# mpiovd.net
KiCad netlist of a schematic drawn in EAGLE
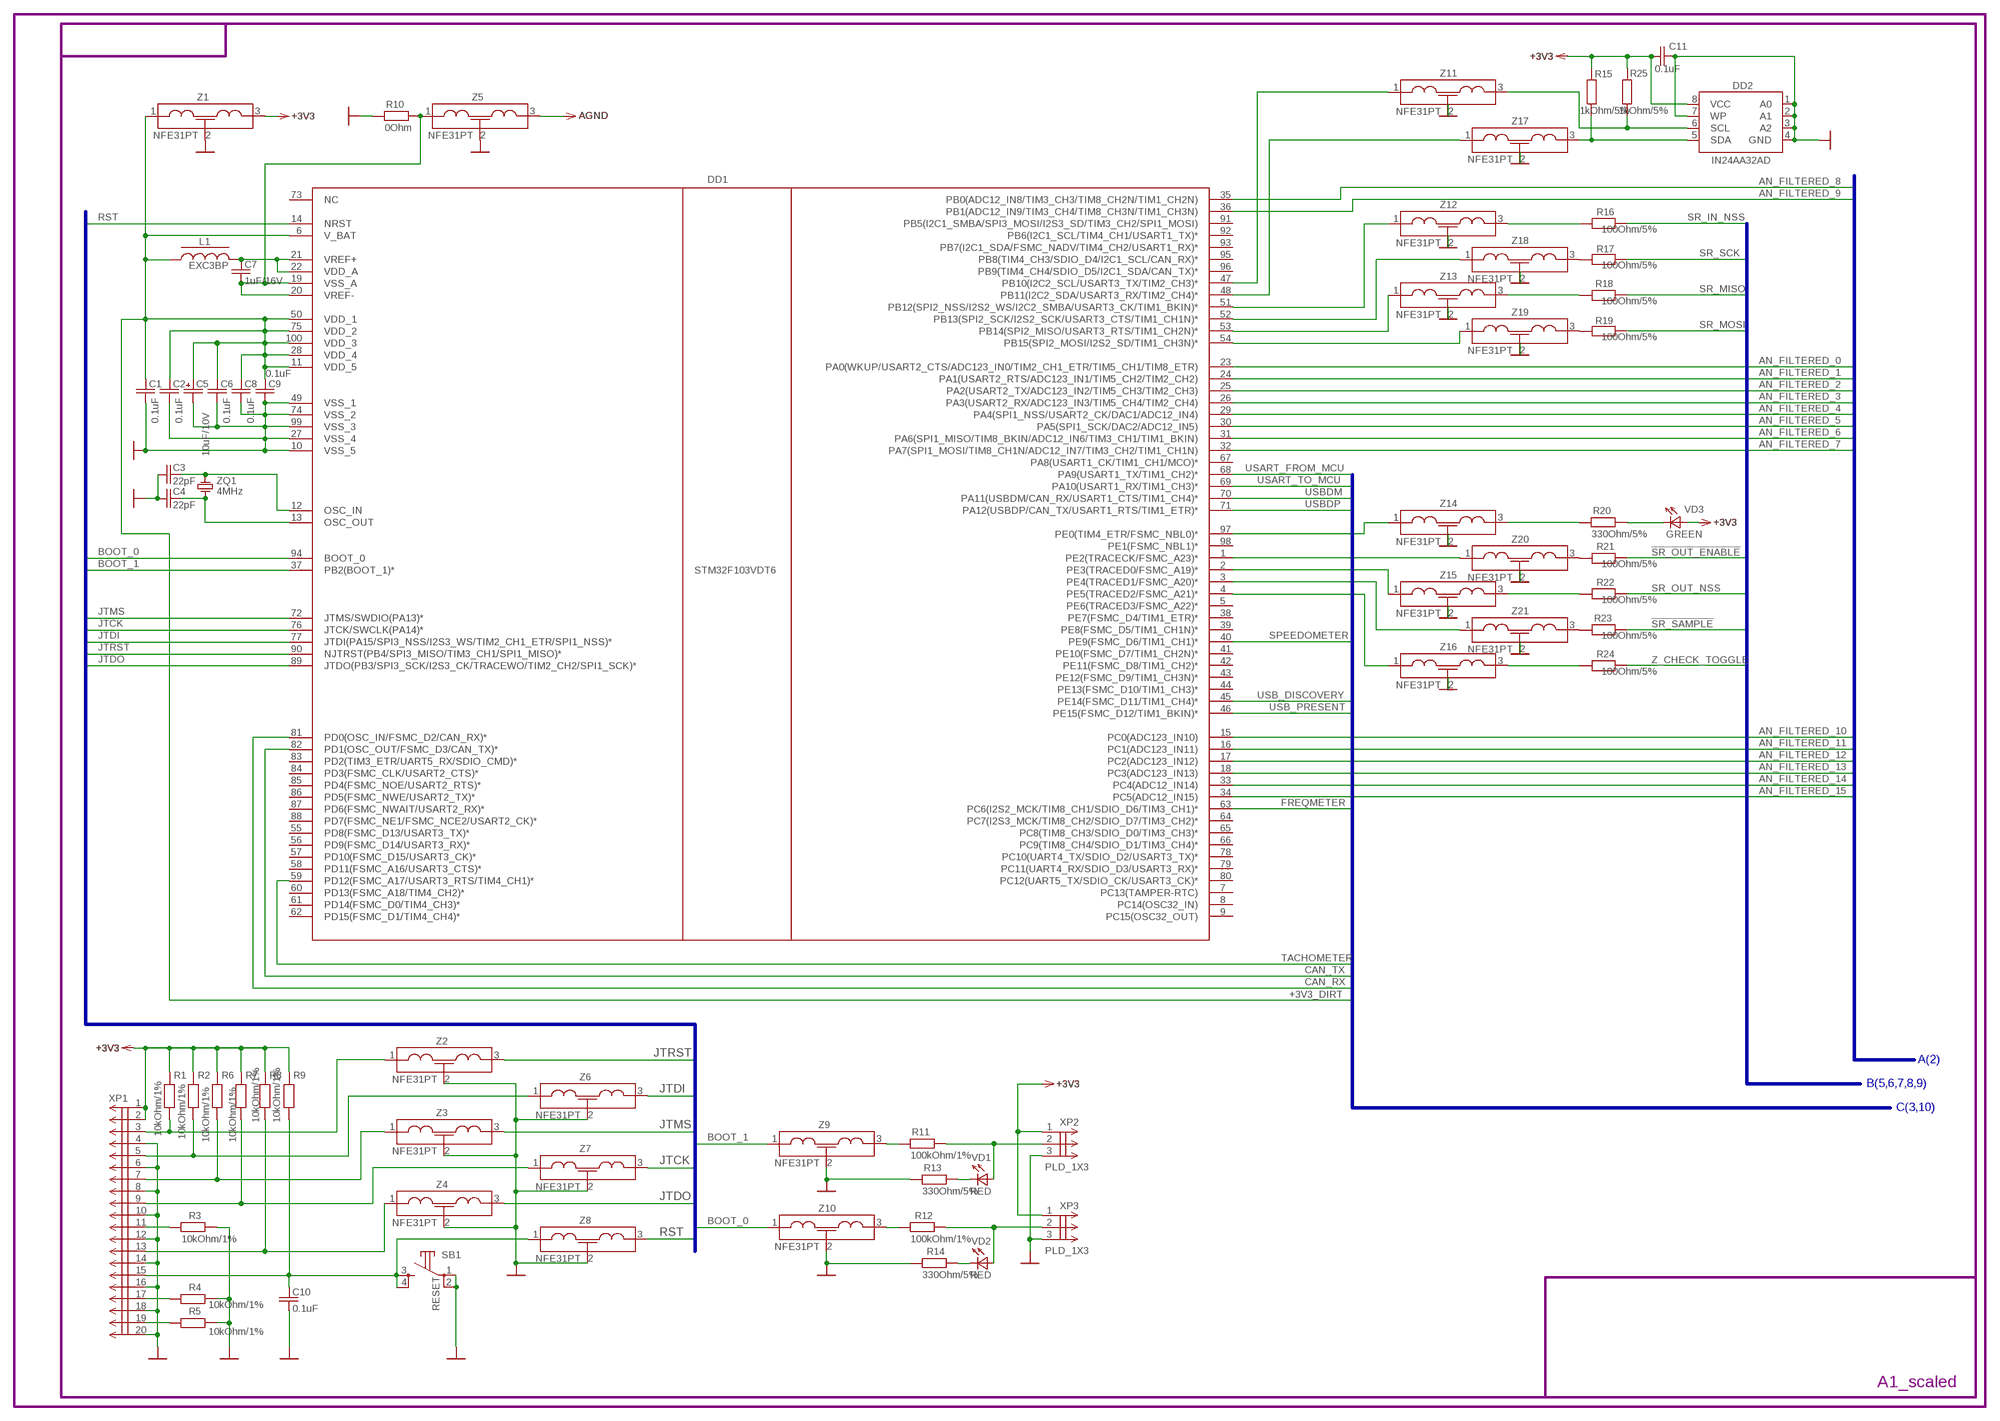
[diagram p0: schematic, sheet 1]
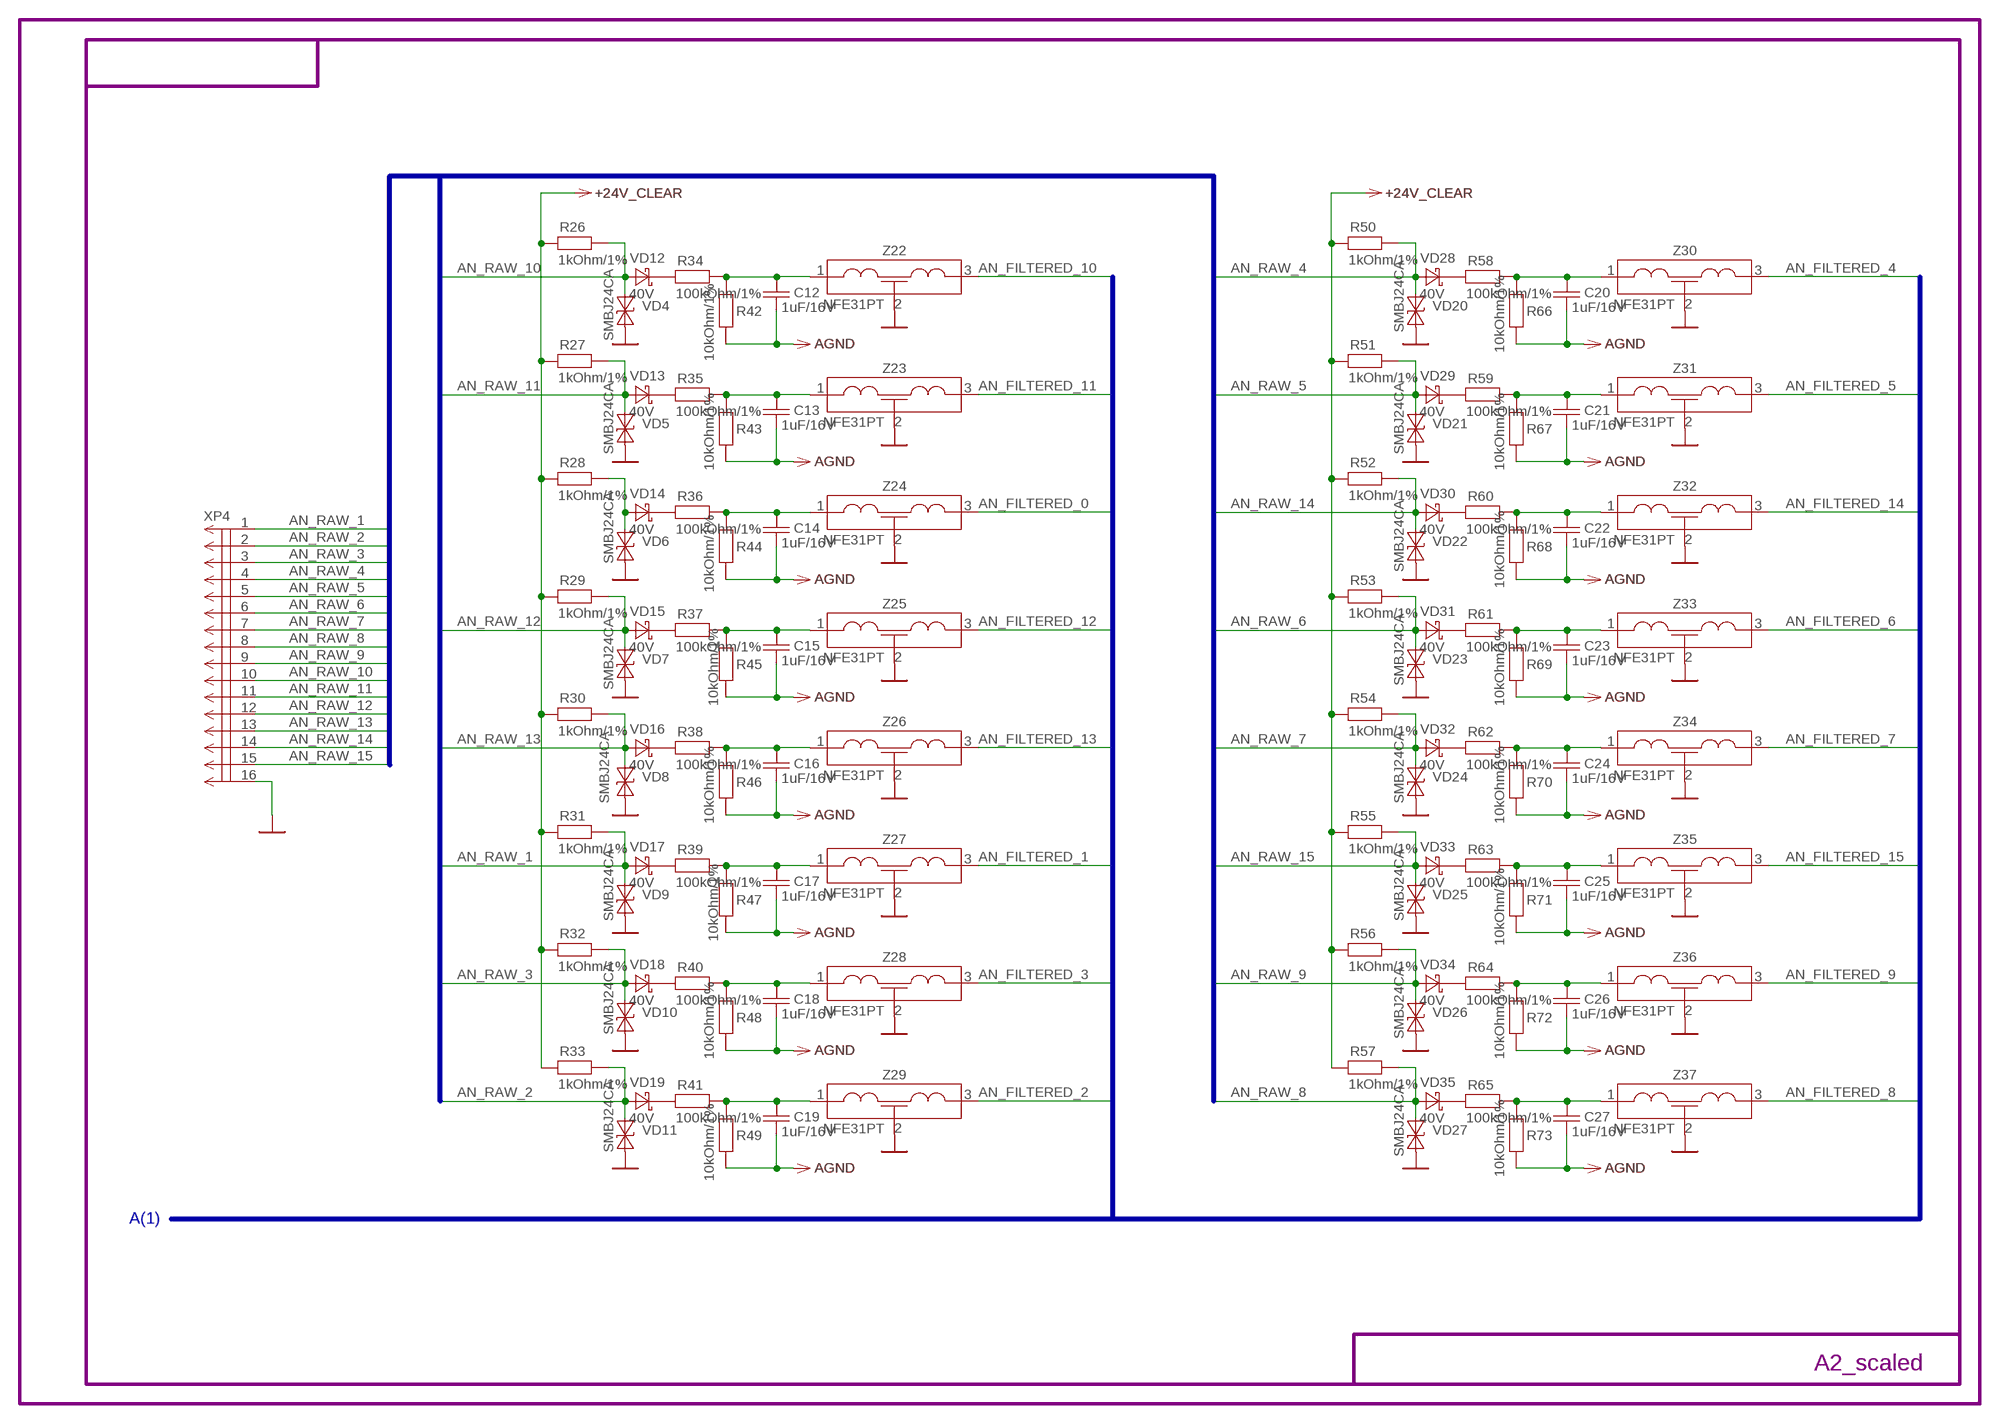
[diagram p1: schematic, sheet 2]
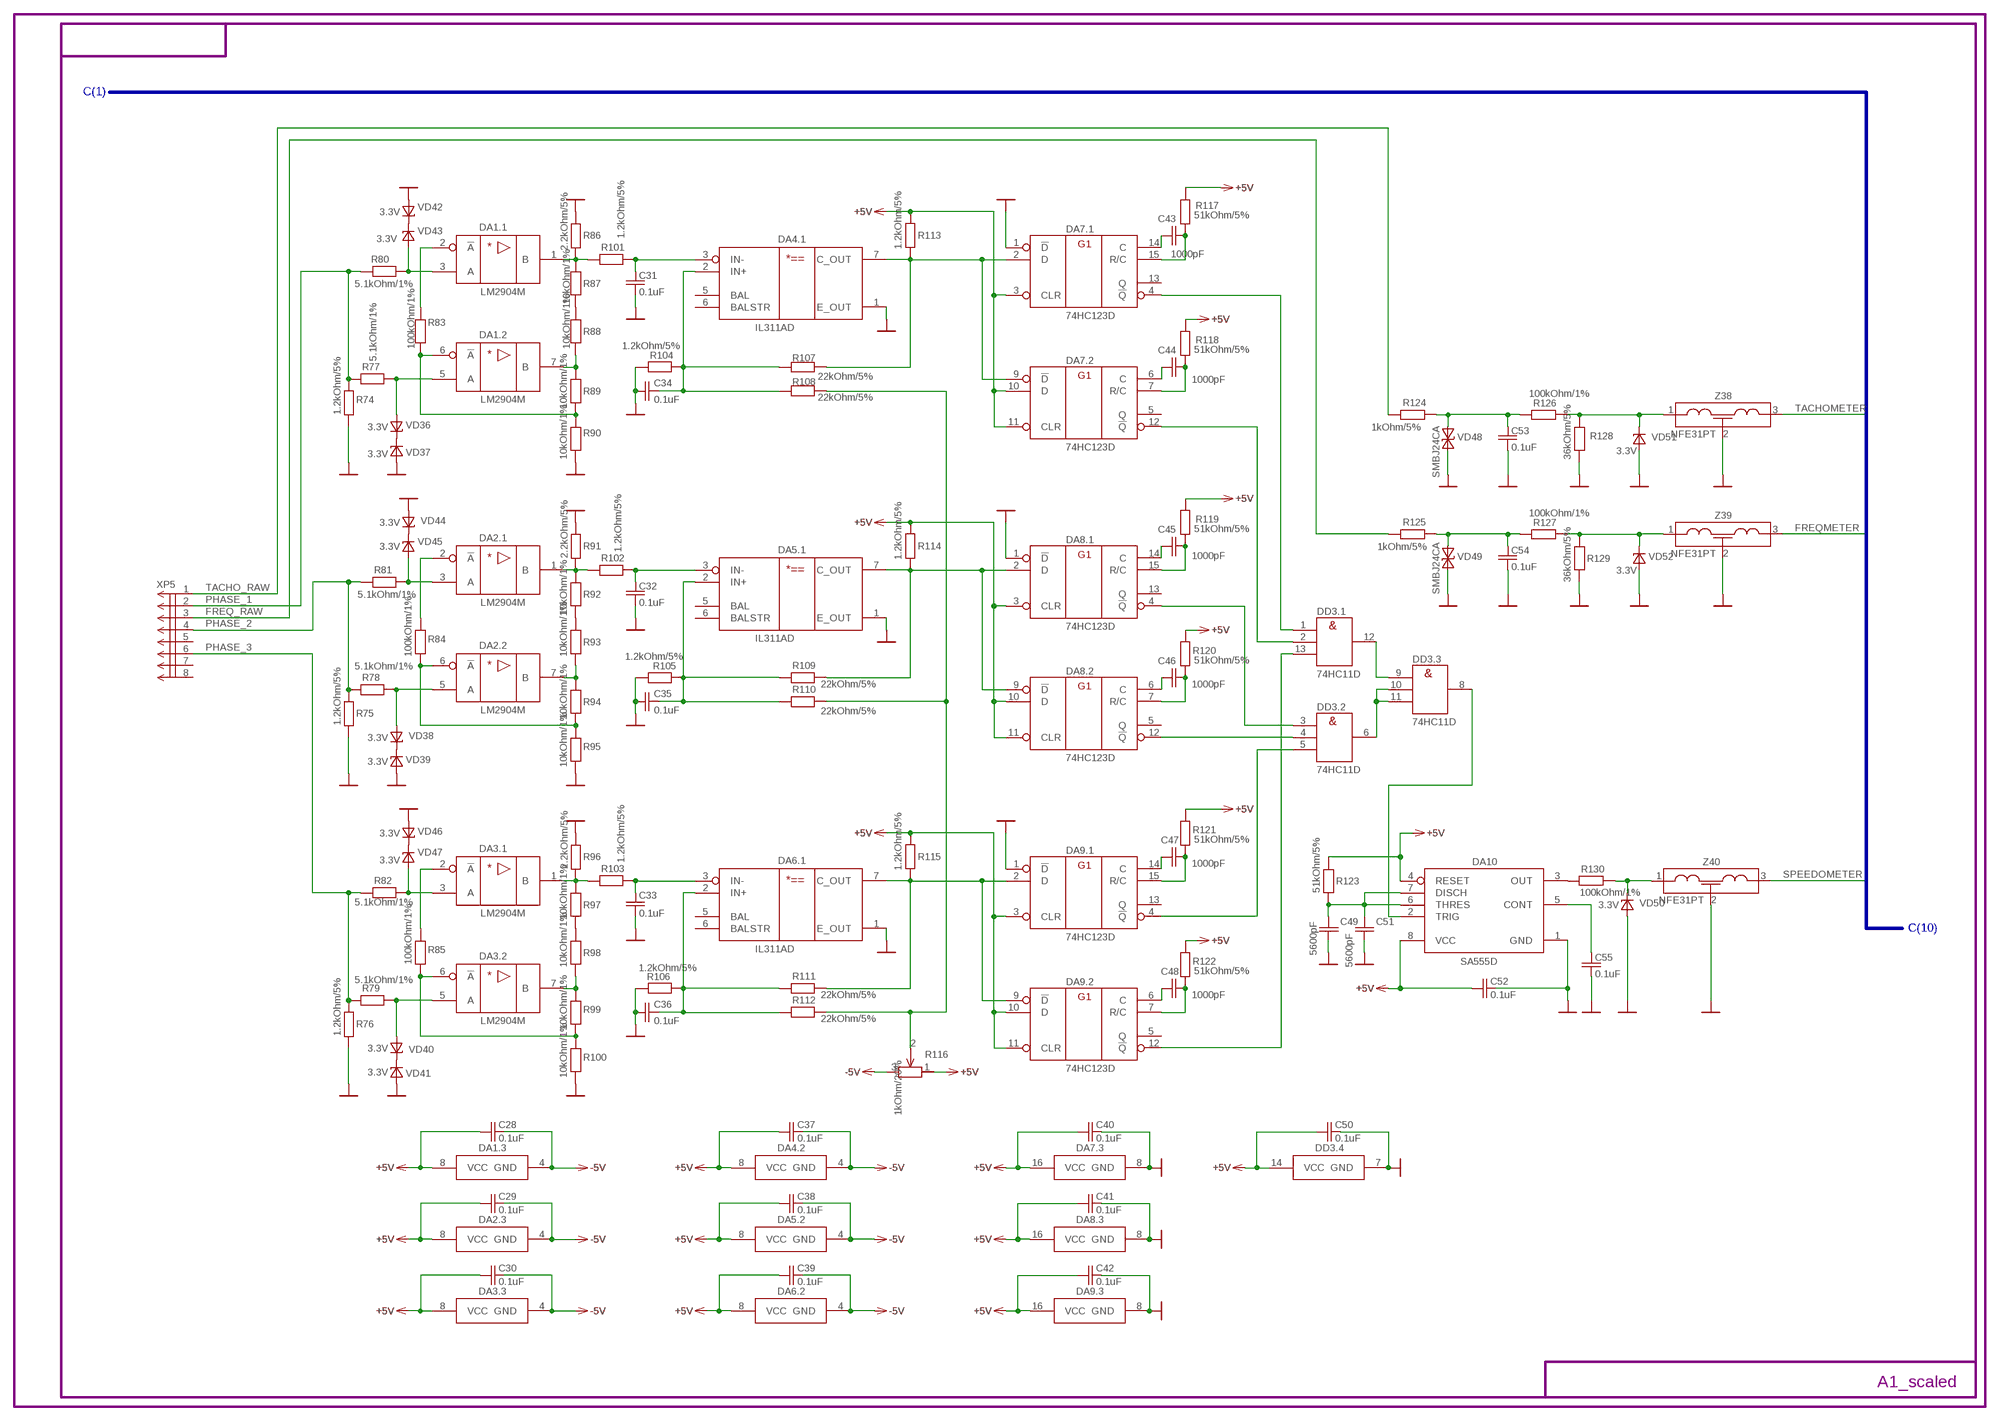
[diagram p2: schematic, sheet 3]
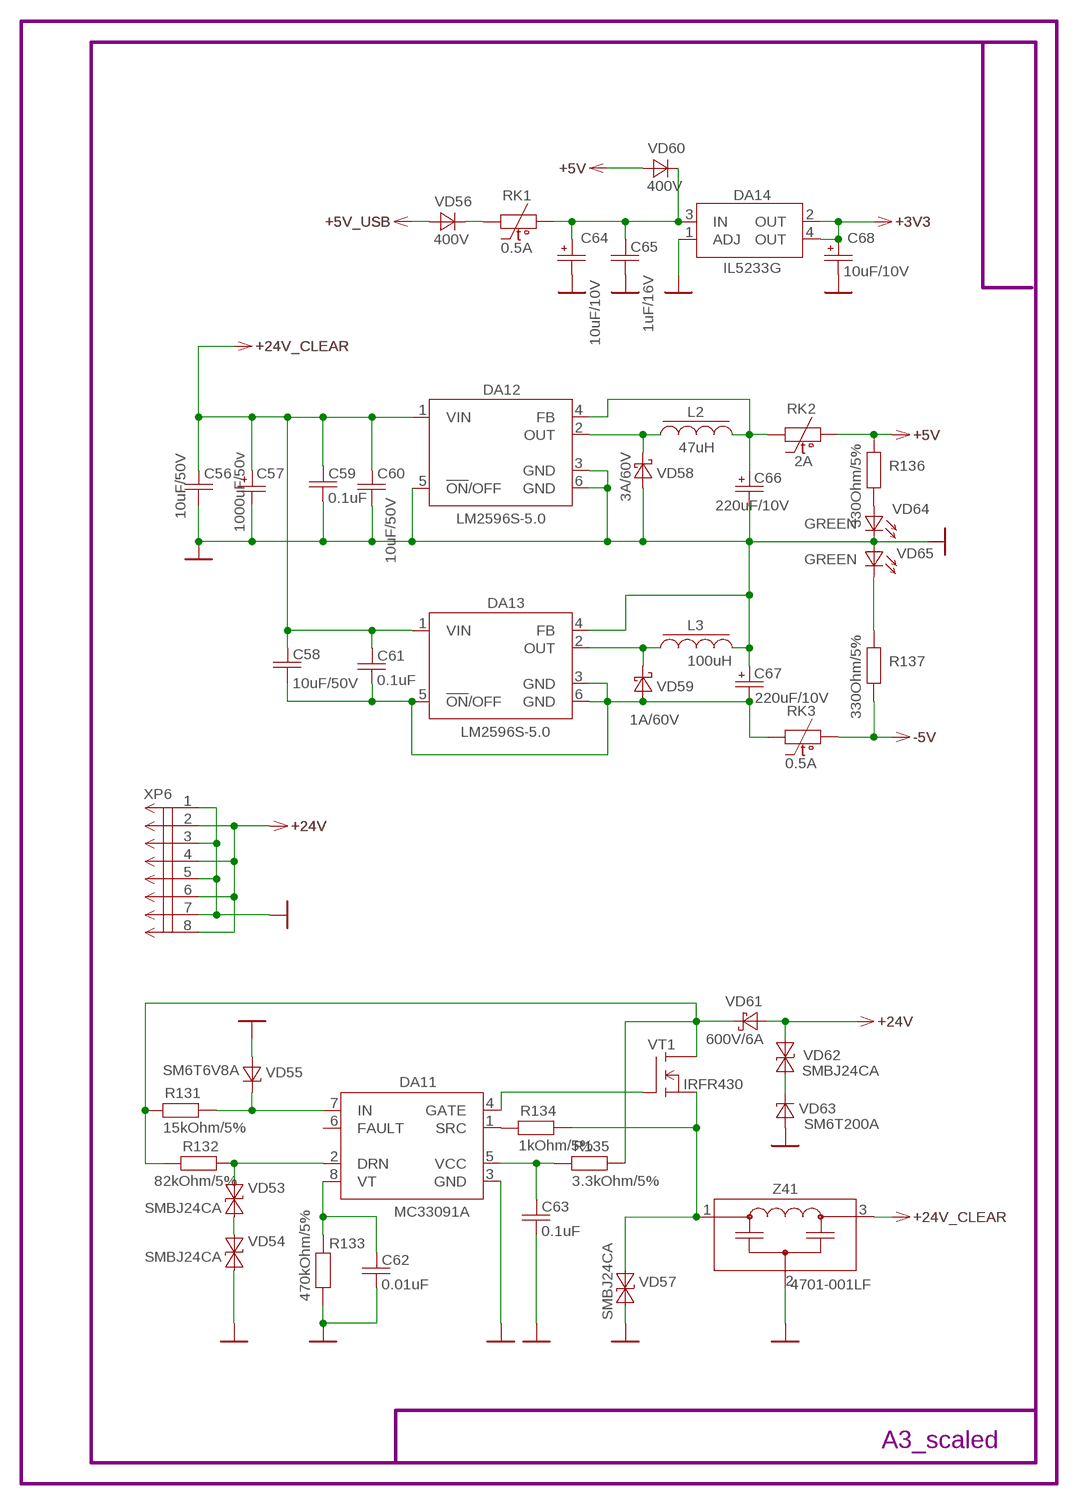
[diagram p3: schematic, sheet 4]
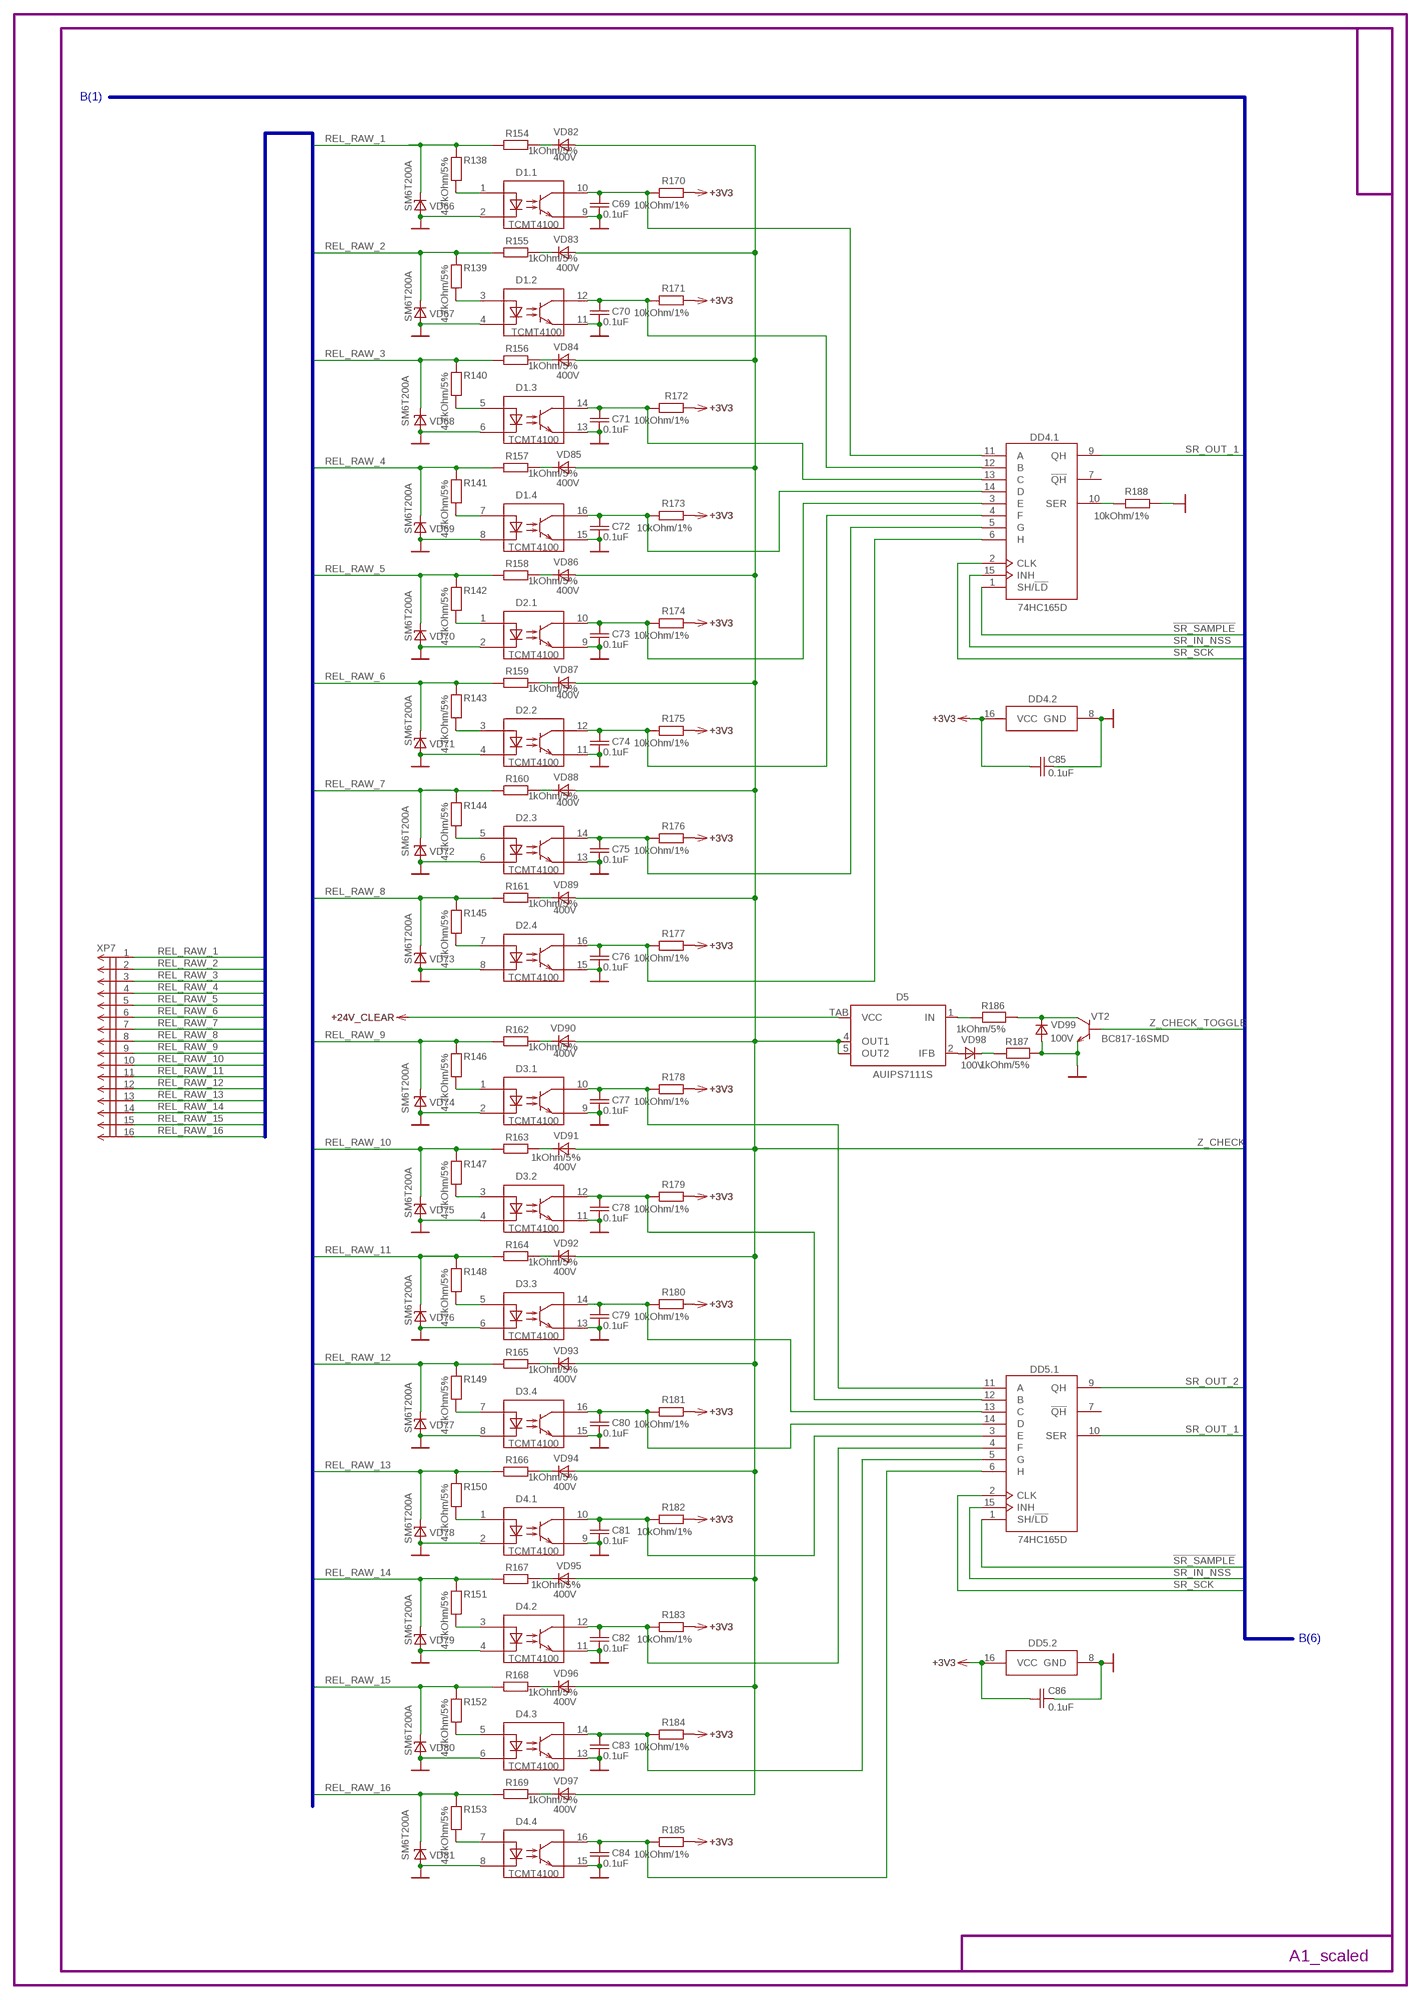
[diagram p4: schematic, sheet 5]
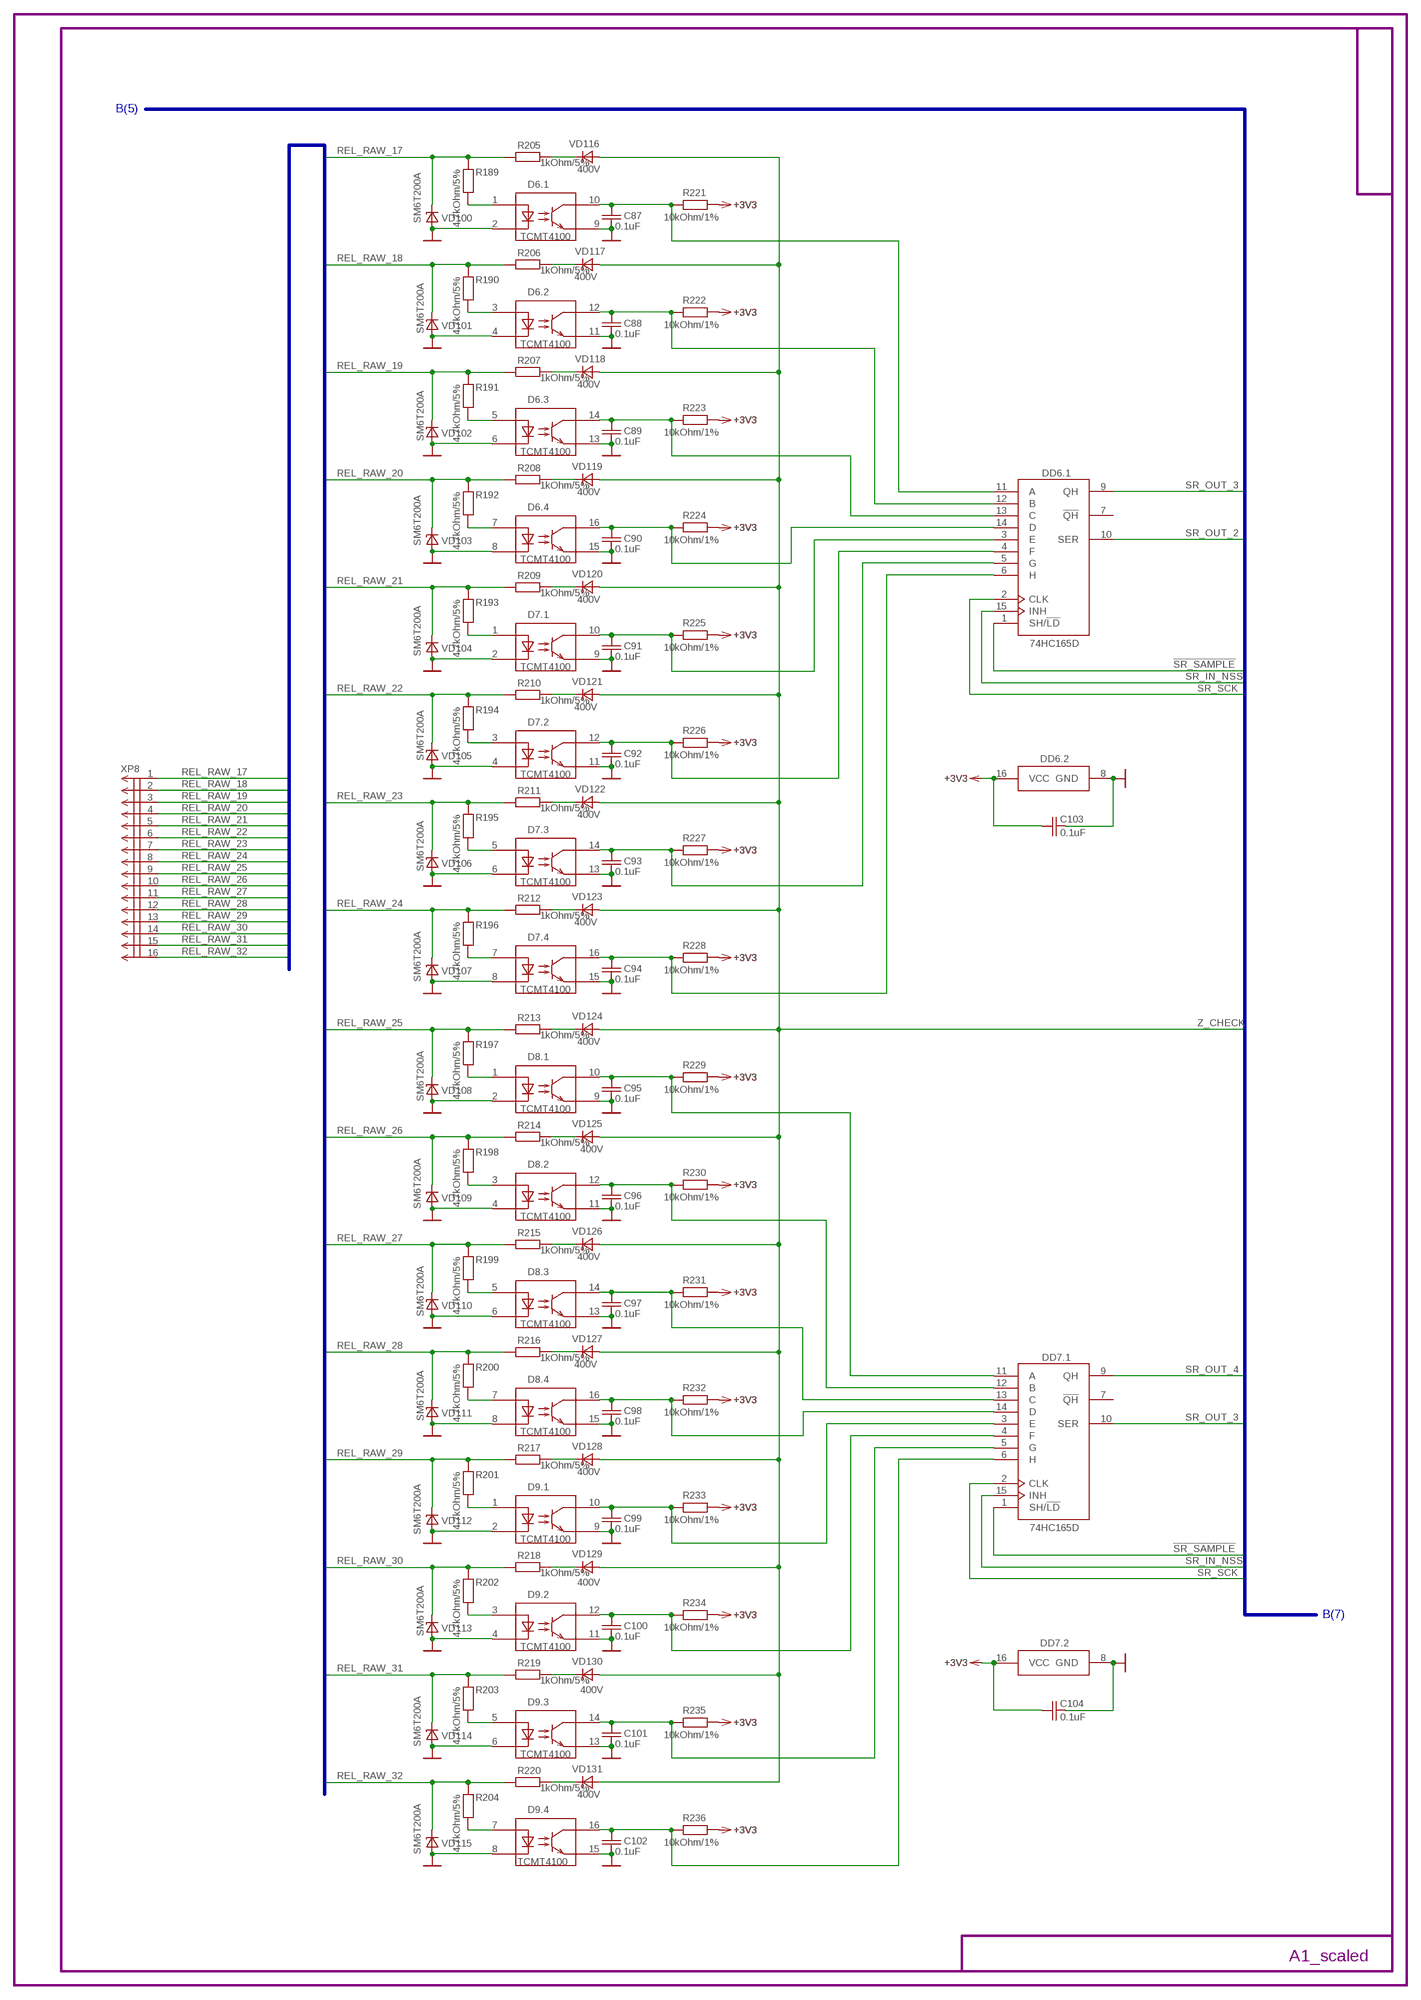
[diagram p5: schematic, sheet 6]
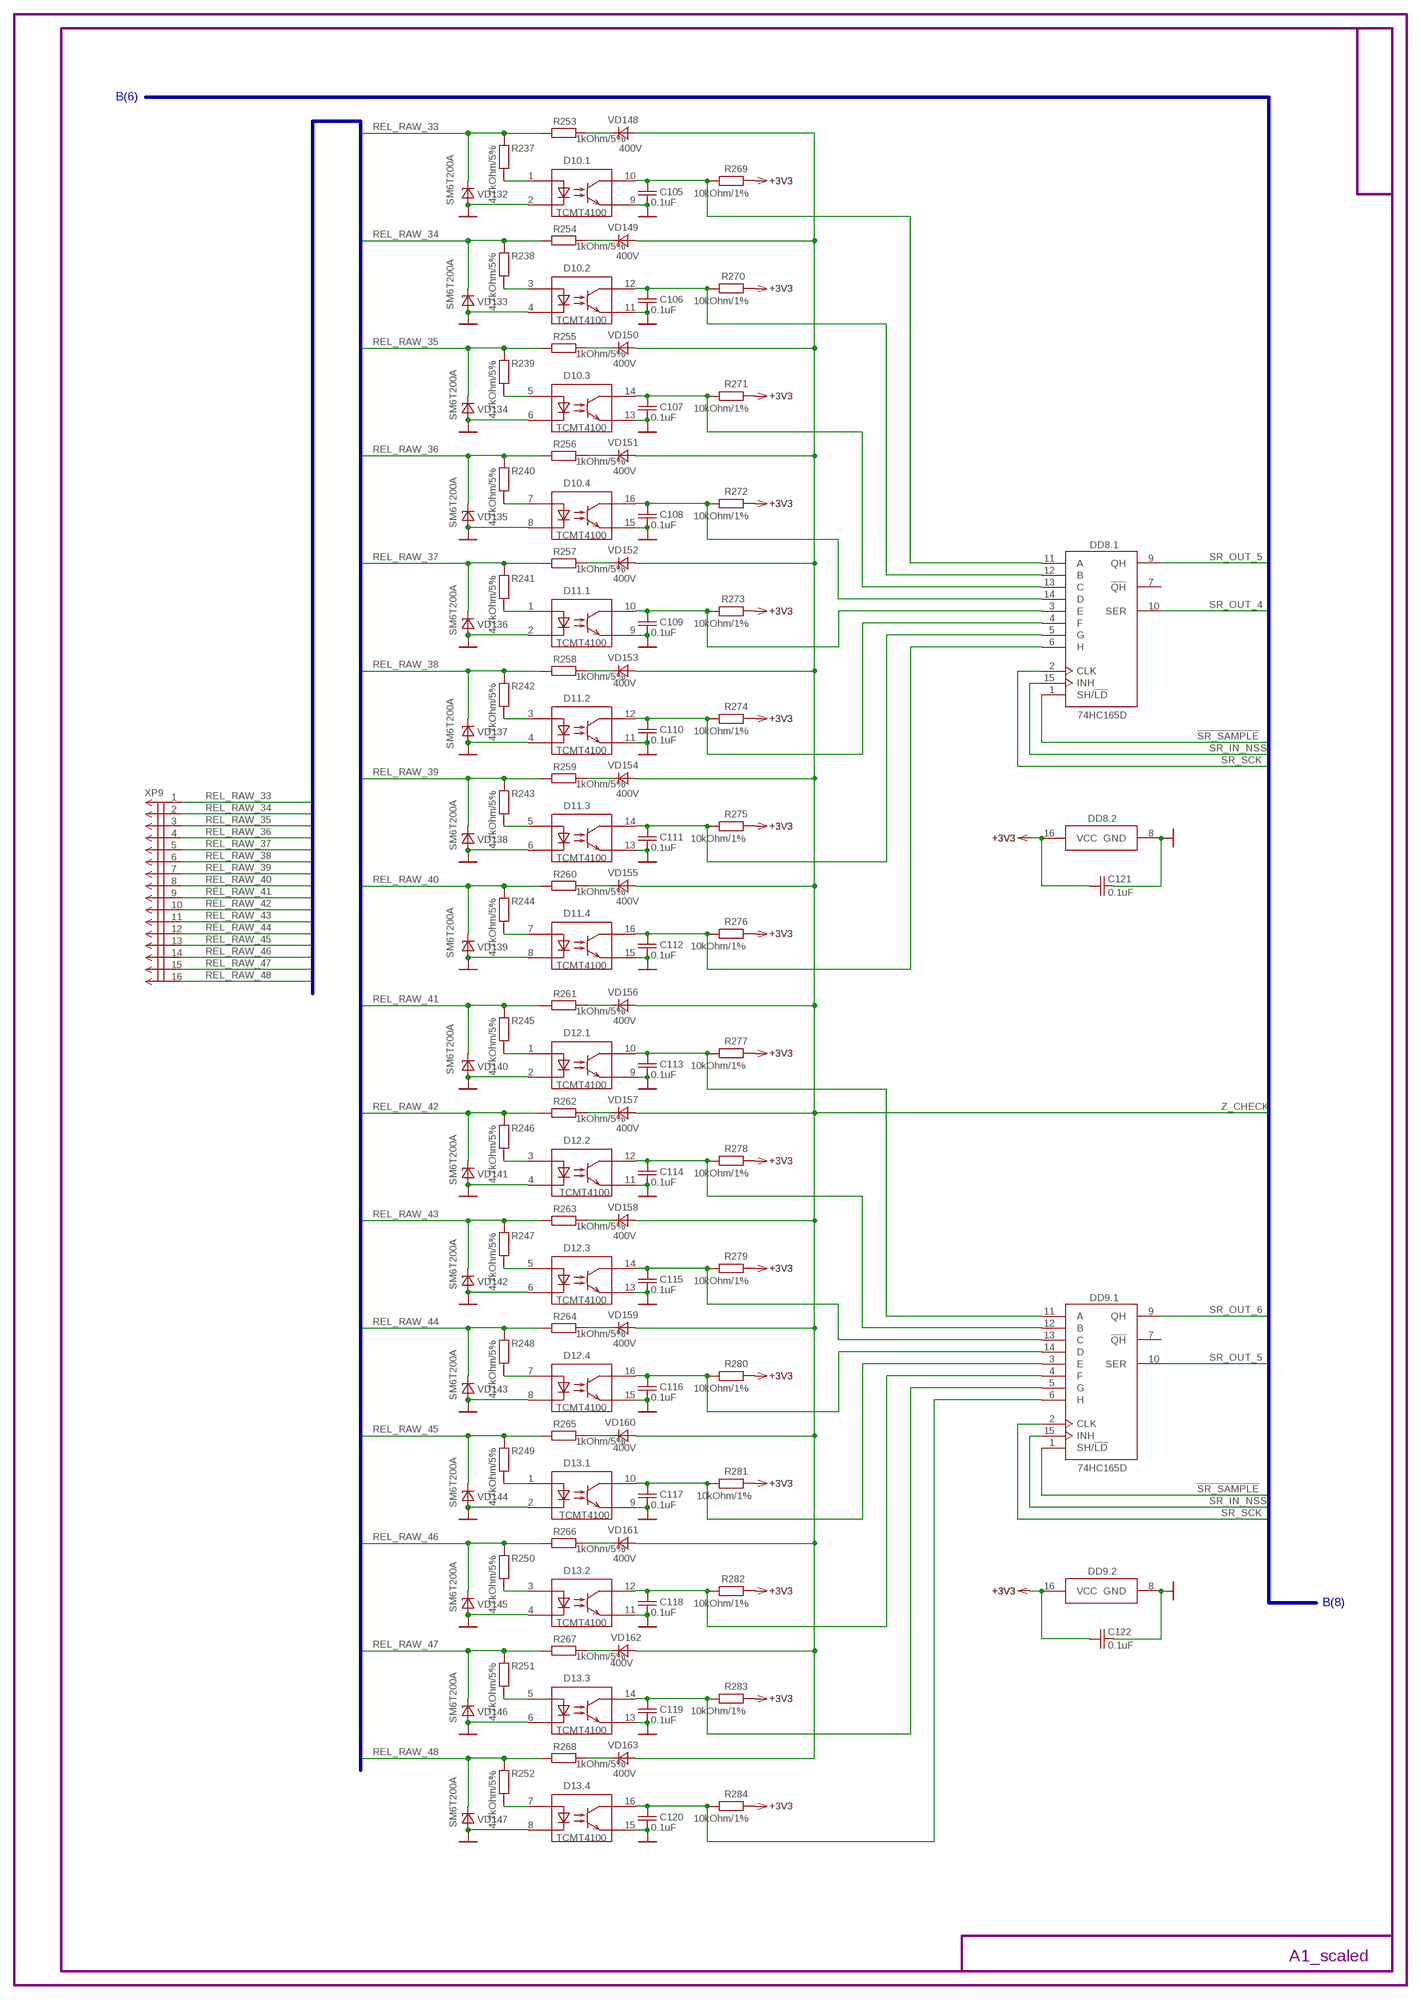
[diagram p6: schematic, sheet 7]
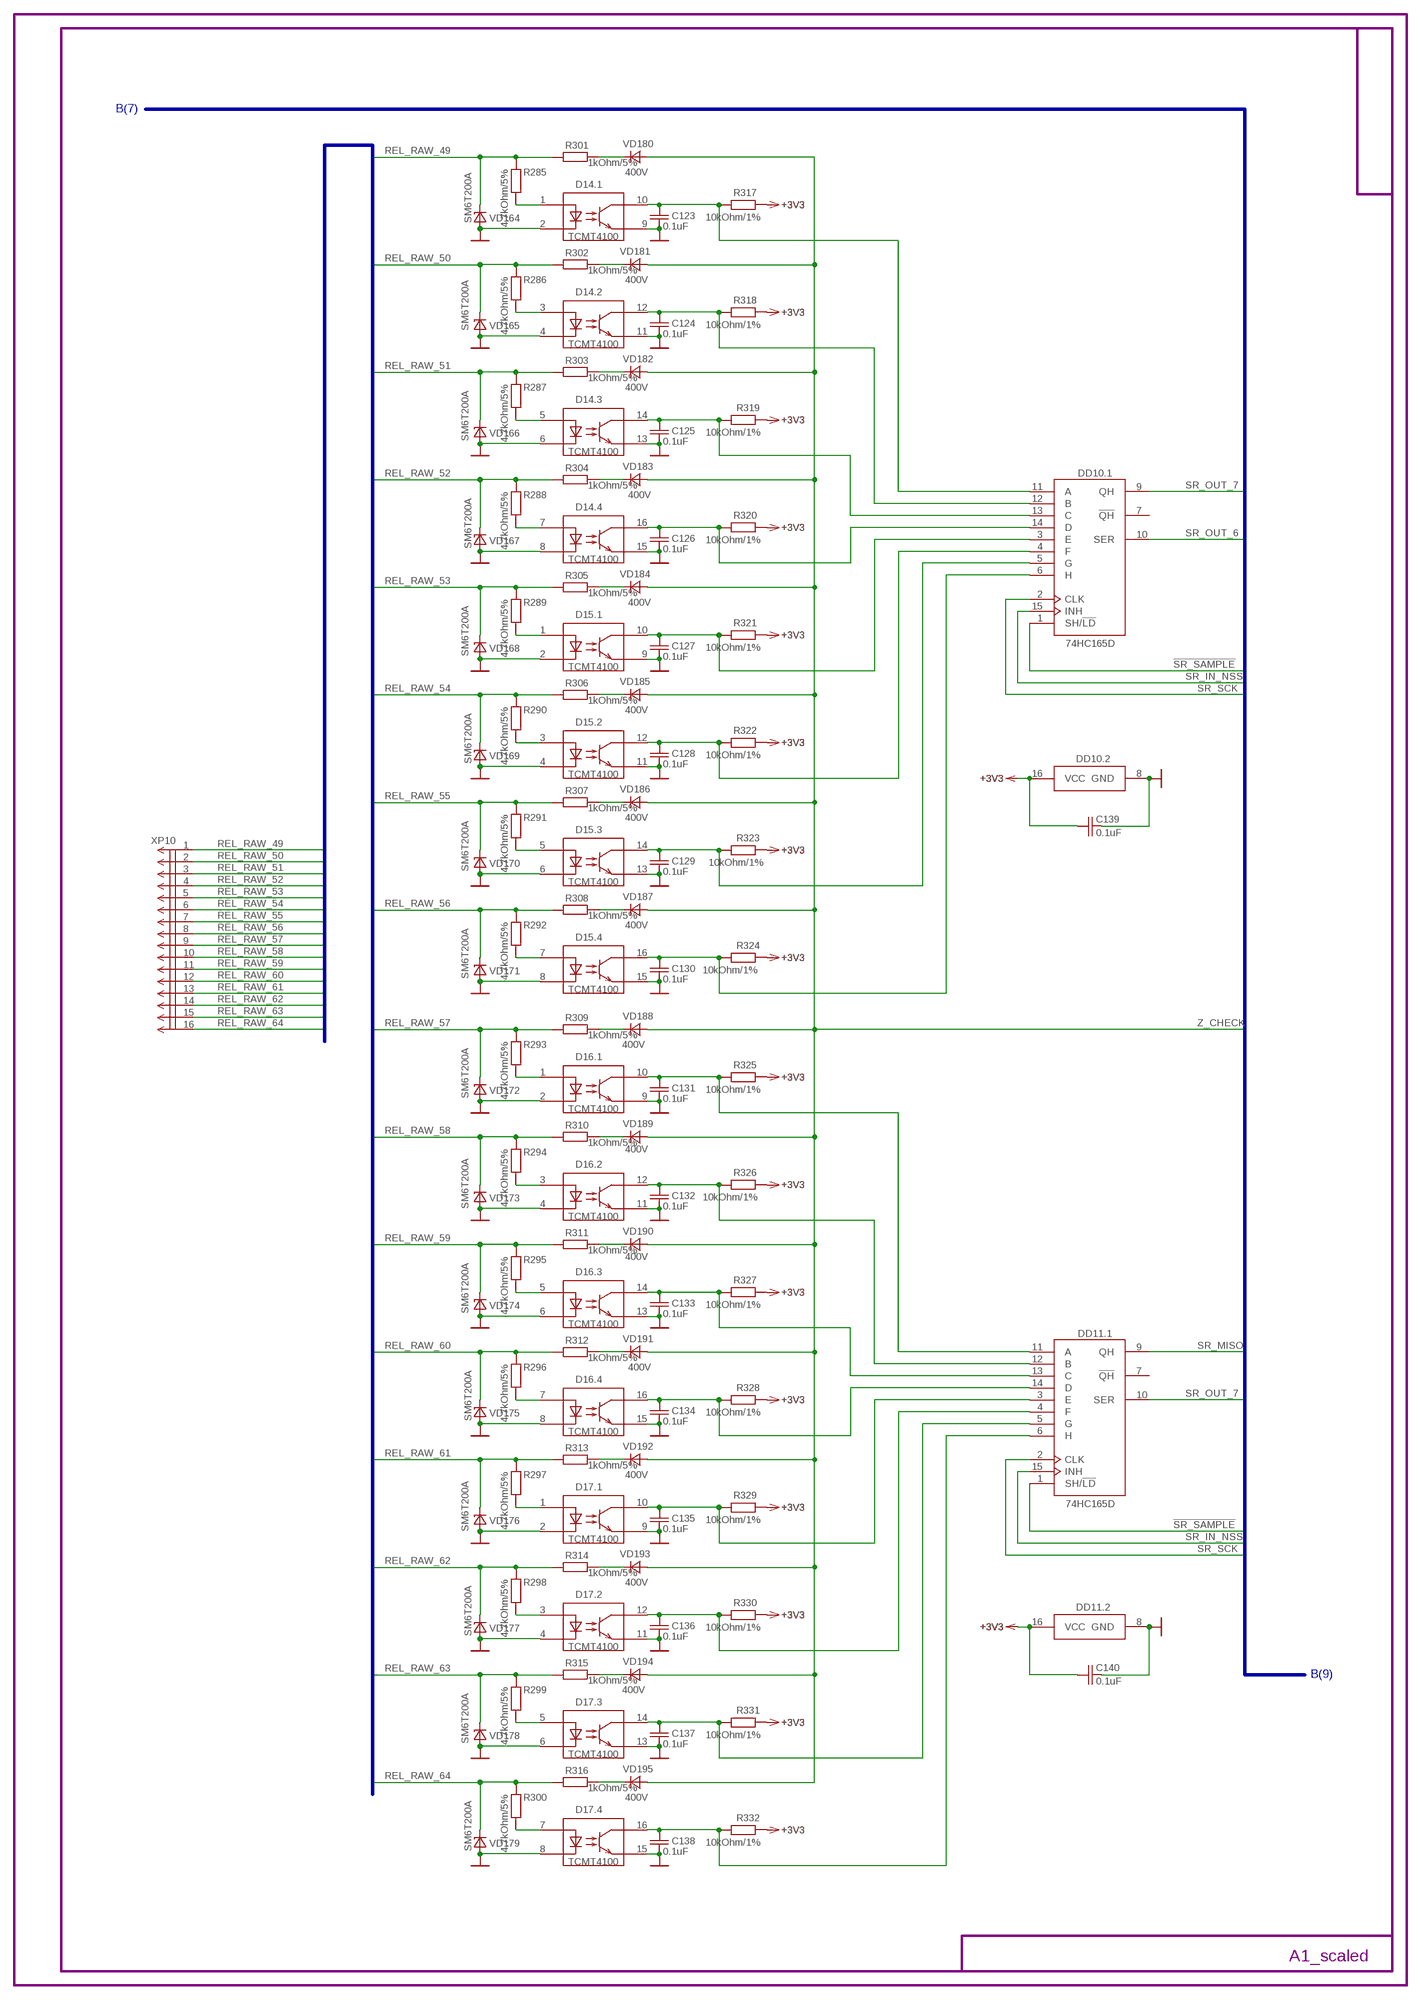
[diagram p7: schematic, sheet 8]
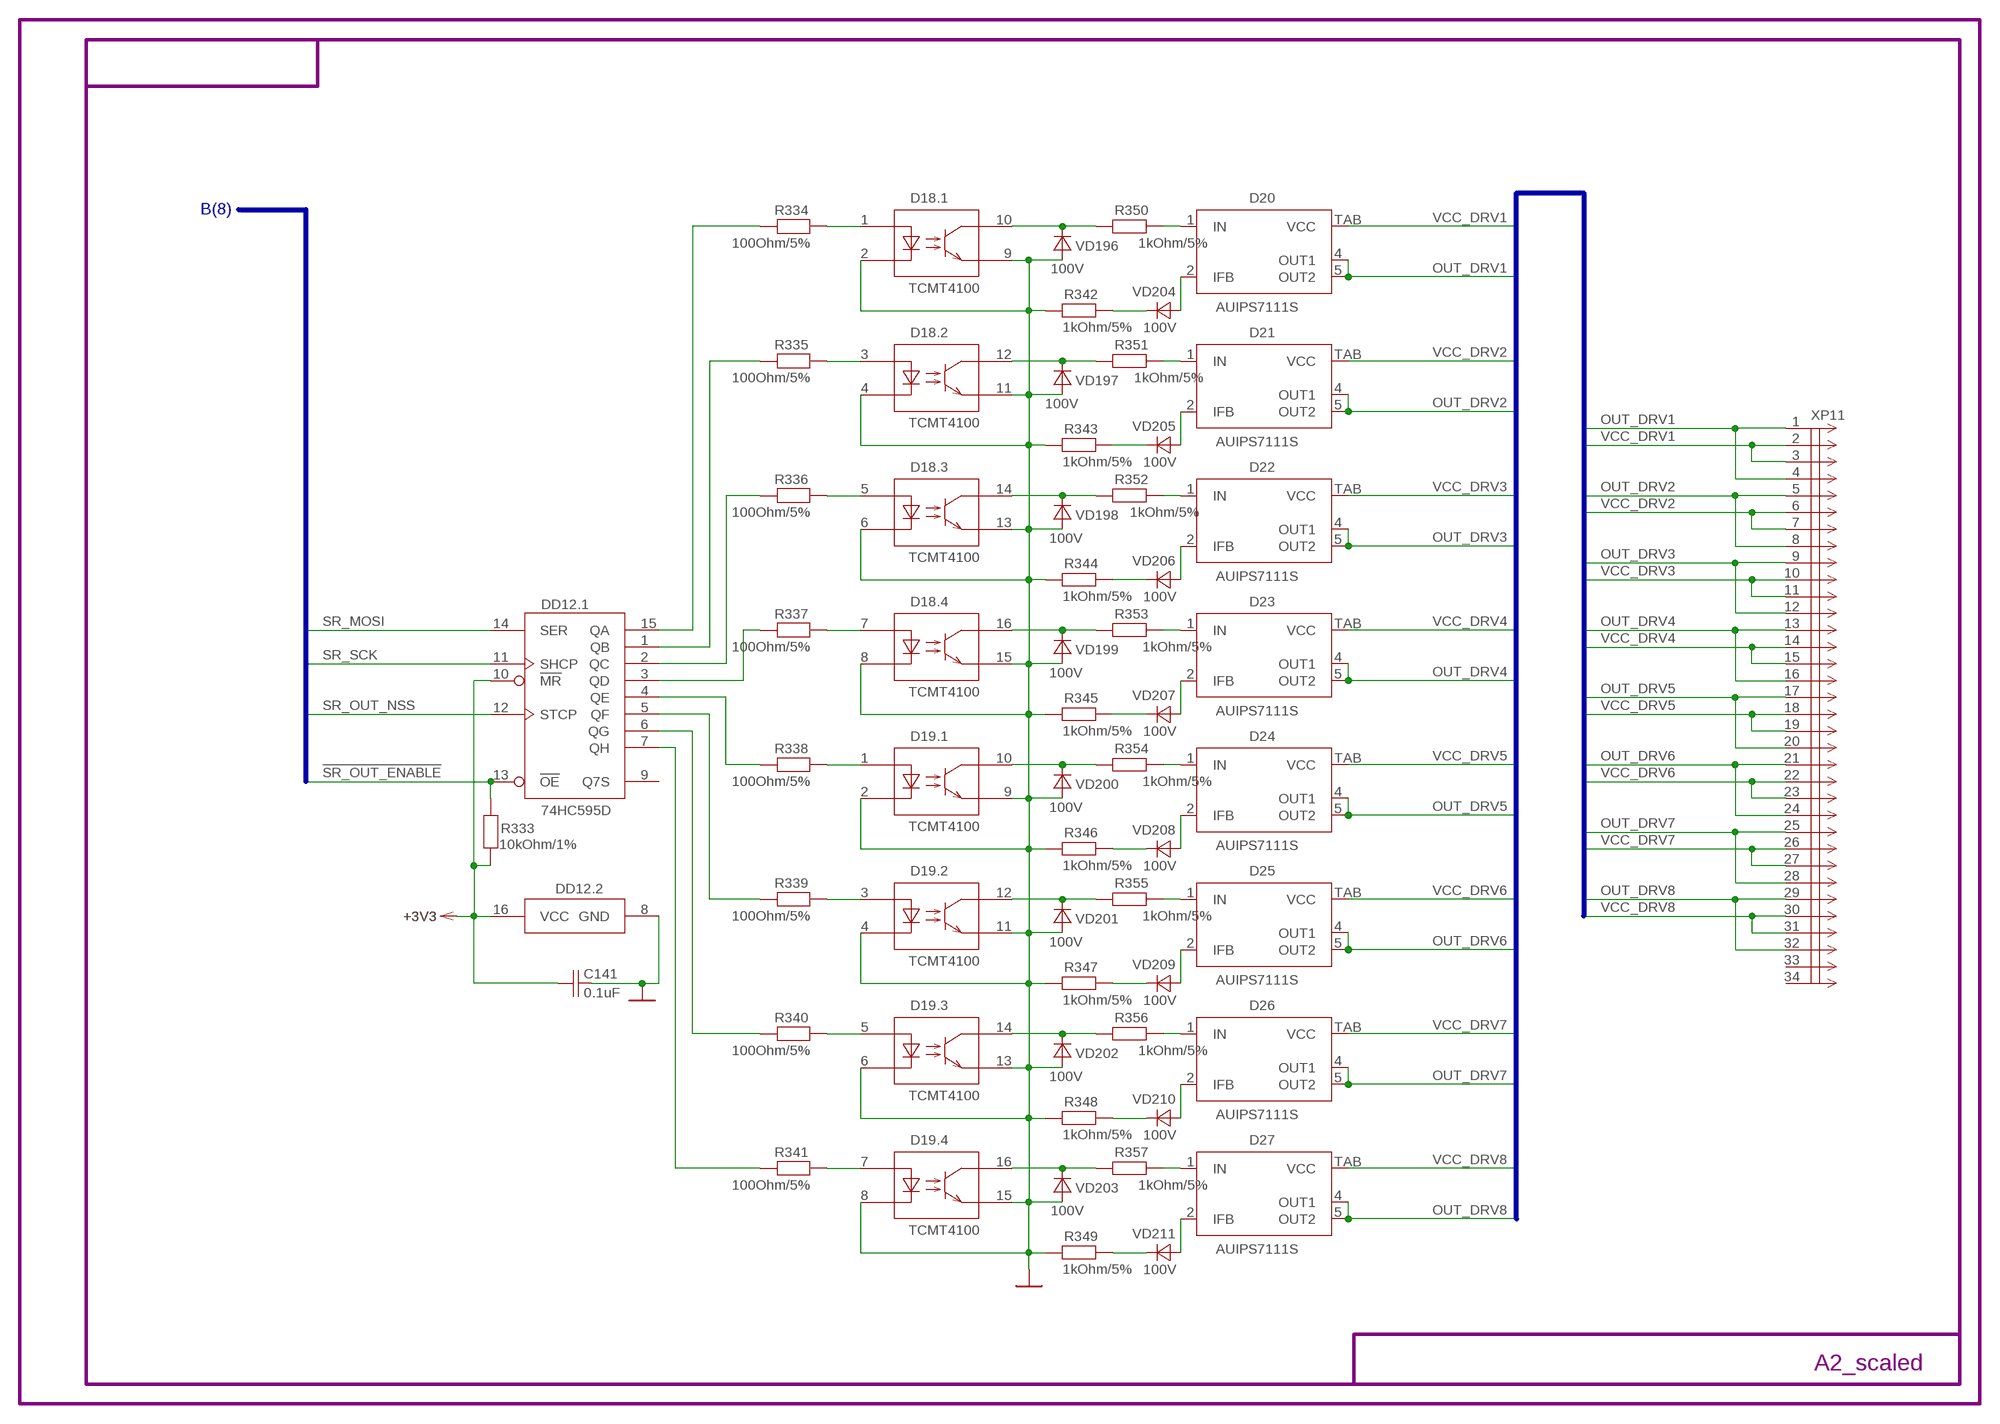
[diagram p8: schematic, sheet 9]
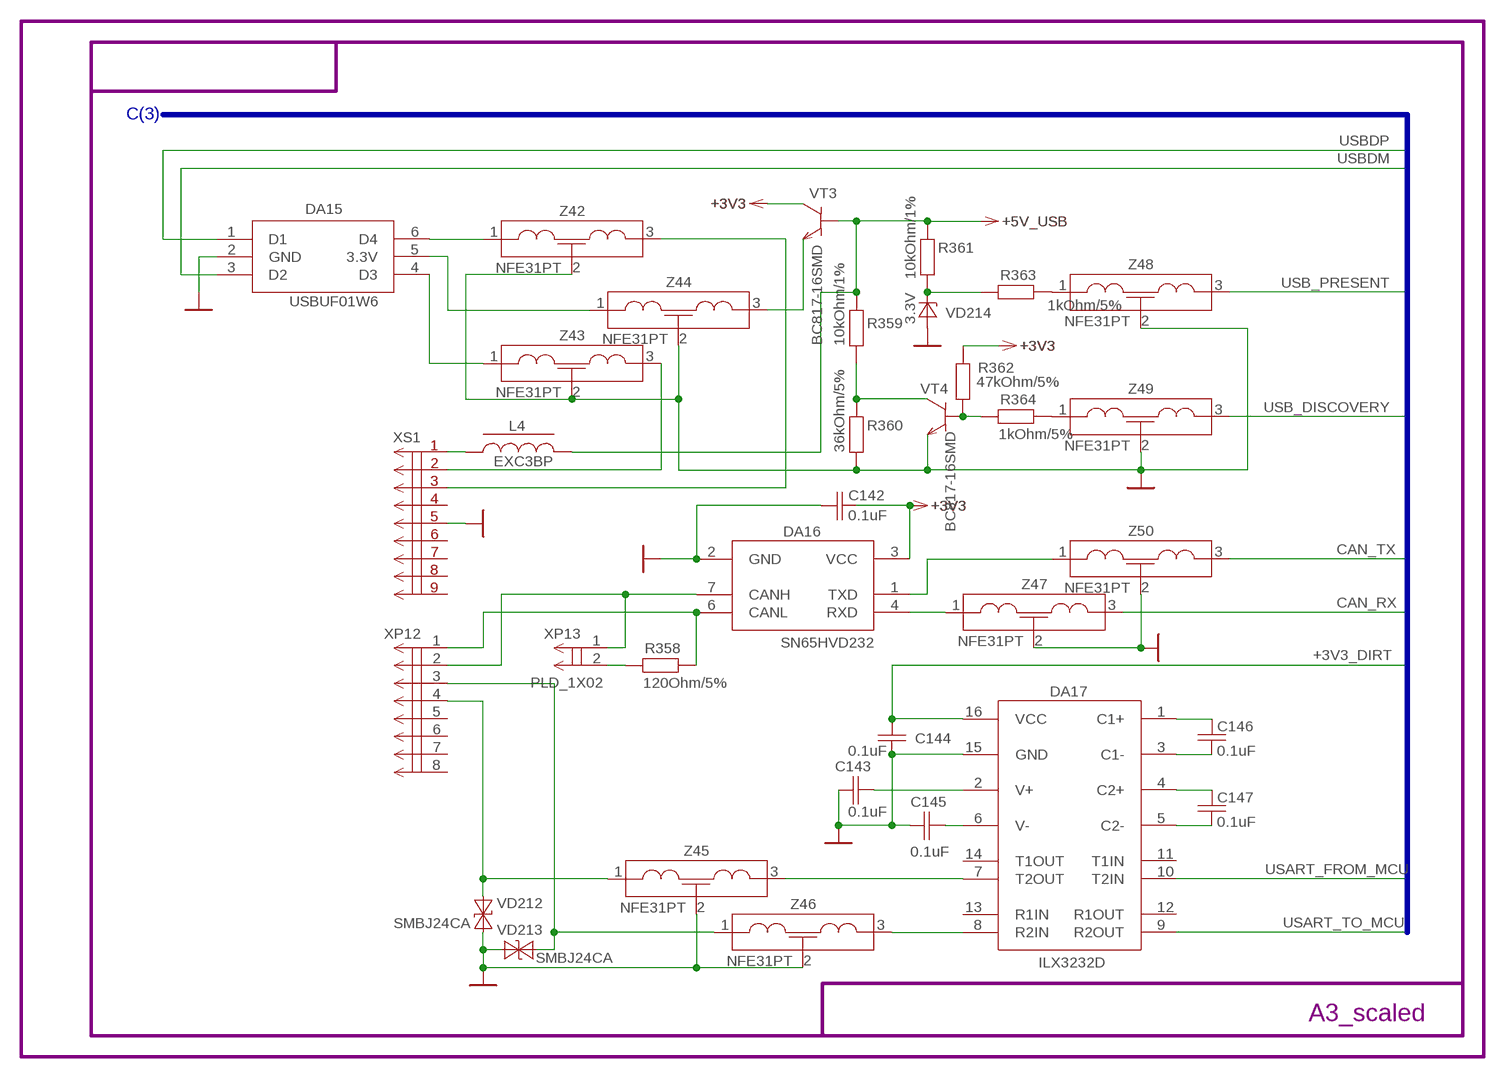
[diagram p9: schematic, sheet 10]
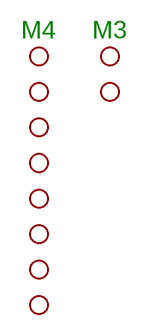
[diagram p10: schematic, sheet 11]

(export (version "E")
  (design (tool "Eeschema 10.0.6"))
  (components
    (comp (ref "C141")
      (value "0.1uF")
      (footprint "eagle-import:C0603")
      (fields (field (name "PARTNO") "C0603C104K5RACTU"))
      (libsource (lib "eagle-import") (part "C-EUC0603"))
    )
    (comp (ref "D18")
      (value "TCMT4100")
      (footprint "eagle-import:SO16")
      (fields (field (name "PARTNO") "TCMT4100"))
      (libsource (lib "eagle-import") (part "TCMT4100"))
    )
    (comp (ref "D19")
      (value "TCMT4100")
      (footprint "eagle-import:SO16")
      (fields (field (name "PARTNO") "TCMT4100"))
      (libsource (lib "eagle-import") (part "TCMT4100"))
    )
    (comp (ref "D20")
      (value "AUIPS7111S")
      (footprint "eagle-import:TO252-5-11")
      (libsource (lib "eagle-import") (part "AUIPS7111S"))
    )
    (comp (ref "D21")
      (value "AUIPS7111S")
      (footprint "eagle-import:TO252-5-11")
      (libsource (lib "eagle-import") (part "AUIPS7111S"))
    )
    (comp (ref "D22")
      (value "AUIPS7111S")
      (footprint "eagle-import:TO252-5-11")
      (libsource (lib "eagle-import") (part "AUIPS7111S"))
    )
    (comp (ref "D23")
      (value "AUIPS7111S")
      (footprint "eagle-import:TO252-5-11")
      (libsource (lib "eagle-import") (part "AUIPS7111S"))
    )
    (comp (ref "D24")
      (value "AUIPS7111S")
      (footprint "eagle-import:TO252-5-11")
      (libsource (lib "eagle-import") (part "AUIPS7111S"))
    )
    (comp (ref "D25")
      (value "AUIPS7111S")
      (footprint "eagle-import:TO252-5-11")
      (libsource (lib "eagle-import") (part "AUIPS7111S"))
    )
    (comp (ref "D26")
      (value "AUIPS7111S")
      (footprint "eagle-import:TO252-5-11")
      (libsource (lib "eagle-import") (part "AUIPS7111S"))
    )
    (comp (ref "D27")
      (value "AUIPS7111S")
      (footprint "eagle-import:TO252-5-11")
      (libsource (lib "eagle-import") (part "AUIPS7111S"))
    )
    (comp (ref "DD12")
      (value "74HC595D")
      (footprint "eagle-import:SO16")
      (fields (field (name "PARTNO") "IN74HC595AD"))
      (libsource (lib "eagle-import") (part "74595DHC"))
    )
    (comp (ref "R333")
      (value "10kOhm/1%")
      (footprint "eagle-import:R0603")
      (fields (field (name "PARTNO") "RC0603FR-1010KL"))
      (libsource (lib "eagle-import") (part "R-EU_R0603"))
    )
    (comp (ref "R334")
      (value "100Ohm/5%")
      (footprint "eagle-import:R0603")
      (fields (field (name "PARTNO") "ERJ3GEYJ101V"))
      (libsource (lib "eagle-import") (part "R-EU_R0603"))
    )
    (comp (ref "R335")
      (value "100Ohm/5%")
      (footprint "eagle-import:R0603")
      (fields (field (name "PARTNO") "ERJ3GEYJ101V"))
      (libsource (lib "eagle-import") (part "R-EU_R0603"))
    )
    (comp (ref "R336")
      (value "100Ohm/5%")
      (footprint "eagle-import:R0603")
      (fields (field (name "PARTNO") "ERJ3GEYJ101V"))
      (libsource (lib "eagle-import") (part "R-EU_R0603"))
    )
    (comp (ref "R337")
      (value "100Ohm/5%")
      (footprint "eagle-import:R0603")
      (fields (field (name "PARTNO") "ERJ3GEYJ101V"))
      (libsource (lib "eagle-import") (part "R-EU_R0603"))
    )
    (comp (ref "R338")
      (value "100Ohm/5%")
      (footprint "eagle-import:R0603")
      (fields (field (name "PARTNO") "ERJ3GEYJ101V"))
      (libsource (lib "eagle-import") (part "R-EU_R0603"))
    )
    (comp (ref "R339")
      (value "100Ohm/5%")
      (footprint "eagle-import:R0603")
      (fields (field (name "PARTNO") "ERJ3GEYJ101V"))
      (libsource (lib "eagle-import") (part "R-EU_R0603"))
    )
    (comp (ref "R340")
      (value "100Ohm/5%")
      (footprint "eagle-import:R0603")
      (fields (field (name "PARTNO") "ERJ3GEYJ101V"))
      (libsource (lib "eagle-import") (part "R-EU_R0603"))
    )
    (comp (ref "R341")
      (value "100Ohm/5%")
      (footprint "eagle-import:R0603")
      (fields (field (name "PARTNO") "ERJ3GEYJ101V"))
      (libsource (lib "eagle-import") (part "R-EU_R0603"))
    )
    (comp (ref "R342")
      (value "1kOhm/5%")
      (footprint "eagle-import:R0805")
      (fields (field (name "PARTNO") "ERJ6GEYJ102V"))
      (libsource (lib "eagle-import") (part "R-EU_R0805"))
    )
    (comp (ref "R343")
      (value "1kOhm/5%")
      (footprint "eagle-import:R0805")
      (fields (field (name "PARTNO") "ERJ6GEYJ102V"))
      (libsource (lib "eagle-import") (part "R-EU_R0805"))
    )
    (comp (ref "R344")
      (value "1kOhm/5%")
      (footprint "eagle-import:R0805")
      (fields (field (name "PARTNO") "ERJ6GEYJ102V"))
      (libsource (lib "eagle-import") (part "R-EU_R0805"))
    )
    (comp (ref "R345")
      (value "1kOhm/5%")
      (footprint "eagle-import:R0805")
      (fields (field (name "PARTNO") "ERJ6GEYJ102V"))
      (libsource (lib "eagle-import") (part "R-EU_R0805"))
    )
    (comp (ref "R346")
      (value "1kOhm/5%")
      (footprint "eagle-import:R0805")
      (fields (field (name "PARTNO") "ERJ6GEYJ102V"))
      (libsource (lib "eagle-import") (part "R-EU_R0805"))
    )
    (comp (ref "R347")
      (value "1kOhm/5%")
      (footprint "eagle-import:R0805")
      (fields (field (name "PARTNO") "ERJ6GEYJ102V"))
      (libsource (lib "eagle-import") (part "R-EU_R0805"))
    )
    (comp (ref "R348")
      (value "1kOhm/5%")
      (footprint "eagle-import:R0805")
      (fields (field (name "PARTNO") "ERJ6GEYJ102V"))
      (libsource (lib "eagle-import") (part "R-EU_R0805"))
    )
    (comp (ref "R349")
      (value "1kOhm/5%")
      (footprint "eagle-import:R0805")
      (fields (field (name "PARTNO") "ERJ6GEYJ102V"))
      (libsource (lib "eagle-import") (part "R-EU_R0805"))
    )
    (comp (ref "R350")
      (value "1kOhm/5%")
      (footprint "eagle-import:R0805")
      (fields (field (name "PARTNO") "ERJ6GEYJ102V"))
      (libsource (lib "eagle-import") (part "R-EU_R0805"))
    )
    (comp (ref "R351")
      (value "1kOhm/5%")
      (footprint "eagle-import:R0805")
      (fields (field (name "PARTNO") "ERJ6GEYJ102V"))
      (libsource (lib "eagle-import") (part "R-EU_R0805"))
    )
    (comp (ref "R352")
      (value "1kOhm/5%")
      (footprint "eagle-import:R0805")
      (fields (field (name "PARTNO") "ERJ6GEYJ102V"))
      (libsource (lib "eagle-import") (part "R-EU_R0805"))
    )
    (comp (ref "R353")
      (value "1kOhm/5%")
      (footprint "eagle-import:R0805")
      (fields (field (name "PARTNO") "ERJ6GEYJ102V"))
      (libsource (lib "eagle-import") (part "R-EU_R0805"))
    )
    (comp (ref "R354")
      (value "1kOhm/5%")
      (footprint "eagle-import:R0805")
      (fields (field (name "PARTNO") "ERJ6GEYJ102V"))
      (libsource (lib "eagle-import") (part "R-EU_R0805"))
    )
    (comp (ref "R355")
      (value "1kOhm/5%")
      (footprint "eagle-import:R0805")
      (fields (field (name "PARTNO") "ERJ6GEYJ102V"))
      (libsource (lib "eagle-import") (part "R-EU_R0805"))
    )
    (comp (ref "R356")
      (value "1kOhm/5%")
      (footprint "eagle-import:R0805")
      (fields (field (name "PARTNO") "ERJ6GEYJ102V"))
      (libsource (lib "eagle-import") (part "R-EU_R0805"))
    )
    (comp (ref "R357")
      (value "1kOhm/5%")
      (footprint "eagle-import:R0805")
      (fields (field (name "PARTNO") "ERJ6GEYJ102V"))
      (libsource (lib "eagle-import") (part "R-EU_R0805"))
    )
    (comp (ref "VD196")
      (value "100V")
      (footprint "eagle-import:SOD323")
      (fields (field (name "PARTNO") "1N4148WS-V-GS18"))
      (libsource (lib "eagle-import") (part "DIODE-STANDARD-SOD323"))
    )
    (comp (ref "VD197")
      (value "100V")
      (footprint "eagle-import:SOD323")
      (fields (field (name "PARTNO") "1N4148WS-V-GS18"))
      (libsource (lib "eagle-import") (part "DIODE-STANDARD-SOD323"))
    )
    (comp (ref "VD198")
      (value "100V")
      (footprint "eagle-import:SOD323")
      (fields (field (name "PARTNO") "1N4148WS-V-GS18"))
      (libsource (lib "eagle-import") (part "DIODE-STANDARD-SOD323"))
    )
    (comp (ref "VD199")
      (value "100V")
      (footprint "eagle-import:SOD323")
      (fields (field (name "PARTNO") "1N4148WS-V-GS18"))
      (libsource (lib "eagle-import") (part "DIODE-STANDARD-SOD323"))
    )
    (comp (ref "VD200")
      (value "100V")
      (footprint "eagle-import:SOD323")
      (fields (field (name "PARTNO") "1N4148WS-V-GS18"))
      (libsource (lib "eagle-import") (part "DIODE-STANDARD-SOD323"))
    )
    (comp (ref "VD201")
      (value "100V")
      (footprint "eagle-import:SOD323")
      (fields (field (name "PARTNO") "1N4148WS-V-GS18"))
      (libsource (lib "eagle-import") (part "DIODE-STANDARD-SOD323"))
    )
    (comp (ref "VD202")
      (value "100V")
      (footprint "eagle-import:SOD323")
      (fields (field (name "PARTNO") "1N4148WS-V-GS18"))
      (libsource (lib "eagle-import") (part "DIODE-STANDARD-SOD323"))
    )
    (comp (ref "VD203")
      (value "100V")
      (footprint "eagle-import:SOD323")
      (fields (field (name "PARTNO") "1N4148WS-V-GS18"))
      (libsource (lib "eagle-import") (part "DIODE-STANDARD-SOD323"))
    )
    (comp (ref "VD204")
      (value "100V")
      (footprint "eagle-import:SOD323")
      (fields (field (name "PARTNO") "1N4148WS-V-GS18"))
      (libsource (lib "eagle-import") (part "DIODE-STANDARD-SOD323"))
    )
    (comp (ref "VD205")
      (value "100V")
      (footprint "eagle-import:SOD323")
      (fields (field (name "PARTNO") "1N4148WS-V-GS18"))
      (libsource (lib "eagle-import") (part "DIODE-STANDARD-SOD323"))
    )
    (comp (ref "VD206")
      (value "100V")
      (footprint "eagle-import:SOD323")
      (fields (field (name "PARTNO") "1N4148WS-V-GS18"))
      (libsource (lib "eagle-import") (part "DIODE-STANDARD-SOD323"))
    )
    (comp (ref "VD207")
      (value "100V")
      (footprint "eagle-import:SOD323")
      (fields (field (name "PARTNO") "1N4148WS-V-GS18"))
      (libsource (lib "eagle-import") (part "DIODE-STANDARD-SOD323"))
    )
    (comp (ref "VD208")
      (value "100V")
      (footprint "eagle-import:SOD323")
      (fields (field (name "PARTNO") "1N4148WS-V-GS18"))
      (libsource (lib "eagle-import") (part "DIODE-STANDARD-SOD323"))
    )
    (comp (ref "VD209")
      (value "100V")
      (footprint "eagle-import:SOD323")
      (fields (field (name "PARTNO") "1N4148WS-V-GS18"))
      (libsource (lib "eagle-import") (part "DIODE-STANDARD-SOD323"))
    )
    (comp (ref "VD210")
      (value "100V")
      (footprint "eagle-import:SOD323")
      (fields (field (name "PARTNO") "1N4148WS-V-GS18"))
      (libsource (lib "eagle-import") (part "DIODE-STANDARD-SOD323"))
    )
    (comp (ref "VD211")
      (value "100V")
      (footprint "eagle-import:SOD323")
      (fields (field (name "PARTNO") "1N4148WS-V-GS18"))
      (libsource (lib "eagle-import") (part "DIODE-STANDARD-SOD323"))
    )
    (comp (ref "XP11")
      (value "MOLEX-90130-34")
      (footprint "eagle-import:MOLEX-90130-34")
      (fields (field (name "PARTNO") "90130-1234"))
      (libsource (lib "eagle-import") (part "MOLEX-90130-34"))
    )
    (comp (ref "C87")
      (value "0.1uF")
      (footprint "eagle-import:C0603")
      (fields (field (name "PARTNO") "C0603C104K5RACTU"))
      (libsource (lib "eagle-import") (part "C-EUC0603"))
    )
    (comp (ref "C88")
      (value "0.1uF")
      (footprint "eagle-import:C0603")
      (fields (field (name "PARTNO") "C0603C104K5RACTU"))
      (libsource (lib "eagle-import") (part "C-EUC0603"))
    )
    (comp (ref "C89")
      (value "0.1uF")
      (footprint "eagle-import:C0603")
      (fields (field (name "PARTNO") "C0603C104K5RACTU"))
      (libsource (lib "eagle-import") (part "C-EUC0603"))
    )
    (comp (ref "C90")
      (value "0.1uF")
      (footprint "eagle-import:C0603")
      (fields (field (name "PARTNO") "C0603C104K5RACTU"))
      (libsource (lib "eagle-import") (part "C-EUC0603"))
    )
    (comp (ref "C91")
      (value "0.1uF")
      (footprint "eagle-import:C0603")
      (fields (field (name "PARTNO") "C0603C104K5RACTU"))
      (libsource (lib "eagle-import") (part "C-EUC0603"))
    )
    (comp (ref "C92")
      (value "0.1uF")
      (footprint "eagle-import:C0603")
      (fields (field (name "PARTNO") "C0603C104K5RACTU"))
      (libsource (lib "eagle-import") (part "C-EUC0603"))
    )
    (comp (ref "C93")
      (value "0.1uF")
      (footprint "eagle-import:C0603")
      (fields (field (name "PARTNO") "C0603C104K5RACTU"))
      (libsource (lib "eagle-import") (part "C-EUC0603"))
    )
    (comp (ref "C94")
      (value "0.1uF")
      (footprint "eagle-import:C0603")
      (fields (field (name "PARTNO") "C0603C104K5RACTU"))
      (libsource (lib "eagle-import") (part "C-EUC0603"))
    )
    (comp (ref "C95")
      (value "0.1uF")
      (footprint "eagle-import:C0603")
      (fields (field (name "PARTNO") "C0603C104K5RACTU"))
      (libsource (lib "eagle-import") (part "C-EUC0603"))
    )
    (comp (ref "C96")
      (value "0.1uF")
      (footprint "eagle-import:C0603")
      (fields (field (name "PARTNO") "C0603C104K5RACTU"))
      (libsource (lib "eagle-import") (part "C-EUC0603"))
    )
    (comp (ref "C97")
      (value "0.1uF")
      (footprint "eagle-import:C0603")
      (fields (field (name "PARTNO") "C0603C104K5RACTU"))
      (libsource (lib "eagle-import") (part "C-EUC0603"))
    )
    (comp (ref "C98")
      (value "0.1uF")
      (footprint "eagle-import:C0603")
      (fields (field (name "PARTNO") "C0603C104K5RACTU"))
      (libsource (lib "eagle-import") (part "C-EUC0603"))
    )
    (comp (ref "C99")
      (value "0.1uF")
      (footprint "eagle-import:C0603")
      (fields (field (name "PARTNO") "C0603C104K5RACTU"))
      (libsource (lib "eagle-import") (part "C-EUC0603"))
    )
    (comp (ref "C100")
      (value "0.1uF")
      (footprint "eagle-import:C0603")
      (fields (field (name "PARTNO") "C0603C104K5RACTU"))
      (libsource (lib "eagle-import") (part "C-EUC0603"))
    )
    (comp (ref "C101")
      (value "0.1uF")
      (footprint "eagle-import:C0603")
      (fields (field (name "PARTNO") "C0603C104K5RACTU"))
      (libsource (lib "eagle-import") (part "C-EUC0603"))
    )
    (comp (ref "C102")
      (value "0.1uF")
      (footprint "eagle-import:C0603")
      (fields (field (name "PARTNO") "C0603C104K5RACTU"))
      (libsource (lib "eagle-import") (part "C-EUC0603"))
    )
    (comp (ref "C103")
      (value "0.1uF")
      (footprint "eagle-import:C0603")
      (fields (field (name "PARTNO") "C0603C104K5RACTU"))
      (libsource (lib "eagle-import") (part "C-EUC0603"))
    )
    (comp (ref "C104")
      (value "0.1uF")
      (footprint "eagle-import:C0603")
      (fields (field (name "PARTNO") "C0603C104K5RACTU"))
      (libsource (lib "eagle-import") (part "C-EUC0603"))
    )
    (comp (ref "D6")
      (value "TCMT4100")
      (footprint "eagle-import:SO16")
      (fields (field (name "PARTNO") "TCMT4100"))
      (libsource (lib "eagle-import") (part "TCMT4100"))
    )
    (comp (ref "D7")
      (value "TCMT4100")
      (footprint "eagle-import:SO16")
      (fields (field (name "PARTNO") "TCMT4100"))
      (libsource (lib "eagle-import") (part "TCMT4100"))
    )
    (comp (ref "D8")
      (value "TCMT4100")
      (footprint "eagle-import:SO16")
      (fields (field (name "PARTNO") "TCMT4100"))
      (libsource (lib "eagle-import") (part "TCMT4100"))
    )
    (comp (ref "D9")
      (value "TCMT4100")
      (footprint "eagle-import:SO16")
      (fields (field (name "PARTNO") "TCMT4100"))
      (libsource (lib "eagle-import") (part "TCMT4100"))
    )
    (comp (ref "DD6")
      (value "74HC165D")
      (footprint "eagle-import:SO16")
      (fields (field (name "PARTNO") "IN74HC165AD"))
      (libsource (lib "eagle-import") (part "74165DHC"))
    )
    (comp (ref "DD7")
      (value "74HC165D")
      (footprint "eagle-import:SO16")
      (fields (field (name "PARTNO") "IN74HC165AD"))
      (libsource (lib "eagle-import") (part "74165DHC"))
    )
    (comp (ref "R189")
      (value "4.7kOhm/5%")
      (footprint "eagle-import:R1206")
      (fields (field (name "PARTNO") "RC1206JR-074K7L"))
      (libsource (lib "eagle-import") (part "R-EU_R1206"))
    )
    (comp (ref "R190")
      (value "4.7kOhm/5%")
      (footprint "eagle-import:R1206")
      (fields (field (name "PARTNO") "RC1206JR-074K7L"))
      (libsource (lib "eagle-import") (part "R-EU_R1206"))
    )
    (comp (ref "R191")
      (value "4.7kOhm/5%")
      (footprint "eagle-import:R1206")
      (fields (field (name "PARTNO") "RC1206JR-074K7L"))
      (libsource (lib "eagle-import") (part "R-EU_R1206"))
    )
    (comp (ref "R192")
      (value "4.7kOhm/5%")
      (footprint "eagle-import:R1206")
      (fields (field (name "PARTNO") "RC1206JR-074K7L"))
      (libsource (lib "eagle-import") (part "R-EU_R1206"))
    )
    (comp (ref "R193")
      (value "4.7kOhm/5%")
      (footprint "eagle-import:R1206")
      (fields (field (name "PARTNO") "RC1206JR-074K7L"))
      (libsource (lib "eagle-import") (part "R-EU_R1206"))
    )
    (comp (ref "R194")
      (value "4.7kOhm/5%")
      (footprint "eagle-import:R1206")
      (fields (field (name "PARTNO") "RC1206JR-074K7L"))
      (libsource (lib "eagle-import") (part "R-EU_R1206"))
    )
    (comp (ref "R195")
      (value "4.7kOhm/5%")
      (footprint "eagle-import:R1206")
      (fields (field (name "PARTNO") "RC1206JR-074K7L"))
      (libsource (lib "eagle-import") (part "R-EU_R1206"))
    )
    (comp (ref "R196")
      (value "4.7kOhm/5%")
      (footprint "eagle-import:R1206")
      (fields (field (name "PARTNO") "RC1206JR-074K7L"))
      (libsource (lib "eagle-import") (part "R-EU_R1206"))
    )
    (comp (ref "R197")
      (value "4.7kOhm/5%")
      (footprint "eagle-import:R1206")
      (fields (field (name "PARTNO") "RC1206JR-074K7L"))
      (libsource (lib "eagle-import") (part "R-EU_R1206"))
    )
    (comp (ref "R198")
      (value "4.7kOhm/5%")
      (footprint "eagle-import:R1206")
      (fields (field (name "PARTNO") "RC1206JR-074K7L"))
      (libsource (lib "eagle-import") (part "R-EU_R1206"))
    )
    (comp (ref "R199")
      (value "4.7kOhm/5%")
      (footprint "eagle-import:R1206")
      (fields (field (name "PARTNO") "RC1206JR-074K7L"))
      (libsource (lib "eagle-import") (part "R-EU_R1206"))
    )
    (comp (ref "R200")
      (value "4.7kOhm/5%")
      (footprint "eagle-import:R1206")
      (fields (field (name "PARTNO") "RC1206JR-074K7L"))
      (libsource (lib "eagle-import") (part "R-EU_R1206"))
    )
    (comp (ref "R201")
      (value "4.7kOhm/5%")
      (footprint "eagle-import:R1206")
      (fields (field (name "PARTNO") "RC1206JR-074K7L"))
      (libsource (lib "eagle-import") (part "R-EU_R1206"))
    )
    (comp (ref "R202")
      (value "4.7kOhm/5%")
      (footprint "eagle-import:R1206")
      (fields (field (name "PARTNO") "RC1206JR-074K7L"))
      (libsource (lib "eagle-import") (part "R-EU_R1206"))
    )
    (comp (ref "R203")
      (value "4.7kOhm/5%")
      (footprint "eagle-import:R1206")
      (fields (field (name "PARTNO") "RC1206JR-074K7L"))
      (libsource (lib "eagle-import") (part "R-EU_R1206"))
    )
    (comp (ref "R204")
      (value "4.7kOhm/5%")
      (footprint "eagle-import:R1206")
      (fields (field (name "PARTNO") "RC1206JR-074K7L"))
      (libsource (lib "eagle-import") (part "R-EU_R1206"))
    )
    (comp (ref "R205")
      (value "1kOhm/5%")
      (footprint "eagle-import:R2512")
      (fields (field (name "PARTNO") "RC2512JK-071KL"))
      (libsource (lib "eagle-import") (part "R-EU_R2512"))
    )
    (comp (ref "R206")
      (value "1kOhm/5%")
      (footprint "eagle-import:R2512")
      (fields (field (name "PARTNO") "RC2512JK-071KL"))
      (libsource (lib "eagle-import") (part "R-EU_R2512"))
    )
    (comp (ref "R207")
      (value "1kOhm/5%")
      (footprint "eagle-import:R2512")
      (fields (field (name "PARTNO") "RC2512JK-071KL"))
      (libsource (lib "eagle-import") (part "R-EU_R2512"))
    )
    (comp (ref "R208")
      (value "1kOhm/5%")
      (footprint "eagle-import:R2512")
      (fields (field (name "PARTNO") "RC2512JK-071KL"))
      (libsource (lib "eagle-import") (part "R-EU_R2512"))
    )
    (comp (ref "R209")
      (value "1kOhm/5%")
      (footprint "eagle-import:R2512")
      (fields (field (name "PARTNO") "RC2512JK-071KL"))
      (libsource (lib "eagle-import") (part "R-EU_R2512"))
    )
    (comp (ref "R210")
      (value "1kOhm/5%")
      (footprint "eagle-import:R2512")
      (fields (field (name "PARTNO") "RC2512JK-071KL"))
      (libsource (lib "eagle-import") (part "R-EU_R2512"))
    )
    (comp (ref "R211")
      (value "1kOhm/5%")
      (footprint "eagle-import:R2512")
      (fields (field (name "PARTNO") "RC2512JK-071KL"))
      (libsource (lib "eagle-import") (part "R-EU_R2512"))
    )
    (comp (ref "R212")
      (value "1kOhm/5%")
      (footprint "eagle-import:R2512")
      (fields (field (name "PARTNO") "RC2512JK-071KL"))
      (libsource (lib "eagle-import") (part "R-EU_R2512"))
    )
    (comp (ref "R213")
      (value "1kOhm/5%")
      (footprint "eagle-import:R2512")
      (fields (field (name "PARTNO") "RC2512JK-071KL"))
      (libsource (lib "eagle-import") (part "R-EU_R2512"))
    )
    (comp (ref "R214")
      (value "1kOhm/5%")
      (footprint "eagle-import:R2512")
      (fields (field (name "PARTNO") "RC2512JK-071KL"))
      (libsource (lib "eagle-import") (part "R-EU_R2512"))
    )
    (comp (ref "R215")
      (value "1kOhm/5%")
      (footprint "eagle-import:R2512")
      (fields (field (name "PARTNO") "RC2512JK-071KL"))
      (libsource (lib "eagle-import") (part "R-EU_R2512"))
    )
    (comp (ref "R216")
      (value "1kOhm/5%")
      (footprint "eagle-import:R2512")
      (fields (field (name "PARTNO") "RC2512JK-071KL"))
      (libsource (lib "eagle-import") (part "R-EU_R2512"))
    )
    (comp (ref "R217")
      (value "1kOhm/5%")
      (footprint "eagle-import:R2512")
      (fields (field (name "PARTNO") "RC2512JK-071KL"))
      (libsource (lib "eagle-import") (part "R-EU_R2512"))
    )
    (comp (ref "R218")
      (value "1kOhm/5%")
      (footprint "eagle-import:R2512")
      (fields (field (name "PARTNO") "RC2512JK-071KL"))
      (libsource (lib "eagle-import") (part "R-EU_R2512"))
    )
    (comp (ref "R219")
      (value "1kOhm/5%")
      (footprint "eagle-import:R2512")
      (fields (field (name "PARTNO") "RC2512JK-071KL"))
      (libsource (lib "eagle-import") (part "R-EU_R2512"))
    )
    (comp (ref "R220")
      (value "1kOhm/5%")
      (footprint "eagle-import:R2512")
      (fields (field (name "PARTNO") "RC2512JK-071KL"))
      (libsource (lib "eagle-import") (part "R-EU_R2512"))
    )
    (comp (ref "R221")
      (value "10kOhm/1%")
      (footprint "eagle-import:R0603")
      (fields (field (name "PARTNO") "RC0603FR-1010KL"))
      (libsource (lib "eagle-import") (part "R-EU_R0603"))
    )
    (comp (ref "R222")
      (value "10kOhm/1%")
      (footprint "eagle-import:R0603")
      (fields (field (name "PARTNO") "RC0603FR-1010KL"))
      (libsource (lib "eagle-import") (part "R-EU_R0603"))
    )
    (comp (ref "R223")
      (value "10kOhm/1%")
      (footprint "eagle-import:R0603")
      (fields (field (name "PARTNO") "RC0603FR-1010KL"))
      (libsource (lib "eagle-import") (part "R-EU_R0603"))
    )
    (comp (ref "R224")
      (value "10kOhm/1%")
      (footprint "eagle-import:R0603")
      (fields (field (name "PARTNO") "RC0603FR-1010KL"))
      (libsource (lib "eagle-import") (part "R-EU_R0603"))
    )
    (comp (ref "R225")
      (value "10kOhm/1%")
      (footprint "eagle-import:R0603")
      (fields (field (name "PARTNO") "RC0603FR-1010KL"))
      (libsource (lib "eagle-import") (part "R-EU_R0603"))
    )
    (comp (ref "R226")
      (value "10kOhm/1%")
      (footprint "eagle-import:R0603")
      (fields (field (name "PARTNO") "RC0603FR-1010KL"))
      (libsource (lib "eagle-import") (part "R-EU_R0603"))
    )
    (comp (ref "R227")
      (value "10kOhm/1%")
      (footprint "eagle-import:R0603")
      (fields (field (name "PARTNO") "RC0603FR-1010KL"))
      (libsource (lib "eagle-import") (part "R-EU_R0603"))
    )
    (comp (ref "R228")
      (value "10kOhm/1%")
      (footprint "eagle-import:R0603")
      (fields (field (name "PARTNO") "RC0603FR-1010KL"))
      (libsource (lib "eagle-import") (part "R-EU_R0603"))
    )
    (comp (ref "R229")
      (value "10kOhm/1%")
      (footprint "eagle-import:R0603")
      (fields (field (name "PARTNO") "RC0603FR-1010KL"))
      (libsource (lib "eagle-import") (part "R-EU_R0603"))
    )
    (comp (ref "R230")
      (value "10kOhm/1%")
      (footprint "eagle-import:R0603")
      (fields (field (name "PARTNO") "RC0603FR-1010KL"))
      (libsource (lib "eagle-import") (part "R-EU_R0603"))
    )
    (comp (ref "R231")
      (value "10kOhm/1%")
      (footprint "eagle-import:R0603")
      (fields (field (name "PARTNO") "RC0603FR-1010KL"))
      (libsource (lib "eagle-import") (part "R-EU_R0603"))
    )
    (comp (ref "R232")
      (value "10kOhm/1%")
      (footprint "eagle-import:R0603")
      (fields (field (name "PARTNO") "RC0603FR-1010KL"))
      (libsource (lib "eagle-import") (part "R-EU_R0603"))
    )
    (comp (ref "R233")
      (value "10kOhm/1%")
      (footprint "eagle-import:R0603")
      (fields (field (name "PARTNO") "RC0603FR-1010KL"))
      (libsource (lib "eagle-import") (part "R-EU_R0603"))
    )
    (comp (ref "R234")
      (value "10kOhm/1%")
      (footprint "eagle-import:R0603")
      (fields (field (name "PARTNO") "RC0603FR-1010KL"))
      (libsource (lib "eagle-import") (part "R-EU_R0603"))
    )
    (comp (ref "R235")
      (value "10kOhm/1%")
      (footprint "eagle-import:R0603")
      (fields (field (name "PARTNO") "RC0603FR-1010KL"))
      (libsource (lib "eagle-import") (part "R-EU_R0603"))
    )
    (comp (ref "R236")
      (value "10kOhm/1%")
      (footprint "eagle-import:R0603")
      (fields (field (name "PARTNO") "RC0603FR-1010KL"))
      (libsource (lib "eagle-import") (part "R-EU_R0603"))
    )
    (comp (ref "VD100")
      (value "SM6T200A")
      (footprint "eagle-import:SMB")
      (libsource (lib "eagle-import") (part "DIODE-TVS-UNIDIR-SMB"))
    )
    (comp (ref "VD101")
      (value "SM6T200A")
      (footprint "eagle-import:SMB")
      (libsource (lib "eagle-import") (part "DIODE-TVS-UNIDIR-SMB"))
    )
    (comp (ref "VD102")
      (value "SM6T200A")
      (footprint "eagle-import:SMB")
      (libsource (lib "eagle-import") (part "DIODE-TVS-UNIDIR-SMB"))
    )
    (comp (ref "VD103")
      (value "SM6T200A")
      (footprint "eagle-import:SMB")
      (libsource (lib "eagle-import") (part "DIODE-TVS-UNIDIR-SMB"))
    )
    (comp (ref "VD104")
      (value "SM6T200A")
      (footprint "eagle-import:SMB")
      (libsource (lib "eagle-import") (part "DIODE-TVS-UNIDIR-SMB"))
    )
    (comp (ref "VD105")
      (value "SM6T200A")
      (footprint "eagle-import:SMB")
      (libsource (lib "eagle-import") (part "DIODE-TVS-UNIDIR-SMB"))
    )
    (comp (ref "VD106")
      (value "SM6T200A")
      (footprint "eagle-import:SMB")
      (libsource (lib "eagle-import") (part "DIODE-TVS-UNIDIR-SMB"))
    )
    (comp (ref "VD107")
      (value "SM6T200A")
      (footprint "eagle-import:SMB")
      (libsource (lib "eagle-import") (part "DIODE-TVS-UNIDIR-SMB"))
    )
    (comp (ref "VD108")
      (value "SM6T200A")
      (footprint "eagle-import:SMB")
      (libsource (lib "eagle-import") (part "DIODE-TVS-UNIDIR-SMB"))
    )
    (comp (ref "VD109")
      (value "SM6T200A")
      (footprint "eagle-import:SMB")
      (libsource (lib "eagle-import") (part "DIODE-TVS-UNIDIR-SMB"))
    )
    (comp (ref "VD110")
      (value "SM6T200A")
      (footprint "eagle-import:SMB")
      (libsource (lib "eagle-import") (part "DIODE-TVS-UNIDIR-SMB"))
    )
    (comp (ref "VD111")
      (value "SM6T200A")
      (footprint "eagle-import:SMB")
      (libsource (lib "eagle-import") (part "DIODE-TVS-UNIDIR-SMB"))
    )
    (comp (ref "VD112")
      (value "SM6T200A")
      (footprint "eagle-import:SMB")
      (libsource (lib "eagle-import") (part "DIODE-TVS-UNIDIR-SMB"))
    )
    (comp (ref "VD113")
      (value "SM6T200A")
      (footprint "eagle-import:SMB")
      (libsource (lib "eagle-import") (part "DIODE-TVS-UNIDIR-SMB"))
    )
    (comp (ref "VD114")
      (value "SM6T200A")
      (footprint "eagle-import:SMB")
      (libsource (lib "eagle-import") (part "DIODE-TVS-UNIDIR-SMB"))
    )
    (comp (ref "VD115")
      (value "SM6T200A")
      (footprint "eagle-import:SMB")
      (libsource (lib "eagle-import") (part "DIODE-TVS-UNIDIR-SMB"))
    )
    (comp (ref "VD116")
      (value "400V")
      (footprint "eagle-import:SMA")
      (fields (field (name "PARTNO") "S1G-E3/61T"))
      (libsource (lib "eagle-import") (part "DIODE-STANDARD-SMA"))
    )
    (comp (ref "VD117")
      (value "400V")
      (footprint "eagle-import:SMA")
      (fields (field (name "PARTNO") "S1G-E3/61T"))
      (libsource (lib "eagle-import") (part "DIODE-STANDARD-SMA"))
    )
    (comp (ref "VD118")
      (value "400V")
      (footprint "eagle-import:SMA")
      (fields (field (name "PARTNO") "S1G-E3/61T"))
      (libsource (lib "eagle-import") (part "DIODE-STANDARD-SMA"))
    )
    (comp (ref "VD119")
      (value "400V")
      (footprint "eagle-import:SMA")
      (fields (field (name "PARTNO") "S1G-E3/61T"))
      (libsource (lib "eagle-import") (part "DIODE-STANDARD-SMA"))
    )
    (comp (ref "VD120")
      (value "400V")
      (footprint "eagle-import:SMA")
      (fields (field (name "PARTNO") "S1G-E3/61T"))
      (libsource (lib "eagle-import") (part "DIODE-STANDARD-SMA"))
    )
    (comp (ref "VD121")
      (value "400V")
      (footprint "eagle-import:SMA")
      (fields (field (name "PARTNO") "S1G-E3/61T"))
      (libsource (lib "eagle-import") (part "DIODE-STANDARD-SMA"))
    )
    (comp (ref "VD122")
      (value "400V")
      (footprint "eagle-import:SMA")
      (fields (field (name "PARTNO") "S1G-E3/61T"))
      (libsource (lib "eagle-import") (part "DIODE-STANDARD-SMA"))
    )
    (comp (ref "VD123")
      (value "400V")
      (footprint "eagle-import:SMA")
      (fields (field (name "PARTNO") "S1G-E3/61T"))
      (libsource (lib "eagle-import") (part "DIODE-STANDARD-SMA"))
    )
    (comp (ref "VD124")
      (value "400V")
      (footprint "eagle-import:SMA")
      (fields (field (name "PARTNO") "S1G-E3/61T"))
      (libsource (lib "eagle-import") (part "DIODE-STANDARD-SMA"))
    )
    (comp (ref "VD125")
      (value "400V")
      (footprint "eagle-import:SMA")
      (fields (field (name "PARTNO") "S1G-E3/61T"))
      (libsource (lib "eagle-import") (part "DIODE-STANDARD-SMA"))
    )
    (comp (ref "VD126")
      (value "400V")
      (footprint "eagle-import:SMA")
      (fields (field (name "PARTNO") "S1G-E3/61T"))
      (libsource (lib "eagle-import") (part "DIODE-STANDARD-SMA"))
    )
    (comp (ref "VD127")
      (value "400V")
      (footprint "eagle-import:SMA")
      (fields (field (name "PARTNO") "S1G-E3/61T"))
      (libsource (lib "eagle-import") (part "DIODE-STANDARD-SMA"))
    )
    (comp (ref "VD128")
      (value "400V")
      (footprint "eagle-import:SMA")
      (fields (field (name "PARTNO") "S1G-E3/61T"))
      (libsource (lib "eagle-import") (part "DIODE-STANDARD-SMA"))
    )
    (comp (ref "VD129")
      (value "400V")
      (footprint "eagle-import:SMA")
      (fields (field (name "PARTNO") "S1G-E3/61T"))
      (libsource (lib "eagle-import") (part "DIODE-STANDARD-SMA"))
    )
    (comp (ref "VD130")
      (value "400V")
      (footprint "eagle-import:SMA")
      (fields (field (name "PARTNO") "S1G-E3/61T"))
      (libsource (lib "eagle-import") (part "DIODE-STANDARD-SMA"))
    )
    (comp (ref "VD131")
      (value "400V")
      (footprint "eagle-import:SMA")
      (fields (field (name "PARTNO") "S1G-E3/61T"))
      (libsource (lib "eagle-import") (part "DIODE-STANDARD-SMA"))
    )
    (comp (ref "XP8")
      (value "MOLEX-90130-16")
      (footprint "eagle-import:MOLEX-90130-16")
      (fields (field (name "PARTNO") "90130-1216"))
      (libsource (lib "eagle-import") (part "MOLEX-90130-16"))
    )
    (comp (ref "C56")
      (value "10uF/50V")
      (footprint "eagle-import:C2220K")
      (fields (field (name "PARTNO") "22205C106KAT2A"))
      (libsource (lib "eagle-import") (part "C-EUC2220K"))
    )
    (comp (ref "C57")
      (value "1000uF/50v")
      (footprint "eagle-import:E35-16-STRAPPED")
      (fields (field (name "PARTNO") "516D108M050QS6AE3"))
      (libsource (lib "eagle-import") (part "CPOL-EUE35-16AXIAL-STRAPPED"))
    )
    (comp (ref "C58")
      (value "10uF/50V")
      (footprint "eagle-import:C2220K")
      (fields (field (name "PARTNO") "22205C106KAT2A"))
      (libsource (lib "eagle-import") (part "C-EUC2220K"))
    )
    (comp (ref "C59")
      (value "0.1uF")
      (footprint "eagle-import:C0603")
      (fields (field (name "PARTNO") "C0603C104K5RACTU"))
      (libsource (lib "eagle-import") (part "C-EUC0603"))
    )
    (comp (ref "C60")
      (value "10uF/50V")
      (footprint "eagle-import:C2220K")
      (fields (field (name "PARTNO") "22205C106KAT2A"))
      (libsource (lib "eagle-import") (part "C-EUC2220K"))
    )
    (comp (ref "C61")
      (value "0.1uF")
      (footprint "eagle-import:C0603")
      (fields (field (name "PARTNO") "C0603C104K5RACTU"))
      (libsource (lib "eagle-import") (part "C-EUC0603"))
    )
    (comp (ref "C62")
      (value "0.01uF")
      (footprint "eagle-import:C0603")
      (fields (field (name "PARTNO") "C0603C103K5RACTU"))
      (libsource (lib "eagle-import") (part "C-EUC0603"))
    )
    (comp (ref "C63")
      (value "0.1uF")
      (footprint "eagle-import:C0603")
      (fields (field (name "PARTNO") "C0603C104K5RACTU"))
      (libsource (lib "eagle-import") (part "C-EUC0603"))
    )
    (comp (ref "C64")
      (value "10uF/10V")
      (footprint "eagle-import:A_3216-18W")
      (fields (field (name "PARTNO") "T491A106K010AT"))
      (libsource (lib "eagle-import") (part "CPOL-EUA/3216-18W"))
    )
    (comp (ref "C65")
      (value "1uF/16V")
      (footprint "eagle-import:C0603")
      (fields (field (name "PARTNO") "C0603C105K4PACTU"))
      (libsource (lib "eagle-import") (part "C-EUC0603"))
    )
    (comp (ref "C66")
      (value "220uF/10V")
      (footprint "eagle-import:TE-D-7343")
      (fields (field (name "PARTNO") "T491D227K010AT"))
      (libsource (lib "eagle-import") (part "CPOL-EUTE-D-7343"))
    )
    (comp (ref "C67")
      (value "220uF/10V")
      (footprint "eagle-import:TE-D-7343")
      (fields (field (name "PARTNO") "T491D227K010AT"))
      (libsource (lib "eagle-import") (part "CPOL-EUTE-D-7343"))
    )
    (comp (ref "C68")
      (value "10uF/10V")
      (footprint "eagle-import:A_3216-18W")
      (fields (field (name "PARTNO") "T491A106K010AT"))
      (libsource (lib "eagle-import") (part "CPOL-EUA/3216-18W"))
    )
    (comp (ref "DA11")
      (value "MC33091A")
      (footprint "eagle-import:SO08")
      (fields (field (name "PARTNO") "IL33091AD"))
      (libsource (lib "eagle-import") (part "MC33091A"))
    )
    (comp (ref "DA12")
      (value "LM2596S-5.0")
      (footprint "eagle-import:TO263-5")
      (fields (field (name "PARTNO") "LM2596S-5.0/NOPB"))
      (libsource (lib "eagle-import") (part "LM2596?-S5.0"))
    )
    (comp (ref "DA13")
      (value "LM2596S-5.0")
      (footprint "eagle-import:TO263-5")
      (fields (field (name "PARTNO") "LM2596S-5.0/NOPB"))
      (libsource (lib "eagle-import") (part "LM2596?-S5.0"))
    )
    (comp (ref "DA14")
      (value "IL5233G")
      (footprint "eagle-import:SOT223")
      (libsource (lib "eagle-import") (part "IL52G33"))
    )
    (comp (ref "L2")
      (value "47uH")
      (footprint "eagle-import:DRA127")
      (fields (field (name "PARTNO") "DR127-470-R"))
      (libsource (lib "eagle-import") (part "DRA127"))
    )
    (comp (ref "L3")
      (value "100uH")
      (footprint "eagle-import:DRA73")
      (fields (field (name "PARTNO") "DR73-101-R"))
      (libsource (lib "eagle-import") (part "DRA73"))
    )
    (comp (ref "R131")
      (value "15kOhm/5%")
      (footprint "eagle-import:R0805")
      (fields (field (name "PARTNO") "ERJ6GEYJ153V"))
      (libsource (lib "eagle-import") (part "R-EU_R0805"))
    )
    (comp (ref "R132")
      (value "82kOhm/5%")
      (footprint "eagle-import:R0805")
      (fields (field (name "PARTNO") "RC0805JR-0782KL"))
      (libsource (lib "eagle-import") (part "R-EU_R0805"))
    )
    (comp (ref "R133")
      (value "470kOhm/5%")
      (footprint "eagle-import:R0805")
      (fields (field (name "PARTNO") "ERJ6GEYJ474V"))
      (libsource (lib "eagle-import") (part "R-EU_R0805"))
    )
    (comp (ref "R134")
      (value "1kOhm/5%")
      (footprint "eagle-import:R0805")
      (fields (field (name "PARTNO") "ERJ6GEYJ102V"))
      (libsource (lib "eagle-import") (part "R-EU_R0805"))
    )
    (comp (ref "R135")
      (value "3.3kOhm/5%")
      (footprint "eagle-import:R2512")
      (fields (field (name "PARTNO") "35203K3JT"))
      (libsource (lib "eagle-import") (part "R-EU_R2512"))
    )
    (comp (ref "R136")
      (value "330Ohm/5%")
      (footprint "eagle-import:R0603")
      (fields (field (name "PARTNO") "ERJ3GEYJ331V"))
      (libsource (lib "eagle-import") (part "R-EU_R0603"))
    )
    (comp (ref "R137")
      (value "330Ohm/5%")
      (footprint "eagle-import:R0603")
      (fields (field (name "PARTNO") "ERJ3GEYJ331V"))
      (libsource (lib "eagle-import") (part "R-EU_R0603"))
    )
    (comp (ref "RK1")
      (value "0.5A")
      (footprint "eagle-import:RK1210")
      (fields (field (name "PARTNO") "1210L050YR"))
      (libsource (lib "eagle-import") (part "RESETTABLE_FUSE_1210"))
    )
    (comp (ref "RK2")
      (value "2A")
      (footprint "eagle-import:RK1812")
      (fields (field (name "PARTNO") "1812L200DR"))
      (libsource (lib "eagle-import") (part "RESETTABLE_FUSE_1812"))
    )
    (comp (ref "RK3")
      (value "0.5A")
      (footprint "eagle-import:RK1210")
      (fields (field (name "PARTNO") "1210L050YR"))
      (libsource (lib "eagle-import") (part "RESETTABLE_FUSE_1210"))
    )
    (comp (ref "VD53")
      (value "SMBJ24CA")
      (footprint "eagle-import:SMB-BIDIR")
      (libsource (lib "eagle-import") (part "DIODE-TVS-BIDIR-SMB"))
    )
    (comp (ref "VD54")
      (value "SMBJ24CA")
      (footprint "eagle-import:SMB-BIDIR")
      (libsource (lib "eagle-import") (part "DIODE-TVS-BIDIR-SMB"))
    )
    (comp (ref "VD55")
      (value "SM6T6V8A")
      (footprint "eagle-import:SMB")
      (libsource (lib "eagle-import") (part "DIODE-TVS-UNIDIR-SMB"))
    )
    (comp (ref "VD56")
      (value "400V")
      (footprint "eagle-import:SMA")
      (fields (field (name "PARTNO") "S1G-E3/61T"))
      (libsource (lib "eagle-import") (part "DIODE-STANDARD-SMA"))
    )
    (comp (ref "VD57")
      (value "SMBJ24CA")
      (footprint "eagle-import:SMB-BIDIR")
      (libsource (lib "eagle-import") (part "DIODE-TVS-BIDIR-SMB"))
    )
    (comp (ref "VD58")
      (value "3A/60V")
      (footprint "eagle-import:SMC")
      (fields (field (name "PARTNO") "VS-30BQ060TRPBF"))
      (libsource (lib "eagle-import") (part "DIODE-SCHOTTKY-SMC"))
    )
    (comp (ref "VD59")
      (value "1A/60V")
      (footprint "eagle-import:SMB")
      (fields (field (name "PARTNO") "VS-10BQ060TRPBF"))
      (libsource (lib "eagle-import") (part "DIODE-SCHOTTKY-SMB"))
    )
    (comp (ref "VD60")
      (value "400V")
      (footprint "eagle-import:SMA")
      (fields (field (name "PARTNO") "S1G-E3/61T"))
      (libsource (lib "eagle-import") (part "DIODE-STANDARD-SMA"))
    )
    (comp (ref "VD61")
      (value "600V/6A")
      (footprint "eagle-import:DPAK")
      (fields (field (name "PARTNO") "IDD06SG60C"))
      (libsource (lib "eagle-import") (part "IDD06SG60C"))
    )
    (comp (ref "VD62")
      (value "SMBJ24CA")
      (footprint "eagle-import:SMB-BIDIR")
      (libsource (lib "eagle-import") (part "DIODE-TVS-BIDIR-SMB"))
    )
    (comp (ref "VD63")
      (value "SM6T200A")
      (footprint "eagle-import:SMB")
      (libsource (lib "eagle-import") (part "DIODE-TVS-UNIDIR-SMB"))
    )
    (comp (ref "VD64")
      (value "GREEN")
      (footprint "eagle-import:LED-0805")
      (fields (field (name "LABEL") "+5V") (field (name "PARTNO") "KPHCM-2012SGC-T"))
      (libsource (lib "eagle-import") (part "LED0805"))
    )
    (comp (ref "VD65")
      (value "GREEN")
      (footprint "eagle-import:LED-0805")
      (fields (field (name "LABEL") "-5V") (field (name "PARTNO") "KPHCM-2012SGC-T"))
      (libsource (lib "eagle-import") (part "LED0805"))
    )
    (comp (ref "VT1")
      (value "IRFR430")
      (footprint "eagle-import:DPAK")
      (fields (field (name "PARTNO") "IRFR430APBF"))
      (libsource (lib "eagle-import") (part "IRFR430"))
    )
    (comp (ref "XP6")
      (value "MOLEX-90130-08")
      (footprint "eagle-import:MOLEX-90130-08")
      (fields (field (name "LABEL") "POWER") (field (name "PARTNO") "90130-1208"))
      (libsource (lib "eagle-import") (part "MOLEX-90130-08"))
    )
    (comp (ref "Z41")
      (value "4701-001LF")
      (footprint "eagle-import:TUSONIX-4701")
      (libsource (lib "eagle-import") (part "4701-001LF"))
    )
    (comp (ref "C105")
      (value "0.1uF")
      (footprint "eagle-import:C0603")
      (fields (field (name "PARTNO") "C0603C104K5RACTU"))
      (libsource (lib "eagle-import") (part "C-EUC0603"))
    )
    (comp (ref "C106")
      (value "0.1uF")
      (footprint "eagle-import:C0603")
      (fields (field (name "PARTNO") "C0603C104K5RACTU"))
      (libsource (lib "eagle-import") (part "C-EUC0603"))
    )
    (comp (ref "C107")
      (value "0.1uF")
      (footprint "eagle-import:C0603")
      (fields (field (name "PARTNO") "C0603C104K5RACTU"))
      (libsource (lib "eagle-import") (part "C-EUC0603"))
    )
    (comp (ref "C108")
      (value "0.1uF")
      (footprint "eagle-import:C0603")
      (fields (field (name "PARTNO") "C0603C104K5RACTU"))
      (libsource (lib "eagle-import") (part "C-EUC0603"))
    )
    (comp (ref "C109")
      (value "0.1uF")
      (footprint "eagle-import:C0603")
      (fields (field (name "PARTNO") "C0603C104K5RACTU"))
      (libsource (lib "eagle-import") (part "C-EUC0603"))
    )
    (comp (ref "C110")
      (value "0.1uF")
      (footprint "eagle-import:C0603")
      (fields (field (name "PARTNO") "C0603C104K5RACTU"))
      (libsource (lib "eagle-import") (part "C-EUC0603"))
    )
    (comp (ref "C111")
      (value "0.1uF")
      (footprint "eagle-import:C0603")
      (fields (field (name "PARTNO") "C0603C104K5RACTU"))
      (libsource (lib "eagle-import") (part "C-EUC0603"))
    )
    (comp (ref "C112")
      (value "0.1uF")
      (footprint "eagle-import:C0603")
      (fields (field (name "PARTNO") "C0603C104K5RACTU"))
      (libsource (lib "eagle-import") (part "C-EUC0603"))
    )
    (comp (ref "C113")
      (value "0.1uF")
      (footprint "eagle-import:C0603")
      (fields (field (name "PARTNO") "C0603C104K5RACTU"))
      (libsource (lib "eagle-import") (part "C-EUC0603"))
    )
    (comp (ref "C114")
      (value "0.1uF")
      (footprint "eagle-import:C0603")
      (fields (field (name "PARTNO") "C0603C104K5RACTU"))
      (libsource (lib "eagle-import") (part "C-EUC0603"))
    )
    (comp (ref "C115")
      (value "0.1uF")
      (footprint "eagle-import:C0603")
      (fields (field (name "PARTNO") "C0603C104K5RACTU"))
      (libsource (lib "eagle-import") (part "C-EUC0603"))
    )
    (comp (ref "C116")
      (value "0.1uF")
      (footprint "eagle-import:C0603")
      (fields (field (name "PARTNO") "C0603C104K5RACTU"))
      (libsource (lib "eagle-import") (part "C-EUC0603"))
    )
    (comp (ref "C117")
      (value "0.1uF")
      (footprint "eagle-import:C0603")
      (fields (field (name "PARTNO") "C0603C104K5RACTU"))
      (libsource (lib "eagle-import") (part "C-EUC0603"))
    )
    (comp (ref "C118")
      (value "0.1uF")
      (footprint "eagle-import:C0603")
      (fields (field (name "PARTNO") "C0603C104K5RACTU"))
      (libsource (lib "eagle-import") (part "C-EUC0603"))
    )
    (comp (ref "C119")
      (value "0.1uF")
      (footprint "eagle-import:C0603")
      (fields (field (name "PARTNO") "C0603C104K5RACTU"))
      (libsource (lib "eagle-import") (part "C-EUC0603"))
    )
    (comp (ref "C120")
      (value "0.1uF")
      (footprint "eagle-import:C0603")
      (fields (field (name "PARTNO") "C0603C104K5RACTU"))
      (libsource (lib "eagle-import") (part "C-EUC0603"))
    )
    (comp (ref "C121")
      (value "0.1uF")
      (footprint "eagle-import:C0603")
      (fields (field (name "PARTNO") "C0603C104K5RACTU"))
      (libsource (lib "eagle-import") (part "C-EUC0603"))
    )
    (comp (ref "C122")
      (value "0.1uF")
      (footprint "eagle-import:C0603")
      (fields (field (name "PARTNO") "C0603C104K5RACTU"))
      (libsource (lib "eagle-import") (part "C-EUC0603"))
    )
    (comp (ref "D10")
      (value "TCMT4100")
      (footprint "eagle-import:SO16")
      (fields (field (name "PARTNO") "TCMT4100"))
      (libsource (lib "eagle-import") (part "TCMT4100"))
    )
    (comp (ref "D11")
      (value "TCMT4100")
      (footprint "eagle-import:SO16")
      (fields (field (name "PARTNO") "TCMT4100"))
      (libsource (lib "eagle-import") (part "TCMT4100"))
    )
    (comp (ref "D12")
      (value "TCMT4100")
      (footprint "eagle-import:SO16")
      (fields (field (name "PARTNO") "TCMT4100"))
      (libsource (lib "eagle-import") (part "TCMT4100"))
    )
    (comp (ref "D13")
      (value "TCMT4100")
      (footprint "eagle-import:SO16")
      (fields (field (name "PARTNO") "TCMT4100"))
      (libsource (lib "eagle-import") (part "TCMT4100"))
    )
    (comp (ref "DD8")
      (value "74HC165D")
      (footprint "eagle-import:SO16")
      (fields (field (name "PARTNO") "IN74HC165AD"))
      (libsource (lib "eagle-import") (part "74165DHC"))
    )
    (comp (ref "DD9")
      (value "74HC165D")
      (footprint "eagle-import:SO16")
      (fields (field (name "PARTNO") "IN74HC165AD"))
      (libsource (lib "eagle-import") (part "74165DHC"))
    )
    (comp (ref "R237")
      (value "4.7kOhm/5%")
      (footprint "eagle-import:R1206")
      (fields (field (name "PARTNO") "RC1206JR-074K7L"))
      (libsource (lib "eagle-import") (part "R-EU_R1206"))
    )
    (comp (ref "R238")
      (value "4.7kOhm/5%")
      (footprint "eagle-import:R1206")
      (fields (field (name "PARTNO") "RC1206JR-074K7L"))
      (libsource (lib "eagle-import") (part "R-EU_R1206"))
    )
    (comp (ref "R239")
      (value "4.7kOhm/5%")
      (footprint "eagle-import:R1206")
      (fields (field (name "PARTNO") "RC1206JR-074K7L"))
      (libsource (lib "eagle-import") (part "R-EU_R1206"))
    )
    (comp (ref "R240")
      (value "4.7kOhm/5%")
      (footprint "eagle-import:R1206")
      (fields (field (name "PARTNO") "RC1206JR-074K7L"))
      (libsource (lib "eagle-import") (part "R-EU_R1206"))
    )
    (comp (ref "R241")
      (value "4.7kOhm/5%")
      (footprint "eagle-import:R1206")
      (fields (field (name "PARTNO") "RC1206JR-074K7L"))
      (libsource (lib "eagle-import") (part "R-EU_R1206"))
    )
    (comp (ref "R242")
      (value "4.7kOhm/5%")
      (footprint "eagle-import:R1206")
      (fields (field (name "PARTNO") "RC1206JR-074K7L"))
      (libsource (lib "eagle-import") (part "R-EU_R1206"))
    )
    (comp (ref "R243")
      (value "4.7kOhm/5%")
      (footprint "eagle-import:R1206")
      (fields (field (name "PARTNO") "RC1206JR-074K7L"))
      (libsource (lib "eagle-import") (part "R-EU_R1206"))
    )
    (comp (ref "R244")
      (value "4.7kOhm/5%")
      (footprint "eagle-import:R1206")
      (fields (field (name "PARTNO") "RC1206JR-074K7L"))
      (libsource (lib "eagle-import") (part "R-EU_R1206"))
    )
    (comp (ref "R245")
      (value "4.7kOhm/5%")
      (footprint "eagle-import:R1206")
      (fields (field (name "PARTNO") "RC1206JR-074K7L"))
      (libsource (lib "eagle-import") (part "R-EU_R1206"))
    )
    (comp (ref "R246")
      (value "4.7kOhm/5%")
      (footprint "eagle-import:R1206")
      (fields (field (name "PARTNO") "RC1206JR-074K7L"))
      (libsource (lib "eagle-import") (part "R-EU_R1206"))
    )
    (comp (ref "R247")
      (value "4.7kOhm/5%")
      (footprint "eagle-import:R1206")
      (fields (field (name "PARTNO") "RC1206JR-074K7L"))
      (libsource (lib "eagle-import") (part "R-EU_R1206"))
    )
    (comp (ref "R248")
      (value "4.7kOhm/5%")
      (footprint "eagle-import:R1206")
      (fields (field (name "PARTNO") "RC1206JR-074K7L"))
      (libsource (lib "eagle-import") (part "R-EU_R1206"))
    )
    (comp (ref "R249")
      (value "4.7kOhm/5%")
      (footprint "eagle-import:R1206")
      (fields (field (name "PARTNO") "RC1206JR-074K7L"))
      (libsource (lib "eagle-import") (part "R-EU_R1206"))
    )
    (comp (ref "R250")
      (value "4.7kOhm/5%")
      (footprint "eagle-import:R1206")
      (fields (field (name "PARTNO") "RC1206JR-074K7L"))
      (libsource (lib "eagle-import") (part "R-EU_R1206"))
    )
    (comp (ref "R251")
      (value "4.7kOhm/5%")
      (footprint "eagle-import:R1206")
      (fields (field (name "PARTNO") "RC1206JR-074K7L"))
      (libsource (lib "eagle-import") (part "R-EU_R1206"))
    )
    (comp (ref "R252")
      (value "4.7kOhm/5%")
      (footprint "eagle-import:R1206")
      (fields (field (name "PARTNO") "RC1206JR-074K7L"))
      (libsource (lib "eagle-import") (part "R-EU_R1206"))
    )
    (comp (ref "R253")
      (value "1kOhm/5%")
      (footprint "eagle-import:R2512")
      (fields (field (name "PARTNO") "RC2512JK-071KL"))
      (libsource (lib "eagle-import") (part "R-EU_R2512"))
    )
    (comp (ref "R254")
      (value "1kOhm/5%")
      (footprint "eagle-import:R2512")
      (fields (field (name "PARTNO") "RC2512JK-071KL"))
      (libsource (lib "eagle-import") (part "R-EU_R2512"))
    )
    (comp (ref "R255")
      (value "1kOhm/5%")
      (footprint "eagle-import:R2512")
      (fields (field (name "PARTNO") "RC2512JK-071KL"))
      (libsource (lib "eagle-import") (part "R-EU_R2512"))
    )
    (comp (ref "R256")
      (value "1kOhm/5%")
      (footprint "eagle-import:R2512")
      (fields (field (name "PARTNO") "RC2512JK-071KL"))
      (libsource (lib "eagle-import") (part "R-EU_R2512"))
    )
    (comp (ref "R257")
      (value "1kOhm/5%")
      (footprint "eagle-import:R2512")
      (fields (field (name "PARTNO") "RC2512JK-071KL"))
      (libsource (lib "eagle-import") (part "R-EU_R2512"))
    )
    (comp (ref "R258")
      (value "1kOhm/5%")
      (footprint "eagle-import:R2512")
      (fields (field (name "PARTNO") "RC2512JK-071KL"))
      (libsource (lib "eagle-import") (part "R-EU_R2512"))
    )
    (comp (ref "R259")
      (value "1kOhm/5%")
      (footprint "eagle-import:R2512")
      (fields (field (name "PARTNO") "RC2512JK-071KL"))
      (libsource (lib "eagle-import") (part "R-EU_R2512"))
    )
    (comp (ref "R260")
      (value "1kOhm/5%")
      (footprint "eagle-import:R2512")
      (fields (field (name "PARTNO") "RC2512JK-071KL"))
      (libsource (lib "eagle-import") (part "R-EU_R2512"))
    )
    (comp (ref "R261")
      (value "1kOhm/5%")
      (footprint "eagle-import:R2512")
      (fields (field (name "PARTNO") "RC2512JK-071KL"))
      (libsource (lib "eagle-import") (part "R-EU_R2512"))
    )
    (comp (ref "R262")
      (value "1kOhm/5%")
      (footprint "eagle-import:R2512")
      (fields (field (name "PARTNO") "RC2512JK-071KL"))
      (libsource (lib "eagle-import") (part "R-EU_R2512"))
    )
    (comp (ref "R263")
      (value "1kOhm/5%")
      (footprint "eagle-import:R2512")
      (fields (field (name "PARTNO") "RC2512JK-071KL"))
      (libsource (lib "eagle-import") (part "R-EU_R2512"))
    )
    (comp (ref "R264")
      (value "1kOhm/5%")
      (footprint "eagle-import:R2512")
      (fields (field (name "PARTNO") "RC2512JK-071KL"))
      (libsource (lib "eagle-import") (part "R-EU_R2512"))
    )
    (comp (ref "R265")
      (value "1kOhm/5%")
      (footprint "eagle-import:R2512")
      (fields (field (name "PARTNO") "RC2512JK-071KL"))
      (libsource (lib "eagle-import") (part "R-EU_R2512"))
    )
    (comp (ref "R266")
      (value "1kOhm/5%")
      (footprint "eagle-import:R2512")
      (fields (field (name "PARTNO") "RC2512JK-071KL"))
      (libsource (lib "eagle-import") (part "R-EU_R2512"))
    )
    (comp (ref "R267")
      (value "1kOhm/5%")
      (footprint "eagle-import:R2512")
      (fields (field (name "PARTNO") "RC2512JK-071KL"))
      (libsource (lib "eagle-import") (part "R-EU_R2512"))
    )
    (comp (ref "R268")
      (value "1kOhm/5%")
      (footprint "eagle-import:R2512")
      (fields (field (name "PARTNO") "RC2512JK-071KL"))
      (libsource (lib "eagle-import") (part "R-EU_R2512"))
    )
    (comp (ref "R269")
      (value "10kOhm/1%")
      (footprint "eagle-import:R0603")
      (fields (field (name "PARTNO") "RC0603FR-1010KL"))
      (libsource (lib "eagle-import") (part "R-EU_R0603"))
    )
    (comp (ref "R270")
      (value "10kOhm/1%")
      (footprint "eagle-import:R0603")
      (fields (field (name "PARTNO") "RC0603FR-1010KL"))
      (libsource (lib "eagle-import") (part "R-EU_R0603"))
    )
    (comp (ref "R271")
      (value "10kOhm/1%")
      (footprint "eagle-import:R0603")
      (fields (field (name "PARTNO") "RC0603FR-1010KL"))
      (libsource (lib "eagle-import") (part "R-EU_R0603"))
    )
    (comp (ref "R272")
      (value "10kOhm/1%")
      (footprint "eagle-import:R0603")
      (fields (field (name "PARTNO") "RC0603FR-1010KL"))
      (libsource (lib "eagle-import") (part "R-EU_R0603"))
    )
    (comp (ref "R273")
      (value "10kOhm/1%")
      (footprint "eagle-import:R0603")
      (fields (field (name "PARTNO") "RC0603FR-1010KL"))
      (libsource (lib "eagle-import") (part "R-EU_R0603"))
    )
    (comp (ref "R274")
      (value "10kOhm/1%")
      (footprint "eagle-import:R0603")
      (fields (field (name "PARTNO") "RC0603FR-1010KL"))
      (libsource (lib "eagle-import") (part "R-EU_R0603"))
    )
    (comp (ref "R275")
      (value "10kOhm/1%")
      (footprint "eagle-import:R0603")
      (fields (field (name "PARTNO") "RC0603FR-1010KL"))
      (libsource (lib "eagle-import") (part "R-EU_R0603"))
    )
    (comp (ref "R276")
      (value "10kOhm/1%")
      (footprint "eagle-import:R0603")
      (fields (field (name "PARTNO") "RC0603FR-1010KL"))
      (libsource (lib "eagle-import") (part "R-EU_R0603"))
    )
    (comp (ref "R277")
      (value "10kOhm/1%")
      (footprint "eagle-import:R0603")
      (fields (field (name "PARTNO") "RC0603FR-1010KL"))
      (libsource (lib "eagle-import") (part "R-EU_R0603"))
    )
    (comp (ref "R278")
      (value "10kOhm/1%")
      (footprint "eagle-import:R0603")
      (fields (field (name "PARTNO") "RC0603FR-1010KL"))
      (libsource (lib "eagle-import") (part "R-EU_R0603"))
    )
    (comp (ref "R279")
      (value "10kOhm/1%")
      (footprint "eagle-import:R0603")
      (fields (field (name "PARTNO") "RC0603FR-1010KL"))
      (libsource (lib "eagle-import") (part "R-EU_R0603"))
    )
    (comp (ref "R280")
      (value "10kOhm/1%")
      (footprint "eagle-import:R0603")
      (fields (field (name "PARTNO") "RC0603FR-1010KL"))
      (libsource (lib "eagle-import") (part "R-EU_R0603"))
    )
    (comp (ref "R281")
      (value "10kOhm/1%")
      (footprint "eagle-import:R0603")
      (fields (field (name "PARTNO") "RC0603FR-1010KL"))
      (libsource (lib "eagle-import") (part "R-EU_R0603"))
    )
    (comp (ref "R282")
      (value "10kOhm/1%")
      (footprint "eagle-import:R0603")
      (fields (field (name "PARTNO") "RC0603FR-1010KL"))
      (libsource (lib "eagle-import") (part "R-EU_R0603"))
    )
    (comp (ref "R283")
      (value "10kOhm/1%")
      (footprint "eagle-import:R0603")
      (fields (field (name "PARTNO") "RC0603FR-1010KL"))
      (libsource (lib "eagle-import") (part "R-EU_R0603"))
    )
    (comp (ref "R284")
      (value "10kOhm/1%")
      (footprint "eagle-import:R0603")
      (fields (field (name "PARTNO") "RC0603FR-1010KL"))
      (libsource (lib "eagle-import") (part "R-EU_R0603"))
    )
    (comp (ref "VD132")
      (value "SM6T200A")
      (footprint "eagle-import:SMB")
      (libsource (lib "eagle-import") (part "DIODE-TVS-UNIDIR-SMB"))
    )
    (comp (ref "VD133")
      (value "SM6T200A")
      (footprint "eagle-import:SMB")
      (libsource (lib "eagle-import") (part "DIODE-TVS-UNIDIR-SMB"))
    )
    (comp (ref "VD134")
      (value "SM6T200A")
      (footprint "eagle-import:SMB")
      (libsource (lib "eagle-import") (part "DIODE-TVS-UNIDIR-SMB"))
    )
    (comp (ref "VD135")
      (value "SM6T200A")
      (footprint "eagle-import:SMB")
      (libsource (lib "eagle-import") (part "DIODE-TVS-UNIDIR-SMB"))
    )
    (comp (ref "VD136")
      (value "SM6T200A")
      (footprint "eagle-import:SMB")
      (libsource (lib "eagle-import") (part "DIODE-TVS-UNIDIR-SMB"))
    )
    (comp (ref "VD137")
      (value "SM6T200A")
      (footprint "eagle-import:SMB")
      (libsource (lib "eagle-import") (part "DIODE-TVS-UNIDIR-SMB"))
    )
    (comp (ref "VD138")
      (value "SM6T200A")
      (footprint "eagle-import:SMB")
      (libsource (lib "eagle-import") (part "DIODE-TVS-UNIDIR-SMB"))
    )
    (comp (ref "VD139")
      (value "SM6T200A")
      (footprint "eagle-import:SMB")
      (libsource (lib "eagle-import") (part "DIODE-TVS-UNIDIR-SMB"))
    )
    (comp (ref "VD140")
      (value "SM6T200A")
      (footprint "eagle-import:SMB")
      (libsource (lib "eagle-import") (part "DIODE-TVS-UNIDIR-SMB"))
    )
    (comp (ref "VD141")
      (value "SM6T200A")
      (footprint "eagle-import:SMB")
      (libsource (lib "eagle-import") (part "DIODE-TVS-UNIDIR-SMB"))
    )
    (comp (ref "VD142")
      (value "SM6T200A")
      (footprint "eagle-import:SMB")
      (libsource (lib "eagle-import") (part "DIODE-TVS-UNIDIR-SMB"))
    )
    (comp (ref "VD143")
      (value "SM6T200A")
      (footprint "eagle-import:SMB")
      (libsource (lib "eagle-import") (part "DIODE-TVS-UNIDIR-SMB"))
    )
    (comp (ref "VD144")
      (value "SM6T200A")
      (footprint "eagle-import:SMB")
      (libsource (lib "eagle-import") (part "DIODE-TVS-UNIDIR-SMB"))
    )
    (comp (ref "VD145")
      (value "SM6T200A")
      (footprint "eagle-import:SMB")
      (libsource (lib "eagle-import") (part "DIODE-TVS-UNIDIR-SMB"))
    )
    (comp (ref "VD146")
      (value "SM6T200A")
      (footprint "eagle-import:SMB")
      (libsource (lib "eagle-import") (part "DIODE-TVS-UNIDIR-SMB"))
    )
    (comp (ref "VD147")
      (value "SM6T200A")
      (footprint "eagle-import:SMB")
      (libsource (lib "eagle-import") (part "DIODE-TVS-UNIDIR-SMB"))
    )
    (comp (ref "VD148")
      (value "400V")
      (footprint "eagle-import:SMA")
      (fields (field (name "PARTNO") "S1G-E3/61T"))
      (libsource (lib "eagle-import") (part "DIODE-STANDARD-SMA"))
    )
    (comp (ref "VD149")
      (value "400V")
      (footprint "eagle-import:SMA")
      (fields (field (name "PARTNO") "S1G-E3/61T"))
      (libsource (lib "eagle-import") (part "DIODE-STANDARD-SMA"))
    )
    (comp (ref "VD150")
      (value "400V")
      (footprint "eagle-import:SMA")
      (fields (field (name "PARTNO") "S1G-E3/61T"))
      (libsource (lib "eagle-import") (part "DIODE-STANDARD-SMA"))
    )
    (comp (ref "VD151")
      (value "400V")
      (footprint "eagle-import:SMA")
      (fields (field (name "PARTNO") "S1G-E3/61T"))
      (libsource (lib "eagle-import") (part "DIODE-STANDARD-SMA"))
    )
    (comp (ref "VD152")
      (value "400V")
      (footprint "eagle-import:SMA")
      (fields (field (name "PARTNO") "S1G-E3/61T"))
      (libsource (lib "eagle-import") (part "DIODE-STANDARD-SMA"))
    )
    (comp (ref "VD153")
      (value "400V")
      (footprint "eagle-import:SMA")
      (fields (field (name "PARTNO") "S1G-E3/61T"))
      (libsource (lib "eagle-import") (part "DIODE-STANDARD-SMA"))
    )
    (comp (ref "VD154")
      (value "400V")
      (footprint "eagle-import:SMA")
      (fields (field (name "PARTNO") "S1G-E3/61T"))
      (libsource (lib "eagle-import") (part "DIODE-STANDARD-SMA"))
    )
    (comp (ref "VD155")
      (value "400V")
      (footprint "eagle-import:SMA")
      (fields (field (name "PARTNO") "S1G-E3/61T"))
      (libsource (lib "eagle-import") (part "DIODE-STANDARD-SMA"))
    )
    (comp (ref "VD156")
      (value "400V")
      (footprint "eagle-import:SMA")
      (fields (field (name "PARTNO") "S1G-E3/61T"))
      (libsource (lib "eagle-import") (part "DIODE-STANDARD-SMA"))
    )
    (comp (ref "VD157")
      (value "400V")
      (footprint "eagle-import:SMA")
      (fields (field (name "PARTNO") "S1G-E3/61T"))
      (libsource (lib "eagle-import") (part "DIODE-STANDARD-SMA"))
    )
    (comp (ref "VD158")
      (value "400V")
      (footprint "eagle-import:SMA")
      (fields (field (name "PARTNO") "S1G-E3/61T"))
      (libsource (lib "eagle-import") (part "DIODE-STANDARD-SMA"))
    )
    (comp (ref "VD159")
      (value "400V")
      (footprint "eagle-import:SMA")
      (fields (field (name "PARTNO") "S1G-E3/61T"))
      (libsource (lib "eagle-import") (part "DIODE-STANDARD-SMA"))
    )
    (comp (ref "VD160")
      (value "400V")
      (footprint "eagle-import:SMA")
      (fields (field (name "PARTNO") "S1G-E3/61T"))
      (libsource (lib "eagle-import") (part "DIODE-STANDARD-SMA"))
    )
    (comp (ref "VD161")
      (value "400V")
      (footprint "eagle-import:SMA")
      (fields (field (name "PARTNO") "S1G-E3/61T"))
      (libsource (lib "eagle-import") (part "DIODE-STANDARD-SMA"))
    )
    (comp (ref "VD162")
      (value "400V")
      (footprint "eagle-import:SMA")
      (fields (field (name "PARTNO") "S1G-E3/61T"))
      (libsource (lib "eagle-import") (part "DIODE-STANDARD-SMA"))
    )
    (comp (ref "VD163")
      (value "400V")
      (footprint "eagle-import:SMA")
      (fields (field (name "PARTNO") "S1G-E3/61T"))
      (libsource (lib "eagle-import") (part "DIODE-STANDARD-SMA"))
    )
    (comp (ref "XP9")
      (value "MOLEX-90130-16")
      (footprint "eagle-import:MOLEX-90130-16")
      (fields (field (name "PARTNO") "90130-1216"))
      (libsource (lib "eagle-import") (part "MOLEX-90130-16"))
    )
    (comp (ref "JP1")
      (value "STAND-OFF-M4")
      (footprint "eagle-import:STAND-OFF-M4")
      (libsource (lib "eagle-import") (part "STAND-OFF-M4"))
    )
    (comp (ref "JP2")
      (value "STAND-OFF-M4")
      (footprint "eagle-import:STAND-OFF-M4")
      (libsource (lib "eagle-import") (part "STAND-OFF-M4"))
    )
    (comp (ref "JP3")
      (value "STAND-OFF-M4")
      (footprint "eagle-import:STAND-OFF-M4")
      (libsource (lib "eagle-import") (part "STAND-OFF-M4"))
    )
    (comp (ref "JP4")
      (value "STAND-OFF-M4")
      (footprint "eagle-import:STAND-OFF-M4")
      (libsource (lib "eagle-import") (part "STAND-OFF-M4"))
    )
    (comp (ref "JP5")
      (value "STAND-OFF-M4")
      (footprint "eagle-import:STAND-OFF-M4")
      (libsource (lib "eagle-import") (part "STAND-OFF-M4"))
    )
    (comp (ref "JP6")
      (value "STAND-OFF-M4")
      (footprint "eagle-import:STAND-OFF-M4")
      (libsource (lib "eagle-import") (part "STAND-OFF-M4"))
    )
    (comp (ref "JP7")
      (value "STAND-OFF-M4")
      (footprint "eagle-import:STAND-OFF-M4")
      (libsource (lib "eagle-import") (part "STAND-OFF-M4"))
    )
    (comp (ref "JP8")
      (value "STAND-OFF-M4")
      (footprint "eagle-import:STAND-OFF-M4")
      (libsource (lib "eagle-import") (part "STAND-OFF-M4"))
    )
    (comp (ref "JP9")
      (value "STAND-OFF-M3")
      (footprint "eagle-import:STAND-OFF-M3")
      (libsource (lib "eagle-import") (part "STAND-OFF-M3"))
    )
    (comp (ref "JP10")
      (value "STAND-OFF-M3")
      (footprint "eagle-import:STAND-OFF-M3")
      (libsource (lib "eagle-import") (part "STAND-OFF-M3"))
    )
    (comp (ref "C142")
      (value "0.1uF")
      (footprint "eagle-import:C0603")
      (fields (field (name "PARTNO") "C0603C104K5RACTU"))
      (libsource (lib "eagle-import") (part "C-EUC0603"))
    )
    (comp (ref "C143")
      (value "0.1uF")
      (footprint "eagle-import:C0603")
      (fields (field (name "PARTNO") "C0603C104K5RACTU"))
      (libsource (lib "eagle-import") (part "C-EUC0603"))
    )
    (comp (ref "C144")
      (value "0.1uF")
      (footprint "eagle-import:C0603")
      (fields (field (name "PARTNO") "C0603C104K5RACTU"))
      (libsource (lib "eagle-import") (part "C-EUC0603"))
    )
    (comp (ref "C145")
      (value "0.1uF")
      (footprint "eagle-import:C0603")
      (fields (field (name "PARTNO") "C0603C104K5RACTU"))
      (libsource (lib "eagle-import") (part "C-EUC0603"))
    )
    (comp (ref "C146")
      (value "0.1uF")
      (footprint "eagle-import:C0603")
      (fields (field (name "PARTNO") "C0603C104K5RACTU"))
      (libsource (lib "eagle-import") (part "C-EUC0603"))
    )
    (comp (ref "C147")
      (value "0.1uF")
      (footprint "eagle-import:C0603")
      (fields (field (name "PARTNO") "C0603C104K5RACTU"))
      (libsource (lib "eagle-import") (part "C-EUC0603"))
    )
    (comp (ref "DA15")
      (value "USBUF01W6")
      (footprint "eagle-import:SOTT323-6L")
      (libsource (lib "eagle-import") (part "USBUF01W6"))
    )
    (comp (ref "DA16")
      (value "SN65HVD232")
      (footprint "eagle-import:SO08")
      (fields (field (name "PARTNO") "SN65HVD232D"))
      (libsource (lib "eagle-import") (part "SN65HVD232"))
    )
    (comp (ref "DA17")
      (value "ILX3232D")
      (footprint "eagle-import:SO16")
      (libsource (lib "eagle-import") (part "ILX3232D"))
    )
    (comp (ref "L4")
      (value "EXC3BP")
      (footprint "eagle-import:L0603")
      (fields (field (name "PARTNO") "EXC3BP121H"))
      (libsource (lib "eagle-import") (part "EXC3BP"))
    )
    (comp (ref "R358")
      (value "120Ohm/5%")
      (footprint "eagle-import:R1206")
      (fields (field (name "PARTNO") "RC1206JR-07120RL"))
      (libsource (lib "eagle-import") (part "R-EU_R1206"))
    )
    (comp (ref "R359")
      (value "10kOhm/1%")
      (footprint "eagle-import:R0603")
      (fields (field (name "PARTNO") "RC0603FR-1010KL"))
      (libsource (lib "eagle-import") (part "R-EU_R0603"))
    )
    (comp (ref "R360")
      (value "36kOhm/5%")
      (footprint "eagle-import:R0603")
      (fields (field (name "PARTNO") "ERJ3GEYJ363V"))
      (libsource (lib "eagle-import") (part "R-EU_R0603"))
    )
    (comp (ref "R361")
      (value "10kOhm/1%")
      (footprint "eagle-import:R0603")
      (fields (field (name "PARTNO") "RC0603FR-1010KL"))
      (libsource (lib "eagle-import") (part "R-EU_R0603"))
    )
    (comp (ref "R362")
      (value "47kOhm/5%")
      (footprint "eagle-import:R0603")
      (fields (field (name "PARTNO") "ERJ3GEYJ473V"))
      (libsource (lib "eagle-import") (part "R-EU_R0603"))
    )
    (comp (ref "R363")
      (value "1kOhm/5%")
      (footprint "eagle-import:R0805")
      (fields (field (name "PARTNO") "ERJ6GEYJ102V"))
      (libsource (lib "eagle-import") (part "R-EU_R0805"))
    )
    (comp (ref "R364")
      (value "1kOhm/5%")
      (footprint "eagle-import:R0805")
      (fields (field (name "PARTNO") "ERJ6GEYJ102V"))
      (libsource (lib "eagle-import") (part "R-EU_R0805"))
    )
    (comp (ref "VD212")
      (value "SMBJ24CA")
      (footprint "eagle-import:SMB-BIDIR")
      (libsource (lib "eagle-import") (part "DIODE-TVS-BIDIR-SMB"))
    )
    (comp (ref "VD213")
      (value "SMBJ24CA")
      (footprint "eagle-import:SMB-BIDIR")
      (libsource (lib "eagle-import") (part "DIODE-TVS-BIDIR-SMB"))
    )
    (comp (ref "VD214")
      (value "3.3V")
      (footprint "eagle-import:SOD80")
      (fields (field (name "PARTNO") "BZV55-C3V3"))
      (libsource (lib "eagle-import") (part "DIODE-ZENER-"))
    )
    (comp (ref "VT3")
      (value "BC817-16SMD")
      (footprint "eagle-import:SOT23-BEC")
      (fields (field (name "PARTNO") "BC817"))
      (libsource (lib "eagle-import") (part "BC817SMD-16"))
    )
    (comp (ref "VT4")
      (value "BC817-16SMD")
      (footprint "eagle-import:SOT23-BEC")
      (fields (field (name "PARTNO") "BC817"))
      (libsource (lib "eagle-import") (part "BC817SMD-16"))
    )
    (comp (ref "XP12")
      (value "MOLEX-90130-08")
      (footprint "eagle-import:MOLEX-90130-08")
      (fields (field (name "LABEL") "INTERFACES") (field (name "PARTNO") "90130-1208"))
      (libsource (lib "eagle-import") (part "MOLEX-90130-08"))
    )
    (comp (ref "XP13")
      (value "PLD_1X02")
      (footprint "eagle-import:PLD_1X02")
      (fields (field (name "PARTNO") "825433-2"))
      (libsource (lib "eagle-import") (part "PLD_1X02"))
    )
    (comp (ref "XS1")
      (value "USB-MINIB_(SOVOK-UGO)")
      (footprint "eagle-import:USB-MINIB")
      (fields (field (name "PARTNO") "MUBS1-05SN2"))
      (libsource (lib "eagle-import") (part "USB-MINIB_(SOVOK-UGO)"))
    )
    (comp (ref "Z42")
      (value "NFE31PT")
      (footprint "eagle-import:NFE31")
      (fields (field (name "PARTNO") "NFE31PT152Z1E9"))
      (libsource (lib "eagle-import") (part "NFE31PT"))
    )
    (comp (ref "Z43")
      (value "NFE31PT")
      (footprint "eagle-import:NFE31")
      (fields (field (name "PARTNO") "NFE31PT152Z1E9"))
      (libsource (lib "eagle-import") (part "NFE31PT"))
    )
    (comp (ref "Z44")
      (value "NFE31PT")
      (footprint "eagle-import:NFE31")
      (fields (field (name "PARTNO") "NFE31PT152Z1E9"))
      (libsource (lib "eagle-import") (part "NFE31PT"))
    )
    (comp (ref "Z45")
      (value "NFE31PT")
      (footprint "eagle-import:NFE31")
      (fields (field (name "PARTNO") "NFE31PT152Z1E9"))
      (libsource (lib "eagle-import") (part "NFE31PT"))
    )
    (comp (ref "Z46")
      (value "NFE31PT")
      (footprint "eagle-import:NFE31")
      (fields (field (name "PARTNO") "NFE31PT152Z1E9"))
      (libsource (lib "eagle-import") (part "NFE31PT"))
    )
    (comp (ref "Z47")
      (value "NFE31PT")
      (footprint "eagle-import:NFE31")
      (fields (field (name "PARTNO") "NFE31PT152Z1E9"))
      (libsource (lib "eagle-import") (part "NFE31PT"))
    )
    (comp (ref "Z48")
      (value "NFE31PT")
      (footprint "eagle-import:NFE31")
      (fields (field (name "PARTNO") "NFE31PT152Z1E9"))
      (libsource (lib "eagle-import") (part "NFE31PT"))
    )
    (comp (ref "Z49")
      (value "NFE31PT")
      (footprint "eagle-import:NFE31")
      (fields (field (name "PARTNO") "NFE31PT152Z1E9"))
      (libsource (lib "eagle-import") (part "NFE31PT"))
    )
    (comp (ref "Z50")
      (value "NFE31PT")
      (footprint "eagle-import:NFE31")
      (fields (field (name "PARTNO") "NFE31PT152Z1E9"))
      (libsource (lib "eagle-import") (part "NFE31PT"))
    )
    (comp (ref "C1")
      (value "0.1uF")
      (footprint "eagle-import:C0603")
      (fields (field (name "PARTNO") "C0603C104K5RACTU"))
      (libsource (lib "eagle-import") (part "C-EUC0603"))
    )
    (comp (ref "C2")
      (value "0.1uF")
      (footprint "eagle-import:C0603")
      (fields (field (name "PARTNO") "C0603C104K5RACTU"))
      (libsource (lib "eagle-import") (part "C-EUC0603"))
    )
    (comp (ref "C3")
      (value "22pF")
      (footprint "eagle-import:C0603")
      (fields (field (name "PARTNO") "C0603C220J5GACTU"))
      (libsource (lib "eagle-import") (part "C-EUC0603"))
    )
    (comp (ref "C4")
      (value "22pF")
      (footprint "eagle-import:C0603")
      (fields (field (name "PARTNO") "C0603C220J5GACTU"))
      (libsource (lib "eagle-import") (part "C-EUC0603"))
    )
    (comp (ref "C5")
      (value "10uF/10V")
      (footprint "eagle-import:A_3216-18W")
      (fields (field (name "PARTNO") "T491A106K010AT"))
      (libsource (lib "eagle-import") (part "CPOL-EUA/3216-18W"))
    )
    (comp (ref "C6")
      (value "0.1uF")
      (footprint "eagle-import:C0603")
      (fields (field (name "PARTNO") "C0603C104K5RACTU"))
      (libsource (lib "eagle-import") (part "C-EUC0603"))
    )
    (comp (ref "C7")
      (value "1uF/16V")
      (footprint "eagle-import:C0603")
      (fields (field (name "PARTNO") "C0603C105K4PACTU"))
      (libsource (lib "eagle-import") (part "C-EUC0603"))
    )
    (comp (ref "C8")
      (value "0.1uF")
      (footprint "eagle-import:C0603")
      (fields (field (name "PARTNO") "C0603C104K5RACTU"))
      (libsource (lib "eagle-import") (part "C-EUC0603"))
    )
    (comp (ref "C9")
      (value "0.1uF")
      (footprint "eagle-import:C0603")
      (fields (field (name "PARTNO") "C0603C104K5RACTU"))
      (libsource (lib "eagle-import") (part "C-EUC0603"))
    )
    (comp (ref "C10")
      (value "0.1uF")
      (footprint "eagle-import:C0603")
      (fields (field (name "PARTNO") "C0603C104K5RACTU"))
      (libsource (lib "eagle-import") (part "C-EUC0603"))
    )
    (comp (ref "C11")
      (value "0.1uF")
      (footprint "eagle-import:C0603")
      (fields (field (name "PARTNO") "C0603C104K5RACTU"))
      (libsource (lib "eagle-import") (part "C-EUC0603"))
    )
    (comp (ref "DD1")
      (value "STM32F103VDT6")
      (footprint "eagle-import:TQFP100")
      (libsource (lib "eagle-import") (part "STM32F103VDT6"))
    )
    (comp (ref "DD2")
      (value "IN24AA32AD")
      (footprint "eagle-import:SO08")
      (libsource (lib "eagle-import") (part "IN24DAA32A"))
    )
    (comp (ref "L1")
      (value "EXC3BP")
      (footprint "eagle-import:L0603")
      (fields (field (name "PARTNO") "EXC3BP121H"))
      (libsource (lib "eagle-import") (part "EXC3BP"))
    )
    (comp (ref "R1")
      (value "10kOhm/1%")
      (footprint "eagle-import:R0603")
      (fields (field (name "PARTNO") "RC0603FR-1010KL"))
      (libsource (lib "eagle-import") (part "R-EU_R0603"))
    )
    (comp (ref "R2")
      (value "10kOhm/1%")
      (footprint "eagle-import:R0603")
      (fields (field (name "PARTNO") "RC0603FR-1010KL"))
      (libsource (lib "eagle-import") (part "R-EU_R0603"))
    )
    (comp (ref "R3")
      (value "10kOhm/1%")
      (footprint "eagle-import:R0603")
      (fields (field (name "PARTNO") "RC0603FR-1010KL"))
      (libsource (lib "eagle-import") (part "R-EU_R0603"))
    )
    (comp (ref "R4")
      (value "10kOhm/1%")
      (footprint "eagle-import:R0603")
      (fields (field (name "PARTNO") "RC0603FR-1010KL"))
      (libsource (lib "eagle-import") (part "R-EU_R0603"))
    )
    (comp (ref "R5")
      (value "10kOhm/1%")
      (footprint "eagle-import:R0603")
      (fields (field (name "PARTNO") "RC0603FR-1010KL"))
      (libsource (lib "eagle-import") (part "R-EU_R0603"))
    )
    (comp (ref "R6")
      (value "10kOhm/1%")
      (footprint "eagle-import:R0603")
      (fields (field (name "PARTNO") "RC0603FR-1010KL"))
      (libsource (lib "eagle-import") (part "R-EU_R0603"))
    )
    (comp (ref "R7")
      (value "10kOhm/1%")
      (footprint "eagle-import:R0603")
      (fields (field (name "PARTNO") "RC0603FR-1010KL"))
      (libsource (lib "eagle-import") (part "R-EU_R0603"))
    )
    (comp (ref "R8")
      (value "10kOhm/1%")
      (footprint "eagle-import:R0603")
      (fields (field (name "PARTNO") "RC0603FR-1010KL"))
      (libsource (lib "eagle-import") (part "R-EU_R0603"))
    )
    (comp (ref "R9")
      (value "10kOhm/1%")
      (footprint "eagle-import:R0603")
      (fields (field (name "PARTNO") "RC0603FR-1010KL"))
      (libsource (lib "eagle-import") (part "R-EU_R0603"))
    )
    (comp (ref "R10")
      (value "0Ohm")
      (footprint "eagle-import:R0805")
      (fields (field (name "PARTNO") "ERJ6GEY0R00V"))
      (libsource (lib "eagle-import") (part "R-EU_R0805"))
    )
    (comp (ref "R11")
      (value "100kOhm/1%")
      (footprint "eagle-import:R0603")
      (fields (field (name "PARTNO") "RC0603FR-13100KL"))
      (libsource (lib "eagle-import") (part "R-EU_R0603"))
    )
    (comp (ref "R12")
      (value "100kOhm/1%")
      (footprint "eagle-import:R0603")
      (fields (field (name "PARTNO") "RC0603FR-13100KL"))
      (libsource (lib "eagle-import") (part "R-EU_R0603"))
    )
    (comp (ref "R13")
      (value "330Ohm/5%")
      (footprint "eagle-import:R0603")
      (fields (field (name "PARTNO") "ERJ3GEYJ331V"))
      (libsource (lib "eagle-import") (part "R-EU_R0603"))
    )
    (comp (ref "R14")
      (value "330Ohm/5%")
      (footprint "eagle-import:R0603")
      (fields (field (name "PARTNO") "ERJ3GEYJ331V"))
      (libsource (lib "eagle-import") (part "R-EU_R0603"))
    )
    (comp (ref "R15")
      (value "1kOhm/5%")
      (footprint "eagle-import:R0805")
      (fields (field (name "PARTNO") "ERJ6GEYJ102V"))
      (libsource (lib "eagle-import") (part "R-EU_R0805"))
    )
    (comp (ref "R16")
      (value "100Ohm/5%")
      (footprint "eagle-import:R0603")
      (fields (field (name "PARTNO") "ERJ3GEYJ101V"))
      (libsource (lib "eagle-import") (part "R-EU_R0603"))
    )
    (comp (ref "R17")
      (value "100Ohm/5%")
      (footprint "eagle-import:R0603")
      (fields (field (name "PARTNO") "ERJ3GEYJ101V"))
      (libsource (lib "eagle-import") (part "R-EU_R0603"))
    )
    (comp (ref "R18")
      (value "100Ohm/5%")
      (footprint "eagle-import:R0603")
      (fields (field (name "PARTNO") "ERJ3GEYJ101V"))
      (libsource (lib "eagle-import") (part "R-EU_R0603"))
    )
    (comp (ref "R19")
      (value "100Ohm/5%")
      (footprint "eagle-import:R0603")
      (fields (field (name "PARTNO") "ERJ3GEYJ101V"))
      (libsource (lib "eagle-import") (part "R-EU_R0603"))
    )
    (comp (ref "R20")
      (value "330Ohm/5%")
      (footprint "eagle-import:R0603")
      (fields (field (name "PARTNO") "ERJ3GEYJ331V"))
      (libsource (lib "eagle-import") (part "R-EU_R0603"))
    )
    (comp (ref "R21")
      (value "100Ohm/5%")
      (footprint "eagle-import:R0603")
      (fields (field (name "PARTNO") "ERJ3GEYJ101V"))
      (libsource (lib "eagle-import") (part "R-EU_R0603"))
    )
    (comp (ref "R22")
      (value "100Ohm/5%")
      (footprint "eagle-import:R0603")
      (fields (field (name "PARTNO") "ERJ3GEYJ101V"))
      (libsource (lib "eagle-import") (part "R-EU_R0603"))
    )
    (comp (ref "R23")
      (value "100Ohm/5%")
      (footprint "eagle-import:R0603")
      (fields (field (name "PARTNO") "ERJ3GEYJ101V"))
      (libsource (lib "eagle-import") (part "R-EU_R0603"))
    )
    (comp (ref "R24")
      (value "100Ohm/5%")
      (footprint "eagle-import:R0603")
      (fields (field (name "PARTNO") "ERJ3GEYJ101V"))
      (libsource (lib "eagle-import") (part "R-EU_R0603"))
    )
    (comp (ref "R25")
      (value "1kOhm/5%")
      (footprint "eagle-import:R0805")
      (fields (field (name "PARTNO") "ERJ6GEYJ102V"))
      (libsource (lib "eagle-import") (part "R-EU_R0805"))
    )
    (comp (ref "SB1")
      (value "RESET")
      (footprint "eagle-import:B3S-10XX")
      (fields (field (name "PARTNO") "4-1437565-2"))
      (libsource (lib "eagle-import") (part "4-1437565-2"))
    )
    (comp (ref "VD1")
      (value "RED")
      (footprint "eagle-import:LED-0805")
      (fields (field (name "PARTNO") "KPHCM-2012EC-T"))
      (libsource (lib "eagle-import") (part "LED0805"))
    )
    (comp (ref "VD2")
      (value "RED")
      (footprint "eagle-import:LED-0805")
      (fields (field (name "PARTNO") "KPHCM-2012EC-T"))
      (libsource (lib "eagle-import") (part "LED0805"))
    )
    (comp (ref "VD3")
      (value "GREEN")
      (footprint "eagle-import:LED-0805")
      (fields (field (name "PARTNO") "KPHCM-2012SGC-T"))
      (libsource (lib "eagle-import") (part "LED0805"))
    )
    (comp (ref "XP1")
      (value "PLD_2X10-SHROUDED")
      (footprint "eagle-import:PLD_2X10_SHROUDED")
      (fields (field (name "LABEL") "JTAG") (field (name "PARTNO") "MC9A12-2034"))
      (libsource (lib "eagle-import") (part "PLD_2X10-SHROUDED"))
    )
    (comp (ref "XP2")
      (value "PLD_1X3")
      (footprint "eagle-import:PLD_1X03")
      (fields (field (name "LABEL") "BOOT_1") (field (name "PARTNO") "825433-3"))
      (libsource (lib "eagle-import") (part "PLD_1X03"))
    )
    (comp (ref "XP3")
      (value "PLD_1X3")
      (footprint "eagle-import:PLD_1X03")
      (fields (field (name "LABEL") "BOOT_0") (field (name "PARTNO") "825433-3"))
      (libsource (lib "eagle-import") (part "PLD_1X03"))
    )
    (comp (ref "Z1")
      (value "NFE31PT")
      (footprint "eagle-import:NFE31")
      (fields (field (name "PARTNO") "NFE31PT152Z1E9"))
      (libsource (lib "eagle-import") (part "NFE31PT"))
    )
    (comp (ref "Z2")
      (value "NFE31PT")
      (footprint "eagle-import:NFE31")
      (fields (field (name "PARTNO") "NFE31PT152Z1E9"))
      (libsource (lib "eagle-import") (part "NFE31PT"))
    )
    (comp (ref "Z3")
      (value "NFE31PT")
      (footprint "eagle-import:NFE31")
      (fields (field (name "PARTNO") "NFE31PT152Z1E9"))
      (libsource (lib "eagle-import") (part "NFE31PT"))
    )
    (comp (ref "Z4")
      (value "NFE31PT")
      (footprint "eagle-import:NFE31")
      (fields (field (name "PARTNO") "NFE31PT152Z1E9"))
      (libsource (lib "eagle-import") (part "NFE31PT"))
    )
    (comp (ref "Z5")
      (value "NFE31PT")
      (footprint "eagle-import:NFE31")
      (fields (field (name "PARTNO") "NFE31PT152Z1E9"))
      (libsource (lib "eagle-import") (part "NFE31PT"))
    )
    (comp (ref "Z6")
      (value "NFE31PT")
      (footprint "eagle-import:NFE31")
      (fields (field (name "PARTNO") "NFE31PT152Z1E9"))
      (libsource (lib "eagle-import") (part "NFE31PT"))
    )
    (comp (ref "Z7")
      (value "NFE31PT")
      (footprint "eagle-import:NFE31")
      (fields (field (name "PARTNO") "NFE31PT152Z1E9"))
      (libsource (lib "eagle-import") (part "NFE31PT"))
    )
    (comp (ref "Z8")
      (value "NFE31PT")
      (footprint "eagle-import:NFE31")
      (fields (field (name "PARTNO") "NFE31PT152Z1E9"))
      (libsource (lib "eagle-import") (part "NFE31PT"))
    )
    (comp (ref "Z9")
      (value "NFE31PT")
      (footprint "eagle-import:NFE31")
      (fields (field (name "PARTNO") "NFE31PT152Z1E9"))
      (libsource (lib "eagle-import") (part "NFE31PT"))
    )
    (comp (ref "Z10")
      (value "NFE31PT")
      (footprint "eagle-import:NFE31")
      (fields (field (name "PARTNO") "NFE31PT152Z1E9"))
      (libsource (lib "eagle-import") (part "NFE31PT"))
    )
    (comp (ref "Z11")
      (value "NFE31PT")
      (footprint "eagle-import:NFE31")
      (fields (field (name "PARTNO") "NFE31PT152Z1E9"))
      (libsource (lib "eagle-import") (part "NFE31PT"))
    )
    (comp (ref "Z12")
      (value "NFE31PT")
      (footprint "eagle-import:NFE31")
      (fields (field (name "PARTNO") "NFE31PT152Z1E9"))
      (libsource (lib "eagle-import") (part "NFE31PT"))
    )
    (comp (ref "Z13")
      (value "NFE31PT")
      (footprint "eagle-import:NFE31")
      (fields (field (name "PARTNO") "NFE31PT152Z1E9"))
      (libsource (lib "eagle-import") (part "NFE31PT"))
    )
    (comp (ref "Z14")
      (value "NFE31PT")
      (footprint "eagle-import:NFE31")
      (fields (field (name "PARTNO") "NFE31PT152Z1E9"))
      (libsource (lib "eagle-import") (part "NFE31PT"))
    )
    (comp (ref "Z15")
      (value "NFE31PT")
      (footprint "eagle-import:NFE31")
      (fields (field (name "PARTNO") "NFE31PT152Z1E9"))
      (libsource (lib "eagle-import") (part "NFE31PT"))
    )
    (comp (ref "Z16")
      (value "NFE31PT")
      (footprint "eagle-import:NFE31")
      (fields (field (name "PARTNO") "NFE31PT152Z1E9"))
      (libsource (lib "eagle-import") (part "NFE31PT"))
    )
    (comp (ref "Z17")
      (value "NFE31PT")
      (footprint "eagle-import:NFE31")
      (fields (field (name "PARTNO") "NFE31PT152Z1E9"))
      (libsource (lib "eagle-import") (part "NFE31PT"))
    )
    (comp (ref "Z18")
      (value "NFE31PT")
      (footprint "eagle-import:NFE31")
      (fields (field (name "PARTNO") "NFE31PT152Z1E9"))
      (libsource (lib "eagle-import") (part "NFE31PT"))
    )
    (comp (ref "Z19")
      (value "NFE31PT")
      (footprint "eagle-import:NFE31")
      (fields (field (name "PARTNO") "NFE31PT152Z1E9"))
      (libsource (lib "eagle-import") (part "NFE31PT"))
    )
    (comp (ref "Z20")
      (value "NFE31PT")
      (footprint "eagle-import:NFE31")
      (fields (field (name "PARTNO") "NFE31PT152Z1E9"))
      (libsource (lib "eagle-import") (part "NFE31PT"))
    )
    (comp (ref "Z21")
      (value "NFE31PT")
      (footprint "eagle-import:NFE31")
      (fields (field (name "PARTNO") "NFE31PT152Z1E9"))
      (libsource (lib "eagle-import") (part "NFE31PT"))
    )
    (comp (ref "ZQ1")
      (value "4MHz")
      (footprint "eagle-import:HC49U-V")
      (fields (field (name "PARTNO") "CA-4.000-18-3050-X"))
      (libsource (lib "eagle-import") (part "CRYSTALHC49UV"))
    )
    (comp (ref "C28")
      (value "0.1uF")
      (footprint "eagle-import:C0603")
      (fields (field (name "PARTNO") "C0603C104K5RACTU"))
      (libsource (lib "eagle-import") (part "C-EUC0603"))
    )
    (comp (ref "C29")
      (value "0.1uF")
      (footprint "eagle-import:C0603")
      (fields (field (name "PARTNO") "C0603C104K5RACTU"))
      (libsource (lib "eagle-import") (part "C-EUC0603"))
    )
    (comp (ref "C30")
      (value "0.1uF")
      (footprint "eagle-import:C0603")
      (fields (field (name "PARTNO") "C0603C104K5RACTU"))
      (libsource (lib "eagle-import") (part "C-EUC0603"))
    )
    (comp (ref "C31")
      (value "0.1uF")
      (footprint "eagle-import:C0603")
      (fields (field (name "PARTNO") "C0603C104K5RACTU"))
      (libsource (lib "eagle-import") (part "C-EUC0603"))
    )
    (comp (ref "C32")
      (value "0.1uF")
      (footprint "eagle-import:C0603")
      (fields (field (name "PARTNO") "C0603C104K5RACTU"))
      (libsource (lib "eagle-import") (part "C-EUC0603"))
    )
    (comp (ref "C33")
      (value "0.1uF")
      (footprint "eagle-import:C0603")
      (fields (field (name "PARTNO") "C0603C104K5RACTU"))
      (libsource (lib "eagle-import") (part "C-EUC0603"))
    )
    (comp (ref "C34")
      (value "0.1uF")
      (footprint "eagle-import:C0603")
      (fields (field (name "PARTNO") "C0603C104K5RACTU"))
      (libsource (lib "eagle-import") (part "C-EUC0603"))
    )
    (comp (ref "C35")
      (value "0.1uF")
      (footprint "eagle-import:C0603")
      (fields (field (name "PARTNO") "C0603C104K5RACTU"))
      (libsource (lib "eagle-import") (part "C-EUC0603"))
    )
    (comp (ref "C36")
      (value "0.1uF")
      (footprint "eagle-import:C0603")
      (fields (field (name "PARTNO") "C0603C104K5RACTU"))
      (libsource (lib "eagle-import") (part "C-EUC0603"))
    )
    (comp (ref "C37")
      (value "0.1uF")
      (footprint "eagle-import:C0603")
      (fields (field (name "PARTNO") "C0603C104K5RACTU"))
      (libsource (lib "eagle-import") (part "C-EUC0603"))
    )
    (comp (ref "C38")
      (value "0.1uF")
      (footprint "eagle-import:C0603")
      (fields (field (name "PARTNO") "C0603C104K5RACTU"))
      (libsource (lib "eagle-import") (part "C-EUC0603"))
    )
    (comp (ref "C39")
      (value "0.1uF")
      (footprint "eagle-import:C0603")
      (fields (field (name "PARTNO") "C0603C104K5RACTU"))
      (libsource (lib "eagle-import") (part "C-EUC0603"))
    )
    (comp (ref "C40")
      (value "0.1uF")
      (footprint "eagle-import:C0603")
      (fields (field (name "PARTNO") "C0603C104K5RACTU"))
      (libsource (lib "eagle-import") (part "C-EUC0603"))
    )
    (comp (ref "C41")
      (value "0.1uF")
      (footprint "eagle-import:C0603")
      (fields (field (name "PARTNO") "C0603C104K5RACTU"))
      (libsource (lib "eagle-import") (part "C-EUC0603"))
    )
    (comp (ref "C42")
      (value "0.1uF")
      (footprint "eagle-import:C0603")
      (fields (field (name "PARTNO") "C0603C104K5RACTU"))
      (libsource (lib "eagle-import") (part "C-EUC0603"))
    )
    (comp (ref "C43")
      (value "1000pF")
      (footprint "eagle-import:C0603")
      (fields (field (name "PARTNO") "C0603C102K5RACTU"))
      (libsource (lib "eagle-import") (part "C-EUC0603"))
    )
    (comp (ref "C44")
      (value "1000pF")
      (footprint "eagle-import:C0603")
      (fields (field (name "PARTNO") "C0603C102K5RACTU"))
      (libsource (lib "eagle-import") (part "C-EUC0603"))
    )
    (comp (ref "C45")
      (value "1000pF")
      (footprint "eagle-import:C0603")
      (fields (field (name "PARTNO") "C0603C102K5RACTU"))
      (libsource (lib "eagle-import") (part "C-EUC0603"))
    )
    (comp (ref "C46")
      (value "1000pF")
      (footprint "eagle-import:C0603")
      (fields (field (name "PARTNO") "C0603C102K5RACTU"))
      (libsource (lib "eagle-import") (part "C-EUC0603"))
    )
    (comp (ref "C47")
      (value "1000pF")
      (footprint "eagle-import:C0603")
      (fields (field (name "PARTNO") "C0603C102K5RACTU"))
      (libsource (lib "eagle-import") (part "C-EUC0603"))
    )
    (comp (ref "C48")
      (value "1000pF")
      (footprint "eagle-import:C0603")
      (fields (field (name "PARTNO") "C0603C102K5RACTU"))
      (libsource (lib "eagle-import") (part "C-EUC0603"))
    )
    (comp (ref "C49")
      (value "5600pF")
      (footprint "eagle-import:C0603")
      (fields (field (name "PARTNO") "C0603C562K5RACTU"))
      (libsource (lib "eagle-import") (part "C-EUC0603"))
    )
    (comp (ref "C50")
      (value "0.1uF")
      (footprint "eagle-import:C0603")
      (fields (field (name "PARTNO") "C0603C104K5RACTU"))
      (libsource (lib "eagle-import") (part "C-EUC0603"))
    )
    (comp (ref "C51")
      (value "5600pF")
      (footprint "eagle-import:C0603")
      (fields (field (name "PARTNO") "C0603C562K5RACTU"))
      (libsource (lib "eagle-import") (part "C-EUC0603"))
    )
    (comp (ref "C52")
      (value "0.1uF")
      (footprint "eagle-import:C0603")
      (fields (field (name "PARTNO") "C0603C104K5RACTU"))
      (libsource (lib "eagle-import") (part "C-EUC0603"))
    )
    (comp (ref "C53")
      (value "0.1uF")
      (footprint "eagle-import:C0603")
      (fields (field (name "PARTNO") "C0603C104K5RACTU"))
      (libsource (lib "eagle-import") (part "C-EUC0603"))
    )
    (comp (ref "C54")
      (value "0.1uF")
      (footprint "eagle-import:C0603")
      (fields (field (name "PARTNO") "C0603C104K5RACTU"))
      (libsource (lib "eagle-import") (part "C-EUC0603"))
    )
    (comp (ref "C55")
      (value "0.1uF")
      (footprint "eagle-import:C0603")
      (fields (field (name "PARTNO") "C0603C104K5RACTU"))
      (libsource (lib "eagle-import") (part "C-EUC0603"))
    )
    (comp (ref "DA1")
      (value "LM2904M")
      (footprint "eagle-import:SO08")
      (fields (field (name "PARTNO") "LM2904M"))
      (libsource (lib "eagle-import") (part "LM2904M"))
    )
    (comp (ref "DA2")
      (value "LM2904M")
      (footprint "eagle-import:SO08")
      (fields (field (name "PARTNO") "LM2904M"))
      (libsource (lib "eagle-import") (part "LM2904M"))
    )
    (comp (ref "DA3")
      (value "LM2904M")
      (footprint "eagle-import:SO08")
      (fields (field (name "PARTNO") "LM2904M"))
      (libsource (lib "eagle-import") (part "LM2904M"))
    )
    (comp (ref "DA4")
      (value "IL311AD")
      (footprint "eagle-import:SO08")
      (fields (field (name "PARTNO") "IL311AD"))
      (libsource (lib "eagle-import") (part "IL311AD"))
    )
    (comp (ref "DA5")
      (value "IL311AD")
      (footprint "eagle-import:SO08")
      (fields (field (name "PARTNO") "IL311AD"))
      (libsource (lib "eagle-import") (part "IL311AD"))
    )
    (comp (ref "DA6")
      (value "IL311AD")
      (footprint "eagle-import:SO08")
      (fields (field (name "PARTNO") "IL311AD"))
      (libsource (lib "eagle-import") (part "IL311AD"))
    )
    (comp (ref "DA7")
      (value "74HC123D")
      (footprint "eagle-import:SO16")
      (fields (field (name "PARTNO") "IN74HC123AD"))
      (libsource (lib "eagle-import") (part "74123DHC"))
    )
    (comp (ref "DA8")
      (value "74HC123D")
      (footprint "eagle-import:SO16")
      (fields (field (name "PARTNO") "IN74HC123AD"))
      (libsource (lib "eagle-import") (part "74123DHC"))
    )
    (comp (ref "DA9")
      (value "74HC123D")
      (footprint "eagle-import:SO16")
      (fields (field (name "PARTNO") "IN74HC123AD"))
      (libsource (lib "eagle-import") (part "74123DHC"))
    )
    (comp (ref "DA10")
      (value "SA555D")
      (footprint "eagle-import:SO08")
      (libsource (lib "eagle-import") (part "555DSA"))
    )
    (comp (ref "DD3")
      (value "74HC11D")
      (footprint "eagle-import:SO14")
      (fields (field (name "PARTNO") "IN74HC11AD"))
      (libsource (lib "eagle-import") (part "7411DHC"))
    )
    (comp (ref "R74")
      (value "1.2kOhm/5%")
      (footprint "eagle-import:R0603")
      (fields (field (name "PARTNO") "RC0603JR-071K2L"))
      (libsource (lib "eagle-import") (part "R-EU_R0603"))
    )
    (comp (ref "R75")
      (value "1.2kOhm/5%")
      (footprint "eagle-import:R0603")
      (fields (field (name "PARTNO") "RC0603JR-071K2L"))
      (libsource (lib "eagle-import") (part "R-EU_R0603"))
    )
    (comp (ref "R76")
      (value "1.2kOhm/5%")
      (footprint "eagle-import:R0603")
      (fields (field (name "PARTNO") "RC0603JR-071K2L"))
      (libsource (lib "eagle-import") (part "R-EU_R0603"))
    )
    (comp (ref "R77")
      (value "5.1kOhm/1%")
      (footprint "eagle-import:R0603")
      (fields (field (name "PARTNO") "RC0603FR-075K1L"))
      (libsource (lib "eagle-import") (part "R-EU_R0603"))
    )
    (comp (ref "R78")
      (value "5.1kOhm/1%")
      (footprint "eagle-import:R0603")
      (fields (field (name "PARTNO") "RC0603FR-075K1L"))
      (libsource (lib "eagle-import") (part "R-EU_R0603"))
    )
    (comp (ref "R79")
      (value "5.1kOhm/1%")
      (footprint "eagle-import:R0603")
      (fields (field (name "PARTNO") "RC0603FR-075K1L"))
      (libsource (lib "eagle-import") (part "R-EU_R0603"))
    )
    (comp (ref "R80")
      (value "5.1kOhm/1%")
      (footprint "eagle-import:R0603")
      (fields (field (name "PARTNO") "RC0603FR-075K1L"))
      (libsource (lib "eagle-import") (part "R-EU_R0603"))
    )
    (comp (ref "R81")
      (value "5.1kOhm/1%")
      (footprint "eagle-import:R0603")
      (fields (field (name "PARTNO") "RC0603FR-075K1L"))
      (libsource (lib "eagle-import") (part "R-EU_R0603"))
    )
    (comp (ref "R82")
      (value "5.1kOhm/1%")
      (footprint "eagle-import:R0603")
      (fields (field (name "PARTNO") "RC0603FR-075K1L"))
      (libsource (lib "eagle-import") (part "R-EU_R0603"))
    )
    (comp (ref "R83")
      (value "100kOhm/1%")
      (footprint "eagle-import:R0603")
      (fields (field (name "PARTNO") "RC0603FR-13100KL"))
      (libsource (lib "eagle-import") (part "R-EU_R0603"))
    )
    (comp (ref "R84")
      (value "100kOhm/1%")
      (footprint "eagle-import:R0603")
      (fields (field (name "PARTNO") "RC0603FR-13100KL"))
      (libsource (lib "eagle-import") (part "R-EU_R0603"))
    )
    (comp (ref "R85")
      (value "100kOhm/1%")
      (footprint "eagle-import:R0603")
      (fields (field (name "PARTNO") "RC0603FR-13100KL"))
      (libsource (lib "eagle-import") (part "R-EU_R0603"))
    )
    (comp (ref "R86")
      (value "2.2kOhm/5%")
      (footprint "eagle-import:R0603")
      (fields (field (name "PARTNO") "RC0603JR-072K2L"))
      (libsource (lib "eagle-import") (part "R-EU_R0603"))
    )
    (comp (ref "R87")
      (value "10kOhm/1%")
      (footprint "eagle-import:R0603")
      (fields (field (name "PARTNO") "RC0603FR-1010KL"))
      (libsource (lib "eagle-import") (part "R-EU_R0603"))
    )
    (comp (ref "R88")
      (value "10kOhm/1%")
      (footprint "eagle-import:R0603")
      (fields (field (name "PARTNO") "RC0603FR-1010KL"))
      (libsource (lib "eagle-import") (part "R-EU_R0603"))
    )
    (comp (ref "R89")
      (value "10kOhm/1%")
      (footprint "eagle-import:R0603")
      (fields (field (name "PARTNO") "RC0603FR-1010KL"))
      (libsource (lib "eagle-import") (part "R-EU_R0603"))
    )
    (comp (ref "R90")
      (value "10kOhm/1%")
      (footprint "eagle-import:R0603")
      (fields (field (name "PARTNO") "RC0603FR-1010KL"))
      (libsource (lib "eagle-import") (part "R-EU_R0603"))
    )
    (comp (ref "R91")
      (value "2.2kOhm/5%")
      (footprint "eagle-import:R0603")
      (fields (field (name "PARTNO") "RC0603JR-072K2L"))
      (libsource (lib "eagle-import") (part "R-EU_R0603"))
    )
    (comp (ref "R92")
      (value "10kOhm/1%")
      (footprint "eagle-import:R0603")
      (fields (field (name "PARTNO") "RC0603FR-1010KL"))
      (libsource (lib "eagle-import") (part "R-EU_R0603"))
    )
    (comp (ref "R93")
      (value "10kOhm/1%")
      (footprint "eagle-import:R0603")
      (fields (field (name "PARTNO") "RC0603FR-1010KL"))
      (libsource (lib "eagle-import") (part "R-EU_R0603"))
    )
    (comp (ref "R94")
      (value "10kOhm/1%")
      (footprint "eagle-import:R0603")
      (fields (field (name "PARTNO") "RC0603FR-1010KL"))
      (libsource (lib "eagle-import") (part "R-EU_R0603"))
    )
    (comp (ref "R95")
      (value "10kOhm/1%")
      (footprint "eagle-import:R0603")
      (fields (field (name "PARTNO") "RC0603FR-1010KL"))
      (libsource (lib "eagle-import") (part "R-EU_R0603"))
    )
    (comp (ref "R96")
      (value "2.2kOhm/5%")
      (footprint "eagle-import:R0603")
      (fields (field (name "PARTNO") "RC0603JR-072K2L"))
      (libsource (lib "eagle-import") (part "R-EU_R0603"))
    )
    (comp (ref "R97")
      (value "10kOhm/1%")
      (footprint "eagle-import:R0603")
      (fields (field (name "PARTNO") "RC0603FR-1010KL"))
      (libsource (lib "eagle-import") (part "R-EU_R0603"))
    )
    (comp (ref "R98")
      (value "10kOhm/1%")
      (footprint "eagle-import:R0603")
      (fields (field (name "PARTNO") "RC0603FR-1010KL"))
      (libsource (lib "eagle-import") (part "R-EU_R0603"))
    )
    (comp (ref "R99")
      (value "10kOhm/1%")
      (footprint "eagle-import:R0603")
      (fields (field (name "PARTNO") "RC0603FR-1010KL"))
      (libsource (lib "eagle-import") (part "R-EU_R0603"))
    )
    (comp (ref "R100")
      (value "10kOhm/1%")
      (footprint "eagle-import:R0603")
      (fields (field (name "PARTNO") "RC0603FR-1010KL"))
      (libsource (lib "eagle-import") (part "R-EU_R0603"))
    )
    (comp (ref "R101")
      (value "1.2kOhm/5%")
      (footprint "eagle-import:R0603")
      (fields (field (name "PARTNO") "RC0603JR-071K2L"))
      (libsource (lib "eagle-import") (part "R-EU_R0603"))
    )
    (comp (ref "R102")
      (value "1.2kOhm/5%")
      (footprint "eagle-import:R0603")
      (fields (field (name "PARTNO") "RC0603JR-071K2L"))
      (libsource (lib "eagle-import") (part "R-EU_R0603"))
    )
    (comp (ref "R103")
      (value "1.2kOhm/5%")
      (footprint "eagle-import:R0603")
      (fields (field (name "PARTNO") "RC0603JR-071K2L"))
      (libsource (lib "eagle-import") (part "R-EU_R0603"))
    )
    (comp (ref "R104")
      (value "1.2kOhm/5%")
      (footprint "eagle-import:R0603")
      (fields (field (name "PARTNO") "RC0603JR-071K2L"))
      (libsource (lib "eagle-import") (part "R-EU_R0603"))
    )
    (comp (ref "R105")
      (value "1.2kOhm/5%")
      (footprint "eagle-import:R0603")
      (fields (field (name "PARTNO") "RC0603JR-071K2L"))
      (libsource (lib "eagle-import") (part "R-EU_R0603"))
    )
    (comp (ref "R106")
      (value "1.2kOhm/5%")
      (footprint "eagle-import:R0603")
      (fields (field (name "PARTNO") "RC0603JR-071K2L"))
      (libsource (lib "eagle-import") (part "R-EU_R0603"))
    )
    (comp (ref "R107")
      (value "22kOhm/5%")
      (footprint "eagle-import:R0603")
      (fields (field (name "PARTNO") "RC0603JR-0722KL"))
      (libsource (lib "eagle-import") (part "R-EU_R0603"))
    )
    (comp (ref "R108")
      (value "22kOhm/5%")
      (footprint "eagle-import:R0603")
      (fields (field (name "PARTNO") "RC0603JR-0722KL"))
      (libsource (lib "eagle-import") (part "R-EU_R0603"))
    )
    (comp (ref "R109")
      (value "22kOhm/5%")
      (footprint "eagle-import:R0603")
      (fields (field (name "PARTNO") "RC0603JR-0722KL"))
      (libsource (lib "eagle-import") (part "R-EU_R0603"))
    )
    (comp (ref "R110")
      (value "22kOhm/5%")
      (footprint "eagle-import:R0603")
      (fields (field (name "PARTNO") "RC0603JR-0722KL"))
      (libsource (lib "eagle-import") (part "R-EU_R0603"))
    )
    (comp (ref "R111")
      (value "22kOhm/5%")
      (footprint "eagle-import:R0603")
      (fields (field (name "PARTNO") "RC0603JR-0722KL"))
      (libsource (lib "eagle-import") (part "R-EU_R0603"))
    )
    (comp (ref "R112")
      (value "22kOhm/5%")
      (footprint "eagle-import:R0603")
      (fields (field (name "PARTNO") "RC0603JR-0722KL"))
      (libsource (lib "eagle-import") (part "R-EU_R0603"))
    )
    (comp (ref "R113")
      (value "1.2kOhm/5%")
      (footprint "eagle-import:R0603")
      (fields (field (name "PARTNO") "RC0603JR-071K2L"))
      (libsource (lib "eagle-import") (part "R-EU_R0603"))
    )
    (comp (ref "R114")
      (value "1.2kOhm/5%")
      (footprint "eagle-import:R0603")
      (fields (field (name "PARTNO") "RC0603JR-071K2L"))
      (libsource (lib "eagle-import") (part "R-EU_R0603"))
    )
    (comp (ref "R115")
      (value "1.2kOhm/5%")
      (footprint "eagle-import:R0603")
      (fields (field (name "PARTNO") "RC0603JR-071K2L"))
      (libsource (lib "eagle-import") (part "R-EU_R0603"))
    )
    (comp (ref "R116")
      (value "1kOhm/20%")
      (footprint "eagle-import:RTRIMTSM53YJ")
      (fields (field (name "PARTNO") "TSM4YJ102KR05"))
      (libsource (lib "eagle-import") (part "R-TRIMMTSM4YJ"))
    )
    (comp (ref "R117")
      (value "51kOhm/5%")
      (footprint "eagle-import:R0603")
      (fields (field (name "PARTNO") "RC0603JR-0751KL"))
      (libsource (lib "eagle-import") (part "R-EU_R0603"))
    )
    (comp (ref "R118")
      (value "51kOhm/5%")
      (footprint "eagle-import:R0603")
      (fields (field (name "PARTNO") "RC0603JR-0751KL"))
      (libsource (lib "eagle-import") (part "R-EU_R0603"))
    )
    (comp (ref "R119")
      (value "51kOhm/5%")
      (footprint "eagle-import:R0603")
      (fields (field (name "PARTNO") "RC0603JR-0751KL"))
      (libsource (lib "eagle-import") (part "R-EU_R0603"))
    )
    (comp (ref "R120")
      (value "51kOhm/5%")
      (footprint "eagle-import:R0603")
      (fields (field (name "PARTNO") "RC0603JR-0751KL"))
      (libsource (lib "eagle-import") (part "R-EU_R0603"))
    )
    (comp (ref "R121")
      (value "51kOhm/5%")
      (footprint "eagle-import:R0603")
      (fields (field (name "PARTNO") "RC0603JR-0751KL"))
      (libsource (lib "eagle-import") (part "R-EU_R0603"))
    )
    (comp (ref "R122")
      (value "51kOhm/5%")
      (footprint "eagle-import:R0603")
      (fields (field (name "PARTNO") "RC0603JR-0751KL"))
      (libsource (lib "eagle-import") (part "R-EU_R0603"))
    )
    (comp (ref "R123")
      (value "51kOhm/5%")
      (footprint "eagle-import:R0603")
      (fields (field (name "PARTNO") "RC0603JR-0751KL"))
      (libsource (lib "eagle-import") (part "R-EU_R0603"))
    )
    (comp (ref "R124")
      (value "1kOhm/5%")
      (footprint "eagle-import:R2512")
      (fields (field (name "PARTNO") "RC2512JK-071KL"))
      (libsource (lib "eagle-import") (part "R-EU_R2512"))
    )
    (comp (ref "R125")
      (value "1kOhm/5%")
      (footprint "eagle-import:R2512")
      (fields (field (name "PARTNO") "RC2512JK-071KL"))
      (libsource (lib "eagle-import") (part "R-EU_R2512"))
    )
    (comp (ref "R126")
      (value "100kOhm/1%")
      (footprint "eagle-import:R0603")
      (fields (field (name "PARTNO") "RC0603FR-13100KL"))
      (libsource (lib "eagle-import") (part "R-EU_R0603"))
    )
    (comp (ref "R127")
      (value "100kOhm/1%")
      (footprint "eagle-import:R0603")
      (fields (field (name "PARTNO") "RC0603FR-13100KL"))
      (libsource (lib "eagle-import") (part "R-EU_R0603"))
    )
    (comp (ref "R128")
      (value "36kOhm/5%")
      (footprint "eagle-import:R0603")
      (fields (field (name "PARTNO") "ERJ3GEYJ363V"))
      (libsource (lib "eagle-import") (part "R-EU_R0603"))
    )
    (comp (ref "R129")
      (value "36kOhm/5%")
      (footprint "eagle-import:R0603")
      (fields (field (name "PARTNO") "ERJ3GEYJ363V"))
      (libsource (lib "eagle-import") (part "R-EU_R0603"))
    )
    (comp (ref "R130")
      (value "100kOhm/1%")
      (footprint "eagle-import:R0603")
      (fields (field (name "PARTNO") "RC0603FR-13100KL"))
      (libsource (lib "eagle-import") (part "R-EU_R0603"))
    )
    (comp (ref "VD36")
      (value "3.3V")
      (footprint "eagle-import:SOD80")
      (fields (field (name "PARTNO") "BZV55-C3V3"))
      (libsource (lib "eagle-import") (part "DIODE-ZENER-"))
    )
    (comp (ref "VD37")
      (value "3.3V")
      (footprint "eagle-import:SOD80")
      (fields (field (name "PARTNO") "BZV55-C3V3"))
      (libsource (lib "eagle-import") (part "DIODE-ZENER-"))
    )
    (comp (ref "VD38")
      (value "3.3V")
      (footprint "eagle-import:SOD80")
      (fields (field (name "PARTNO") "BZV55-C3V3"))
      (libsource (lib "eagle-import") (part "DIODE-ZENER-"))
    )
    (comp (ref "VD39")
      (value "3.3V")
      (footprint "eagle-import:SOD80")
      (fields (field (name "PARTNO") "BZV55-C3V3"))
      (libsource (lib "eagle-import") (part "DIODE-ZENER-"))
    )
    (comp (ref "VD40")
      (value "3.3V")
      (footprint "eagle-import:SOD80")
      (fields (field (name "PARTNO") "BZV55-C3V3"))
      (libsource (lib "eagle-import") (part "DIODE-ZENER-"))
    )
    (comp (ref "VD41")
      (value "3.3V")
      (footprint "eagle-import:SOD80")
      (fields (field (name "PARTNO") "BZV55-C3V3"))
      (libsource (lib "eagle-import") (part "DIODE-ZENER-"))
    )
    (comp (ref "VD42")
      (value "3.3V")
      (footprint "eagle-import:SOD80")
      (fields (field (name "PARTNO") "BZV55-C3V3"))
      (libsource (lib "eagle-import") (part "DIODE-ZENER-"))
    )
    (comp (ref "VD43")
      (value "3.3V")
      (footprint "eagle-import:SOD80")
      (fields (field (name "PARTNO") "BZV55-C3V3"))
      (libsource (lib "eagle-import") (part "DIODE-ZENER-"))
    )
    (comp (ref "VD44")
      (value "3.3V")
      (footprint "eagle-import:SOD80")
      (fields (field (name "PARTNO") "BZV55-C3V3"))
      (libsource (lib "eagle-import") (part "DIODE-ZENER-"))
    )
    (comp (ref "VD45")
      (value "3.3V")
      (footprint "eagle-import:SOD80")
      (fields (field (name "PARTNO") "BZV55-C3V3"))
      (libsource (lib "eagle-import") (part "DIODE-ZENER-"))
    )
    (comp (ref "VD46")
      (value "3.3V")
      (footprint "eagle-import:SOD80")
      (fields (field (name "PARTNO") "BZV55-C3V3"))
      (libsource (lib "eagle-import") (part "DIODE-ZENER-"))
    )
    (comp (ref "VD47")
      (value "3.3V")
      (footprint "eagle-import:SOD80")
      (fields (field (name "PARTNO") "BZV55-C3V3"))
      (libsource (lib "eagle-import") (part "DIODE-ZENER-"))
    )
    (comp (ref "VD48")
      (value "SMBJ24CA")
      (footprint "eagle-import:SMB-BIDIR")
      (libsource (lib "eagle-import") (part "DIODE-TVS-BIDIR-SMB"))
    )
    (comp (ref "VD49")
      (value "SMBJ24CA")
      (footprint "eagle-import:SMB-BIDIR")
      (libsource (lib "eagle-import") (part "DIODE-TVS-BIDIR-SMB"))
    )
    (comp (ref "VD50")
      (value "3.3V")
      (footprint "eagle-import:SOD80")
      (fields (field (name "PARTNO") "BZV55-C3V3"))
      (libsource (lib "eagle-import") (part "DIODE-ZENER-"))
    )
    (comp (ref "VD51")
      (value "3.3V")
      (footprint "eagle-import:SOD80")
      (fields (field (name "PARTNO") "BZV55-C3V3"))
      (libsource (lib "eagle-import") (part "DIODE-ZENER-"))
    )
    (comp (ref "VD52")
      (value "3.3V")
      (footprint "eagle-import:SOD80")
      (fields (field (name "PARTNO") "BZV55-C3V3"))
      (libsource (lib "eagle-import") (part "DIODE-ZENER-"))
    )
    (comp (ref "XP5")
      (value "MOLEX-90130-08")
      (footprint "eagle-import:MOLEX-90130-08")
      (fields (field (name "LABEL") "FREQUENCY") (field (name "PARTNO") "90130-1208"))
      (libsource (lib "eagle-import") (part "MOLEX-90130-08"))
    )
    (comp (ref "Z38")
      (value "NFE31PT")
      (footprint "eagle-import:NFE31")
      (fields (field (name "PARTNO") "NFE31PT152Z1E9"))
      (libsource (lib "eagle-import") (part "NFE31PT"))
    )
    (comp (ref "Z39")
      (value "NFE31PT")
      (footprint "eagle-import:NFE31")
      (fields (field (name "PARTNO") "NFE31PT152Z1E9"))
      (libsource (lib "eagle-import") (part "NFE31PT"))
    )
    (comp (ref "Z40")
      (value "NFE31PT")
      (footprint "eagle-import:NFE31")
      (fields (field (name "PARTNO") "NFE31PT152Z1E9"))
      (libsource (lib "eagle-import") (part "NFE31PT"))
    )
    (comp (ref "C69")
      (value "0.1uF")
      (footprint "eagle-import:C0603")
      (fields (field (name "PARTNO") "C0603C104K5RACTU"))
      (libsource (lib "eagle-import") (part "C-EUC0603"))
    )
    (comp (ref "C70")
      (value "0.1uF")
      (footprint "eagle-import:C0603")
      (fields (field (name "PARTNO") "C0603C104K5RACTU"))
      (libsource (lib "eagle-import") (part "C-EUC0603"))
    )
    (comp (ref "C71")
      (value "0.1uF")
      (footprint "eagle-import:C0603")
      (fields (field (name "PARTNO") "C0603C104K5RACTU"))
      (libsource (lib "eagle-import") (part "C-EUC0603"))
    )
    (comp (ref "C72")
      (value "0.1uF")
      (footprint "eagle-import:C0603")
      (fields (field (name "PARTNO") "C0603C104K5RACTU"))
      (libsource (lib "eagle-import") (part "C-EUC0603"))
    )
    (comp (ref "C73")
      (value "0.1uF")
      (footprint "eagle-import:C0603")
      (fields (field (name "PARTNO") "C0603C104K5RACTU"))
      (libsource (lib "eagle-import") (part "C-EUC0603"))
    )
    (comp (ref "C74")
      (value "0.1uF")
      (footprint "eagle-import:C0603")
      (fields (field (name "PARTNO") "C0603C104K5RACTU"))
      (libsource (lib "eagle-import") (part "C-EUC0603"))
    )
    (comp (ref "C75")
      (value "0.1uF")
      (footprint "eagle-import:C0603")
      (fields (field (name "PARTNO") "C0603C104K5RACTU"))
      (libsource (lib "eagle-import") (part "C-EUC0603"))
    )
    (comp (ref "C76")
      (value "0.1uF")
      (footprint "eagle-import:C0603")
      (fields (field (name "PARTNO") "C0603C104K5RACTU"))
      (libsource (lib "eagle-import") (part "C-EUC0603"))
    )
    (comp (ref "C77")
      (value "0.1uF")
      (footprint "eagle-import:C0603")
      (fields (field (name "PARTNO") "C0603C104K5RACTU"))
      (libsource (lib "eagle-import") (part "C-EUC0603"))
    )
    (comp (ref "C78")
      (value "0.1uF")
      (footprint "eagle-import:C0603")
      (fields (field (name "PARTNO") "C0603C104K5RACTU"))
      (libsource (lib "eagle-import") (part "C-EUC0603"))
    )
    (comp (ref "C79")
      (value "0.1uF")
      (footprint "eagle-import:C0603")
      (fields (field (name "PARTNO") "C0603C104K5RACTU"))
      (libsource (lib "eagle-import") (part "C-EUC0603"))
    )
    (comp (ref "C80")
      (value "0.1uF")
      (footprint "eagle-import:C0603")
      (fields (field (name "PARTNO") "C0603C104K5RACTU"))
      (libsource (lib "eagle-import") (part "C-EUC0603"))
    )
    (comp (ref "C81")
      (value "0.1uF")
      (footprint "eagle-import:C0603")
      (fields (field (name "PARTNO") "C0603C104K5RACTU"))
      (libsource (lib "eagle-import") (part "C-EUC0603"))
    )
    (comp (ref "C82")
      (value "0.1uF")
      (footprint "eagle-import:C0603")
      (fields (field (name "PARTNO") "C0603C104K5RACTU"))
      (libsource (lib "eagle-import") (part "C-EUC0603"))
    )
    (comp (ref "C83")
      (value "0.1uF")
      (footprint "eagle-import:C0603")
      (fields (field (name "PARTNO") "C0603C104K5RACTU"))
      (libsource (lib "eagle-import") (part "C-EUC0603"))
    )
    (comp (ref "C84")
      (value "0.1uF")
      (footprint "eagle-import:C0603")
      (fields (field (name "PARTNO") "C0603C104K5RACTU"))
      (libsource (lib "eagle-import") (part "C-EUC0603"))
    )
    (comp (ref "C85")
      (value "0.1uF")
      (footprint "eagle-import:C0603")
      (fields (field (name "PARTNO") "C0603C104K5RACTU"))
      (libsource (lib "eagle-import") (part "C-EUC0603"))
    )
    (comp (ref "C86")
      (value "0.1uF")
      (footprint "eagle-import:C0603")
      (fields (field (name "PARTNO") "C0603C104K5RACTU"))
      (libsource (lib "eagle-import") (part "C-EUC0603"))
    )
    (comp (ref "D1")
      (value "TCMT4100")
      (footprint "eagle-import:SO16")
      (fields (field (name "PARTNO") "TCMT4100"))
      (libsource (lib "eagle-import") (part "TCMT4100"))
    )
    (comp (ref "D2")
      (value "TCMT4100")
      (footprint "eagle-import:SO16")
      (fields (field (name "PARTNO") "TCMT4100"))
      (libsource (lib "eagle-import") (part "TCMT4100"))
    )
    (comp (ref "D3")
      (value "TCMT4100")
      (footprint "eagle-import:SO16")
      (fields (field (name "PARTNO") "TCMT4100"))
      (libsource (lib "eagle-import") (part "TCMT4100"))
    )
    (comp (ref "D4")
      (value "TCMT4100")
      (footprint "eagle-import:SO16")
      (fields (field (name "PARTNO") "TCMT4100"))
      (libsource (lib "eagle-import") (part "TCMT4100"))
    )
    (comp (ref "D5")
      (value "AUIPS7111S")
      (footprint "eagle-import:TO252-5-11")
      (libsource (lib "eagle-import") (part "AUIPS7111S"))
    )
    (comp (ref "DD4")
      (value "74HC165D")
      (footprint "eagle-import:SO16")
      (fields (field (name "PARTNO") "IN74HC165AD"))
      (libsource (lib "eagle-import") (part "74165DHC"))
    )
    (comp (ref "DD5")
      (value "74HC165D")
      (footprint "eagle-import:SO16")
      (fields (field (name "PARTNO") "IN74HC165AD"))
      (libsource (lib "eagle-import") (part "74165DHC"))
    )
    (comp (ref "R138")
      (value "4.7kOhm/5%")
      (footprint "eagle-import:R1206")
      (fields (field (name "PARTNO") "RC1206JR-074K7L"))
      (libsource (lib "eagle-import") (part "R-EU_R1206"))
    )
    (comp (ref "R139")
      (value "4.7kOhm/5%")
      (footprint "eagle-import:R1206")
      (fields (field (name "PARTNO") "RC1206JR-074K7L"))
      (libsource (lib "eagle-import") (part "R-EU_R1206"))
    )
    (comp (ref "R140")
      (value "4.7kOhm/5%")
      (footprint "eagle-import:R1206")
      (fields (field (name "PARTNO") "RC1206JR-074K7L"))
      (libsource (lib "eagle-import") (part "R-EU_R1206"))
    )
    (comp (ref "R141")
      (value "4.7kOhm/5%")
      (footprint "eagle-import:R1206")
      (fields (field (name "PARTNO") "RC1206JR-074K7L"))
      (libsource (lib "eagle-import") (part "R-EU_R1206"))
    )
    (comp (ref "R142")
      (value "4.7kOhm/5%")
      (footprint "eagle-import:R1206")
      (fields (field (name "PARTNO") "RC1206JR-074K7L"))
      (libsource (lib "eagle-import") (part "R-EU_R1206"))
    )
    (comp (ref "R143")
      (value "4.7kOhm/5%")
      (footprint "eagle-import:R1206")
      (fields (field (name "PARTNO") "RC1206JR-074K7L"))
      (libsource (lib "eagle-import") (part "R-EU_R1206"))
    )
    (comp (ref "R144")
      (value "4.7kOhm/5%")
      (footprint "eagle-import:R1206")
      (fields (field (name "PARTNO") "RC1206JR-074K7L"))
      (libsource (lib "eagle-import") (part "R-EU_R1206"))
    )
    (comp (ref "R145")
      (value "4.7kOhm/5%")
      (footprint "eagle-import:R1206")
      (fields (field (name "PARTNO") "RC1206JR-074K7L"))
      (libsource (lib "eagle-import") (part "R-EU_R1206"))
    )
    (comp (ref "R146")
      (value "4.7kOhm/5%")
      (footprint "eagle-import:R1206")
      (fields (field (name "PARTNO") "RC1206JR-074K7L"))
      (libsource (lib "eagle-import") (part "R-EU_R1206"))
    )
    (comp (ref "R147")
      (value "4.7kOhm/5%")
      (footprint "eagle-import:R1206")
      (fields (field (name "PARTNO") "RC1206JR-074K7L"))
      (libsource (lib "eagle-import") (part "R-EU_R1206"))
    )
    (comp (ref "R148")
      (value "4.7kOhm/5%")
      (footprint "eagle-import:R1206")
      (fields (field (name "PARTNO") "RC1206JR-074K7L"))
      (libsource (lib "eagle-import") (part "R-EU_R1206"))
    )
    (comp (ref "R149")
      (value "4.7kOhm/5%")
      (footprint "eagle-import:R1206")
      (fields (field (name "PARTNO") "RC1206JR-074K7L"))
      (libsource (lib "eagle-import") (part "R-EU_R1206"))
    )
    (comp (ref "R150")
      (value "4.7kOhm/5%")
      (footprint "eagle-import:R1206")
      (fields (field (name "PARTNO") "RC1206JR-074K7L"))
      (libsource (lib "eagle-import") (part "R-EU_R1206"))
    )
    (comp (ref "R151")
      (value "4.7kOhm/5%")
      (footprint "eagle-import:R1206")
      (fields (field (name "PARTNO") "RC1206JR-074K7L"))
      (libsource (lib "eagle-import") (part "R-EU_R1206"))
    )
    (comp (ref "R152")
      (value "4.7kOhm/5%")
      (footprint "eagle-import:R1206")
      (fields (field (name "PARTNO") "RC1206JR-074K7L"))
      (libsource (lib "eagle-import") (part "R-EU_R1206"))
    )
    (comp (ref "R153")
      (value "4.7kOhm/5%")
      (footprint "eagle-import:R1206")
      (fields (field (name "PARTNO") "RC1206JR-074K7L"))
      (libsource (lib "eagle-import") (part "R-EU_R1206"))
    )
    (comp (ref "R154")
      (value "1kOhm/5%")
      (footprint "eagle-import:R2512")
      (fields (field (name "PARTNO") "RC2512JK-071KL"))
      (libsource (lib "eagle-import") (part "R-EU_R2512"))
    )
    (comp (ref "R155")
      (value "1kOhm/5%")
      (footprint "eagle-import:R2512")
      (fields (field (name "PARTNO") "RC2512JK-071KL"))
      (libsource (lib "eagle-import") (part "R-EU_R2512"))
    )
    (comp (ref "R156")
      (value "1kOhm/5%")
      (footprint "eagle-import:R2512")
      (fields (field (name "PARTNO") "RC2512JK-071KL"))
      (libsource (lib "eagle-import") (part "R-EU_R2512"))
    )
    (comp (ref "R157")
      (value "1kOhm/5%")
      (footprint "eagle-import:R2512")
      (fields (field (name "PARTNO") "RC2512JK-071KL"))
      (libsource (lib "eagle-import") (part "R-EU_R2512"))
    )
    (comp (ref "R158")
      (value "1kOhm/5%")
      (footprint "eagle-import:R2512")
      (fields (field (name "PARTNO") "RC2512JK-071KL"))
      (libsource (lib "eagle-import") (part "R-EU_R2512"))
    )
    (comp (ref "R159")
      (value "1kOhm/5%")
      (footprint "eagle-import:R2512")
      (fields (field (name "PARTNO") "RC2512JK-071KL"))
      (libsource (lib "eagle-import") (part "R-EU_R2512"))
    )
    (comp (ref "R160")
      (value "1kOhm/5%")
      (footprint "eagle-import:R2512")
      (fields (field (name "PARTNO") "RC2512JK-071KL"))
      (libsource (lib "eagle-import") (part "R-EU_R2512"))
    )
    (comp (ref "R161")
      (value "1kOhm/5%")
      (footprint "eagle-import:R2512")
      (fields (field (name "PARTNO") "RC2512JK-071KL"))
      (libsource (lib "eagle-import") (part "R-EU_R2512"))
    )
    (comp (ref "R162")
      (value "1kOhm/5%")
      (footprint "eagle-import:R2512")
      (fields (field (name "PARTNO") "RC2512JK-071KL"))
      (libsource (lib "eagle-import") (part "R-EU_R2512"))
    )
    (comp (ref "R163")
      (value "1kOhm/5%")
      (footprint "eagle-import:R2512")
      (fields (field (name "PARTNO") "RC2512JK-071KL"))
      (libsource (lib "eagle-import") (part "R-EU_R2512"))
    )
    (comp (ref "R164")
      (value "1kOhm/5%")
      (footprint "eagle-import:R2512")
      (fields (field (name "PARTNO") "RC2512JK-071KL"))
      (libsource (lib "eagle-import") (part "R-EU_R2512"))
    )
    (comp (ref "R165")
      (value "1kOhm/5%")
      (footprint "eagle-import:R2512")
      (fields (field (name "PARTNO") "RC2512JK-071KL"))
      (libsource (lib "eagle-import") (part "R-EU_R2512"))
    )
    (comp (ref "R166")
      (value "1kOhm/5%")
      (footprint "eagle-import:R2512")
      (fields (field (name "PARTNO") "RC2512JK-071KL"))
      (libsource (lib "eagle-import") (part "R-EU_R2512"))
    )
    (comp (ref "R167")
      (value "1kOhm/5%")
      (footprint "eagle-import:R2512")
      (fields (field (name "PARTNO") "RC2512JK-071KL"))
      (libsource (lib "eagle-import") (part "R-EU_R2512"))
    )
    (comp (ref "R168")
      (value "1kOhm/5%")
      (footprint "eagle-import:R2512")
      (fields (field (name "PARTNO") "RC2512JK-071KL"))
      (libsource (lib "eagle-import") (part "R-EU_R2512"))
    )
    (comp (ref "R169")
      (value "1kOhm/5%")
      (footprint "eagle-import:R2512")
      (fields (field (name "PARTNO") "RC2512JK-071KL"))
      (libsource (lib "eagle-import") (part "R-EU_R2512"))
    )
    (comp (ref "R170")
      (value "10kOhm/1%")
      (footprint "eagle-import:R0603")
      (fields (field (name "PARTNO") "RC0603FR-1010KL"))
      (libsource (lib "eagle-import") (part "R-EU_R0603"))
    )
    (comp (ref "R171")
      (value "10kOhm/1%")
      (footprint "eagle-import:R0603")
      (fields (field (name "PARTNO") "RC0603FR-1010KL"))
      (libsource (lib "eagle-import") (part "R-EU_R0603"))
    )
    (comp (ref "R172")
      (value "10kOhm/1%")
      (footprint "eagle-import:R0603")
      (fields (field (name "PARTNO") "RC0603FR-1010KL"))
      (libsource (lib "eagle-import") (part "R-EU_R0603"))
    )
    (comp (ref "R173")
      (value "10kOhm/1%")
      (footprint "eagle-import:R0603")
      (fields (field (name "PARTNO") "RC0603FR-1010KL"))
      (libsource (lib "eagle-import") (part "R-EU_R0603"))
    )
    (comp (ref "R174")
      (value "10kOhm/1%")
      (footprint "eagle-import:R0603")
      (fields (field (name "PARTNO") "RC0603FR-1010KL"))
      (libsource (lib "eagle-import") (part "R-EU_R0603"))
    )
    (comp (ref "R175")
      (value "10kOhm/1%")
      (footprint "eagle-import:R0603")
      (fields (field (name "PARTNO") "RC0603FR-1010KL"))
      (libsource (lib "eagle-import") (part "R-EU_R0603"))
    )
    (comp (ref "R176")
      (value "10kOhm/1%")
      (footprint "eagle-import:R0603")
      (fields (field (name "PARTNO") "RC0603FR-1010KL"))
      (libsource (lib "eagle-import") (part "R-EU_R0603"))
    )
    (comp (ref "R177")
      (value "10kOhm/1%")
      (footprint "eagle-import:R0603")
      (fields (field (name "PARTNO") "RC0603FR-1010KL"))
      (libsource (lib "eagle-import") (part "R-EU_R0603"))
    )
    (comp (ref "R178")
      (value "10kOhm/1%")
      (footprint "eagle-import:R0603")
      (fields (field (name "PARTNO") "RC0603FR-1010KL"))
      (libsource (lib "eagle-import") (part "R-EU_R0603"))
    )
    (comp (ref "R179")
      (value "10kOhm/1%")
      (footprint "eagle-import:R0603")
      (fields (field (name "PARTNO") "RC0603FR-1010KL"))
      (libsource (lib "eagle-import") (part "R-EU_R0603"))
    )
    (comp (ref "R180")
      (value "10kOhm/1%")
      (footprint "eagle-import:R0603")
      (fields (field (name "PARTNO") "RC0603FR-1010KL"))
      (libsource (lib "eagle-import") (part "R-EU_R0603"))
    )
    (comp (ref "R181")
      (value "10kOhm/1%")
      (footprint "eagle-import:R0603")
      (fields (field (name "PARTNO") "RC0603FR-1010KL"))
      (libsource (lib "eagle-import") (part "R-EU_R0603"))
    )
    (comp (ref "R182")
      (value "10kOhm/1%")
      (footprint "eagle-import:R0603")
      (fields (field (name "PARTNO") "RC0603FR-1010KL"))
      (libsource (lib "eagle-import") (part "R-EU_R0603"))
    )
    (comp (ref "R183")
      (value "10kOhm/1%")
      (footprint "eagle-import:R0603")
      (fields (field (name "PARTNO") "RC0603FR-1010KL"))
      (libsource (lib "eagle-import") (part "R-EU_R0603"))
    )
    (comp (ref "R184")
      (value "10kOhm/1%")
      (footprint "eagle-import:R0603")
      (fields (field (name "PARTNO") "RC0603FR-1010KL"))
      (libsource (lib "eagle-import") (part "R-EU_R0603"))
    )
    (comp (ref "R185")
      (value "10kOhm/1%")
      (footprint "eagle-import:R0603")
      (fields (field (name "PARTNO") "RC0603FR-1010KL"))
      (libsource (lib "eagle-import") (part "R-EU_R0603"))
    )
    (comp (ref "R186")
      (value "1kOhm/5%")
      (footprint "eagle-import:R0805")
      (fields (field (name "PARTNO") "ERJ6GEYJ102V"))
      (libsource (lib "eagle-import") (part "R-EU_R0805"))
    )
    (comp (ref "R187")
      (value "1kOhm/5%")
      (footprint "eagle-import:R0805")
      (fields (field (name "PARTNO") "ERJ6GEYJ102V"))
      (libsource (lib "eagle-import") (part "R-EU_R0805"))
    )
    (comp (ref "R188")
      (value "10kOhm/1%")
      (footprint "eagle-import:R0603")
      (fields (field (name "PARTNO") "RC0603FR-1010KL"))
      (libsource (lib "eagle-import") (part "R-EU_R0603"))
    )
    (comp (ref "VD66")
      (value "SM6T200A")
      (footprint "eagle-import:SMB")
      (libsource (lib "eagle-import") (part "DIODE-TVS-UNIDIR-SMB"))
    )
    (comp (ref "VD67")
      (value "SM6T200A")
      (footprint "eagle-import:SMB")
      (libsource (lib "eagle-import") (part "DIODE-TVS-UNIDIR-SMB"))
    )
    (comp (ref "VD68")
      (value "SM6T200A")
      (footprint "eagle-import:SMB")
      (libsource (lib "eagle-import") (part "DIODE-TVS-UNIDIR-SMB"))
    )
    (comp (ref "VD69")
      (value "SM6T200A")
      (footprint "eagle-import:SMB")
      (libsource (lib "eagle-import") (part "DIODE-TVS-UNIDIR-SMB"))
    )
    (comp (ref "VD70")
      (value "SM6T200A")
      (footprint "eagle-import:SMB")
      (libsource (lib "eagle-import") (part "DIODE-TVS-UNIDIR-SMB"))
    )
    (comp (ref "VD71")
      (value "SM6T200A")
      (footprint "eagle-import:SMB")
      (libsource (lib "eagle-import") (part "DIODE-TVS-UNIDIR-SMB"))
    )
    (comp (ref "VD72")
      (value "SM6T200A")
      (footprint "eagle-import:SMB")
      (libsource (lib "eagle-import") (part "DIODE-TVS-UNIDIR-SMB"))
    )
    (comp (ref "VD73")
      (value "SM6T200A")
      (footprint "eagle-import:SMB")
      (libsource (lib "eagle-import") (part "DIODE-TVS-UNIDIR-SMB"))
    )
    (comp (ref "VD74")
      (value "SM6T200A")
      (footprint "eagle-import:SMB")
      (libsource (lib "eagle-import") (part "DIODE-TVS-UNIDIR-SMB"))
    )
    (comp (ref "VD75")
      (value "SM6T200A")
      (footprint "eagle-import:SMB")
      (libsource (lib "eagle-import") (part "DIODE-TVS-UNIDIR-SMB"))
    )
    (comp (ref "VD76")
      (value "SM6T200A")
      (footprint "eagle-import:SMB")
      (libsource (lib "eagle-import") (part "DIODE-TVS-UNIDIR-SMB"))
    )
    (comp (ref "VD77")
      (value "SM6T200A")
      (footprint "eagle-import:SMB")
      (libsource (lib "eagle-import") (part "DIODE-TVS-UNIDIR-SMB"))
    )
    (comp (ref "VD78")
      (value "SM6T200A")
      (footprint "eagle-import:SMB")
      (libsource (lib "eagle-import") (part "DIODE-TVS-UNIDIR-SMB"))
    )
    (comp (ref "VD79")
      (value "SM6T200A")
      (footprint "eagle-import:SMB")
      (libsource (lib "eagle-import") (part "DIODE-TVS-UNIDIR-SMB"))
    )
    (comp (ref "VD80")
      (value "SM6T200A")
      (footprint "eagle-import:SMB")
      (libsource (lib "eagle-import") (part "DIODE-TVS-UNIDIR-SMB"))
    )
    (comp (ref "VD81")
      (value "SM6T200A")
      (footprint "eagle-import:SMB")
      (libsource (lib "eagle-import") (part "DIODE-TVS-UNIDIR-SMB"))
    )
    (comp (ref "VD82")
      (value "400V")
      (footprint "eagle-import:SMA")
      (fields (field (name "PARTNO") "S1G-E3/61T"))
      (libsource (lib "eagle-import") (part "DIODE-STANDARD-SMA"))
    )
    (comp (ref "VD83")
      (value "400V")
      (footprint "eagle-import:SMA")
      (fields (field (name "PARTNO") "S1G-E3/61T"))
      (libsource (lib "eagle-import") (part "DIODE-STANDARD-SMA"))
    )
    (comp (ref "VD84")
      (value "400V")
      (footprint "eagle-import:SMA")
      (fields (field (name "PARTNO") "S1G-E3/61T"))
      (libsource (lib "eagle-import") (part "DIODE-STANDARD-SMA"))
    )
    (comp (ref "VD85")
      (value "400V")
      (footprint "eagle-import:SMA")
      (fields (field (name "PARTNO") "S1G-E3/61T"))
      (libsource (lib "eagle-import") (part "DIODE-STANDARD-SMA"))
    )
    (comp (ref "VD86")
      (value "400V")
      (footprint "eagle-import:SMA")
      (fields (field (name "PARTNO") "S1G-E3/61T"))
      (libsource (lib "eagle-import") (part "DIODE-STANDARD-SMA"))
    )
    (comp (ref "VD87")
      (value "400V")
      (footprint "eagle-import:SMA")
      (fields (field (name "PARTNO") "S1G-E3/61T"))
      (libsource (lib "eagle-import") (part "DIODE-STANDARD-SMA"))
    )
    (comp (ref "VD88")
      (value "400V")
      (footprint "eagle-import:SMA")
      (fields (field (name "PARTNO") "S1G-E3/61T"))
      (libsource (lib "eagle-import") (part "DIODE-STANDARD-SMA"))
    )
    (comp (ref "VD89")
      (value "400V")
      (footprint "eagle-import:SMA")
      (fields (field (name "PARTNO") "S1G-E3/61T"))
      (libsource (lib "eagle-import") (part "DIODE-STANDARD-SMA"))
    )
    (comp (ref "VD90")
      (value "400V")
      (footprint "eagle-import:SMA")
      (fields (field (name "PARTNO") "S1G-E3/61T"))
      (libsource (lib "eagle-import") (part "DIODE-STANDARD-SMA"))
    )
    (comp (ref "VD91")
      (value "400V")
      (footprint "eagle-import:SMA")
      (fields (field (name "PARTNO") "S1G-E3/61T"))
      (libsource (lib "eagle-import") (part "DIODE-STANDARD-SMA"))
    )
    (comp (ref "VD92")
      (value "400V")
      (footprint "eagle-import:SMA")
      (fields (field (name "PARTNO") "S1G-E3/61T"))
      (libsource (lib "eagle-import") (part "DIODE-STANDARD-SMA"))
    )
    (comp (ref "VD93")
      (value "400V")
      (footprint "eagle-import:SMA")
      (fields (field (name "PARTNO") "S1G-E3/61T"))
      (libsource (lib "eagle-import") (part "DIODE-STANDARD-SMA"))
    )
    (comp (ref "VD94")
      (value "400V")
      (footprint "eagle-import:SMA")
      (fields (field (name "PARTNO") "S1G-E3/61T"))
      (libsource (lib "eagle-import") (part "DIODE-STANDARD-SMA"))
    )
    (comp (ref "VD95")
      (value "400V")
      (footprint "eagle-import:SMA")
      (fields (field (name "PARTNO") "S1G-E3/61T"))
      (libsource (lib "eagle-import") (part "DIODE-STANDARD-SMA"))
    )
    (comp (ref "VD96")
      (value "400V")
      (footprint "eagle-import:SMA")
      (fields (field (name "PARTNO") "S1G-E3/61T"))
      (libsource (lib "eagle-import") (part "DIODE-STANDARD-SMA"))
    )
    (comp (ref "VD97")
      (value "400V")
      (footprint "eagle-import:SMA")
      (fields (field (name "PARTNO") "S1G-E3/61T"))
      (libsource (lib "eagle-import") (part "DIODE-STANDARD-SMA"))
    )
    (comp (ref "VD98")
      (value "100V")
      (footprint "eagle-import:SOD323")
      (fields (field (name "PARTNO") "1N4148WS-V-GS18"))
      (libsource (lib "eagle-import") (part "DIODE-STANDARD-SOD323"))
    )
    (comp (ref "VD99")
      (value "100V")
      (footprint "eagle-import:SOD323")
      (fields (field (name "PARTNO") "1N4148WS-V-GS18"))
      (libsource (lib "eagle-import") (part "DIODE-STANDARD-SOD323"))
    )
    (comp (ref "VT2")
      (value "BC817-16SMD")
      (footprint "eagle-import:SOT23-BEC")
      (fields (field (name "PARTNO") "BC817"))
      (libsource (lib "eagle-import") (part "BC817SMD-16"))
    )
    (comp (ref "XP7")
      (value "MOLEX-90130-16")
      (footprint "eagle-import:MOLEX-90130-16")
      (fields (field (name "LABEL") "DISCRETE(1..16)") (field (name "PARTNO") "90130-1216"))
      (libsource (lib "eagle-import") (part "MOLEX-90130-16"))
    )
    (comp (ref "C123")
      (value "0.1uF")
      (footprint "eagle-import:C0603")
      (fields (field (name "PARTNO") "C0603C104K5RACTU"))
      (libsource (lib "eagle-import") (part "C-EUC0603"))
    )
    (comp (ref "C124")
      (value "0.1uF")
      (footprint "eagle-import:C0603")
      (fields (field (name "PARTNO") "C0603C104K5RACTU"))
      (libsource (lib "eagle-import") (part "C-EUC0603"))
    )
    (comp (ref "C125")
      (value "0.1uF")
      (footprint "eagle-import:C0603")
      (fields (field (name "PARTNO") "C0603C104K5RACTU"))
      (libsource (lib "eagle-import") (part "C-EUC0603"))
    )
    (comp (ref "C126")
      (value "0.1uF")
      (footprint "eagle-import:C0603")
      (fields (field (name "PARTNO") "C0603C104K5RACTU"))
      (libsource (lib "eagle-import") (part "C-EUC0603"))
    )
    (comp (ref "C127")
      (value "0.1uF")
      (footprint "eagle-import:C0603")
      (fields (field (name "PARTNO") "C0603C104K5RACTU"))
      (libsource (lib "eagle-import") (part "C-EUC0603"))
    )
    (comp (ref "C128")
      (value "0.1uF")
      (footprint "eagle-import:C0603")
      (fields (field (name "PARTNO") "C0603C104K5RACTU"))
      (libsource (lib "eagle-import") (part "C-EUC0603"))
    )
    (comp (ref "C129")
      (value "0.1uF")
      (footprint "eagle-import:C0603")
      (fields (field (name "PARTNO") "C0603C104K5RACTU"))
      (libsource (lib "eagle-import") (part "C-EUC0603"))
    )
    (comp (ref "C130")
      (value "0.1uF")
      (footprint "eagle-import:C0603")
      (fields (field (name "PARTNO") "C0603C104K5RACTU"))
      (libsource (lib "eagle-import") (part "C-EUC0603"))
    )
    (comp (ref "C131")
      (value "0.1uF")
      (footprint "eagle-import:C0603")
      (fields (field (name "PARTNO") "C0603C104K5RACTU"))
      (libsource (lib "eagle-import") (part "C-EUC0603"))
    )
    (comp (ref "C132")
      (value "0.1uF")
      (footprint "eagle-import:C0603")
      (fields (field (name "PARTNO") "C0603C104K5RACTU"))
      (libsource (lib "eagle-import") (part "C-EUC0603"))
    )
    (comp (ref "C133")
      (value "0.1uF")
      (footprint "eagle-import:C0603")
      (fields (field (name "PARTNO") "C0603C104K5RACTU"))
      (libsource (lib "eagle-import") (part "C-EUC0603"))
    )
    (comp (ref "C134")
      (value "0.1uF")
      (footprint "eagle-import:C0603")
      (fields (field (name "PARTNO") "C0603C104K5RACTU"))
      (libsource (lib "eagle-import") (part "C-EUC0603"))
    )
    (comp (ref "C135")
      (value "0.1uF")
      (footprint "eagle-import:C0603")
      (fields (field (name "PARTNO") "C0603C104K5RACTU"))
      (libsource (lib "eagle-import") (part "C-EUC0603"))
    )
    (comp (ref "C136")
      (value "0.1uF")
      (footprint "eagle-import:C0603")
      (fields (field (name "PARTNO") "C0603C104K5RACTU"))
      (libsource (lib "eagle-import") (part "C-EUC0603"))
    )
    (comp (ref "C137")
      (value "0.1uF")
      (footprint "eagle-import:C0603")
      (fields (field (name "PARTNO") "C0603C104K5RACTU"))
      (libsource (lib "eagle-import") (part "C-EUC0603"))
    )
    (comp (ref "C138")
      (value "0.1uF")
      (footprint "eagle-import:C0603")
      (fields (field (name "PARTNO") "C0603C104K5RACTU"))
      (libsource (lib "eagle-import") (part "C-EUC0603"))
    )
    (comp (ref "C139")
      (value "0.1uF")
      (footprint "eagle-import:C0603")
      (fields (field (name "PARTNO") "C0603C104K5RACTU"))
      (libsource (lib "eagle-import") (part "C-EUC0603"))
    )
    (comp (ref "C140")
      (value "0.1uF")
      (footprint "eagle-import:C0603")
      (fields (field (name "PARTNO") "C0603C104K5RACTU"))
      (libsource (lib "eagle-import") (part "C-EUC0603"))
    )
    (comp (ref "D14")
      (value "TCMT4100")
      (footprint "eagle-import:SO16")
      (fields (field (name "PARTNO") "TCMT4100"))
      (libsource (lib "eagle-import") (part "TCMT4100"))
    )
    (comp (ref "D15")
      (value "TCMT4100")
      (footprint "eagle-import:SO16")
      (fields (field (name "PARTNO") "TCMT4100"))
      (libsource (lib "eagle-import") (part "TCMT4100"))
    )
    (comp (ref "D16")
      (value "TCMT4100")
      (footprint "eagle-import:SO16")
      (fields (field (name "PARTNO") "TCMT4100"))
      (libsource (lib "eagle-import") (part "TCMT4100"))
    )
    (comp (ref "D17")
      (value "TCMT4100")
      (footprint "eagle-import:SO16")
      (fields (field (name "PARTNO") "TCMT4100"))
      (libsource (lib "eagle-import") (part "TCMT4100"))
    )
    (comp (ref "DD10")
      (value "74HC165D")
      (footprint "eagle-import:SO16")
      (fields (field (name "PARTNO") "IN74HC165AD"))
      (libsource (lib "eagle-import") (part "74165DHC"))
    )
    (comp (ref "DD11")
      (value "74HC165D")
      (footprint "eagle-import:SO16")
      (fields (field (name "PARTNO") "IN74HC165AD"))
      (libsource (lib "eagle-import") (part "74165DHC"))
    )
    (comp (ref "R285")
      (value "4.7kOhm/5%")
      (footprint "eagle-import:R1206")
      (fields (field (name "PARTNO") "RC1206JR-074K7L"))
      (libsource (lib "eagle-import") (part "R-EU_R1206"))
    )
    (comp (ref "R286")
      (value "4.7kOhm/5%")
      (footprint "eagle-import:R1206")
      (fields (field (name "PARTNO") "RC1206JR-074K7L"))
      (libsource (lib "eagle-import") (part "R-EU_R1206"))
    )
    (comp (ref "R287")
      (value "4.7kOhm/5%")
      (footprint "eagle-import:R1206")
      (fields (field (name "PARTNO") "RC1206JR-074K7L"))
      (libsource (lib "eagle-import") (part "R-EU_R1206"))
    )
    (comp (ref "R288")
      (value "4.7kOhm/5%")
      (footprint "eagle-import:R1206")
      (fields (field (name "PARTNO") "RC1206JR-074K7L"))
      (libsource (lib "eagle-import") (part "R-EU_R1206"))
    )
    (comp (ref "R289")
      (value "4.7kOhm/5%")
      (footprint "eagle-import:R1206")
      (fields (field (name "PARTNO") "RC1206JR-074K7L"))
      (libsource (lib "eagle-import") (part "R-EU_R1206"))
    )
    (comp (ref "R290")
      (value "4.7kOhm/5%")
      (footprint "eagle-import:R1206")
      (fields (field (name "PARTNO") "RC1206JR-074K7L"))
      (libsource (lib "eagle-import") (part "R-EU_R1206"))
    )
    (comp (ref "R291")
      (value "4.7kOhm/5%")
      (footprint "eagle-import:R1206")
      (fields (field (name "PARTNO") "RC1206JR-074K7L"))
      (libsource (lib "eagle-import") (part "R-EU_R1206"))
    )
    (comp (ref "R292")
      (value "4.7kOhm/5%")
      (footprint "eagle-import:R1206")
      (fields (field (name "PARTNO") "RC1206JR-074K7L"))
      (libsource (lib "eagle-import") (part "R-EU_R1206"))
    )
    (comp (ref "R293")
      (value "4.7kOhm/5%")
      (footprint "eagle-import:R1206")
      (fields (field (name "PARTNO") "RC1206JR-074K7L"))
      (libsource (lib "eagle-import") (part "R-EU_R1206"))
    )
    (comp (ref "R294")
      (value "4.7kOhm/5%")
      (footprint "eagle-import:R1206")
      (fields (field (name "PARTNO") "RC1206JR-074K7L"))
      (libsource (lib "eagle-import") (part "R-EU_R1206"))
    )
    (comp (ref "R295")
      (value "4.7kOhm/5%")
      (footprint "eagle-import:R1206")
      (fields (field (name "PARTNO") "RC1206JR-074K7L"))
      (libsource (lib "eagle-import") (part "R-EU_R1206"))
    )
    (comp (ref "R296")
      (value "4.7kOhm/5%")
      (footprint "eagle-import:R1206")
      (fields (field (name "PARTNO") "RC1206JR-074K7L"))
      (libsource (lib "eagle-import") (part "R-EU_R1206"))
    )
    (comp (ref "R297")
      (value "4.7kOhm/5%")
      (footprint "eagle-import:R1206")
      (fields (field (name "PARTNO") "RC1206JR-074K7L"))
      (libsource (lib "eagle-import") (part "R-EU_R1206"))
    )
    (comp (ref "R298")
      (value "4.7kOhm/5%")
      (footprint "eagle-import:R1206")
      (fields (field (name "PARTNO") "RC1206JR-074K7L"))
      (libsource (lib "eagle-import") (part "R-EU_R1206"))
    )
    (comp (ref "R299")
      (value "4.7kOhm/5%")
      (footprint "eagle-import:R1206")
      (fields (field (name "PARTNO") "RC1206JR-074K7L"))
      (libsource (lib "eagle-import") (part "R-EU_R1206"))
    )
    (comp (ref "R300")
      (value "4.7kOhm/5%")
      (footprint "eagle-import:R1206")
      (fields (field (name "PARTNO") "RC1206JR-074K7L"))
      (libsource (lib "eagle-import") (part "R-EU_R1206"))
    )
    (comp (ref "R301")
      (value "1kOhm/5%")
      (footprint "eagle-import:R2512")
      (fields (field (name "PARTNO") "RC2512JK-071KL"))
      (libsource (lib "eagle-import") (part "R-EU_R2512"))
    )
    (comp (ref "R302")
      (value "1kOhm/5%")
      (footprint "eagle-import:R2512")
      (fields (field (name "PARTNO") "RC2512JK-071KL"))
      (libsource (lib "eagle-import") (part "R-EU_R2512"))
    )
    (comp (ref "R303")
      (value "1kOhm/5%")
      (footprint "eagle-import:R2512")
      (fields (field (name "PARTNO") "RC2512JK-071KL"))
      (libsource (lib "eagle-import") (part "R-EU_R2512"))
    )
    (comp (ref "R304")
      (value "1kOhm/5%")
      (footprint "eagle-import:R2512")
      (fields (field (name "PARTNO") "RC2512JK-071KL"))
      (libsource (lib "eagle-import") (part "R-EU_R2512"))
    )
    (comp (ref "R305")
      (value "1kOhm/5%")
      (footprint "eagle-import:R2512")
      (fields (field (name "PARTNO") "RC2512JK-071KL"))
      (libsource (lib "eagle-import") (part "R-EU_R2512"))
    )
    (comp (ref "R306")
      (value "1kOhm/5%")
      (footprint "eagle-import:R2512")
      (fields (field (name "PARTNO") "RC2512JK-071KL"))
      (libsource (lib "eagle-import") (part "R-EU_R2512"))
    )
    (comp (ref "R307")
      (value "1kOhm/5%")
      (footprint "eagle-import:R2512")
      (fields (field (name "PARTNO") "RC2512JK-071KL"))
      (libsource (lib "eagle-import") (part "R-EU_R2512"))
    )
    (comp (ref "R308")
      (value "1kOhm/5%")
      (footprint "eagle-import:R2512")
      (fields (field (name "PARTNO") "RC2512JK-071KL"))
      (libsource (lib "eagle-import") (part "R-EU_R2512"))
    )
    (comp (ref "R309")
      (value "1kOhm/5%")
      (footprint "eagle-import:R2512")
      (fields (field (name "PARTNO") "RC2512JK-071KL"))
      (libsource (lib "eagle-import") (part "R-EU_R2512"))
    )
    (comp (ref "R310")
      (value "1kOhm/5%")
      (footprint "eagle-import:R2512")
      (fields (field (name "PARTNO") "RC2512JK-071KL"))
      (libsource (lib "eagle-import") (part "R-EU_R2512"))
    )
    (comp (ref "R311")
      (value "1kOhm/5%")
      (footprint "eagle-import:R2512")
      (fields (field (name "PARTNO") "RC2512JK-071KL"))
      (libsource (lib "eagle-import") (part "R-EU_R2512"))
    )
    (comp (ref "R312")
      (value "1kOhm/5%")
      (footprint "eagle-import:R2512")
      (fields (field (name "PARTNO") "RC2512JK-071KL"))
      (libsource (lib "eagle-import") (part "R-EU_R2512"))
    )
    (comp (ref "R313")
      (value "1kOhm/5%")
      (footprint "eagle-import:R2512")
      (fields (field (name "PARTNO") "RC2512JK-071KL"))
      (libsource (lib "eagle-import") (part "R-EU_R2512"))
    )
    (comp (ref "R314")
      (value "1kOhm/5%")
      (footprint "eagle-import:R2512")
      (fields (field (name "PARTNO") "RC2512JK-071KL"))
      (libsource (lib "eagle-import") (part "R-EU_R2512"))
    )
    (comp (ref "R315")
      (value "1kOhm/5%")
      (footprint "eagle-import:R2512")
      (fields (field (name "PARTNO") "RC2512JK-071KL"))
      (libsource (lib "eagle-import") (part "R-EU_R2512"))
    )
    (comp (ref "R316")
      (value "1kOhm/5%")
      (footprint "eagle-import:R2512")
      (fields (field (name "PARTNO") "RC2512JK-071KL"))
      (libsource (lib "eagle-import") (part "R-EU_R2512"))
    )
    (comp (ref "R317")
      (value "10kOhm/1%")
      (footprint "eagle-import:R0603")
      (fields (field (name "PARTNO") "RC0603FR-1010KL"))
      (libsource (lib "eagle-import") (part "R-EU_R0603"))
    )
    (comp (ref "R318")
      (value "10kOhm/1%")
      (footprint "eagle-import:R0603")
      (fields (field (name "PARTNO") "RC0603FR-1010KL"))
      (libsource (lib "eagle-import") (part "R-EU_R0603"))
    )
    (comp (ref "R319")
      (value "10kOhm/1%")
      (footprint "eagle-import:R0603")
      (fields (field (name "PARTNO") "RC0603FR-1010KL"))
      (libsource (lib "eagle-import") (part "R-EU_R0603"))
    )
    (comp (ref "R320")
      (value "10kOhm/1%")
      (footprint "eagle-import:R0603")
      (fields (field (name "PARTNO") "RC0603FR-1010KL"))
      (libsource (lib "eagle-import") (part "R-EU_R0603"))
    )
    (comp (ref "R321")
      (value "10kOhm/1%")
      (footprint "eagle-import:R0603")
      (fields (field (name "PARTNO") "RC0603FR-1010KL"))
      (libsource (lib "eagle-import") (part "R-EU_R0603"))
    )
    (comp (ref "R322")
      (value "10kOhm/1%")
      (footprint "eagle-import:R0603")
      (fields (field (name "PARTNO") "RC0603FR-1010KL"))
      (libsource (lib "eagle-import") (part "R-EU_R0603"))
    )
    (comp (ref "R323")
      (value "10kOhm/1%")
      (footprint "eagle-import:R0603")
      (fields (field (name "PARTNO") "RC0603FR-1010KL"))
      (libsource (lib "eagle-import") (part "R-EU_R0603"))
    )
    (comp (ref "R324")
      (value "10kOhm/1%")
      (footprint "eagle-import:R0603")
      (fields (field (name "PARTNO") "RC0603FR-1010KL"))
      (libsource (lib "eagle-import") (part "R-EU_R0603"))
    )
    (comp (ref "R325")
      (value "10kOhm/1%")
      (footprint "eagle-import:R0603")
      (fields (field (name "PARTNO") "RC0603FR-1010KL"))
      (libsource (lib "eagle-import") (part "R-EU_R0603"))
    )
    (comp (ref "R326")
      (value "10kOhm/1%")
      (footprint "eagle-import:R0603")
      (fields (field (name "PARTNO") "RC0603FR-1010KL"))
      (libsource (lib "eagle-import") (part "R-EU_R0603"))
    )
    (comp (ref "R327")
      (value "10kOhm/1%")
      (footprint "eagle-import:R0603")
      (fields (field (name "PARTNO") "RC0603FR-1010KL"))
      (libsource (lib "eagle-import") (part "R-EU_R0603"))
    )
    (comp (ref "R328")
      (value "10kOhm/1%")
      (footprint "eagle-import:R0603")
      (fields (field (name "PARTNO") "RC0603FR-1010KL"))
      (libsource (lib "eagle-import") (part "R-EU_R0603"))
    )
    (comp (ref "R329")
      (value "10kOhm/1%")
      (footprint "eagle-import:R0603")
      (fields (field (name "PARTNO") "RC0603FR-1010KL"))
      (libsource (lib "eagle-import") (part "R-EU_R0603"))
    )
    (comp (ref "R330")
      (value "10kOhm/1%")
      (footprint "eagle-import:R0603")
      (fields (field (name "PARTNO") "RC0603FR-1010KL"))
      (libsource (lib "eagle-import") (part "R-EU_R0603"))
    )
    (comp (ref "R331")
      (value "10kOhm/1%")
      (footprint "eagle-import:R0603")
      (fields (field (name "PARTNO") "RC0603FR-1010KL"))
      (libsource (lib "eagle-import") (part "R-EU_R0603"))
    )
    (comp (ref "R332")
      (value "10kOhm/1%")
      (footprint "eagle-import:R0603")
      (fields (field (name "PARTNO") "RC0603FR-1010KL"))
      (libsource (lib "eagle-import") (part "R-EU_R0603"))
    )
    (comp (ref "VD164")
      (value "SM6T200A")
      (footprint "eagle-import:SMB")
      (libsource (lib "eagle-import") (part "DIODE-TVS-UNIDIR-SMB"))
    )
    (comp (ref "VD165")
      (value "SM6T200A")
      (footprint "eagle-import:SMB")
      (libsource (lib "eagle-import") (part "DIODE-TVS-UNIDIR-SMB"))
    )
    (comp (ref "VD166")
      (value "SM6T200A")
      (footprint "eagle-import:SMB")
      (libsource (lib "eagle-import") (part "DIODE-TVS-UNIDIR-SMB"))
    )
    (comp (ref "VD167")
      (value "SM6T200A")
      (footprint "eagle-import:SMB")
      (libsource (lib "eagle-import") (part "DIODE-TVS-UNIDIR-SMB"))
    )
    (comp (ref "VD168")
      (value "SM6T200A")
      (footprint "eagle-import:SMB")
      (libsource (lib "eagle-import") (part "DIODE-TVS-UNIDIR-SMB"))
    )
    (comp (ref "VD169")
      (value "SM6T200A")
      (footprint "eagle-import:SMB")
      (libsource (lib "eagle-import") (part "DIODE-TVS-UNIDIR-SMB"))
    )
    (comp (ref "VD170")
      (value "SM6T200A")
      (footprint "eagle-import:SMB")
      (libsource (lib "eagle-import") (part "DIODE-TVS-UNIDIR-SMB"))
    )
    (comp (ref "VD171")
      (value "SM6T200A")
      (footprint "eagle-import:SMB")
      (libsource (lib "eagle-import") (part "DIODE-TVS-UNIDIR-SMB"))
    )
    (comp (ref "VD172")
      (value "SM6T200A")
      (footprint "eagle-import:SMB")
      (libsource (lib "eagle-import") (part "DIODE-TVS-UNIDIR-SMB"))
    )
    (comp (ref "VD173")
      (value "SM6T200A")
      (footprint "eagle-import:SMB")
      (libsource (lib "eagle-import") (part "DIODE-TVS-UNIDIR-SMB"))
    )
    (comp (ref "VD174")
      (value "SM6T200A")
      (footprint "eagle-import:SMB")
      (libsource (lib "eagle-import") (part "DIODE-TVS-UNIDIR-SMB"))
    )
    (comp (ref "VD175")
      (value "SM6T200A")
      (footprint "eagle-import:SMB")
      (libsource (lib "eagle-import") (part "DIODE-TVS-UNIDIR-SMB"))
    )
    (comp (ref "VD176")
      (value "SM6T200A")
      (footprint "eagle-import:SMB")
      (libsource (lib "eagle-import") (part "DIODE-TVS-UNIDIR-SMB"))
    )
    (comp (ref "VD177")
      (value "SM6T200A")
      (footprint "eagle-import:SMB")
      (libsource (lib "eagle-import") (part "DIODE-TVS-UNIDIR-SMB"))
    )
    (comp (ref "VD178")
      (value "SM6T200A")
      (footprint "eagle-import:SMB")
      (libsource (lib "eagle-import") (part "DIODE-TVS-UNIDIR-SMB"))
    )
    (comp (ref "VD179")
      (value "SM6T200A")
      (footprint "eagle-import:SMB")
      (libsource (lib "eagle-import") (part "DIODE-TVS-UNIDIR-SMB"))
    )
    (comp (ref "VD180")
      (value "400V")
      (footprint "eagle-import:SMA")
      (fields (field (name "PARTNO") "S1G-E3/61T"))
      (libsource (lib "eagle-import") (part "DIODE-STANDARD-SMA"))
    )
    (comp (ref "VD181")
      (value "400V")
      (footprint "eagle-import:SMA")
      (fields (field (name "PARTNO") "S1G-E3/61T"))
      (libsource (lib "eagle-import") (part "DIODE-STANDARD-SMA"))
    )
    (comp (ref "VD182")
      (value "400V")
      (footprint "eagle-import:SMA")
      (fields (field (name "PARTNO") "S1G-E3/61T"))
      (libsource (lib "eagle-import") (part "DIODE-STANDARD-SMA"))
    )
    (comp (ref "VD183")
      (value "400V")
      (footprint "eagle-import:SMA")
      (fields (field (name "PARTNO") "S1G-E3/61T"))
      (libsource (lib "eagle-import") (part "DIODE-STANDARD-SMA"))
    )
    (comp (ref "VD184")
      (value "400V")
      (footprint "eagle-import:SMA")
      (fields (field (name "PARTNO") "S1G-E3/61T"))
      (libsource (lib "eagle-import") (part "DIODE-STANDARD-SMA"))
    )
    (comp (ref "VD185")
      (value "400V")
      (footprint "eagle-import:SMA")
      (fields (field (name "PARTNO") "S1G-E3/61T"))
      (libsource (lib "eagle-import") (part "DIODE-STANDARD-SMA"))
    )
    (comp (ref "VD186")
      (value "400V")
      (footprint "eagle-import:SMA")
      (fields (field (name "PARTNO") "S1G-E3/61T"))
      (libsource (lib "eagle-import") (part "DIODE-STANDARD-SMA"))
    )
    (comp (ref "VD187")
      (value "400V")
      (footprint "eagle-import:SMA")
      (fields (field (name "PARTNO") "S1G-E3/61T"))
      (libsource (lib "eagle-import") (part "DIODE-STANDARD-SMA"))
    )
    (comp (ref "VD188")
      (value "400V")
      (footprint "eagle-import:SMA")
      (fields (field (name "PARTNO") "S1G-E3/61T"))
      (libsource (lib "eagle-import") (part "DIODE-STANDARD-SMA"))
    )
    (comp (ref "VD189")
      (value "400V")
      (footprint "eagle-import:SMA")
      (fields (field (name "PARTNO") "S1G-E3/61T"))
      (libsource (lib "eagle-import") (part "DIODE-STANDARD-SMA"))
    )
    (comp (ref "VD190")
      (value "400V")
      (footprint "eagle-import:SMA")
      (fields (field (name "PARTNO") "S1G-E3/61T"))
      (libsource (lib "eagle-import") (part "DIODE-STANDARD-SMA"))
    )
    (comp (ref "VD191")
      (value "400V")
      (footprint "eagle-import:SMA")
      (fields (field (name "PARTNO") "S1G-E3/61T"))
      (libsource (lib "eagle-import") (part "DIODE-STANDARD-SMA"))
    )
    (comp (ref "VD192")
      (value "400V")
      (footprint "eagle-import:SMA")
      (fields (field (name "PARTNO") "S1G-E3/61T"))
      (libsource (lib "eagle-import") (part "DIODE-STANDARD-SMA"))
    )
    (comp (ref "VD193")
      (value "400V")
      (footprint "eagle-import:SMA")
      (fields (field (name "PARTNO") "S1G-E3/61T"))
      (libsource (lib "eagle-import") (part "DIODE-STANDARD-SMA"))
    )
    (comp (ref "VD194")
      (value "400V")
      (footprint "eagle-import:SMA")
      (fields (field (name "PARTNO") "S1G-E3/61T"))
      (libsource (lib "eagle-import") (part "DIODE-STANDARD-SMA"))
    )
    (comp (ref "VD195")
      (value "400V")
      (footprint "eagle-import:SMA")
      (fields (field (name "PARTNO") "S1G-E3/61T"))
      (libsource (lib "eagle-import") (part "DIODE-STANDARD-SMA"))
    )
    (comp (ref "XP10")
      (value "MOLEX-90130-16")
      (footprint "eagle-import:MOLEX-90130-16")
      (fields (field (name "PARTNO") "90130-1216"))
      (libsource (lib "eagle-import") (part "MOLEX-90130-16"))
    )
    (comp (ref "C12")
      (value "1uF/16V")
      (footprint "eagle-import:C0603")
      (fields (field (name "PARTNO") "C0603C105K4PACTU"))
      (libsource (lib "eagle-import") (part "C-EUC0603"))
    )
    (comp (ref "C13")
      (value "1uF/16V")
      (footprint "eagle-import:C0603")
      (fields (field (name "PARTNO") "C0603C105K4PACTU"))
      (libsource (lib "eagle-import") (part "C-EUC0603"))
    )
    (comp (ref "C14")
      (value "1uF/16V")
      (footprint "eagle-import:C0603")
      (fields (field (name "PARTNO") "C0603C105K4PACTU"))
      (libsource (lib "eagle-import") (part "C-EUC0603"))
    )
    (comp (ref "C15")
      (value "1uF/16V")
      (footprint "eagle-import:C0603")
      (fields (field (name "PARTNO") "C0603C105K4PACTU"))
      (libsource (lib "eagle-import") (part "C-EUC0603"))
    )
    (comp (ref "C16")
      (value "1uF/16V")
      (footprint "eagle-import:C0603")
      (fields (field (name "PARTNO") "C0603C105K4PACTU"))
      (libsource (lib "eagle-import") (part "C-EUC0603"))
    )
    (comp (ref "C17")
      (value "1uF/16V")
      (footprint "eagle-import:C0603")
      (fields (field (name "PARTNO") "C0603C105K4PACTU"))
      (libsource (lib "eagle-import") (part "C-EUC0603"))
    )
    (comp (ref "C18")
      (value "1uF/16V")
      (footprint "eagle-import:C0603")
      (fields (field (name "PARTNO") "C0603C105K4PACTU"))
      (libsource (lib "eagle-import") (part "C-EUC0603"))
    )
    (comp (ref "C19")
      (value "1uF/16V")
      (footprint "eagle-import:C0603")
      (fields (field (name "PARTNO") "C0603C105K4PACTU"))
      (libsource (lib "eagle-import") (part "C-EUC0603"))
    )
    (comp (ref "C20")
      (value "1uF/16V")
      (footprint "eagle-import:C0603")
      (fields (field (name "PARTNO") "C0603C105K4PACTU"))
      (libsource (lib "eagle-import") (part "C-EUC0603"))
    )
    (comp (ref "C21")
      (value "1uF/16V")
      (footprint "eagle-import:C0603")
      (fields (field (name "PARTNO") "C0603C105K4PACTU"))
      (libsource (lib "eagle-import") (part "C-EUC0603"))
    )
    (comp (ref "C22")
      (value "1uF/16V")
      (footprint "eagle-import:C0603")
      (fields (field (name "PARTNO") "C0603C105K4PACTU"))
      (libsource (lib "eagle-import") (part "C-EUC0603"))
    )
    (comp (ref "C23")
      (value "1uF/16V")
      (footprint "eagle-import:C0603")
      (fields (field (name "PARTNO") "C0603C105K4PACTU"))
      (libsource (lib "eagle-import") (part "C-EUC0603"))
    )
    (comp (ref "C24")
      (value "1uF/16V")
      (footprint "eagle-import:C0603")
      (fields (field (name "PARTNO") "C0603C105K4PACTU"))
      (libsource (lib "eagle-import") (part "C-EUC0603"))
    )
    (comp (ref "C25")
      (value "1uF/16V")
      (footprint "eagle-import:C0603")
      (fields (field (name "PARTNO") "C0603C105K4PACTU"))
      (libsource (lib "eagle-import") (part "C-EUC0603"))
    )
    (comp (ref "C26")
      (value "1uF/16V")
      (footprint "eagle-import:C0603")
      (fields (field (name "PARTNO") "C0603C105K4PACTU"))
      (libsource (lib "eagle-import") (part "C-EUC0603"))
    )
    (comp (ref "C27")
      (value "1uF/16V")
      (footprint "eagle-import:C0603")
      (fields (field (name "PARTNO") "C0603C105K4PACTU"))
      (libsource (lib "eagle-import") (part "C-EUC0603"))
    )
    (comp (ref "R26")
      (value "1kOhm/1%")
      (footprint "eagle-import:R2512")
      (fields (field (name "PARTNO") "RC2512FK-071KL"))
      (libsource (lib "eagle-import") (part "R-EU_R2512"))
    )
    (comp (ref "R27")
      (value "1kOhm/1%")
      (footprint "eagle-import:R2512")
      (fields (field (name "PARTNO") "RC2512FK-071KL"))
      (libsource (lib "eagle-import") (part "R-EU_R2512"))
    )
    (comp (ref "R28")
      (value "1kOhm/1%")
      (footprint "eagle-import:R2512")
      (fields (field (name "PARTNO") "RC2512FK-071KL"))
      (libsource (lib "eagle-import") (part "R-EU_R2512"))
    )
    (comp (ref "R29")
      (value "1kOhm/1%")
      (footprint "eagle-import:R2512")
      (fields (field (name "PARTNO") "RC2512FK-071KL"))
      (libsource (lib "eagle-import") (part "R-EU_R2512"))
    )
    (comp (ref "R30")
      (value "1kOhm/1%")
      (footprint "eagle-import:R2512")
      (fields (field (name "PARTNO") "RC2512FK-071KL"))
      (libsource (lib "eagle-import") (part "R-EU_R2512"))
    )
    (comp (ref "R31")
      (value "1kOhm/1%")
      (footprint "eagle-import:R2512")
      (fields (field (name "PARTNO") "RC2512FK-071KL"))
      (libsource (lib "eagle-import") (part "R-EU_R2512"))
    )
    (comp (ref "R32")
      (value "1kOhm/1%")
      (footprint "eagle-import:R2512")
      (fields (field (name "PARTNO") "RC2512FK-071KL"))
      (libsource (lib "eagle-import") (part "R-EU_R2512"))
    )
    (comp (ref "R33")
      (value "1kOhm/1%")
      (footprint "eagle-import:R2512")
      (fields (field (name "PARTNO") "RC2512FK-071KL"))
      (libsource (lib "eagle-import") (part "R-EU_R2512"))
    )
    (comp (ref "R34")
      (value "100kOhm/1%")
      (footprint "eagle-import:R0603")
      (fields (field (name "PARTNO") "RC0603FR-13100KL"))
      (libsource (lib "eagle-import") (part "R-EU_R0603"))
    )
    (comp (ref "R35")
      (value "100kOhm/1%")
      (footprint "eagle-import:R0603")
      (fields (field (name "PARTNO") "RC0603FR-13100KL"))
      (libsource (lib "eagle-import") (part "R-EU_R0603"))
    )
    (comp (ref "R36")
      (value "100kOhm/1%")
      (footprint "eagle-import:R0603")
      (fields (field (name "PARTNO") "RC0603FR-13100KL"))
      (libsource (lib "eagle-import") (part "R-EU_R0603"))
    )
    (comp (ref "R37")
      (value "100kOhm/1%")
      (footprint "eagle-import:R0603")
      (fields (field (name "PARTNO") "RC0603FR-13100KL"))
      (libsource (lib "eagle-import") (part "R-EU_R0603"))
    )
    (comp (ref "R38")
      (value "100kOhm/1%")
      (footprint "eagle-import:R0603")
      (fields (field (name "PARTNO") "RC0603FR-13100KL"))
      (libsource (lib "eagle-import") (part "R-EU_R0603"))
    )
    (comp (ref "R39")
      (value "100kOhm/1%")
      (footprint "eagle-import:R0603")
      (fields (field (name "PARTNO") "RC0603FR-13100KL"))
      (libsource (lib "eagle-import") (part "R-EU_R0603"))
    )
    (comp (ref "R40")
      (value "100kOhm/1%")
      (footprint "eagle-import:R0603")
      (fields (field (name "PARTNO") "RC0603FR-13100KL"))
      (libsource (lib "eagle-import") (part "R-EU_R0603"))
    )
    (comp (ref "R41")
      (value "100kOhm/1%")
      (footprint "eagle-import:R0603")
      (fields (field (name "PARTNO") "RC0603FR-13100KL"))
      (libsource (lib "eagle-import") (part "R-EU_R0603"))
    )
    (comp (ref "R42")
      (value "10kOhm/1%")
      (footprint "eagle-import:R0603")
      (fields (field (name "PARTNO") "RC0603FR-1010KL"))
      (libsource (lib "eagle-import") (part "R-EU_R0603"))
    )
    (comp (ref "R43")
      (value "10kOhm/1%")
      (footprint "eagle-import:R0603")
      (fields (field (name "PARTNO") "RC0603FR-1010KL"))
      (libsource (lib "eagle-import") (part "R-EU_R0603"))
    )
    (comp (ref "R44")
      (value "10kOhm/1%")
      (footprint "eagle-import:R0603")
      (fields (field (name "PARTNO") "RC0603FR-1010KL"))
      (libsource (lib "eagle-import") (part "R-EU_R0603"))
    )
    (comp (ref "R45")
      (value "10kOhm/1%")
      (footprint "eagle-import:R0603")
      (fields (field (name "PARTNO") "RC0603FR-1010KL"))
      (libsource (lib "eagle-import") (part "R-EU_R0603"))
    )
    (comp (ref "R46")
      (value "10kOhm/1%")
      (footprint "eagle-import:R0603")
      (fields (field (name "PARTNO") "RC0603FR-1010KL"))
      (libsource (lib "eagle-import") (part "R-EU_R0603"))
    )
    (comp (ref "R47")
      (value "10kOhm/1%")
      (footprint "eagle-import:R0603")
      (fields (field (name "PARTNO") "RC0603FR-1010KL"))
      (libsource (lib "eagle-import") (part "R-EU_R0603"))
    )
    (comp (ref "R48")
      (value "10kOhm/1%")
      (footprint "eagle-import:R0603")
      (fields (field (name "PARTNO") "RC0603FR-1010KL"))
      (libsource (lib "eagle-import") (part "R-EU_R0603"))
    )
    (comp (ref "R49")
      (value "10kOhm/1%")
      (footprint "eagle-import:R0603")
      (fields (field (name "PARTNO") "RC0603FR-1010KL"))
      (libsource (lib "eagle-import") (part "R-EU_R0603"))
    )
    (comp (ref "R50")
      (value "1kOhm/1%")
      (footprint "eagle-import:R2512")
      (fields (field (name "PARTNO") "RC2512FK-071KL"))
      (libsource (lib "eagle-import") (part "R-EU_R2512"))
    )
    (comp (ref "R51")
      (value "1kOhm/1%")
      (footprint "eagle-import:R2512")
      (fields (field (name "PARTNO") "RC2512FK-071KL"))
      (libsource (lib "eagle-import") (part "R-EU_R2512"))
    )
    (comp (ref "R52")
      (value "1kOhm/1%")
      (footprint "eagle-import:R2512")
      (fields (field (name "PARTNO") "RC2512FK-071KL"))
      (libsource (lib "eagle-import") (part "R-EU_R2512"))
    )
    (comp (ref "R53")
      (value "1kOhm/1%")
      (footprint "eagle-import:R2512")
      (fields (field (name "PARTNO") "RC2512FK-071KL"))
      (libsource (lib "eagle-import") (part "R-EU_R2512"))
    )
    (comp (ref "R54")
      (value "1kOhm/1%")
      (footprint "eagle-import:R2512")
      (fields (field (name "PARTNO") "RC2512FK-071KL"))
      (libsource (lib "eagle-import") (part "R-EU_R2512"))
    )
    (comp (ref "R55")
      (value "1kOhm/1%")
      (footprint "eagle-import:R2512")
      (fields (field (name "PARTNO") "RC2512FK-071KL"))
      (libsource (lib "eagle-import") (part "R-EU_R2512"))
    )
    (comp (ref "R56")
      (value "1kOhm/1%")
      (footprint "eagle-import:R2512")
      (fields (field (name "PARTNO") "RC2512FK-071KL"))
      (libsource (lib "eagle-import") (part "R-EU_R2512"))
    )
    (comp (ref "R57")
      (value "1kOhm/1%")
      (footprint "eagle-import:R2512")
      (fields (field (name "PARTNO") "RC2512FK-071KL"))
      (libsource (lib "eagle-import") (part "R-EU_R2512"))
    )
    (comp (ref "R58")
      (value "100kOhm/1%")
      (footprint "eagle-import:R0603")
      (fields (field (name "PARTNO") "RC0603FR-13100KL"))
      (libsource (lib "eagle-import") (part "R-EU_R0603"))
    )
    (comp (ref "R59")
      (value "100kOhm/1%")
      (footprint "eagle-import:R0603")
      (fields (field (name "PARTNO") "RC0603FR-13100KL"))
      (libsource (lib "eagle-import") (part "R-EU_R0603"))
    )
    (comp (ref "R60")
      (value "100kOhm/1%")
      (footprint "eagle-import:R0603")
      (fields (field (name "PARTNO") "RC0603FR-13100KL"))
      (libsource (lib "eagle-import") (part "R-EU_R0603"))
    )
    (comp (ref "R61")
      (value "100kOhm/1%")
      (footprint "eagle-import:R0603")
      (fields (field (name "PARTNO") "RC0603FR-13100KL"))
      (libsource (lib "eagle-import") (part "R-EU_R0603"))
    )
    (comp (ref "R62")
      (value "100kOhm/1%")
      (footprint "eagle-import:R0603")
      (fields (field (name "PARTNO") "RC0603FR-13100KL"))
      (libsource (lib "eagle-import") (part "R-EU_R0603"))
    )
    (comp (ref "R63")
      (value "100kOhm/1%")
      (footprint "eagle-import:R0603")
      (fields (field (name "PARTNO") "RC0603FR-13100KL"))
      (libsource (lib "eagle-import") (part "R-EU_R0603"))
    )
    (comp (ref "R64")
      (value "100kOhm/1%")
      (footprint "eagle-import:R0603")
      (fields (field (name "PARTNO") "RC0603FR-13100KL"))
      (libsource (lib "eagle-import") (part "R-EU_R0603"))
    )
    (comp (ref "R65")
      (value "100kOhm/1%")
      (footprint "eagle-import:R0603")
      (fields (field (name "PARTNO") "RC0603FR-13100KL"))
      (libsource (lib "eagle-import") (part "R-EU_R0603"))
    )
    (comp (ref "R66")
      (value "10kOhm/1%")
      (footprint "eagle-import:R0603")
      (fields (field (name "PARTNO") "RC0603FR-1010KL"))
      (libsource (lib "eagle-import") (part "R-EU_R0603"))
    )
    (comp (ref "R67")
      (value "10kOhm/1%")
      (footprint "eagle-import:R0603")
      (fields (field (name "PARTNO") "RC0603FR-1010KL"))
      (libsource (lib "eagle-import") (part "R-EU_R0603"))
    )
    (comp (ref "R68")
      (value "10kOhm/1%")
      (footprint "eagle-import:R0603")
      (fields (field (name "PARTNO") "RC0603FR-1010KL"))
      (libsource (lib "eagle-import") (part "R-EU_R0603"))
    )
    (comp (ref "R69")
      (value "10kOhm/1%")
      (footprint "eagle-import:R0603")
      (fields (field (name "PARTNO") "RC0603FR-1010KL"))
      (libsource (lib "eagle-import") (part "R-EU_R0603"))
    )
    (comp (ref "R70")
      (value "10kOhm/1%")
      (footprint "eagle-import:R0603")
      (fields (field (name "PARTNO") "RC0603FR-1010KL"))
      (libsource (lib "eagle-import") (part "R-EU_R0603"))
    )
    (comp (ref "R71")
      (value "10kOhm/1%")
      (footprint "eagle-import:R0603")
      (fields (field (name "PARTNO") "RC0603FR-1010KL"))
      (libsource (lib "eagle-import") (part "R-EU_R0603"))
    )
    (comp (ref "R72")
      (value "10kOhm/1%")
      (footprint "eagle-import:R0603")
      (fields (field (name "PARTNO") "RC0603FR-1010KL"))
      (libsource (lib "eagle-import") (part "R-EU_R0603"))
    )
    (comp (ref "R73")
      (value "10kOhm/1%")
      (footprint "eagle-import:R0603")
      (fields (field (name "PARTNO") "RC0603FR-1010KL"))
      (libsource (lib "eagle-import") (part "R-EU_R0603"))
    )
    (comp (ref "VD4")
      (value "SMBJ24CA")
      (footprint "eagle-import:SMB-BIDIR")
      (libsource (lib "eagle-import") (part "DIODE-TVS-BIDIR-SMB"))
    )
    (comp (ref "VD5")
      (value "SMBJ24CA")
      (footprint "eagle-import:SMB-BIDIR")
      (libsource (lib "eagle-import") (part "DIODE-TVS-BIDIR-SMB"))
    )
    (comp (ref "VD6")
      (value "SMBJ24CA")
      (footprint "eagle-import:SMB-BIDIR")
      (libsource (lib "eagle-import") (part "DIODE-TVS-BIDIR-SMB"))
    )
    (comp (ref "VD7")
      (value "SMBJ24CA")
      (footprint "eagle-import:SMB-BIDIR")
      (libsource (lib "eagle-import") (part "DIODE-TVS-BIDIR-SMB"))
    )
    (comp (ref "VD8")
      (value "SMBJ24CA")
      (footprint "eagle-import:SMB-BIDIR")
      (libsource (lib "eagle-import") (part "DIODE-TVS-BIDIR-SMB"))
    )
    (comp (ref "VD9")
      (value "SMBJ24CA")
      (footprint "eagle-import:SMB-BIDIR")
      (libsource (lib "eagle-import") (part "DIODE-TVS-BIDIR-SMB"))
    )
    (comp (ref "VD10")
      (value "SMBJ24CA")
      (footprint "eagle-import:SMB-BIDIR")
      (libsource (lib "eagle-import") (part "DIODE-TVS-BIDIR-SMB"))
    )
    (comp (ref "VD11")
      (value "SMBJ24CA")
      (footprint "eagle-import:SMB-BIDIR")
      (libsource (lib "eagle-import") (part "DIODE-TVS-BIDIR-SMB"))
    )
    (comp (ref "VD12")
      (value "40V")
      (footprint "eagle-import:SOD323")
      (fields (field (name "PARTNO") "BAT54JFILM"))
      (libsource (lib "eagle-import") (part "DIODE-SCHOTTKY-SOD323"))
    )
    (comp (ref "VD13")
      (value "40V")
      (footprint "eagle-import:SOD323")
      (fields (field (name "PARTNO") "BAT54JFILM"))
      (libsource (lib "eagle-import") (part "DIODE-SCHOTTKY-SOD323"))
    )
    (comp (ref "VD14")
      (value "40V")
      (footprint "eagle-import:SOD323")
      (fields (field (name "PARTNO") "BAT54JFILM"))
      (libsource (lib "eagle-import") (part "DIODE-SCHOTTKY-SOD323"))
    )
    (comp (ref "VD15")
      (value "40V")
      (footprint "eagle-import:SOD323")
      (fields (field (name "PARTNO") "BAT54JFILM"))
      (libsource (lib "eagle-import") (part "DIODE-SCHOTTKY-SOD323"))
    )
    (comp (ref "VD16")
      (value "40V")
      (footprint "eagle-import:SOD323")
      (fields (field (name "PARTNO") "BAT54JFILM"))
      (libsource (lib "eagle-import") (part "DIODE-SCHOTTKY-SOD323"))
    )
    (comp (ref "VD17")
      (value "40V")
      (footprint "eagle-import:SOD323")
      (fields (field (name "PARTNO") "BAT54JFILM"))
      (libsource (lib "eagle-import") (part "DIODE-SCHOTTKY-SOD323"))
    )
    (comp (ref "VD18")
      (value "40V")
      (footprint "eagle-import:SOD323")
      (fields (field (name "PARTNO") "BAT54JFILM"))
      (libsource (lib "eagle-import") (part "DIODE-SCHOTTKY-SOD323"))
    )
    (comp (ref "VD19")
      (value "40V")
      (footprint "eagle-import:SOD323")
      (fields (field (name "PARTNO") "BAT54JFILM"))
      (libsource (lib "eagle-import") (part "DIODE-SCHOTTKY-SOD323"))
    )
    (comp (ref "VD20")
      (value "SMBJ24CA")
      (footprint "eagle-import:SMB-BIDIR")
      (libsource (lib "eagle-import") (part "DIODE-TVS-BIDIR-SMB"))
    )
    (comp (ref "VD21")
      (value "SMBJ24CA")
      (footprint "eagle-import:SMB-BIDIR")
      (libsource (lib "eagle-import") (part "DIODE-TVS-BIDIR-SMB"))
    )
    (comp (ref "VD22")
      (value "SMBJ24CA")
      (footprint "eagle-import:SMB-BIDIR")
      (libsource (lib "eagle-import") (part "DIODE-TVS-BIDIR-SMB"))
    )
    (comp (ref "VD23")
      (value "SMBJ24CA")
      (footprint "eagle-import:SMB-BIDIR")
      (libsource (lib "eagle-import") (part "DIODE-TVS-BIDIR-SMB"))
    )
    (comp (ref "VD24")
      (value "SMBJ24CA")
      (footprint "eagle-import:SMB-BIDIR")
      (libsource (lib "eagle-import") (part "DIODE-TVS-BIDIR-SMB"))
    )
    (comp (ref "VD25")
      (value "SMBJ24CA")
      (footprint "eagle-import:SMB-BIDIR")
      (libsource (lib "eagle-import") (part "DIODE-TVS-BIDIR-SMB"))
    )
    (comp (ref "VD26")
      (value "SMBJ24CA")
      (footprint "eagle-import:SMB-BIDIR")
      (libsource (lib "eagle-import") (part "DIODE-TVS-BIDIR-SMB"))
    )
    (comp (ref "VD27")
      (value "SMBJ24CA")
      (footprint "eagle-import:SMB-BIDIR")
      (libsource (lib "eagle-import") (part "DIODE-TVS-BIDIR-SMB"))
    )
    (comp (ref "VD28")
      (value "40V")
      (footprint "eagle-import:SOD323")
      (fields (field (name "PARTNO") "BAT54JFILM"))
      (libsource (lib "eagle-import") (part "DIODE-SCHOTTKY-SOD323"))
    )
    (comp (ref "VD29")
      (value "40V")
      (footprint "eagle-import:SOD323")
      (fields (field (name "PARTNO") "BAT54JFILM"))
      (libsource (lib "eagle-import") (part "DIODE-SCHOTTKY-SOD323"))
    )
    (comp (ref "VD30")
      (value "40V")
      (footprint "eagle-import:SOD323")
      (fields (field (name "PARTNO") "BAT54JFILM"))
      (libsource (lib "eagle-import") (part "DIODE-SCHOTTKY-SOD323"))
    )
    (comp (ref "VD31")
      (value "40V")
      (footprint "eagle-import:SOD323")
      (fields (field (name "PARTNO") "BAT54JFILM"))
      (libsource (lib "eagle-import") (part "DIODE-SCHOTTKY-SOD323"))
    )
    (comp (ref "VD32")
      (value "40V")
      (footprint "eagle-import:SOD323")
      (fields (field (name "PARTNO") "BAT54JFILM"))
      (libsource (lib "eagle-import") (part "DIODE-SCHOTTKY-SOD323"))
    )
    (comp (ref "VD33")
      (value "40V")
      (footprint "eagle-import:SOD323")
      (fields (field (name "PARTNO") "BAT54JFILM"))
      (libsource (lib "eagle-import") (part "DIODE-SCHOTTKY-SOD323"))
    )
    (comp (ref "VD34")
      (value "40V")
      (footprint "eagle-import:SOD323")
      (fields (field (name "PARTNO") "BAT54JFILM"))
      (libsource (lib "eagle-import") (part "DIODE-SCHOTTKY-SOD323"))
    )
    (comp (ref "VD35")
      (value "40V")
      (footprint "eagle-import:SOD323")
      (fields (field (name "PARTNO") "BAT54JFILM"))
      (libsource (lib "eagle-import") (part "DIODE-SCHOTTKY-SOD323"))
    )
    (comp (ref "XP4")
      (value "MOLEX-90130-16")
      (footprint "eagle-import:MOLEX-90130-16")
      (fields (field (name "LABEL") "ANALOG") (field (name "PARTNO") "90130-1216"))
      (libsource (lib "eagle-import") (part "MOLEX-90130-16"))
    )
    (comp (ref "Z22")
      (value "NFE31PT")
      (footprint "eagle-import:NFE31")
      (fields (field (name "PARTNO") "NFE31PT152Z1E9"))
      (libsource (lib "eagle-import") (part "NFE31PT"))
    )
    (comp (ref "Z23")
      (value "NFE31PT")
      (footprint "eagle-import:NFE31")
      (fields (field (name "PARTNO") "NFE31PT152Z1E9"))
      (libsource (lib "eagle-import") (part "NFE31PT"))
    )
    (comp (ref "Z24")
      (value "NFE31PT")
      (footprint "eagle-import:NFE31")
      (fields (field (name "PARTNO") "NFE31PT152Z1E9"))
      (libsource (lib "eagle-import") (part "NFE31PT"))
    )
    (comp (ref "Z25")
      (value "NFE31PT")
      (footprint "eagle-import:NFE31")
      (fields (field (name "PARTNO") "NFE31PT152Z1E9"))
      (libsource (lib "eagle-import") (part "NFE31PT"))
    )
    (comp (ref "Z26")
      (value "NFE31PT")
      (footprint "eagle-import:NFE31")
      (fields (field (name "PARTNO") "NFE31PT152Z1E9"))
      (libsource (lib "eagle-import") (part "NFE31PT"))
    )
    (comp (ref "Z27")
      (value "NFE31PT")
      (footprint "eagle-import:NFE31")
      (fields (field (name "PARTNO") "NFE31PT152Z1E9"))
      (libsource (lib "eagle-import") (part "NFE31PT"))
    )
    (comp (ref "Z28")
      (value "NFE31PT")
      (footprint "eagle-import:NFE31")
      (fields (field (name "PARTNO") "NFE31PT152Z1E9"))
      (libsource (lib "eagle-import") (part "NFE31PT"))
    )
    (comp (ref "Z29")
      (value "NFE31PT")
      (footprint "eagle-import:NFE31")
      (fields (field (name "PARTNO") "NFE31PT152Z1E9"))
      (libsource (lib "eagle-import") (part "NFE31PT"))
    )
    (comp (ref "Z30")
      (value "NFE31PT")
      (footprint "eagle-import:NFE31")
      (fields (field (name "PARTNO") "NFE31PT152Z1E9"))
      (libsource (lib "eagle-import") (part "NFE31PT"))
    )
    (comp (ref "Z31")
      (value "NFE31PT")
      (footprint "eagle-import:NFE31")
      (fields (field (name "PARTNO") "NFE31PT152Z1E9"))
      (libsource (lib "eagle-import") (part "NFE31PT"))
    )
    (comp (ref "Z32")
      (value "NFE31PT")
      (footprint "eagle-import:NFE31")
      (fields (field (name "PARTNO") "NFE31PT152Z1E9"))
      (libsource (lib "eagle-import") (part "NFE31PT"))
    )
    (comp (ref "Z33")
      (value "NFE31PT")
      (footprint "eagle-import:NFE31")
      (fields (field (name "PARTNO") "NFE31PT152Z1E9"))
      (libsource (lib "eagle-import") (part "NFE31PT"))
    )
    (comp (ref "Z34")
      (value "NFE31PT")
      (footprint "eagle-import:NFE31")
      (fields (field (name "PARTNO") "NFE31PT152Z1E9"))
      (libsource (lib "eagle-import") (part "NFE31PT"))
    )
    (comp (ref "Z35")
      (value "NFE31PT")
      (footprint "eagle-import:NFE31")
      (fields (field (name "PARTNO") "NFE31PT152Z1E9"))
      (libsource (lib "eagle-import") (part "NFE31PT"))
    )
    (comp (ref "Z36")
      (value "NFE31PT")
      (footprint "eagle-import:NFE31")
      (fields (field (name "PARTNO") "NFE31PT152Z1E9"))
      (libsource (lib "eagle-import") (part "NFE31PT"))
    )
    (comp (ref "Z37")
      (value "NFE31PT")
      (footprint "eagle-import:NFE31")
      (fields (field (name "PARTNO") "NFE31PT152Z1E9"))
      (libsource (lib "eagle-import") (part "NFE31PT"))
    )
  )
  (nets
    (net (code "1") (name "+3V3") (class "Default")
      (node (ref "C103") (pin "1") (pinfunction "1_1") (pintype "passive"))
      (node (ref "C104") (pin "1") (pinfunction "1_1") (pintype "passive"))
      (node (ref "C11") (pin "2") (pinfunction "2_2") (pintype "passive"))
      (node (ref "C121") (pin "1") (pinfunction "1_1") (pintype "passive"))
      (node (ref "C122") (pin "1") (pinfunction "1_1") (pintype "passive"))
      (node (ref "C139") (pin "1") (pinfunction "1_1") (pintype "passive"))
      (node (ref "C140") (pin "1") (pinfunction "1_1") (pintype "passive"))
      (node (ref "C141") (pin "1") (pinfunction "1_1") (pintype "passive"))
      (node (ref "C142") (pin "2") (pinfunction "2_2") (pintype "passive"))
      (node (ref "C68") (pin "+") (pinfunction "+_+") (pintype "passive"))
      (node (ref "C85") (pin "1") (pinfunction "1_1") (pintype "passive"))
      (node (ref "C86") (pin "1") (pinfunction "1_1") (pintype "passive"))
      (node (ref "DA14") (pin "2") (pinfunction "OUT_2") (pintype "power_in"))
      (node (ref "DA14") (pin "4") (pinfunction "OUT_4") (pintype "power_in"))
      (node (ref "DA16") (pin "3") (pinfunction "VCC_3") (pintype "power_in"))
      (node (ref "DD10") (pin "16") (pinfunction "VCC_16") (pintype "power_in"))
      (node (ref "DD11") (pin "16") (pinfunction "VCC_16") (pintype "power_in"))
      (node (ref "DD12") (pin "10") (pinfunction "~{MR}_10") (pintype "input"))
      (node (ref "DD12") (pin "16") (pinfunction "VCC_16") (pintype "power_in"))
      (node (ref "DD2") (pin "8") (pinfunction "VCC_8") (pintype "power_in"))
      (node (ref "DD4") (pin "16") (pinfunction "VCC_16") (pintype "power_in"))
      (node (ref "DD5") (pin "16") (pinfunction "VCC_16") (pintype "power_in"))
      (node (ref "DD6") (pin "16") (pinfunction "VCC_16") (pintype "power_in"))
      (node (ref "DD7") (pin "16") (pinfunction "VCC_16") (pintype "power_in"))
      (node (ref "DD8") (pin "16") (pinfunction "VCC_16") (pintype "power_in"))
      (node (ref "DD9") (pin "16") (pinfunction "VCC_16") (pintype "power_in"))
      (node (ref "R1") (pin "2") (pinfunction "2_2") (pintype "passive"))
      (node (ref "R15") (pin "1") (pinfunction "1_1") (pintype "passive"))
      (node (ref "R170") (pin "1") (pinfunction "1_1") (pintype "passive"))
      (node (ref "R171") (pin "1") (pinfunction "1_1") (pintype "passive"))
      (node (ref "R172") (pin "1") (pinfunction "1_1") (pintype "passive"))
      (node (ref "R173") (pin "1") (pinfunction "1_1") (pintype "passive"))
      (node (ref "R174") (pin "1") (pinfunction "1_1") (pintype "passive"))
      (node (ref "R175") (pin "1") (pinfunction "1_1") (pintype "passive"))
      (node (ref "R176") (pin "1") (pinfunction "1_1") (pintype "passive"))
      (node (ref "R177") (pin "1") (pinfunction "1_1") (pintype "passive"))
      (node (ref "R178") (pin "1") (pinfunction "1_1") (pintype "passive"))
      (node (ref "R179") (pin "1") (pinfunction "1_1") (pintype "passive"))
      (node (ref "R180") (pin "1") (pinfunction "1_1") (pintype "passive"))
      (node (ref "R181") (pin "1") (pinfunction "1_1") (pintype "passive"))
      (node (ref "R182") (pin "1") (pinfunction "1_1") (pintype "passive"))
      (node (ref "R183") (pin "1") (pinfunction "1_1") (pintype "passive"))
      (node (ref "R184") (pin "1") (pinfunction "1_1") (pintype "passive"))
      (node (ref "R185") (pin "1") (pinfunction "1_1") (pintype "passive"))
      (node (ref "R2") (pin "2") (pinfunction "2_2") (pintype "passive"))
      (node (ref "R221") (pin "1") (pinfunction "1_1") (pintype "passive"))
      (node (ref "R222") (pin "1") (pinfunction "1_1") (pintype "passive"))
      (node (ref "R223") (pin "1") (pinfunction "1_1") (pintype "passive"))
      (node (ref "R224") (pin "1") (pinfunction "1_1") (pintype "passive"))
      (node (ref "R225") (pin "1") (pinfunction "1_1") (pintype "passive"))
      (node (ref "R226") (pin "1") (pinfunction "1_1") (pintype "passive"))
      (node (ref "R227") (pin "1") (pinfunction "1_1") (pintype "passive"))
      (node (ref "R228") (pin "1") (pinfunction "1_1") (pintype "passive"))
      (node (ref "R229") (pin "1") (pinfunction "1_1") (pintype "passive"))
      (node (ref "R230") (pin "1") (pinfunction "1_1") (pintype "passive"))
      (node (ref "R231") (pin "1") (pinfunction "1_1") (pintype "passive"))
      (node (ref "R232") (pin "1") (pinfunction "1_1") (pintype "passive"))
      (node (ref "R233") (pin "1") (pinfunction "1_1") (pintype "passive"))
      (node (ref "R234") (pin "1") (pinfunction "1_1") (pintype "passive"))
      (node (ref "R235") (pin "1") (pinfunction "1_1") (pintype "passive"))
      (node (ref "R236") (pin "1") (pinfunction "1_1") (pintype "passive"))
      (node (ref "R25") (pin "1") (pinfunction "1_1") (pintype "passive"))
      (node (ref "R269") (pin "1") (pinfunction "1_1") (pintype "passive"))
      (node (ref "R270") (pin "1") (pinfunction "1_1") (pintype "passive"))
      (node (ref "R271") (pin "1") (pinfunction "1_1") (pintype "passive"))
      (node (ref "R272") (pin "1") (pinfunction "1_1") (pintype "passive"))
      (node (ref "R273") (pin "1") (pinfunction "1_1") (pintype "passive"))
      (node (ref "R274") (pin "1") (pinfunction "1_1") (pintype "passive"))
      (node (ref "R275") (pin "1") (pinfunction "1_1") (pintype "passive"))
      (node (ref "R276") (pin "1") (pinfunction "1_1") (pintype "passive"))
      (node (ref "R277") (pin "1") (pinfunction "1_1") (pintype "passive"))
      (node (ref "R278") (pin "1") (pinfunction "1_1") (pintype "passive"))
      (node (ref "R279") (pin "1") (pinfunction "1_1") (pintype "passive"))
      (node (ref "R280") (pin "1") (pinfunction "1_1") (pintype "passive"))
      (node (ref "R281") (pin "1") (pinfunction "1_1") (pintype "passive"))
      (node (ref "R282") (pin "1") (pinfunction "1_1") (pintype "passive"))
      (node (ref "R283") (pin "1") (pinfunction "1_1") (pintype "passive"))
      (node (ref "R284") (pin "1") (pinfunction "1_1") (pintype "passive"))
      (node (ref "R317") (pin "1") (pinfunction "1_1") (pintype "passive"))
      (node (ref "R318") (pin "1") (pinfunction "1_1") (pintype "passive"))
      (node (ref "R319") (pin "1") (pinfunction "1_1") (pintype "passive"))
      (node (ref "R320") (pin "1") (pinfunction "1_1") (pintype "passive"))
      (node (ref "R321") (pin "1") (pinfunction "1_1") (pintype "passive"))
      (node (ref "R322") (pin "1") (pinfunction "1_1") (pintype "passive"))
      (node (ref "R323") (pin "1") (pinfunction "1_1") (pintype "passive"))
      (node (ref "R324") (pin "1") (pinfunction "1_1") (pintype "passive"))
      (node (ref "R325") (pin "1") (pinfunction "1_1") (pintype "passive"))
      (node (ref "R326") (pin "1") (pinfunction "1_1") (pintype "passive"))
      (node (ref "R327") (pin "1") (pinfunction "1_1") (pintype "passive"))
      (node (ref "R328") (pin "1") (pinfunction "1_1") (pintype "passive"))
      (node (ref "R329") (pin "1") (pinfunction "1_1") (pintype "passive"))
      (node (ref "R330") (pin "1") (pinfunction "1_1") (pintype "passive"))
      (node (ref "R331") (pin "1") (pinfunction "1_1") (pintype "passive"))
      (node (ref "R332") (pin "1") (pinfunction "1_1") (pintype "passive"))
      (node (ref "R333") (pin "2") (pinfunction "2_2") (pintype "passive"))
      (node (ref "R362") (pin "2") (pinfunction "2_2") (pintype "passive"))
      (node (ref "R6") (pin "2") (pinfunction "2_2") (pintype "passive"))
      (node (ref "R7") (pin "2") (pinfunction "2_2") (pintype "passive"))
      (node (ref "R8") (pin "2") (pinfunction "2_2") (pintype "passive"))
      (node (ref "R9") (pin "2") (pinfunction "2_2") (pintype "passive"))
      (node (ref "VD3") (pin "A") (pinfunction "A_A") (pintype "passive"))
      (node (ref "VT3") (pin "C") (pinfunction "C_C") (pintype "passive"))
      (node (ref "XP1") (pin "1") (pinfunction "1_1") (pintype "passive"))
      (node (ref "XP1") (pin "2") (pinfunction "2_2") (pintype "passive"))
      (node (ref "XP2") (pin "1") (pinfunction "1_1") (pintype "passive"))
      (node (ref "XP3") (pin "1") (pinfunction "1_1") (pintype "passive"))
      (node (ref "Z1") (pin "3") (pinfunction "3_3") (pintype "passive"))
    )
    (net (code "2") (name "+3V3_DIRT") (class "Default")
      (node (ref "C1") (pin "1") (pinfunction "1_1") (pintype "passive"))
      (node (ref "C144") (pin "1") (pinfunction "1_1") (pintype "passive"))
      (node (ref "C2") (pin "1") (pinfunction "1_1") (pintype "passive"))
      (node (ref "C5") (pin "+") (pinfunction "+_+") (pintype "passive"))
      (node (ref "C6") (pin "1") (pinfunction "1_1") (pintype "passive"))
      (node (ref "C8") (pin "1") (pinfunction "1_1") (pintype "passive"))
      (node (ref "C9") (pin "1") (pinfunction "1_1") (pintype "passive"))
      (node (ref "DA17") (pin "16") (pinfunction "VCC_16") (pintype "power_in"))
      (node (ref "DD1") (pin "100") (pinfunction "VDD_3_100") (pintype "power_in"))
      (node (ref "DD1") (pin "11") (pinfunction "VDD_5_11") (pintype "power_in"))
      (node (ref "DD1") (pin "28") (pinfunction "VDD_4_28") (pintype "power_in"))
      (node (ref "DD1") (pin "50") (pinfunction "VDD_1_50") (pintype "power_in"))
      (node (ref "DD1") (pin "6") (pinfunction "V_BAT_6") (pintype "power_in"))
      (node (ref "DD1") (pin "75") (pinfunction "VDD_2_75") (pintype "power_in"))
      (node (ref "L1") (pin "1") (pinfunction "1_1") (pintype "passive"))
      (node (ref "Z1") (pin "1") (pinfunction "1_1") (pintype "passive"))
    )
    (net (code "3") (name "+5V") (class "Default")
      (node (ref "C28") (pin "1") (pinfunction "1_1") (pintype "passive"))
      (node (ref "C29") (pin "1") (pinfunction "1_1") (pintype "passive"))
      (node (ref "C30") (pin "1") (pinfunction "1_1") (pintype "passive"))
      (node (ref "C37") (pin "1") (pinfunction "1_1") (pintype "passive"))
      (node (ref "C38") (pin "1") (pinfunction "1_1") (pintype "passive"))
      (node (ref "C39") (pin "1") (pinfunction "1_1") (pintype "passive"))
      (node (ref "C40") (pin "1") (pinfunction "1_1") (pintype "passive"))
      (node (ref "C41") (pin "1") (pinfunction "1_1") (pintype "passive"))
      (node (ref "C42") (pin "1") (pinfunction "1_1") (pintype "passive"))
      (node (ref "C50") (pin "1") (pinfunction "1_1") (pintype "passive"))
      (node (ref "C52") (pin "1") (pinfunction "1_1") (pintype "passive"))
      (node (ref "DA1") (pin "8") (pinfunction "VCC_8") (pintype "power_in"))
      (node (ref "DA10") (pin "4") (pinfunction "RESET_4") (pintype "input"))
      (node (ref "DA10") (pin "8") (pinfunction "VCC_8") (pintype "power_in"))
      (node (ref "DA2") (pin "8") (pinfunction "VCC_8") (pintype "power_in"))
      (node (ref "DA3") (pin "8") (pinfunction "VCC_8") (pintype "power_in"))
      (node (ref "DA4") (pin "8") (pinfunction "VCC_8") (pintype "power_in"))
      (node (ref "DA5") (pin "8") (pinfunction "VCC_8") (pintype "power_in"))
      (node (ref "DA6") (pin "8") (pinfunction "VCC_8") (pintype "power_in"))
      (node (ref "DA7") (pin "10") (pinfunction "D_10") (pintype "input"))
      (node (ref "DA7") (pin "11") (pinfunction "CLR_11") (pintype "input"))
      (node (ref "DA7") (pin "16") (pinfunction "VCC_16") (pintype "power_in"))
      (node (ref "DA7") (pin "3") (pinfunction "CLR_3") (pintype "input"))
      (node (ref "DA8") (pin "10") (pinfunction "D_10") (pintype "input"))
      (node (ref "DA8") (pin "11") (pinfunction "CLR_11") (pintype "input"))
      (node (ref "DA8") (pin "16") (pinfunction "VCC_16") (pintype "power_in"))
      (node (ref "DA8") (pin "3") (pinfunction "CLR_3") (pintype "input"))
      (node (ref "DA9") (pin "10") (pinfunction "D_10") (pintype "input"))
      (node (ref "DA9") (pin "11") (pinfunction "CLR_11") (pintype "input"))
      (node (ref "DA9") (pin "16") (pinfunction "VCC_16") (pintype "power_in"))
      (node (ref "DA9") (pin "3") (pinfunction "CLR_3") (pintype "input"))
      (node (ref "DD3") (pin "14") (pinfunction "VCC_14") (pintype "power_in"))
      (node (ref "R113") (pin "1") (pinfunction "1_1") (pintype "passive"))
      (node (ref "R114") (pin "1") (pinfunction "1_1") (pintype "passive"))
      (node (ref "R115") (pin "1") (pinfunction "1_1") (pintype "passive"))
      (node (ref "R116") (pin "1") (pinfunction "A_1") (pintype "passive"))
      (node (ref "R117") (pin "2") (pinfunction "2_2") (pintype "passive"))
      (node (ref "R118") (pin "2") (pinfunction "2_2") (pintype "passive"))
      (node (ref "R119") (pin "2") (pinfunction "2_2") (pintype "passive"))
      (node (ref "R120") (pin "2") (pinfunction "2_2") (pintype "passive"))
      (node (ref "R121") (pin "2") (pinfunction "2_2") (pintype "passive"))
      (node (ref "R122") (pin "2") (pinfunction "2_2") (pintype "passive"))
      (node (ref "R123") (pin "2") (pinfunction "2_2") (pintype "passive"))
      (node (ref "R136") (pin "1") (pinfunction "1_1") (pintype "passive"))
      (node (ref "RK2") (pin "2") (pinfunction "P$2_2") (pintype "passive"))
      (node (ref "VD60") (pin "A") (pinfunction "A_A") (pintype "passive"))
    )
    (net (code "4") (name "+5V_USB") (class "Default")
      (node (ref "L4") (pin "2") (pinfunction "2_2") (pintype "passive"))
      (node (ref "R359") (pin "2") (pinfunction "2_2") (pintype "passive"))
      (node (ref "R361") (pin "2") (pinfunction "2_2") (pintype "passive"))
      (node (ref "VD56") (pin "A") (pinfunction "A_A") (pintype "passive"))
      (node (ref "VT3") (pin "B") (pinfunction "B_B") (pintype "passive"))
    )
    (net (code "5") (name "+24V") (class "Default")
      (node (ref "VD61") (pin "3") (pinfunction "A_3") (pintype "passive"))
      (node (ref "VD62") (pin "A1") (pinfunction "A1_A1") (pintype "passive"))
      (node (ref "XP6") (pin "2") (pinfunction "2_2") (pintype "passive"))
      (node (ref "XP6") (pin "4") (pinfunction "4_4") (pintype "passive"))
      (node (ref "XP6") (pin "6") (pinfunction "6_6") (pintype "passive"))
      (node (ref "XP6") (pin "8") (pinfunction "8_8") (pintype "passive"))
    )
    (net (code "6") (name "+24V_CLEAR") (class "Default")
      (node (ref "C56") (pin "2") (pinfunction "2_2") (pintype "passive"))
      (node (ref "C57") (pin "+") (pinfunction "+_+") (pintype "passive"))
      (node (ref "C58") (pin "2") (pinfunction "2_2") (pintype "passive"))
      (node (ref "C59") (pin "1") (pinfunction "1_1") (pintype "passive"))
      (node (ref "C60") (pin "2") (pinfunction "2_2") (pintype "passive"))
      (node (ref "C61") (pin "1") (pinfunction "1_1") (pintype "passive"))
      (node (ref "D5") (pin "TAB") (pinfunction "VCC_TAB") (pintype "power_in"))
      (node (ref "DA12") (pin "1") (pinfunction "VIN_1") (pintype "input"))
      (node (ref "DA13") (pin "1") (pinfunction "VIN_1") (pintype "input"))
      (node (ref "R26") (pin "1") (pinfunction "1_1") (pintype "passive"))
      (node (ref "R27") (pin "1") (pinfunction "1_1") (pintype "passive"))
      (node (ref "R28") (pin "1") (pinfunction "1_1") (pintype "passive"))
      (node (ref "R29") (pin "1") (pinfunction "1_1") (pintype "passive"))
      (node (ref "R30") (pin "1") (pinfunction "1_1") (pintype "passive"))
      (node (ref "R31") (pin "1") (pinfunction "1_1") (pintype "passive"))
      (node (ref "R32") (pin "1") (pinfunction "1_1") (pintype "passive"))
      (node (ref "R33") (pin "1") (pinfunction "1_1") (pintype "passive"))
      (node (ref "R50") (pin "1") (pinfunction "1_1") (pintype "passive"))
      (node (ref "R51") (pin "1") (pinfunction "1_1") (pintype "passive"))
      (node (ref "R52") (pin "1") (pinfunction "1_1") (pintype "passive"))
      (node (ref "R53") (pin "1") (pinfunction "1_1") (pintype "passive"))
      (node (ref "R54") (pin "1") (pinfunction "1_1") (pintype "passive"))
      (node (ref "R55") (pin "1") (pinfunction "1_1") (pintype "passive"))
      (node (ref "R56") (pin "1") (pinfunction "1_1") (pintype "passive"))
      (node (ref "R57") (pin "1") (pinfunction "1_1") (pintype "passive"))
      (node (ref "Z41") (pin "3") (pinfunction "3_3") (pintype "passive"))
    )
    (net (code "7") (name "-5V") (class "Default")
      (node (ref "C28") (pin "2") (pinfunction "2_2") (pintype "passive"))
      (node (ref "C29") (pin "2") (pinfunction "2_2") (pintype "passive"))
      (node (ref "C30") (pin "2") (pinfunction "2_2") (pintype "passive"))
      (node (ref "C37") (pin "2") (pinfunction "2_2") (pintype "passive"))
      (node (ref "C38") (pin "2") (pinfunction "2_2") (pintype "passive"))
      (node (ref "C39") (pin "2") (pinfunction "2_2") (pintype "passive"))
      (node (ref "DA1") (pin "4") (pinfunction "GND_4") (pintype "power_in"))
      (node (ref "DA2") (pin "4") (pinfunction "GND_4") (pintype "power_in"))
      (node (ref "DA3") (pin "4") (pinfunction "GND_4") (pintype "power_in"))
      (node (ref "DA4") (pin "4") (pinfunction "GND_4") (pintype "power_in"))
      (node (ref "DA5") (pin "4") (pinfunction "GND_4") (pintype "power_in"))
      (node (ref "DA6") (pin "4") (pinfunction "GND_4") (pintype "power_in"))
      (node (ref "R116") (pin "3") (pinfunction "E_3") (pintype "passive"))
      (node (ref "R137") (pin "2") (pinfunction "2_2") (pintype "passive"))
      (node (ref "RK3") (pin "2") (pinfunction "P$2_2") (pintype "passive"))
    )
    (net (code "8") (name "AGND") (class "Default")
      (node (ref "C12") (pin "2") (pinfunction "2_2") (pintype "passive"))
      (node (ref "C13") (pin "2") (pinfunction "2_2") (pintype "passive"))
      (node (ref "C14") (pin "2") (pinfunction "2_2") (pintype "passive"))
      (node (ref "C15") (pin "2") (pinfunction "2_2") (pintype "passive"))
      (node (ref "C16") (pin "2") (pinfunction "2_2") (pintype "passive"))
      (node (ref "C17") (pin "2") (pinfunction "2_2") (pintype "passive"))
      (node (ref "C18") (pin "2") (pinfunction "2_2") (pintype "passive"))
      (node (ref "C19") (pin "2") (pinfunction "2_2") (pintype "passive"))
      (node (ref "C20") (pin "2") (pinfunction "2_2") (pintype "passive"))
      (node (ref "C21") (pin "2") (pinfunction "2_2") (pintype "passive"))
      (node (ref "C22") (pin "2") (pinfunction "2_2") (pintype "passive"))
      (node (ref "C23") (pin "2") (pinfunction "2_2") (pintype "passive"))
      (node (ref "C24") (pin "2") (pinfunction "2_2") (pintype "passive"))
      (node (ref "C25") (pin "2") (pinfunction "2_2") (pintype "passive"))
      (node (ref "C26") (pin "2") (pinfunction "2_2") (pintype "passive"))
      (node (ref "C27") (pin "2") (pinfunction "2_2") (pintype "passive"))
      (node (ref "R42") (pin "1") (pinfunction "1_1") (pintype "passive"))
      (node (ref "R43") (pin "1") (pinfunction "1_1") (pintype "passive"))
      (node (ref "R44") (pin "1") (pinfunction "1_1") (pintype "passive"))
      (node (ref "R45") (pin "1") (pinfunction "1_1") (pintype "passive"))
      (node (ref "R46") (pin "1") (pinfunction "1_1") (pintype "passive"))
      (node (ref "R47") (pin "1") (pinfunction "1_1") (pintype "passive"))
      (node (ref "R48") (pin "1") (pinfunction "1_1") (pintype "passive"))
      (node (ref "R49") (pin "1") (pinfunction "1_1") (pintype "passive"))
      (node (ref "R66") (pin "1") (pinfunction "1_1") (pintype "passive"))
      (node (ref "R67") (pin "1") (pinfunction "1_1") (pintype "passive"))
      (node (ref "R68") (pin "1") (pinfunction "1_1") (pintype "passive"))
      (node (ref "R69") (pin "1") (pinfunction "1_1") (pintype "passive"))
      (node (ref "R70") (pin "1") (pinfunction "1_1") (pintype "passive"))
      (node (ref "R71") (pin "1") (pinfunction "1_1") (pintype "passive"))
      (node (ref "R72") (pin "1") (pinfunction "1_1") (pintype "passive"))
      (node (ref "R73") (pin "1") (pinfunction "1_1") (pintype "passive"))
      (node (ref "Z5") (pin "3") (pinfunction "3_3") (pintype "passive"))
    )
    (net (code "9") (name "AN_FILTERED_0") (class "Default")
      (node (ref "DD1") (pin "23") (pinfunction "PA0(WKUP/USART2_CTS/ADC123_IN0/TIM2_CH1_ETR/TIM5_CH1/TIM8_ETR)_23") (pintype "bidirectional"))
      (node (ref "Z24") (pin "3") (pinfunction "3_3") (pintype "passive"))
    )
    (net (code "10") (name "AN_FILTERED_1") (class "Default")
      (node (ref "DD1") (pin "24") (pinfunction "PA1(USART2_RTS/ADC123_IN1/TIM5_CH2/TIM2_CH2)_24") (pintype "bidirectional"))
      (node (ref "Z27") (pin "3") (pinfunction "3_3") (pintype "passive"))
    )
    (net (code "11") (name "AN_FILTERED_2") (class "Default")
      (node (ref "DD1") (pin "25") (pinfunction "PA2(USART2_TX/ADC123_IN2/TIM5_CH3/TIM2_CH3)_25") (pintype "bidirectional"))
      (node (ref "Z29") (pin "3") (pinfunction "3_3") (pintype "passive"))
    )
    (net (code "12") (name "AN_FILTERED_3") (class "Default")
      (node (ref "DD1") (pin "26") (pinfunction "PA3(USART2_RX/ADC123_IN3/TIM5_CH4/TIM2_CH4)_26") (pintype "bidirectional"))
      (node (ref "Z28") (pin "3") (pinfunction "3_3") (pintype "passive"))
    )
    (net (code "13") (name "AN_FILTERED_4") (class "Default")
      (node (ref "DD1") (pin "29") (pinfunction "PA4(SPI1_NSS/USART2_CK/DAC1/ADC12_IN4)_29") (pintype "bidirectional"))
      (node (ref "Z30") (pin "3") (pinfunction "3_3") (pintype "passive"))
    )
    (net (code "14") (name "AN_FILTERED_5") (class "Default")
      (node (ref "DD1") (pin "30") (pinfunction "PA5(SPI1_SCK/DAC2/ADC12_IN5)_30") (pintype "bidirectional"))
      (node (ref "Z31") (pin "3") (pinfunction "3_3") (pintype "passive"))
    )
    (net (code "15") (name "AN_FILTERED_6") (class "Default")
      (node (ref "DD1") (pin "31") (pinfunction "PA6(SPI1_MISO/TIM8_BKIN/ADC12_IN6/TIM3_CH1/TIM1_BKIN)_31") (pintype "bidirectional"))
      (node (ref "Z33") (pin "3") (pinfunction "3_3") (pintype "passive"))
    )
    (net (code "16") (name "AN_FILTERED_7") (class "Default")
      (node (ref "DD1") (pin "32") (pinfunction "PA7(SPI1_MOSI/TIM8_CH1N/ADC12_IN7/TIM3_CH2/TIM1_CH1N)_32") (pintype "bidirectional"))
      (node (ref "Z34") (pin "3") (pinfunction "3_3") (pintype "passive"))
    )
    (net (code "17") (name "AN_FILTERED_8") (class "Default")
      (node (ref "DD1") (pin "35") (pinfunction "PB0(ADC12_IN8/TIM3_CH3/TIM8_CH2N/TIM1_CH2N)_35") (pintype "bidirectional"))
      (node (ref "Z37") (pin "3") (pinfunction "3_3") (pintype "passive"))
    )
    (net (code "18") (name "AN_FILTERED_9") (class "Default")
      (node (ref "DD1") (pin "36") (pinfunction "PB1(ADC12_IN9/TIM3_CH4/TIM8_CH3N/TIM1_CH3N)_36") (pintype "bidirectional"))
      (node (ref "Z36") (pin "3") (pinfunction "3_3") (pintype "passive"))
    )
    (net (code "19") (name "AN_FILTERED_10") (class "Default")
      (node (ref "DD1") (pin "15") (pinfunction "PC0(ADC123_IN10)_15") (pintype "bidirectional"))
      (node (ref "Z22") (pin "3") (pinfunction "3_3") (pintype "passive"))
    )
    (net (code "20") (name "AN_FILTERED_11") (class "Default")
      (node (ref "DD1") (pin "16") (pinfunction "PC1(ADC123_IN11)_16") (pintype "bidirectional"))
      (node (ref "Z23") (pin "3") (pinfunction "3_3") (pintype "passive"))
    )
    (net (code "21") (name "AN_FILTERED_12") (class "Default")
      (node (ref "DD1") (pin "17") (pinfunction "PC2(ADC123_IN12)_17") (pintype "bidirectional"))
      (node (ref "Z25") (pin "3") (pinfunction "3_3") (pintype "passive"))
    )
    (net (code "22") (name "AN_FILTERED_13") (class "Default")
      (node (ref "DD1") (pin "18") (pinfunction "PC3(ADC123_IN13)_18") (pintype "bidirectional"))
      (node (ref "Z26") (pin "3") (pinfunction "3_3") (pintype "passive"))
    )
    (net (code "23") (name "AN_FILTERED_14") (class "Default")
      (node (ref "DD1") (pin "33") (pinfunction "PC4(ADC12_IN14)_33") (pintype "bidirectional"))
      (node (ref "Z32") (pin "3") (pinfunction "3_3") (pintype "passive"))
    )
    (net (code "24") (name "AN_FILTERED_15") (class "Default")
      (node (ref "DD1") (pin "34") (pinfunction "PC5(ADC12_IN15)_34") (pintype "bidirectional"))
      (node (ref "Z35") (pin "3") (pinfunction "3_3") (pintype "passive"))
    )
    (net (code "25") (name "AN_RAW_1") (class "Default")
      (node (ref "R31") (pin "2") (pinfunction "2_2") (pintype "passive"))
      (node (ref "VD17") (pin "A") (pinfunction "A_A") (pintype "passive"))
      (node (ref "VD9") (pin "A1") (pinfunction "A1_A1") (pintype "passive"))
      (node (ref "XP4") (pin "1") (pinfunction "1_1") (pintype "passive"))
    )
    (net (code "26") (name "AN_RAW_2") (class "Default")
      (node (ref "R33") (pin "2") (pinfunction "2_2") (pintype "passive"))
      (node (ref "VD11") (pin "A1") (pinfunction "A1_A1") (pintype "passive"))
      (node (ref "VD19") (pin "A") (pinfunction "A_A") (pintype "passive"))
      (node (ref "XP4") (pin "2") (pinfunction "2_2") (pintype "passive"))
    )
    (net (code "27") (name "AN_RAW_3") (class "Default")
      (node (ref "R32") (pin "2") (pinfunction "2_2") (pintype "passive"))
      (node (ref "VD10") (pin "A1") (pinfunction "A1_A1") (pintype "passive"))
      (node (ref "VD18") (pin "A") (pinfunction "A_A") (pintype "passive"))
      (node (ref "XP4") (pin "3") (pinfunction "3_3") (pintype "passive"))
    )
    (net (code "28") (name "AN_RAW_4") (class "Default")
      (node (ref "R50") (pin "2") (pinfunction "2_2") (pintype "passive"))
      (node (ref "VD20") (pin "A1") (pinfunction "A1_A1") (pintype "passive"))
      (node (ref "VD28") (pin "A") (pinfunction "A_A") (pintype "passive"))
      (node (ref "XP4") (pin "4") (pinfunction "4_4") (pintype "passive"))
    )
    (net (code "29") (name "AN_RAW_5") (class "Default")
      (node (ref "R51") (pin "2") (pinfunction "2_2") (pintype "passive"))
      (node (ref "VD21") (pin "A1") (pinfunction "A1_A1") (pintype "passive"))
      (node (ref "VD29") (pin "A") (pinfunction "A_A") (pintype "passive"))
      (node (ref "XP4") (pin "5") (pinfunction "5_5") (pintype "passive"))
    )
    (net (code "30") (name "AN_RAW_6") (class "Default")
      (node (ref "R53") (pin "2") (pinfunction "2_2") (pintype "passive"))
      (node (ref "VD23") (pin "A1") (pinfunction "A1_A1") (pintype "passive"))
      (node (ref "VD31") (pin "A") (pinfunction "A_A") (pintype "passive"))
      (node (ref "XP4") (pin "6") (pinfunction "6_6") (pintype "passive"))
    )
    (net (code "31") (name "AN_RAW_7") (class "Default")
      (node (ref "R54") (pin "2") (pinfunction "2_2") (pintype "passive"))
      (node (ref "VD24") (pin "A1") (pinfunction "A1_A1") (pintype "passive"))
      (node (ref "VD32") (pin "A") (pinfunction "A_A") (pintype "passive"))
      (node (ref "XP4") (pin "7") (pinfunction "7_7") (pintype "passive"))
    )
    (net (code "32") (name "AN_RAW_8") (class "Default")
      (node (ref "R57") (pin "2") (pinfunction "2_2") (pintype "passive"))
      (node (ref "VD27") (pin "A1") (pinfunction "A1_A1") (pintype "passive"))
      (node (ref "VD35") (pin "A") (pinfunction "A_A") (pintype "passive"))
      (node (ref "XP4") (pin "8") (pinfunction "8_8") (pintype "passive"))
    )
    (net (code "33") (name "AN_RAW_9") (class "Default")
      (node (ref "R56") (pin "2") (pinfunction "2_2") (pintype "passive"))
      (node (ref "VD26") (pin "A1") (pinfunction "A1_A1") (pintype "passive"))
      (node (ref "VD34") (pin "A") (pinfunction "A_A") (pintype "passive"))
      (node (ref "XP4") (pin "9") (pinfunction "9_9") (pintype "passive"))
    )
    (net (code "34") (name "AN_RAW_10") (class "Default")
      (node (ref "R26") (pin "2") (pinfunction "2_2") (pintype "passive"))
      (node (ref "VD12") (pin "A") (pinfunction "A_A") (pintype "passive"))
      (node (ref "VD4") (pin "A1") (pinfunction "A1_A1") (pintype "passive"))
      (node (ref "XP4") (pin "10") (pinfunction "10_10") (pintype "passive"))
    )
    (net (code "35") (name "AN_RAW_11") (class "Default")
      (node (ref "R27") (pin "2") (pinfunction "2_2") (pintype "passive"))
      (node (ref "VD13") (pin "A") (pinfunction "A_A") (pintype "passive"))
      (node (ref "VD5") (pin "A1") (pinfunction "A1_A1") (pintype "passive"))
      (node (ref "XP4") (pin "11") (pinfunction "11_11") (pintype "passive"))
    )
    (net (code "36") (name "AN_RAW_12") (class "Default")
      (node (ref "R29") (pin "2") (pinfunction "2_2") (pintype "passive"))
      (node (ref "VD15") (pin "A") (pinfunction "A_A") (pintype "passive"))
      (node (ref "VD7") (pin "A1") (pinfunction "A1_A1") (pintype "passive"))
      (node (ref "XP4") (pin "12") (pinfunction "12_12") (pintype "passive"))
    )
    (net (code "37") (name "AN_RAW_13") (class "Default")
      (node (ref "R30") (pin "2") (pinfunction "2_2") (pintype "passive"))
      (node (ref "VD16") (pin "A") (pinfunction "A_A") (pintype "passive"))
      (node (ref "VD8") (pin "A1") (pinfunction "A1_A1") (pintype "passive"))
      (node (ref "XP4") (pin "13") (pinfunction "13_13") (pintype "passive"))
    )
    (net (code "38") (name "AN_RAW_14") (class "Default")
      (node (ref "R52") (pin "2") (pinfunction "2_2") (pintype "passive"))
      (node (ref "VD22") (pin "A1") (pinfunction "A1_A1") (pintype "passive"))
      (node (ref "VD30") (pin "A") (pinfunction "A_A") (pintype "passive"))
      (node (ref "XP4") (pin "14") (pinfunction "14_14") (pintype "passive"))
    )
    (net (code "39") (name "AN_RAW_15") (class "Default")
      (node (ref "R55") (pin "2") (pinfunction "2_2") (pintype "passive"))
      (node (ref "VD25") (pin "A1") (pinfunction "A1_A1") (pintype "passive"))
      (node (ref "VD33") (pin "A") (pinfunction "A_A") (pintype "passive"))
      (node (ref "XP4") (pin "15") (pinfunction "15_15") (pintype "passive"))
    )
    (net (code "40") (name "BOOT_0") (class "Default")
      (node (ref "DD1") (pin "94") (pinfunction "BOOT_0_94") (pintype "input"))
      (node (ref "Z10") (pin "1") (pinfunction "1_1") (pintype "passive"))
    )
    (net (code "41") (name "BOOT_1") (class "Default")
      (node (ref "DD1") (pin "37") (pinfunction "PB2(BOOT_1)*_37") (pintype "bidirectional"))
      (node (ref "Z9") (pin "1") (pinfunction "1_1") (pintype "passive"))
    )
    (net (code "42") (name "CAN_RX") (class "Default")
      (node (ref "DD1") (pin "81") (pinfunction "PD0(OSC_IN/FSMC_D2/CAN_RX)*_81") (pintype "bidirectional"))
      (node (ref "Z47") (pin "3") (pinfunction "3_3") (pintype "passive"))
    )
    (net (code "43") (name "CAN_TX") (class "Default")
      (node (ref "DD1") (pin "82") (pinfunction "PD1(OSC_OUT/FSMC_D3/CAN_TX)*_82") (pintype "bidirectional"))
      (node (ref "Z50") (pin "3") (pinfunction "3_3") (pintype "passive"))
    )
    (net (code "44") (name "FREQMETER") (class "Default")
      (node (ref "DD1") (pin "63") (pinfunction "PC6(I2S2_MCK/TIM8_CH1/SDIO_D6/TIM3_CH1)*_63") (pintype "bidirectional"))
      (node (ref "Z39") (pin "3") (pinfunction "3_3") (pintype "passive"))
    )
    (net (code "45") (name "FREQ_RAW") (class "Default")
      (node (ref "R125") (pin "2") (pinfunction "2_2") (pintype "passive"))
      (node (ref "XP5") (pin "3") (pinfunction "3_3") (pintype "passive"))
    )
    (net (code "46") (name "GND") (class "Default")
      (node (ref "C1") (pin "2") (pinfunction "2_2") (pintype "passive"))
      (node (ref "C10") (pin "2") (pinfunction "2_2") (pintype "passive"))
      (node (ref "C100") (pin "2") (pinfunction "2_2") (pintype "passive"))
      (node (ref "C101") (pin "2") (pinfunction "2_2") (pintype "passive"))
      (node (ref "C102") (pin "2") (pinfunction "2_2") (pintype "passive"))
      (node (ref "C103") (pin "2") (pinfunction "2_2") (pintype "passive"))
      (node (ref "C104") (pin "2") (pinfunction "2_2") (pintype "passive"))
      (node (ref "C105") (pin "2") (pinfunction "2_2") (pintype "passive"))
      (node (ref "C106") (pin "2") (pinfunction "2_2") (pintype "passive"))
      (node (ref "C107") (pin "2") (pinfunction "2_2") (pintype "passive"))
      (node (ref "C108") (pin "2") (pinfunction "2_2") (pintype "passive"))
      (node (ref "C109") (pin "2") (pinfunction "2_2") (pintype "passive"))
      (node (ref "C11") (pin "1") (pinfunction "1_1") (pintype "passive"))
      (node (ref "C110") (pin "2") (pinfunction "2_2") (pintype "passive"))
      (node (ref "C111") (pin "2") (pinfunction "2_2") (pintype "passive"))
      (node (ref "C112") (pin "2") (pinfunction "2_2") (pintype "passive"))
      (node (ref "C113") (pin "2") (pinfunction "2_2") (pintype "passive"))
      (node (ref "C114") (pin "2") (pinfunction "2_2") (pintype "passive"))
      (node (ref "C115") (pin "2") (pinfunction "2_2") (pintype "passive"))
      (node (ref "C116") (pin "2") (pinfunction "2_2") (pintype "passive"))
      (node (ref "C117") (pin "2") (pinfunction "2_2") (pintype "passive"))
      (node (ref "C118") (pin "2") (pinfunction "2_2") (pintype "passive"))
      (node (ref "C119") (pin "2") (pinfunction "2_2") (pintype "passive"))
      (node (ref "C120") (pin "2") (pinfunction "2_2") (pintype "passive"))
      (node (ref "C121") (pin "2") (pinfunction "2_2") (pintype "passive"))
      (node (ref "C122") (pin "2") (pinfunction "2_2") (pintype "passive"))
      (node (ref "C123") (pin "2") (pinfunction "2_2") (pintype "passive"))
      (node (ref "C124") (pin "2") (pinfunction "2_2") (pintype "passive"))
      (node (ref "C125") (pin "2") (pinfunction "2_2") (pintype "passive"))
      (node (ref "C126") (pin "2") (pinfunction "2_2") (pintype "passive"))
      (node (ref "C127") (pin "2") (pinfunction "2_2") (pintype "passive"))
      (node (ref "C128") (pin "2") (pinfunction "2_2") (pintype "passive"))
      (node (ref "C129") (pin "2") (pinfunction "2_2") (pintype "passive"))
      (node (ref "C130") (pin "2") (pinfunction "2_2") (pintype "passive"))
      (node (ref "C131") (pin "2") (pinfunction "2_2") (pintype "passive"))
      (node (ref "C132") (pin "2") (pinfunction "2_2") (pintype "passive"))
      (node (ref "C133") (pin "2") (pinfunction "2_2") (pintype "passive"))
      (node (ref "C134") (pin "2") (pinfunction "2_2") (pintype "passive"))
      (node (ref "C135") (pin "2") (pinfunction "2_2") (pintype "passive"))
      (node (ref "C136") (pin "2") (pinfunction "2_2") (pintype "passive"))
      (node (ref "C137") (pin "2") (pinfunction "2_2") (pintype "passive"))
      (node (ref "C138") (pin "2") (pinfunction "2_2") (pintype "passive"))
      (node (ref "C139") (pin "2") (pinfunction "2_2") (pintype "passive"))
      (node (ref "C140") (pin "2") (pinfunction "2_2") (pintype "passive"))
      (node (ref "C141") (pin "2") (pinfunction "2_2") (pintype "passive"))
      (node (ref "C142") (pin "1") (pinfunction "1_1") (pintype "passive"))
      (node (ref "C143") (pin "2") (pinfunction "2_2") (pintype "passive"))
      (node (ref "C144") (pin "2") (pinfunction "2_2") (pintype "passive"))
      (node (ref "C145") (pin "2") (pinfunction "2_2") (pintype "passive"))
      (node (ref "C2") (pin "2") (pinfunction "2_2") (pintype "passive"))
      (node (ref "C3") (pin "2") (pinfunction "2_2") (pintype "passive"))
      (node (ref "C31") (pin "1") (pinfunction "1_1") (pintype "passive"))
      (node (ref "C32") (pin "1") (pinfunction "1_1") (pintype "passive"))
      (node (ref "C33") (pin "1") (pinfunction "1_1") (pintype "passive"))
      (node (ref "C34") (pin "2") (pinfunction "2_2") (pintype "passive"))
      (node (ref "C35") (pin "2") (pinfunction "2_2") (pintype "passive"))
      (node (ref "C36") (pin "2") (pinfunction "2_2") (pintype "passive"))
      (node (ref "C4") (pin "2") (pinfunction "2_2") (pintype "passive"))
      (node (ref "C40") (pin "2") (pinfunction "2_2") (pintype "passive"))
      (node (ref "C41") (pin "2") (pinfunction "2_2") (pintype "passive"))
      (node (ref "C42") (pin "2") (pinfunction "2_2") (pintype "passive"))
      (node (ref "C49") (pin "2") (pinfunction "2_2") (pintype "passive"))
      (node (ref "C5") (pin "-") (pinfunction "-_-") (pintype "passive"))
      (node (ref "C50") (pin "2") (pinfunction "2_2") (pintype "passive"))
      (node (ref "C51") (pin "2") (pinfunction "2_2") (pintype "passive"))
      (node (ref "C52") (pin "2") (pinfunction "2_2") (pintype "passive"))
      (node (ref "C53") (pin "1") (pinfunction "1_1") (pintype "passive"))
      (node (ref "C54") (pin "1") (pinfunction "1_1") (pintype "passive"))
      (node (ref "C55") (pin "2") (pinfunction "2_2") (pintype "passive"))
      (node (ref "C56") (pin "1") (pinfunction "1_1") (pintype "passive"))
      (node (ref "C57") (pin "-") (pinfunction "-_-") (pintype "passive"))
      (node (ref "C59") (pin "2") (pinfunction "2_2") (pintype "passive"))
      (node (ref "C6") (pin "2") (pinfunction "2_2") (pintype "passive"))
      (node (ref "C60") (pin "1") (pinfunction "1_1") (pintype "passive"))
      (node (ref "C62") (pin "2") (pinfunction "2_2") (pintype "passive"))
      (node (ref "C63") (pin "2") (pinfunction "2_2") (pintype "passive"))
      (node (ref "C64") (pin "-") (pinfunction "-_-") (pintype "passive"))
      (node (ref "C65") (pin "2") (pinfunction "2_2") (pintype "passive"))
      (node (ref "C66") (pin "-") (pinfunction "-_-") (pintype "passive"))
      (node (ref "C67") (pin "+") (pinfunction "+_+") (pintype "passive"))
      (node (ref "C68") (pin "-") (pinfunction "-_-") (pintype "passive"))
      (node (ref "C69") (pin "2") (pinfunction "2_2") (pintype "passive"))
      (node (ref "C70") (pin "2") (pinfunction "2_2") (pintype "passive"))
      (node (ref "C71") (pin "2") (pinfunction "2_2") (pintype "passive"))
      (node (ref "C72") (pin "2") (pinfunction "2_2") (pintype "passive"))
      (node (ref "C73") (pin "2") (pinfunction "2_2") (pintype "passive"))
      (node (ref "C74") (pin "2") (pinfunction "2_2") (pintype "passive"))
      (node (ref "C75") (pin "2") (pinfunction "2_2") (pintype "passive"))
      (node (ref "C76") (pin "2") (pinfunction "2_2") (pintype "passive"))
      (node (ref "C77") (pin "2") (pinfunction "2_2") (pintype "passive"))
      (node (ref "C78") (pin "2") (pinfunction "2_2") (pintype "passive"))
      (node (ref "C79") (pin "2") (pinfunction "2_2") (pintype "passive"))
      (node (ref "C8") (pin "2") (pinfunction "2_2") (pintype "passive"))
      (node (ref "C80") (pin "2") (pinfunction "2_2") (pintype "passive"))
      (node (ref "C81") (pin "2") (pinfunction "2_2") (pintype "passive"))
      (node (ref "C82") (pin "2") (pinfunction "2_2") (pintype "passive"))
      (node (ref "C83") (pin "2") (pinfunction "2_2") (pintype "passive"))
      (node (ref "C84") (pin "2") (pinfunction "2_2") (pintype "passive"))
      (node (ref "C85") (pin "2") (pinfunction "2_2") (pintype "passive"))
      (node (ref "C86") (pin "2") (pinfunction "2_2") (pintype "passive"))
      (node (ref "C87") (pin "2") (pinfunction "2_2") (pintype "passive"))
      (node (ref "C88") (pin "2") (pinfunction "2_2") (pintype "passive"))
      (node (ref "C89") (pin "2") (pinfunction "2_2") (pintype "passive"))
      (node (ref "C9") (pin "2") (pinfunction "2_2") (pintype "passive"))
      (node (ref "C90") (pin "2") (pinfunction "2_2") (pintype "passive"))
      (node (ref "C91") (pin "2") (pinfunction "2_2") (pintype "passive"))
      (node (ref "C92") (pin "2") (pinfunction "2_2") (pintype "passive"))
      (node (ref "C93") (pin "2") (pinfunction "2_2") (pintype "passive"))
      (node (ref "C94") (pin "2") (pinfunction "2_2") (pintype "passive"))
      (node (ref "C95") (pin "2") (pinfunction "2_2") (pintype "passive"))
      (node (ref "C96") (pin "2") (pinfunction "2_2") (pintype "passive"))
      (node (ref "C97") (pin "2") (pinfunction "2_2") (pintype "passive"))
      (node (ref "C98") (pin "2") (pinfunction "2_2") (pintype "passive"))
      (node (ref "C99") (pin "2") (pinfunction "2_2") (pintype "passive"))
      (node (ref "D1") (pin "11") (pinfunction "TE_11") (pintype "bidirectional"))
      (node (ref "D1") (pin "13") (pinfunction "TE_13") (pintype "bidirectional"))
      (node (ref "D1") (pin "15") (pinfunction "TE_15") (pintype "bidirectional"))
      (node (ref "D1") (pin "2") (pinfunction "DC_2") (pintype "passive"))
      (node (ref "D1") (pin "4") (pinfunction "DC_4") (pintype "passive"))
      (node (ref "D1") (pin "6") (pinfunction "DC_6") (pintype "passive"))
      (node (ref "D1") (pin "8") (pinfunction "DC_8") (pintype "passive"))
      (node (ref "D1") (pin "9") (pinfunction "TE_9") (pintype "bidirectional"))
      (node (ref "D10") (pin "11") (pinfunction "TE_11") (pintype "bidirectional"))
      (node (ref "D10") (pin "13") (pinfunction "TE_13") (pintype "bidirectional"))
      (node (ref "D10") (pin "15") (pinfunction "TE_15") (pintype "bidirectional"))
      (node (ref "D10") (pin "2") (pinfunction "DC_2") (pintype "passive"))
      (node (ref "D10") (pin "4") (pinfunction "DC_4") (pintype "passive"))
      (node (ref "D10") (pin "6") (pinfunction "DC_6") (pintype "passive"))
      (node (ref "D10") (pin "8") (pinfunction "DC_8") (pintype "passive"))
      (node (ref "D10") (pin "9") (pinfunction "TE_9") (pintype "bidirectional"))
      (node (ref "D11") (pin "11") (pinfunction "TE_11") (pintype "bidirectional"))
      (node (ref "D11") (pin "13") (pinfunction "TE_13") (pintype "bidirectional"))
      (node (ref "D11") (pin "15") (pinfunction "TE_15") (pintype "bidirectional"))
      (node (ref "D11") (pin "2") (pinfunction "DC_2") (pintype "passive"))
      (node (ref "D11") (pin "4") (pinfunction "DC_4") (pintype "passive"))
      (node (ref "D11") (pin "6") (pinfunction "DC_6") (pintype "passive"))
      (node (ref "D11") (pin "8") (pinfunction "DC_8") (pintype "passive"))
      (node (ref "D11") (pin "9") (pinfunction "TE_9") (pintype "bidirectional"))
      (node (ref "D12") (pin "11") (pinfunction "TE_11") (pintype "bidirectional"))
      (node (ref "D12") (pin "13") (pinfunction "TE_13") (pintype "bidirectional"))
      (node (ref "D12") (pin "15") (pinfunction "TE_15") (pintype "bidirectional"))
      (node (ref "D12") (pin "2") (pinfunction "DC_2") (pintype "passive"))
      (node (ref "D12") (pin "4") (pinfunction "DC_4") (pintype "passive"))
      (node (ref "D12") (pin "6") (pinfunction "DC_6") (pintype "passive"))
      (node (ref "D12") (pin "8") (pinfunction "DC_8") (pintype "passive"))
      (node (ref "D12") (pin "9") (pinfunction "TE_9") (pintype "bidirectional"))
      (node (ref "D13") (pin "11") (pinfunction "TE_11") (pintype "bidirectional"))
      (node (ref "D13") (pin "13") (pinfunction "TE_13") (pintype "bidirectional"))
      (node (ref "D13") (pin "15") (pinfunction "TE_15") (pintype "bidirectional"))
      (node (ref "D13") (pin "2") (pinfunction "DC_2") (pintype "passive"))
      (node (ref "D13") (pin "4") (pinfunction "DC_4") (pintype "passive"))
      (node (ref "D13") (pin "6") (pinfunction "DC_6") (pintype "passive"))
      (node (ref "D13") (pin "8") (pinfunction "DC_8") (pintype "passive"))
      (node (ref "D13") (pin "9") (pinfunction "TE_9") (pintype "bidirectional"))
      (node (ref "D14") (pin "11") (pinfunction "TE_11") (pintype "bidirectional"))
      (node (ref "D14") (pin "13") (pinfunction "TE_13") (pintype "bidirectional"))
      (node (ref "D14") (pin "15") (pinfunction "TE_15") (pintype "bidirectional"))
      (node (ref "D14") (pin "2") (pinfunction "DC_2") (pintype "passive"))
      (node (ref "D14") (pin "4") (pinfunction "DC_4") (pintype "passive"))
      (node (ref "D14") (pin "6") (pinfunction "DC_6") (pintype "passive"))
      (node (ref "D14") (pin "8") (pinfunction "DC_8") (pintype "passive"))
      (node (ref "D14") (pin "9") (pinfunction "TE_9") (pintype "bidirectional"))
      (node (ref "D15") (pin "11") (pinfunction "TE_11") (pintype "bidirectional"))
      (node (ref "D15") (pin "13") (pinfunction "TE_13") (pintype "bidirectional"))
      (node (ref "D15") (pin "15") (pinfunction "TE_15") (pintype "bidirectional"))
      (node (ref "D15") (pin "2") (pinfunction "DC_2") (pintype "passive"))
      (node (ref "D15") (pin "4") (pinfunction "DC_4") (pintype "passive"))
      (node (ref "D15") (pin "6") (pinfunction "DC_6") (pintype "passive"))
      (node (ref "D15") (pin "8") (pinfunction "DC_8") (pintype "passive"))
      (node (ref "D15") (pin "9") (pinfunction "TE_9") (pintype "bidirectional"))
      (node (ref "D16") (pin "11") (pinfunction "TE_11") (pintype "bidirectional"))
      (node (ref "D16") (pin "13") (pinfunction "TE_13") (pintype "bidirectional"))
      (node (ref "D16") (pin "15") (pinfunction "TE_15") (pintype "bidirectional"))
      (node (ref "D16") (pin "2") (pinfunction "DC_2") (pintype "passive"))
      (node (ref "D16") (pin "4") (pinfunction "DC_4") (pintype "passive"))
      (node (ref "D16") (pin "6") (pinfunction "DC_6") (pintype "passive"))
      (node (ref "D16") (pin "8") (pinfunction "DC_8") (pintype "passive"))
      (node (ref "D16") (pin "9") (pinfunction "TE_9") (pintype "bidirectional"))
      (node (ref "D17") (pin "11") (pinfunction "TE_11") (pintype "bidirectional"))
      (node (ref "D17") (pin "13") (pinfunction "TE_13") (pintype "bidirectional"))
      (node (ref "D17") (pin "15") (pinfunction "TE_15") (pintype "bidirectional"))
      (node (ref "D17") (pin "2") (pinfunction "DC_2") (pintype "passive"))
      (node (ref "D17") (pin "4") (pinfunction "DC_4") (pintype "passive"))
      (node (ref "D17") (pin "6") (pinfunction "DC_6") (pintype "passive"))
      (node (ref "D17") (pin "8") (pinfunction "DC_8") (pintype "passive"))
      (node (ref "D17") (pin "9") (pinfunction "TE_9") (pintype "bidirectional"))
      (node (ref "D18") (pin "11") (pinfunction "TE_11") (pintype "bidirectional"))
      (node (ref "D18") (pin "13") (pinfunction "TE_13") (pintype "bidirectional"))
      (node (ref "D18") (pin "15") (pinfunction "TE_15") (pintype "bidirectional"))
      (node (ref "D18") (pin "2") (pinfunction "DC_2") (pintype "passive"))
      (node (ref "D18") (pin "4") (pinfunction "DC_4") (pintype "passive"))
      (node (ref "D18") (pin "6") (pinfunction "DC_6") (pintype "passive"))
      (node (ref "D18") (pin "8") (pinfunction "DC_8") (pintype "passive"))
      (node (ref "D18") (pin "9") (pinfunction "TE_9") (pintype "bidirectional"))
      (node (ref "D19") (pin "11") (pinfunction "TE_11") (pintype "bidirectional"))
      (node (ref "D19") (pin "13") (pinfunction "TE_13") (pintype "bidirectional"))
      (node (ref "D19") (pin "15") (pinfunction "TE_15") (pintype "bidirectional"))
      (node (ref "D19") (pin "2") (pinfunction "DC_2") (pintype "passive"))
      (node (ref "D19") (pin "4") (pinfunction "DC_4") (pintype "passive"))
      (node (ref "D19") (pin "6") (pinfunction "DC_6") (pintype "passive"))
      (node (ref "D19") (pin "8") (pinfunction "DC_8") (pintype "passive"))
      (node (ref "D19") (pin "9") (pinfunction "TE_9") (pintype "bidirectional"))
      (node (ref "D2") (pin "11") (pinfunction "TE_11") (pintype "bidirectional"))
      (node (ref "D2") (pin "13") (pinfunction "TE_13") (pintype "bidirectional"))
      (node (ref "D2") (pin "15") (pinfunction "TE_15") (pintype "bidirectional"))
      (node (ref "D2") (pin "2") (pinfunction "DC_2") (pintype "passive"))
      (node (ref "D2") (pin "4") (pinfunction "DC_4") (pintype "passive"))
      (node (ref "D2") (pin "6") (pinfunction "DC_6") (pintype "passive"))
      (node (ref "D2") (pin "8") (pinfunction "DC_8") (pintype "passive"))
      (node (ref "D2") (pin "9") (pinfunction "TE_9") (pintype "bidirectional"))
      (node (ref "D3") (pin "11") (pinfunction "TE_11") (pintype "bidirectional"))
      (node (ref "D3") (pin "13") (pinfunction "TE_13") (pintype "bidirectional"))
      (node (ref "D3") (pin "15") (pinfunction "TE_15") (pintype "bidirectional"))
      (node (ref "D3") (pin "2") (pinfunction "DC_2") (pintype "passive"))
      (node (ref "D3") (pin "4") (pinfunction "DC_4") (pintype "passive"))
      (node (ref "D3") (pin "6") (pinfunction "DC_6") (pintype "passive"))
      (node (ref "D3") (pin "8") (pinfunction "DC_8") (pintype "passive"))
      (node (ref "D3") (pin "9") (pinfunction "TE_9") (pintype "bidirectional"))
      (node (ref "D4") (pin "11") (pinfunction "TE_11") (pintype "bidirectional"))
      (node (ref "D4") (pin "13") (pinfunction "TE_13") (pintype "bidirectional"))
      (node (ref "D4") (pin "15") (pinfunction "TE_15") (pintype "bidirectional"))
      (node (ref "D4") (pin "2") (pinfunction "DC_2") (pintype "passive"))
      (node (ref "D4") (pin "4") (pinfunction "DC_4") (pintype "passive"))
      (node (ref "D4") (pin "6") (pinfunction "DC_6") (pintype "passive"))
      (node (ref "D4") (pin "8") (pinfunction "DC_8") (pintype "passive"))
      (node (ref "D4") (pin "9") (pinfunction "TE_9") (pintype "bidirectional"))
      (node (ref "D6") (pin "11") (pinfunction "TE_11") (pintype "bidirectional"))
      (node (ref "D6") (pin "13") (pinfunction "TE_13") (pintype "bidirectional"))
      (node (ref "D6") (pin "15") (pinfunction "TE_15") (pintype "bidirectional"))
      (node (ref "D6") (pin "2") (pinfunction "DC_2") (pintype "passive"))
      (node (ref "D6") (pin "4") (pinfunction "DC_4") (pintype "passive"))
      (node (ref "D6") (pin "6") (pinfunction "DC_6") (pintype "passive"))
      (node (ref "D6") (pin "8") (pinfunction "DC_8") (pintype "passive"))
      (node (ref "D6") (pin "9") (pinfunction "TE_9") (pintype "bidirectional"))
      (node (ref "D7") (pin "11") (pinfunction "TE_11") (pintype "bidirectional"))
      (node (ref "D7") (pin "13") (pinfunction "TE_13") (pintype "bidirectional"))
      (node (ref "D7") (pin "15") (pinfunction "TE_15") (pintype "bidirectional"))
      (node (ref "D7") (pin "2") (pinfunction "DC_2") (pintype "passive"))
      (node (ref "D7") (pin "4") (pinfunction "DC_4") (pintype "passive"))
      (node (ref "D7") (pin "6") (pinfunction "DC_6") (pintype "passive"))
      (node (ref "D7") (pin "8") (pinfunction "DC_8") (pintype "passive"))
      (node (ref "D7") (pin "9") (pinfunction "TE_9") (pintype "bidirectional"))
      (node (ref "D8") (pin "11") (pinfunction "TE_11") (pintype "bidirectional"))
      (node (ref "D8") (pin "13") (pinfunction "TE_13") (pintype "bidirectional"))
      (node (ref "D8") (pin "15") (pinfunction "TE_15") (pintype "bidirectional"))
      (node (ref "D8") (pin "2") (pinfunction "DC_2") (pintype "passive"))
      (node (ref "D8") (pin "4") (pinfunction "DC_4") (pintype "passive"))
      (node (ref "D8") (pin "6") (pinfunction "DC_6") (pintype "passive"))
      (node (ref "D8") (pin "8") (pinfunction "DC_8") (pintype "passive"))
      (node (ref "D8") (pin "9") (pinfunction "TE_9") (pintype "bidirectional"))
      (node (ref "D9") (pin "11") (pinfunction "TE_11") (pintype "bidirectional"))
      (node (ref "D9") (pin "13") (pinfunction "TE_13") (pintype "bidirectional"))
      (node (ref "D9") (pin "15") (pinfunction "TE_15") (pintype "bidirectional"))
      (node (ref "D9") (pin "2") (pinfunction "DC_2") (pintype "passive"))
      (node (ref "D9") (pin "4") (pinfunction "DC_4") (pintype "passive"))
      (node (ref "D9") (pin "6") (pinfunction "DC_6") (pintype "passive"))
      (node (ref "D9") (pin "8") (pinfunction "DC_8") (pintype "passive"))
      (node (ref "D9") (pin "9") (pinfunction "TE_9") (pintype "bidirectional"))
      (node (ref "DA10") (pin "1") (pinfunction "GND_1") (pintype "power_in"))
      (node (ref "DA11") (pin "3") (pinfunction "GND_3") (pintype "power_in"))
      (node (ref "DA12") (pin "3") (pinfunction "GND_3") (pintype "input"))
      (node (ref "DA12") (pin "5") (pinfunction "~{ON}/OFF_5") (pintype "input"))
      (node (ref "DA12") (pin "6") (pinfunction "GND_6") (pintype "input"))
      (node (ref "DA13") (pin "4") (pinfunction "FB_4") (pintype "input"))
      (node (ref "DA14") (pin "1") (pinfunction "ADJ_1") (pintype "input"))
      (node (ref "DA15") (pin "2") (pinfunction "GND_2") (pintype "power_in"))
      (node (ref "DA16") (pin "2") (pinfunction "GND_2") (pintype "power_in"))
      (node (ref "DA17") (pin "15") (pinfunction "GND_15") (pintype "power_in"))
      (node (ref "DA4") (pin "1") (pinfunction "E_OUT_1") (pintype "bidirectional"))
      (node (ref "DA5") (pin "1") (pinfunction "E_OUT_1") (pintype "bidirectional"))
      (node (ref "DA6") (pin "1") (pinfunction "E_OUT_1") (pintype "bidirectional"))
      (node (ref "DA7") (pin "1") (pinfunction "~{D}_1") (pintype "input"))
      (node (ref "DA7") (pin "8") (pinfunction "GND_8") (pintype "power_in"))
      (node (ref "DA8") (pin "1") (pinfunction "~{D}_1") (pintype "input"))
      (node (ref "DA8") (pin "8") (pinfunction "GND_8") (pintype "power_in"))
      (node (ref "DA9") (pin "1") (pinfunction "~{D}_1") (pintype "input"))
      (node (ref "DA9") (pin "8") (pinfunction "GND_8") (pintype "power_in"))
      (node (ref "DD1") (pin "10") (pinfunction "VSS_5_10") (pintype "power_in"))
      (node (ref "DD1") (pin "27") (pinfunction "VSS_4_27") (pintype "power_in"))
      (node (ref "DD1") (pin "49") (pinfunction "VSS_1_49") (pintype "power_in"))
      (node (ref "DD1") (pin "74") (pinfunction "VSS_2_74") (pintype "power_in"))
      (node (ref "DD1") (pin "99") (pinfunction "VSS_3_99") (pintype "power_in"))
      (node (ref "DD10") (pin "8") (pinfunction "GND_8") (pintype "power_in"))
      (node (ref "DD11") (pin "8") (pinfunction "GND_8") (pintype "power_in"))
      (node (ref "DD12") (pin "8") (pinfunction "GND_8") (pintype "power_in"))
      (node (ref "DD2") (pin "1") (pinfunction "A0_1") (pintype "input"))
      (node (ref "DD2") (pin "2") (pinfunction "A1_2") (pintype "input"))
      (node (ref "DD2") (pin "3") (pinfunction "A2_3") (pintype "input"))
      (node (ref "DD2") (pin "4") (pinfunction "GND_4") (pintype "power_in"))
      (node (ref "DD2") (pin "7") (pinfunction "WP_7") (pintype "input"))
      (node (ref "DD3") (pin "7") (pinfunction "GND_7") (pintype "power_in"))
      (node (ref "DD4") (pin "8") (pinfunction "GND_8") (pintype "power_in"))
      (node (ref "DD5") (pin "8") (pinfunction "GND_8") (pintype "power_in"))
      (node (ref "DD6") (pin "8") (pinfunction "GND_8") (pintype "power_in"))
      (node (ref "DD7") (pin "8") (pinfunction "GND_8") (pintype "power_in"))
      (node (ref "DD8") (pin "8") (pinfunction "GND_8") (pintype "power_in"))
      (node (ref "DD9") (pin "8") (pinfunction "GND_8") (pintype "power_in"))
      (node (ref "L3") (pin "2") (pinfunction "2_2") (pintype "passive"))
      (node (ref "R10") (pin "1") (pinfunction "1_1") (pintype "passive"))
      (node (ref "R100") (pin "1") (pinfunction "1_1") (pintype "passive"))
      (node (ref "R104") (pin "2") (pinfunction "2_2") (pintype "passive"))
      (node (ref "R105") (pin "2") (pinfunction "2_2") (pintype "passive"))
      (node (ref "R106") (pin "2") (pinfunction "2_2") (pintype "passive"))
      (node (ref "R128") (pin "1") (pinfunction "1_1") (pintype "passive"))
      (node (ref "R129") (pin "1") (pinfunction "1_1") (pintype "passive"))
      (node (ref "R13") (pin "1") (pinfunction "1_1") (pintype "passive"))
      (node (ref "R133") (pin "1") (pinfunction "1_1") (pintype "passive"))
      (node (ref "R14") (pin "1") (pinfunction "1_1") (pintype "passive"))
      (node (ref "R187") (pin "1") (pinfunction "1_1") (pintype "passive"))
      (node (ref "R188") (pin "1") (pinfunction "1_1") (pintype "passive"))
      (node (ref "R3") (pin "2") (pinfunction "2_2") (pintype "passive"))
      (node (ref "R342") (pin "1") (pinfunction "1_1") (pintype "passive"))
      (node (ref "R343") (pin "1") (pinfunction "1_1") (pintype "passive"))
      (node (ref "R344") (pin "1") (pinfunction "1_1") (pintype "passive"))
      (node (ref "R345") (pin "1") (pinfunction "1_1") (pintype "passive"))
      (node (ref "R346") (pin "1") (pinfunction "1_1") (pintype "passive"))
      (node (ref "R347") (pin "1") (pinfunction "1_1") (pintype "passive"))
      (node (ref "R348") (pin "1") (pinfunction "1_1") (pintype "passive"))
      (node (ref "R349") (pin "1") (pinfunction "1_1") (pintype "passive"))
      (node (ref "R360") (pin "1") (pinfunction "1_1") (pintype "passive"))
      (node (ref "R4") (pin "2") (pinfunction "2_2") (pintype "passive"))
      (node (ref "R5") (pin "2") (pinfunction "2_2") (pintype "passive"))
      (node (ref "R74") (pin "1") (pinfunction "1_1") (pintype "passive"))
      (node (ref "R75") (pin "1") (pinfunction "1_1") (pintype "passive"))
      (node (ref "R76") (pin "1") (pinfunction "1_1") (pintype "passive"))
      (node (ref "R86") (pin "2") (pinfunction "2_2") (pintype "passive"))
      (node (ref "R90") (pin "1") (pinfunction "1_1") (pintype "passive"))
      (node (ref "R91") (pin "2") (pinfunction "2_2") (pintype "passive"))
      (node (ref "R95") (pin "1") (pinfunction "1_1") (pintype "passive"))
      (node (ref "R96") (pin "2") (pinfunction "2_2") (pintype "passive"))
      (node (ref "SB1") (pin "1") (pinfunction "1_1") (pintype "passive"))
      (node (ref "SB1") (pin "2") (pinfunction "2_2") (pintype "passive"))
      (node (ref "VD10") (pin "A2") (pinfunction "A2_A2") (pintype "passive"))
      (node (ref "VD100") (pin "A") (pinfunction "A_A") (pintype "passive"))
      (node (ref "VD101") (pin "A") (pinfunction "A_A") (pintype "passive"))
      (node (ref "VD102") (pin "A") (pinfunction "A_A") (pintype "passive"))
      (node (ref "VD103") (pin "A") (pinfunction "A_A") (pintype "passive"))
      (node (ref "VD104") (pin "A") (pinfunction "A_A") (pintype "passive"))
      (node (ref "VD105") (pin "A") (pinfunction "A_A") (pintype "passive"))
      (node (ref "VD106") (pin "A") (pinfunction "A_A") (pintype "passive"))
      (node (ref "VD107") (pin "A") (pinfunction "A_A") (pintype "passive"))
      (node (ref "VD108") (pin "A") (pinfunction "A_A") (pintype "passive"))
      (node (ref "VD109") (pin "A") (pinfunction "A_A") (pintype "passive"))
      (node (ref "VD11") (pin "A2") (pinfunction "A2_A2") (pintype "passive"))
      (node (ref "VD110") (pin "A") (pinfunction "A_A") (pintype "passive"))
      (node (ref "VD111") (pin "A") (pinfunction "A_A") (pintype "passive"))
      (node (ref "VD112") (pin "A") (pinfunction "A_A") (pintype "passive"))
      (node (ref "VD113") (pin "A") (pinfunction "A_A") (pintype "passive"))
      (node (ref "VD114") (pin "A") (pinfunction "A_A") (pintype "passive"))
      (node (ref "VD115") (pin "A") (pinfunction "A_A") (pintype "passive"))
      (node (ref "VD132") (pin "A") (pinfunction "A_A") (pintype "passive"))
      (node (ref "VD133") (pin "A") (pinfunction "A_A") (pintype "passive"))
      (node (ref "VD134") (pin "A") (pinfunction "A_A") (pintype "passive"))
      (node (ref "VD135") (pin "A") (pinfunction "A_A") (pintype "passive"))
      (node (ref "VD136") (pin "A") (pinfunction "A_A") (pintype "passive"))
      (node (ref "VD137") (pin "A") (pinfunction "A_A") (pintype "passive"))
      (node (ref "VD138") (pin "A") (pinfunction "A_A") (pintype "passive"))
      (node (ref "VD139") (pin "A") (pinfunction "A_A") (pintype "passive"))
      (node (ref "VD140") (pin "A") (pinfunction "A_A") (pintype "passive"))
      (node (ref "VD141") (pin "A") (pinfunction "A_A") (pintype "passive"))
      (node (ref "VD142") (pin "A") (pinfunction "A_A") (pintype "passive"))
      (node (ref "VD143") (pin "A") (pinfunction "A_A") (pintype "passive"))
      (node (ref "VD144") (pin "A") (pinfunction "A_A") (pintype "passive"))
      (node (ref "VD145") (pin "A") (pinfunction "A_A") (pintype "passive"))
      (node (ref "VD146") (pin "A") (pinfunction "A_A") (pintype "passive"))
      (node (ref "VD147") (pin "A") (pinfunction "A_A") (pintype "passive"))
      (node (ref "VD164") (pin "A") (pinfunction "A_A") (pintype "passive"))
      (node (ref "VD165") (pin "A") (pinfunction "A_A") (pintype "passive"))
      (node (ref "VD166") (pin "A") (pinfunction "A_A") (pintype "passive"))
      (node (ref "VD167") (pin "A") (pinfunction "A_A") (pintype "passive"))
      (node (ref "VD168") (pin "A") (pinfunction "A_A") (pintype "passive"))
      (node (ref "VD169") (pin "A") (pinfunction "A_A") (pintype "passive"))
      (node (ref "VD170") (pin "A") (pinfunction "A_A") (pintype "passive"))
      (node (ref "VD171") (pin "A") (pinfunction "A_A") (pintype "passive"))
      (node (ref "VD172") (pin "A") (pinfunction "A_A") (pintype "passive"))
      (node (ref "VD173") (pin "A") (pinfunction "A_A") (pintype "passive"))
      (node (ref "VD174") (pin "A") (pinfunction "A_A") (pintype "passive"))
      (node (ref "VD175") (pin "A") (pinfunction "A_A") (pintype "passive"))
      (node (ref "VD176") (pin "A") (pinfunction "A_A") (pintype "passive"))
      (node (ref "VD177") (pin "A") (pinfunction "A_A") (pintype "passive"))
      (node (ref "VD178") (pin "A") (pinfunction "A_A") (pintype "passive"))
      (node (ref "VD179") (pin "A") (pinfunction "A_A") (pintype "passive"))
      (node (ref "VD196") (pin "A") (pinfunction "A_A") (pintype "passive"))
      (node (ref "VD197") (pin "A") (pinfunction "A_A") (pintype "passive"))
      (node (ref "VD198") (pin "A") (pinfunction "A_A") (pintype "passive"))
      (node (ref "VD199") (pin "A") (pinfunction "A_A") (pintype "passive"))
      (node (ref "VD20") (pin "A2") (pinfunction "A2_A2") (pintype "passive"))
      (node (ref "VD200") (pin "A") (pinfunction "A_A") (pintype "passive"))
      (node (ref "VD201") (pin "A") (pinfunction "A_A") (pintype "passive"))
      (node (ref "VD202") (pin "A") (pinfunction "A_A") (pintype "passive"))
      (node (ref "VD203") (pin "A") (pinfunction "A_A") (pintype "passive"))
      (node (ref "VD21") (pin "A2") (pinfunction "A2_A2") (pintype "passive"))
      (node (ref "VD212") (pin "A1") (pinfunction "A1_A1") (pintype "passive"))
      (node (ref "VD213") (pin "A1") (pinfunction "A1_A1") (pintype "passive"))
      (node (ref "VD214") (pin "A") (pinfunction "A_A") (pintype "passive"))
      (node (ref "VD22") (pin "A2") (pinfunction "A2_A2") (pintype "passive"))
      (node (ref "VD23") (pin "A2") (pinfunction "A2_A2") (pintype "passive"))
      (node (ref "VD24") (pin "A2") (pinfunction "A2_A2") (pintype "passive"))
      (node (ref "VD25") (pin "A2") (pinfunction "A2_A2") (pintype "passive"))
      (node (ref "VD26") (pin "A2") (pinfunction "A2_A2") (pintype "passive"))
      (node (ref "VD27") (pin "A2") (pinfunction "A2_A2") (pintype "passive"))
      (node (ref "VD37") (pin "A") (pinfunction "A_A") (pintype "passive"))
      (node (ref "VD39") (pin "A") (pinfunction "A_A") (pintype "passive"))
      (node (ref "VD4") (pin "A2") (pinfunction "A2_A2") (pintype "passive"))
      (node (ref "VD41") (pin "A") (pinfunction "A_A") (pintype "passive"))
      (node (ref "VD42") (pin "A") (pinfunction "A_A") (pintype "passive"))
      (node (ref "VD44") (pin "A") (pinfunction "A_A") (pintype "passive"))
      (node (ref "VD46") (pin "A") (pinfunction "A_A") (pintype "passive"))
      (node (ref "VD48") (pin "A2") (pinfunction "A2_A2") (pintype "passive"))
      (node (ref "VD49") (pin "A2") (pinfunction "A2_A2") (pintype "passive"))
      (node (ref "VD5") (pin "A2") (pinfunction "A2_A2") (pintype "passive"))
      (node (ref "VD50") (pin "A") (pinfunction "A_A") (pintype "passive"))
      (node (ref "VD51") (pin "A") (pinfunction "A_A") (pintype "passive"))
      (node (ref "VD52") (pin "A") (pinfunction "A_A") (pintype "passive"))
      (node (ref "VD54") (pin "A1") (pinfunction "A1_A1") (pintype "passive"))
      (node (ref "VD55") (pin "A") (pinfunction "A_A") (pintype "passive"))
      (node (ref "VD57") (pin "A2") (pinfunction "A2_A2") (pintype "passive"))
      (node (ref "VD58") (pin "A") (pinfunction "A_A") (pintype "passive"))
      (node (ref "VD6") (pin "A2") (pinfunction "A2_A2") (pintype "passive"))
      (node (ref "VD63") (pin "A") (pinfunction "A_A") (pintype "passive"))
      (node (ref "VD64") (pin "C") (pinfunction "C_C") (pintype "passive"))
      (node (ref "VD65") (pin "A") (pinfunction "A_A") (pintype "passive"))
      (node (ref "VD66") (pin "A") (pinfunction "A_A") (pintype "passive"))
      (node (ref "VD67") (pin "A") (pinfunction "A_A") (pintype "passive"))
      (node (ref "VD68") (pin "A") (pinfunction "A_A") (pintype "passive"))
      (node (ref "VD69") (pin "A") (pinfunction "A_A") (pintype "passive"))
      (node (ref "VD7") (pin "A2") (pinfunction "A2_A2") (pintype "passive"))
      (node (ref "VD70") (pin "A") (pinfunction "A_A") (pintype "passive"))
      (node (ref "VD71") (pin "A") (pinfunction "A_A") (pintype "passive"))
      (node (ref "VD72") (pin "A") (pinfunction "A_A") (pintype "passive"))
      (node (ref "VD73") (pin "A") (pinfunction "A_A") (pintype "passive"))
      (node (ref "VD74") (pin "A") (pinfunction "A_A") (pintype "passive"))
      (node (ref "VD75") (pin "A") (pinfunction "A_A") (pintype "passive"))
      (node (ref "VD76") (pin "A") (pinfunction "A_A") (pintype "passive"))
      (node (ref "VD77") (pin "A") (pinfunction "A_A") (pintype "passive"))
      (node (ref "VD78") (pin "A") (pinfunction "A_A") (pintype "passive"))
      (node (ref "VD79") (pin "A") (pinfunction "A_A") (pintype "passive"))
      (node (ref "VD8") (pin "A2") (pinfunction "A2_A2") (pintype "passive"))
      (node (ref "VD80") (pin "A") (pinfunction "A_A") (pintype "passive"))
      (node (ref "VD81") (pin "A") (pinfunction "A_A") (pintype "passive"))
      (node (ref "VD9") (pin "A2") (pinfunction "A2_A2") (pintype "passive"))
      (node (ref "VD99") (pin "A") (pinfunction "A_A") (pintype "passive"))
      (node (ref "VT2") (pin "E") (pinfunction "E_E") (pintype "passive"))
      (node (ref "VT4") (pin "E") (pinfunction "E_E") (pintype "passive"))
      (node (ref "XP1") (pin "10") (pinfunction "10_10") (pintype "passive"))
      (node (ref "XP1") (pin "12") (pinfunction "12_12") (pintype "passive"))
      (node (ref "XP1") (pin "14") (pinfunction "14_14") (pintype "passive"))
      (node (ref "XP1") (pin "16") (pinfunction "16_16") (pintype "passive"))
      (node (ref "XP1") (pin "18") (pinfunction "18_18") (pintype "passive"))
      (node (ref "XP1") (pin "20") (pinfunction "20_20") (pintype "passive"))
      (node (ref "XP1") (pin "4") (pinfunction "4_4") (pintype "passive"))
      (node (ref "XP1") (pin "6") (pinfunction "6_6") (pintype "passive"))
      (node (ref "XP1") (pin "8") (pinfunction "8_8") (pintype "passive"))
      (node (ref "XP2") (pin "3") (pinfunction "3_3") (pintype "passive"))
      (node (ref "XP3") (pin "3") (pinfunction "3_3") (pintype "passive"))
      (node (ref "XP4") (pin "16") (pinfunction "16_16") (pintype "passive"))
      (node (ref "XP6") (pin "1") (pinfunction "1_1") (pintype "passive"))
      (node (ref "XP6") (pin "3") (pinfunction "3_3") (pintype "passive"))
      (node (ref "XP6") (pin "5") (pinfunction "5_5") (pintype "passive"))
      (node (ref "XP6") (pin "7") (pinfunction "7_7") (pintype "passive"))
      (node (ref "XS1") (pin "GND") (pinfunction "5_GND") (pintype "passive"))
      (node (ref "Z1") (pin "2") (pinfunction "2_2") (pintype "passive"))
      (node (ref "Z10") (pin "2") (pinfunction "2_2") (pintype "passive"))
      (node (ref "Z11") (pin "2") (pinfunction "2_2") (pintype "passive"))
      (node (ref "Z12") (pin "2") (pinfunction "2_2") (pintype "passive"))
      (node (ref "Z13") (pin "2") (pinfunction "2_2") (pintype "passive"))
      (node (ref "Z14") (pin "2") (pinfunction "2_2") (pintype "passive"))
      (node (ref "Z15") (pin "2") (pinfunction "2_2") (pintype "passive"))
      (node (ref "Z16") (pin "2") (pinfunction "2_2") (pintype "passive"))
      (node (ref "Z17") (pin "2") (pinfunction "2_2") (pintype "passive"))
      (node (ref "Z18") (pin "2") (pinfunction "2_2") (pintype "passive"))
      (node (ref "Z19") (pin "2") (pinfunction "2_2") (pintype "passive"))
      (node (ref "Z2") (pin "2") (pinfunction "2_2") (pintype "passive"))
      (node (ref "Z20") (pin "2") (pinfunction "2_2") (pintype "passive"))
      (node (ref "Z21") (pin "2") (pinfunction "2_2") (pintype "passive"))
      (node (ref "Z22") (pin "2") (pinfunction "2_2") (pintype "passive"))
      (node (ref "Z23") (pin "2") (pinfunction "2_2") (pintype "passive"))
      (node (ref "Z24") (pin "2") (pinfunction "2_2") (pintype "passive"))
      (node (ref "Z25") (pin "2") (pinfunction "2_2") (pintype "passive"))
      (node (ref "Z26") (pin "2") (pinfunction "2_2") (pintype "passive"))
      (node (ref "Z27") (pin "2") (pinfunction "2_2") (pintype "passive"))
      (node (ref "Z28") (pin "2") (pinfunction "2_2") (pintype "passive"))
      (node (ref "Z29") (pin "2") (pinfunction "2_2") (pintype "passive"))
      (node (ref "Z3") (pin "2") (pinfunction "2_2") (pintype "passive"))
      (node (ref "Z30") (pin "2") (pinfunction "2_2") (pintype "passive"))
      (node (ref "Z31") (pin "2") (pinfunction "2_2") (pintype "passive"))
      (node (ref "Z32") (pin "2") (pinfunction "2_2") (pintype "passive"))
      (node (ref "Z33") (pin "2") (pinfunction "2_2") (pintype "passive"))
      (node (ref "Z34") (pin "2") (pinfunction "2_2") (pintype "passive"))
      (node (ref "Z35") (pin "2") (pinfunction "2_2") (pintype "passive"))
      (node (ref "Z36") (pin "2") (pinfunction "2_2") (pintype "passive"))
      (node (ref "Z37") (pin "2") (pinfunction "2_2") (pintype "passive"))
      (node (ref "Z38") (pin "2") (pinfunction "2_2") (pintype "passive"))
      (node (ref "Z39") (pin "2") (pinfunction "2_2") (pintype "passive"))
      (node (ref "Z4") (pin "2") (pinfunction "2_2") (pintype "passive"))
      (node (ref "Z40") (pin "2") (pinfunction "2_2") (pintype "passive"))
      (node (ref "Z41") (pin "2") (pinfunction "2_2") (pintype "passive"))
      (node (ref "Z42") (pin "2") (pinfunction "2_2") (pintype "passive"))
      (node (ref "Z43") (pin "2") (pinfunction "2_2") (pintype "passive"))
      (node (ref "Z44") (pin "2") (pinfunction "2_2") (pintype "passive"))
      (node (ref "Z45") (pin "2") (pinfunction "2_2") (pintype "passive"))
      (node (ref "Z46") (pin "2") (pinfunction "2_2") (pintype "passive"))
      (node (ref "Z47") (pin "2") (pinfunction "2_2") (pintype "passive"))
      (node (ref "Z48") (pin "2") (pinfunction "2_2") (pintype "passive"))
      (node (ref "Z49") (pin "2") (pinfunction "2_2") (pintype "passive"))
      (node (ref "Z5") (pin "2") (pinfunction "2_2") (pintype "passive"))
      (node (ref "Z50") (pin "2") (pinfunction "2_2") (pintype "passive"))
      (node (ref "Z6") (pin "2") (pinfunction "2_2") (pintype "passive"))
      (node (ref "Z7") (pin "2") (pinfunction "2_2") (pintype "passive"))
      (node (ref "Z8") (pin "2") (pinfunction "2_2") (pintype "passive"))
      (node (ref "Z9") (pin "2") (pinfunction "2_2") (pintype "passive"))
    )
    (net (code "47") (name "JTCK") (class "Default")
      (node (ref "DD1") (pin "76") (pinfunction "JTCK/SWCLK(PA14)*_76") (pintype "bidirectional"))
      (node (ref "Z7") (pin "3") (pinfunction "3_3") (pintype "passive"))
    )
    (net (code "48") (name "JTDI") (class "Default")
      (node (ref "DD1") (pin "77") (pinfunction "JTDI(PA15/SPI3_NSS/I2S3_WS/TIM2_CH1_ETR/SPI1_NSS)*_77") (pintype "bidirectional"))
      (node (ref "Z6") (pin "3") (pinfunction "3_3") (pintype "passive"))
    )
    (net (code "49") (name "JTDO") (class "Default")
      (node (ref "DD1") (pin "89") (pinfunction "JTDO(PB3/SPI3_SCK/I2S3_CK/TRACEWO/TIM2_CH2/SPI1_SCK)*_89") (pintype "bidirectional"))
      (node (ref "Z4") (pin "3") (pinfunction "3_3") (pintype "passive"))
    )
    (net (code "50") (name "JTMS") (class "Default")
      (node (ref "DD1") (pin "72") (pinfunction "JTMS/SWDIO(PA13)*_72") (pintype "bidirectional"))
      (node (ref "Z3") (pin "3") (pinfunction "3_3") (pintype "passive"))
    )
    (net (code "51") (name "JTRST") (class "Default")
      (node (ref "DD1") (pin "90") (pinfunction "NJTRST(PB4/SPI3_MISO/TIM3_CH1/SPI1_MISO)*_90") (pintype "bidirectional"))
      (node (ref "Z2") (pin "3") (pinfunction "3_3") (pintype "passive"))
    )
    (net (code "52") (name "Net-(C10-Pad1)") (class "Default")
      (node (ref "C10") (pin "1") (pinfunction "1_1") (pintype "passive"))
      (node (ref "R9") (pin "1") (pinfunction "1_1") (pintype "passive"))
      (node (ref "SB1") (pin "3") (pinfunction "3_3") (pintype "passive"))
      (node (ref "SB1") (pin "4") (pinfunction "4_4") (pintype "passive"))
      (node (ref "XP1") (pin "15") (pinfunction "15_15") (pintype "passive"))
      (node (ref "Z8") (pin "1") (pinfunction "1_1") (pintype "passive"))
    )
    (net (code "53") (name "Net-(C12-Pad1)") (class "Default")
      (node (ref "C12") (pin "1") (pinfunction "1_1") (pintype "passive"))
      (node (ref "R34") (pin "2") (pinfunction "2_2") (pintype "passive"))
      (node (ref "R42") (pin "2") (pinfunction "2_2") (pintype "passive"))
      (node (ref "Z22") (pin "1") (pinfunction "1_1") (pintype "passive"))
    )
    (net (code "54") (name "Net-(C13-Pad1)") (class "Default")
      (node (ref "C13") (pin "1") (pinfunction "1_1") (pintype "passive"))
      (node (ref "R35") (pin "2") (pinfunction "2_2") (pintype "passive"))
      (node (ref "R43") (pin "2") (pinfunction "2_2") (pintype "passive"))
      (node (ref "Z23") (pin "1") (pinfunction "1_1") (pintype "passive"))
    )
    (net (code "55") (name "Net-(C14-Pad1)") (class "Default")
      (node (ref "C14") (pin "1") (pinfunction "1_1") (pintype "passive"))
      (node (ref "R36") (pin "2") (pinfunction "2_2") (pintype "passive"))
      (node (ref "R44") (pin "2") (pinfunction "2_2") (pintype "passive"))
      (node (ref "Z24") (pin "1") (pinfunction "1_1") (pintype "passive"))
    )
    (net (code "56") (name "Net-(C15-Pad1)") (class "Default")
      (node (ref "C15") (pin "1") (pinfunction "1_1") (pintype "passive"))
      (node (ref "R37") (pin "2") (pinfunction "2_2") (pintype "passive"))
      (node (ref "R45") (pin "2") (pinfunction "2_2") (pintype "passive"))
      (node (ref "Z25") (pin "1") (pinfunction "1_1") (pintype "passive"))
    )
    (net (code "57") (name "Net-(C16-Pad1)") (class "Default")
      (node (ref "C16") (pin "1") (pinfunction "1_1") (pintype "passive"))
      (node (ref "R38") (pin "2") (pinfunction "2_2") (pintype "passive"))
      (node (ref "R46") (pin "2") (pinfunction "2_2") (pintype "passive"))
      (node (ref "Z26") (pin "1") (pinfunction "1_1") (pintype "passive"))
    )
    (net (code "58") (name "Net-(C17-Pad1)") (class "Default")
      (node (ref "C17") (pin "1") (pinfunction "1_1") (pintype "passive"))
      (node (ref "R39") (pin "2") (pinfunction "2_2") (pintype "passive"))
      (node (ref "R47") (pin "2") (pinfunction "2_2") (pintype "passive"))
      (node (ref "Z27") (pin "1") (pinfunction "1_1") (pintype "passive"))
    )
    (net (code "59") (name "Net-(C18-Pad1)") (class "Default")
      (node (ref "C18") (pin "1") (pinfunction "1_1") (pintype "passive"))
      (node (ref "R40") (pin "2") (pinfunction "2_2") (pintype "passive"))
      (node (ref "R48") (pin "2") (pinfunction "2_2") (pintype "passive"))
      (node (ref "Z28") (pin "1") (pinfunction "1_1") (pintype "passive"))
    )
    (net (code "60") (name "Net-(C19-Pad1)") (class "Default")
      (node (ref "C19") (pin "1") (pinfunction "1_1") (pintype "passive"))
      (node (ref "R41") (pin "2") (pinfunction "2_2") (pintype "passive"))
      (node (ref "R49") (pin "2") (pinfunction "2_2") (pintype "passive"))
      (node (ref "Z29") (pin "1") (pinfunction "1_1") (pintype "passive"))
    )
    (net (code "61") (name "Net-(C20-Pad1)") (class "Default")
      (node (ref "C20") (pin "1") (pinfunction "1_1") (pintype "passive"))
      (node (ref "R58") (pin "2") (pinfunction "2_2") (pintype "passive"))
      (node (ref "R66") (pin "2") (pinfunction "2_2") (pintype "passive"))
      (node (ref "Z30") (pin "1") (pinfunction "1_1") (pintype "passive"))
    )
    (net (code "62") (name "Net-(C21-Pad1)") (class "Default")
      (node (ref "C21") (pin "1") (pinfunction "1_1") (pintype "passive"))
      (node (ref "R59") (pin "2") (pinfunction "2_2") (pintype "passive"))
      (node (ref "R67") (pin "2") (pinfunction "2_2") (pintype "passive"))
      (node (ref "Z31") (pin "1") (pinfunction "1_1") (pintype "passive"))
    )
    (net (code "63") (name "Net-(C22-Pad1)") (class "Default")
      (node (ref "C22") (pin "1") (pinfunction "1_1") (pintype "passive"))
      (node (ref "R60") (pin "2") (pinfunction "2_2") (pintype "passive"))
      (node (ref "R68") (pin "2") (pinfunction "2_2") (pintype "passive"))
      (node (ref "Z32") (pin "1") (pinfunction "1_1") (pintype "passive"))
    )
    (net (code "64") (name "Net-(C23-Pad1)") (class "Default")
      (node (ref "C23") (pin "1") (pinfunction "1_1") (pintype "passive"))
      (node (ref "R61") (pin "2") (pinfunction "2_2") (pintype "passive"))
      (node (ref "R69") (pin "2") (pinfunction "2_2") (pintype "passive"))
      (node (ref "Z33") (pin "1") (pinfunction "1_1") (pintype "passive"))
    )
    (net (code "65") (name "Net-(C24-Pad1)") (class "Default")
      (node (ref "C24") (pin "1") (pinfunction "1_1") (pintype "passive"))
      (node (ref "R62") (pin "2") (pinfunction "2_2") (pintype "passive"))
      (node (ref "R70") (pin "2") (pinfunction "2_2") (pintype "passive"))
      (node (ref "Z34") (pin "1") (pinfunction "1_1") (pintype "passive"))
    )
    (net (code "66") (name "Net-(C25-Pad1)") (class "Default")
      (node (ref "C25") (pin "1") (pinfunction "1_1") (pintype "passive"))
      (node (ref "R63") (pin "2") (pinfunction "2_2") (pintype "passive"))
      (node (ref "R71") (pin "2") (pinfunction "2_2") (pintype "passive"))
      (node (ref "Z35") (pin "1") (pinfunction "1_1") (pintype "passive"))
    )
    (net (code "67") (name "Net-(C26-Pad1)") (class "Default")
      (node (ref "C26") (pin "1") (pinfunction "1_1") (pintype "passive"))
      (node (ref "R64") (pin "2") (pinfunction "2_2") (pintype "passive"))
      (node (ref "R72") (pin "2") (pinfunction "2_2") (pintype "passive"))
      (node (ref "Z36") (pin "1") (pinfunction "1_1") (pintype "passive"))
    )
    (net (code "68") (name "Net-(C27-Pad1)") (class "Default")
      (node (ref "C27") (pin "1") (pinfunction "1_1") (pintype "passive"))
      (node (ref "R65") (pin "2") (pinfunction "2_2") (pintype "passive"))
      (node (ref "R73") (pin "2") (pinfunction "2_2") (pintype "passive"))
      (node (ref "Z37") (pin "1") (pinfunction "1_1") (pintype "passive"))
    )
    (net (code "69") (name "Net-(C53-Pad2)") (class "Default")
      (node (ref "C53") (pin "2") (pinfunction "2_2") (pintype "passive"))
      (node (ref "R124") (pin "1") (pinfunction "1_1") (pintype "passive"))
      (node (ref "R126") (pin "1") (pinfunction "1_1") (pintype "passive"))
      (node (ref "VD48") (pin "A1") (pinfunction "A1_A1") (pintype "passive"))
    )
    (net (code "70") (name "Net-(C54-Pad2)") (class "Default")
      (node (ref "C54") (pin "2") (pinfunction "2_2") (pintype "passive"))
      (node (ref "R125") (pin "1") (pinfunction "1_1") (pintype "passive"))
      (node (ref "R127") (pin "1") (pinfunction "1_1") (pintype "passive"))
      (node (ref "VD49") (pin "A1") (pinfunction "A1_A1") (pintype "passive"))
    )
    (net (code "71") (name "Net-(D1A-DA)") (class "Default")
      (node (ref "D1") (pin "1") (pinfunction "DA_1") (pintype "passive"))
      (node (ref "R138") (pin "2") (pinfunction "2_2") (pintype "passive"))
    )
    (net (code "72") (name "Net-(D1A-TC)") (class "Default")
      (node (ref "C69") (pin "1") (pinfunction "1_1") (pintype "passive"))
      (node (ref "D1") (pin "10") (pinfunction "TC_10") (pintype "bidirectional"))
      (node (ref "DD4") (pin "11") (pinfunction "A_11") (pintype "input"))
      (node (ref "R170") (pin "2") (pinfunction "2_2") (pintype "passive"))
    )
    (net (code "73") (name "Net-(D1B-DA)") (class "Default")
      (node (ref "D1") (pin "3") (pinfunction "DA_3") (pintype "passive"))
      (node (ref "R139") (pin "2") (pinfunction "2_2") (pintype "passive"))
    )
    (net (code "74") (name "Net-(D1B-TC)") (class "Default")
      (node (ref "C70") (pin "1") (pinfunction "1_1") (pintype "passive"))
      (node (ref "D1") (pin "12") (pinfunction "TC_12") (pintype "bidirectional"))
      (node (ref "DD4") (pin "12") (pinfunction "B_12") (pintype "input"))
      (node (ref "R171") (pin "2") (pinfunction "2_2") (pintype "passive"))
    )
    (net (code "75") (name "Net-(D1C-DA)") (class "Default")
      (node (ref "D1") (pin "5") (pinfunction "DA_5") (pintype "passive"))
      (node (ref "R140") (pin "2") (pinfunction "2_2") (pintype "passive"))
    )
    (net (code "76") (name "Net-(D1C-TC)") (class "Default")
      (node (ref "C71") (pin "1") (pinfunction "1_1") (pintype "passive"))
      (node (ref "D1") (pin "14") (pinfunction "TC_14") (pintype "bidirectional"))
      (node (ref "DD4") (pin "13") (pinfunction "C_13") (pintype "input"))
      (node (ref "R172") (pin "2") (pinfunction "2_2") (pintype "passive"))
    )
    (net (code "77") (name "Net-(D1D-DA)") (class "Default")
      (node (ref "D1") (pin "7") (pinfunction "DA_7") (pintype "passive"))
      (node (ref "R141") (pin "2") (pinfunction "2_2") (pintype "passive"))
    )
    (net (code "78") (name "Net-(D1D-TC)") (class "Default")
      (node (ref "C72") (pin "1") (pinfunction "1_1") (pintype "passive"))
      (node (ref "D1") (pin "16") (pinfunction "TC_16") (pintype "bidirectional"))
      (node (ref "DD4") (pin "14") (pinfunction "D_14") (pintype "input"))
      (node (ref "R173") (pin "2") (pinfunction "2_2") (pintype "passive"))
    )
    (net (code "79") (name "Net-(D2A-DA)") (class "Default")
      (node (ref "D2") (pin "1") (pinfunction "DA_1") (pintype "passive"))
      (node (ref "R142") (pin "2") (pinfunction "2_2") (pintype "passive"))
    )
    (net (code "80") (name "Net-(D2A-TC)") (class "Default")
      (node (ref "C73") (pin "1") (pinfunction "1_1") (pintype "passive"))
      (node (ref "D2") (pin "10") (pinfunction "TC_10") (pintype "bidirectional"))
      (node (ref "DD4") (pin "3") (pinfunction "E_3") (pintype "input"))
      (node (ref "R174") (pin "2") (pinfunction "2_2") (pintype "passive"))
    )
    (net (code "81") (name "Net-(D2B-DA)") (class "Default")
      (node (ref "D2") (pin "3") (pinfunction "DA_3") (pintype "passive"))
      (node (ref "R143") (pin "2") (pinfunction "2_2") (pintype "passive"))
    )
    (net (code "82") (name "Net-(D2B-TC)") (class "Default")
      (node (ref "C74") (pin "1") (pinfunction "1_1") (pintype "passive"))
      (node (ref "D2") (pin "12") (pinfunction "TC_12") (pintype "bidirectional"))
      (node (ref "DD4") (pin "4") (pinfunction "F_4") (pintype "input"))
      (node (ref "R175") (pin "2") (pinfunction "2_2") (pintype "passive"))
    )
    (net (code "83") (name "Net-(D2C-DA)") (class "Default")
      (node (ref "D2") (pin "5") (pinfunction "DA_5") (pintype "passive"))
      (node (ref "R144") (pin "2") (pinfunction "2_2") (pintype "passive"))
    )
    (net (code "84") (name "Net-(D2C-TC)") (class "Default")
      (node (ref "C75") (pin "1") (pinfunction "1_1") (pintype "passive"))
      (node (ref "D2") (pin "14") (pinfunction "TC_14") (pintype "bidirectional"))
      (node (ref "DD4") (pin "5") (pinfunction "G_5") (pintype "input"))
      (node (ref "R176") (pin "2") (pinfunction "2_2") (pintype "passive"))
    )
    (net (code "85") (name "Net-(D2D-DA)") (class "Default")
      (node (ref "D2") (pin "7") (pinfunction "DA_7") (pintype "passive"))
      (node (ref "R145") (pin "2") (pinfunction "2_2") (pintype "passive"))
    )
    (net (code "86") (name "Net-(D2D-TC)") (class "Default")
      (node (ref "C76") (pin "1") (pinfunction "1_1") (pintype "passive"))
      (node (ref "D2") (pin "16") (pinfunction "TC_16") (pintype "bidirectional"))
      (node (ref "DD4") (pin "6") (pinfunction "H_6") (pintype "input"))
      (node (ref "R177") (pin "2") (pinfunction "2_2") (pintype "passive"))
    )
    (net (code "87") (name "Net-(D3A-DA)") (class "Default")
      (node (ref "D3") (pin "1") (pinfunction "DA_1") (pintype "passive"))
      (node (ref "R146") (pin "2") (pinfunction "2_2") (pintype "passive"))
    )
    (net (code "88") (name "Net-(D3A-TC)") (class "Default")
      (node (ref "C77") (pin "1") (pinfunction "1_1") (pintype "passive"))
      (node (ref "D3") (pin "10") (pinfunction "TC_10") (pintype "bidirectional"))
      (node (ref "DD5") (pin "11") (pinfunction "A_11") (pintype "input"))
      (node (ref "R178") (pin "2") (pinfunction "2_2") (pintype "passive"))
    )
    (net (code "89") (name "Net-(D3B-DA)") (class "Default")
      (node (ref "D3") (pin "3") (pinfunction "DA_3") (pintype "passive"))
      (node (ref "R147") (pin "2") (pinfunction "2_2") (pintype "passive"))
    )
    (net (code "90") (name "Net-(D3B-TC)") (class "Default")
      (node (ref "C78") (pin "1") (pinfunction "1_1") (pintype "passive"))
      (node (ref "D3") (pin "12") (pinfunction "TC_12") (pintype "bidirectional"))
      (node (ref "DD5") (pin "12") (pinfunction "B_12") (pintype "input"))
      (node (ref "R179") (pin "2") (pinfunction "2_2") (pintype "passive"))
    )
    (net (code "91") (name "Net-(D3C-DA)") (class "Default")
      (node (ref "D3") (pin "5") (pinfunction "DA_5") (pintype "passive"))
      (node (ref "R148") (pin "2") (pinfunction "2_2") (pintype "passive"))
    )
    (net (code "92") (name "Net-(D3C-TC)") (class "Default")
      (node (ref "C79") (pin "1") (pinfunction "1_1") (pintype "passive"))
      (node (ref "D3") (pin "14") (pinfunction "TC_14") (pintype "bidirectional"))
      (node (ref "DD5") (pin "13") (pinfunction "C_13") (pintype "input"))
      (node (ref "R180") (pin "2") (pinfunction "2_2") (pintype "passive"))
    )
    (net (code "93") (name "Net-(D3D-DA)") (class "Default")
      (node (ref "D3") (pin "7") (pinfunction "DA_7") (pintype "passive"))
      (node (ref "R149") (pin "2") (pinfunction "2_2") (pintype "passive"))
    )
    (net (code "94") (name "Net-(D3D-TC)") (class "Default")
      (node (ref "C80") (pin "1") (pinfunction "1_1") (pintype "passive"))
      (node (ref "D3") (pin "16") (pinfunction "TC_16") (pintype "bidirectional"))
      (node (ref "DD5") (pin "14") (pinfunction "D_14") (pintype "input"))
      (node (ref "R181") (pin "2") (pinfunction "2_2") (pintype "passive"))
    )
    (net (code "95") (name "Net-(D4A-DA)") (class "Default")
      (node (ref "D4") (pin "1") (pinfunction "DA_1") (pintype "passive"))
      (node (ref "R150") (pin "2") (pinfunction "2_2") (pintype "passive"))
    )
    (net (code "96") (name "Net-(D4A-TC)") (class "Default")
      (node (ref "C81") (pin "1") (pinfunction "1_1") (pintype "passive"))
      (node (ref "D4") (pin "10") (pinfunction "TC_10") (pintype "bidirectional"))
      (node (ref "DD5") (pin "3") (pinfunction "E_3") (pintype "input"))
      (node (ref "R182") (pin "2") (pinfunction "2_2") (pintype "passive"))
    )
    (net (code "97") (name "Net-(D4B-DA)") (class "Default")
      (node (ref "D4") (pin "3") (pinfunction "DA_3") (pintype "passive"))
      (node (ref "R151") (pin "2") (pinfunction "2_2") (pintype "passive"))
    )
    (net (code "98") (name "Net-(D4B-TC)") (class "Default")
      (node (ref "C82") (pin "1") (pinfunction "1_1") (pintype "passive"))
      (node (ref "D4") (pin "12") (pinfunction "TC_12") (pintype "bidirectional"))
      (node (ref "DD5") (pin "4") (pinfunction "F_4") (pintype "input"))
      (node (ref "R183") (pin "2") (pinfunction "2_2") (pintype "passive"))
    )
    (net (code "99") (name "Net-(D4C-DA)") (class "Default")
      (node (ref "D4") (pin "5") (pinfunction "DA_5") (pintype "passive"))
      (node (ref "R152") (pin "2") (pinfunction "2_2") (pintype "passive"))
    )
    (net (code "100") (name "Net-(D4C-TC)") (class "Default")
      (node (ref "C83") (pin "1") (pinfunction "1_1") (pintype "passive"))
      (node (ref "D4") (pin "14") (pinfunction "TC_14") (pintype "bidirectional"))
      (node (ref "DD5") (pin "5") (pinfunction "G_5") (pintype "input"))
      (node (ref "R184") (pin "2") (pinfunction "2_2") (pintype "passive"))
    )
    (net (code "101") (name "Net-(D4D-DA)") (class "Default")
      (node (ref "D4") (pin "7") (pinfunction "DA_7") (pintype "passive"))
      (node (ref "R153") (pin "2") (pinfunction "2_2") (pintype "passive"))
    )
    (net (code "102") (name "Net-(D4D-TC)") (class "Default")
      (node (ref "C84") (pin "1") (pinfunction "1_1") (pintype "passive"))
      (node (ref "D4") (pin "16") (pinfunction "TC_16") (pintype "bidirectional"))
      (node (ref "DD5") (pin "6") (pinfunction "H_6") (pintype "input"))
      (node (ref "R185") (pin "2") (pinfunction "2_2") (pintype "passive"))
    )
    (net (code "103") (name "Net-(D5-IFB)") (class "Default")
      (node (ref "D5") (pin "2") (pinfunction "IFB_2") (pintype "output"))
      (node (ref "VD98") (pin "A") (pinfunction "A_A") (pintype "passive"))
    )
    (net (code "104") (name "Net-(D5-IN)") (class "Default")
      (node (ref "D5") (pin "1") (pinfunction "IN_1") (pintype "input"))
      (node (ref "R186") (pin "2") (pinfunction "2_2") (pintype "passive"))
    )
    (net (code "105") (name "Net-(D6A-DA)") (class "Default")
      (node (ref "D6") (pin "1") (pinfunction "DA_1") (pintype "passive"))
      (node (ref "R189") (pin "2") (pinfunction "2_2") (pintype "passive"))
    )
    (net (code "106") (name "Net-(D6A-TC)") (class "Default")
      (node (ref "C87") (pin "1") (pinfunction "1_1") (pintype "passive"))
      (node (ref "D6") (pin "10") (pinfunction "TC_10") (pintype "bidirectional"))
      (node (ref "DD6") (pin "11") (pinfunction "A_11") (pintype "input"))
      (node (ref "R221") (pin "2") (pinfunction "2_2") (pintype "passive"))
    )
    (net (code "107") (name "Net-(D6B-DA)") (class "Default")
      (node (ref "D6") (pin "3") (pinfunction "DA_3") (pintype "passive"))
      (node (ref "R190") (pin "2") (pinfunction "2_2") (pintype "passive"))
    )
    (net (code "108") (name "Net-(D6B-TC)") (class "Default")
      (node (ref "C88") (pin "1") (pinfunction "1_1") (pintype "passive"))
      (node (ref "D6") (pin "12") (pinfunction "TC_12") (pintype "bidirectional"))
      (node (ref "DD6") (pin "12") (pinfunction "B_12") (pintype "input"))
      (node (ref "R222") (pin "2") (pinfunction "2_2") (pintype "passive"))
    )
    (net (code "109") (name "Net-(D6C-DA)") (class "Default")
      (node (ref "D6") (pin "5") (pinfunction "DA_5") (pintype "passive"))
      (node (ref "R191") (pin "2") (pinfunction "2_2") (pintype "passive"))
    )
    (net (code "110") (name "Net-(D6C-TC)") (class "Default")
      (node (ref "C89") (pin "1") (pinfunction "1_1") (pintype "passive"))
      (node (ref "D6") (pin "14") (pinfunction "TC_14") (pintype "bidirectional"))
      (node (ref "DD6") (pin "13") (pinfunction "C_13") (pintype "input"))
      (node (ref "R223") (pin "2") (pinfunction "2_2") (pintype "passive"))
    )
    (net (code "111") (name "Net-(D6D-DA)") (class "Default")
      (node (ref "D6") (pin "7") (pinfunction "DA_7") (pintype "passive"))
      (node (ref "R192") (pin "2") (pinfunction "2_2") (pintype "passive"))
    )
    (net (code "112") (name "Net-(D6D-TC)") (class "Default")
      (node (ref "C90") (pin "1") (pinfunction "1_1") (pintype "passive"))
      (node (ref "D6") (pin "16") (pinfunction "TC_16") (pintype "bidirectional"))
      (node (ref "DD6") (pin "14") (pinfunction "D_14") (pintype "input"))
      (node (ref "R224") (pin "2") (pinfunction "2_2") (pintype "passive"))
    )
    (net (code "113") (name "Net-(D7A-DA)") (class "Default")
      (node (ref "D7") (pin "1") (pinfunction "DA_1") (pintype "passive"))
      (node (ref "R193") (pin "2") (pinfunction "2_2") (pintype "passive"))
    )
    (net (code "114") (name "Net-(D7A-TC)") (class "Default")
      (node (ref "C91") (pin "1") (pinfunction "1_1") (pintype "passive"))
      (node (ref "D7") (pin "10") (pinfunction "TC_10") (pintype "bidirectional"))
      (node (ref "DD6") (pin "3") (pinfunction "E_3") (pintype "input"))
      (node (ref "R225") (pin "2") (pinfunction "2_2") (pintype "passive"))
    )
    (net (code "115") (name "Net-(D7B-DA)") (class "Default")
      (node (ref "D7") (pin "3") (pinfunction "DA_3") (pintype "passive"))
      (node (ref "R194") (pin "2") (pinfunction "2_2") (pintype "passive"))
    )
    (net (code "116") (name "Net-(D7B-TC)") (class "Default")
      (node (ref "C92") (pin "1") (pinfunction "1_1") (pintype "passive"))
      (node (ref "D7") (pin "12") (pinfunction "TC_12") (pintype "bidirectional"))
      (node (ref "DD6") (pin "4") (pinfunction "F_4") (pintype "input"))
      (node (ref "R226") (pin "2") (pinfunction "2_2") (pintype "passive"))
    )
    (net (code "117") (name "Net-(D7C-DA)") (class "Default")
      (node (ref "D7") (pin "5") (pinfunction "DA_5") (pintype "passive"))
      (node (ref "R195") (pin "2") (pinfunction "2_2") (pintype "passive"))
    )
    (net (code "118") (name "Net-(D7C-TC)") (class "Default")
      (node (ref "C93") (pin "1") (pinfunction "1_1") (pintype "passive"))
      (node (ref "D7") (pin "14") (pinfunction "TC_14") (pintype "bidirectional"))
      (node (ref "DD6") (pin "5") (pinfunction "G_5") (pintype "input"))
      (node (ref "R227") (pin "2") (pinfunction "2_2") (pintype "passive"))
    )
    (net (code "119") (name "Net-(D7D-DA)") (class "Default")
      (node (ref "D7") (pin "7") (pinfunction "DA_7") (pintype "passive"))
      (node (ref "R196") (pin "2") (pinfunction "2_2") (pintype "passive"))
    )
    (net (code "120") (name "Net-(D7D-TC)") (class "Default")
      (node (ref "C94") (pin "1") (pinfunction "1_1") (pintype "passive"))
      (node (ref "D7") (pin "16") (pinfunction "TC_16") (pintype "bidirectional"))
      (node (ref "DD6") (pin "6") (pinfunction "H_6") (pintype "input"))
      (node (ref "R228") (pin "2") (pinfunction "2_2") (pintype "passive"))
    )
    (net (code "121") (name "Net-(D8A-DA)") (class "Default")
      (node (ref "D8") (pin "1") (pinfunction "DA_1") (pintype "passive"))
      (node (ref "R197") (pin "2") (pinfunction "2_2") (pintype "passive"))
    )
    (net (code "122") (name "Net-(D8A-TC)") (class "Default")
      (node (ref "C95") (pin "1") (pinfunction "1_1") (pintype "passive"))
      (node (ref "D8") (pin "10") (pinfunction "TC_10") (pintype "bidirectional"))
      (node (ref "DD7") (pin "11") (pinfunction "A_11") (pintype "input"))
      (node (ref "R229") (pin "2") (pinfunction "2_2") (pintype "passive"))
    )
    (net (code "123") (name "Net-(D8B-DA)") (class "Default")
      (node (ref "D8") (pin "3") (pinfunction "DA_3") (pintype "passive"))
      (node (ref "R198") (pin "2") (pinfunction "2_2") (pintype "passive"))
    )
    (net (code "124") (name "Net-(D8B-TC)") (class "Default")
      (node (ref "C96") (pin "1") (pinfunction "1_1") (pintype "passive"))
      (node (ref "D8") (pin "12") (pinfunction "TC_12") (pintype "bidirectional"))
      (node (ref "DD7") (pin "12") (pinfunction "B_12") (pintype "input"))
      (node (ref "R230") (pin "2") (pinfunction "2_2") (pintype "passive"))
    )
    (net (code "125") (name "Net-(D8C-DA)") (class "Default")
      (node (ref "D8") (pin "5") (pinfunction "DA_5") (pintype "passive"))
      (node (ref "R199") (pin "2") (pinfunction "2_2") (pintype "passive"))
    )
    (net (code "126") (name "Net-(D8C-TC)") (class "Default")
      (node (ref "C97") (pin "1") (pinfunction "1_1") (pintype "passive"))
      (node (ref "D8") (pin "14") (pinfunction "TC_14") (pintype "bidirectional"))
      (node (ref "DD7") (pin "13") (pinfunction "C_13") (pintype "input"))
      (node (ref "R231") (pin "2") (pinfunction "2_2") (pintype "passive"))
    )
    (net (code "127") (name "Net-(D8D-DA)") (class "Default")
      (node (ref "D8") (pin "7") (pinfunction "DA_7") (pintype "passive"))
      (node (ref "R200") (pin "2") (pinfunction "2_2") (pintype "passive"))
    )
    (net (code "128") (name "Net-(D8D-TC)") (class "Default")
      (node (ref "C98") (pin "1") (pinfunction "1_1") (pintype "passive"))
      (node (ref "D8") (pin "16") (pinfunction "TC_16") (pintype "bidirectional"))
      (node (ref "DD7") (pin "14") (pinfunction "D_14") (pintype "input"))
      (node (ref "R232") (pin "2") (pinfunction "2_2") (pintype "passive"))
    )
    (net (code "129") (name "Net-(D9A-DA)") (class "Default")
      (node (ref "D9") (pin "1") (pinfunction "DA_1") (pintype "passive"))
      (node (ref "R201") (pin "2") (pinfunction "2_2") (pintype "passive"))
    )
    (net (code "130") (name "Net-(D9A-TC)") (class "Default")
      (node (ref "C99") (pin "1") (pinfunction "1_1") (pintype "passive"))
      (node (ref "D9") (pin "10") (pinfunction "TC_10") (pintype "bidirectional"))
      (node (ref "DD7") (pin "3") (pinfunction "E_3") (pintype "input"))
      (node (ref "R233") (pin "2") (pinfunction "2_2") (pintype "passive"))
    )
    (net (code "131") (name "Net-(D9B-DA)") (class "Default")
      (node (ref "D9") (pin "3") (pinfunction "DA_3") (pintype "passive"))
      (node (ref "R202") (pin "2") (pinfunction "2_2") (pintype "passive"))
    )
    (net (code "132") (name "Net-(D9B-TC)") (class "Default")
      (node (ref "C100") (pin "1") (pinfunction "1_1") (pintype "passive"))
      (node (ref "D9") (pin "12") (pinfunction "TC_12") (pintype "bidirectional"))
      (node (ref "DD7") (pin "4") (pinfunction "F_4") (pintype "input"))
      (node (ref "R234") (pin "2") (pinfunction "2_2") (pintype "passive"))
    )
    (net (code "133") (name "Net-(D9C-DA)") (class "Default")
      (node (ref "D9") (pin "5") (pinfunction "DA_5") (pintype "passive"))
      (node (ref "R203") (pin "2") (pinfunction "2_2") (pintype "passive"))
    )
    (net (code "134") (name "Net-(D9C-TC)") (class "Default")
      (node (ref "C101") (pin "1") (pinfunction "1_1") (pintype "passive"))
      (node (ref "D9") (pin "14") (pinfunction "TC_14") (pintype "bidirectional"))
      (node (ref "DD7") (pin "5") (pinfunction "G_5") (pintype "input"))
      (node (ref "R235") (pin "2") (pinfunction "2_2") (pintype "passive"))
    )
    (net (code "135") (name "Net-(D9D-DA)") (class "Default")
      (node (ref "D9") (pin "7") (pinfunction "DA_7") (pintype "passive"))
      (node (ref "R204") (pin "2") (pinfunction "2_2") (pintype "passive"))
    )
    (net (code "136") (name "Net-(D9D-TC)") (class "Default")
      (node (ref "C102") (pin "1") (pinfunction "1_1") (pintype "passive"))
      (node (ref "D9") (pin "16") (pinfunction "TC_16") (pintype "bidirectional"))
      (node (ref "DD7") (pin "6") (pinfunction "H_6") (pintype "input"))
      (node (ref "R236") (pin "2") (pinfunction "2_2") (pintype "passive"))
    )
    (net (code "137") (name "Net-(D10A-DA)") (class "Default")
      (node (ref "D10") (pin "1") (pinfunction "DA_1") (pintype "passive"))
      (node (ref "R237") (pin "2") (pinfunction "2_2") (pintype "passive"))
    )
    (net (code "138") (name "Net-(D10A-TC)") (class "Default")
      (node (ref "C105") (pin "1") (pinfunction "1_1") (pintype "passive"))
      (node (ref "D10") (pin "10") (pinfunction "TC_10") (pintype "bidirectional"))
      (node (ref "DD8") (pin "11") (pinfunction "A_11") (pintype "input"))
      (node (ref "R269") (pin "2") (pinfunction "2_2") (pintype "passive"))
    )
    (net (code "139") (name "Net-(D10B-DA)") (class "Default")
      (node (ref "D10") (pin "3") (pinfunction "DA_3") (pintype "passive"))
      (node (ref "R238") (pin "2") (pinfunction "2_2") (pintype "passive"))
    )
    (net (code "140") (name "Net-(D10B-TC)") (class "Default")
      (node (ref "C106") (pin "1") (pinfunction "1_1") (pintype "passive"))
      (node (ref "D10") (pin "12") (pinfunction "TC_12") (pintype "bidirectional"))
      (node (ref "DD8") (pin "12") (pinfunction "B_12") (pintype "input"))
      (node (ref "R270") (pin "2") (pinfunction "2_2") (pintype "passive"))
    )
    (net (code "141") (name "Net-(D10C-DA)") (class "Default")
      (node (ref "D10") (pin "5") (pinfunction "DA_5") (pintype "passive"))
      (node (ref "R239") (pin "2") (pinfunction "2_2") (pintype "passive"))
    )
    (net (code "142") (name "Net-(D10C-TC)") (class "Default")
      (node (ref "C107") (pin "1") (pinfunction "1_1") (pintype "passive"))
      (node (ref "D10") (pin "14") (pinfunction "TC_14") (pintype "bidirectional"))
      (node (ref "DD8") (pin "13") (pinfunction "C_13") (pintype "input"))
      (node (ref "R271") (pin "2") (pinfunction "2_2") (pintype "passive"))
    )
    (net (code "143") (name "Net-(D10D-DA)") (class "Default")
      (node (ref "D10") (pin "7") (pinfunction "DA_7") (pintype "passive"))
      (node (ref "R240") (pin "2") (pinfunction "2_2") (pintype "passive"))
    )
    (net (code "144") (name "Net-(D10D-TC)") (class "Default")
      (node (ref "C108") (pin "1") (pinfunction "1_1") (pintype "passive"))
      (node (ref "D10") (pin "16") (pinfunction "TC_16") (pintype "bidirectional"))
      (node (ref "DD8") (pin "14") (pinfunction "D_14") (pintype "input"))
      (node (ref "R272") (pin "2") (pinfunction "2_2") (pintype "passive"))
    )
    (net (code "145") (name "Net-(D11A-DA)") (class "Default")
      (node (ref "D11") (pin "1") (pinfunction "DA_1") (pintype "passive"))
      (node (ref "R241") (pin "2") (pinfunction "2_2") (pintype "passive"))
    )
    (net (code "146") (name "Net-(D11A-TC)") (class "Default")
      (node (ref "C109") (pin "1") (pinfunction "1_1") (pintype "passive"))
      (node (ref "D11") (pin "10") (pinfunction "TC_10") (pintype "bidirectional"))
      (node (ref "DD8") (pin "3") (pinfunction "E_3") (pintype "input"))
      (node (ref "R273") (pin "2") (pinfunction "2_2") (pintype "passive"))
    )
    (net (code "147") (name "Net-(D11B-DA)") (class "Default")
      (node (ref "D11") (pin "3") (pinfunction "DA_3") (pintype "passive"))
      (node (ref "R242") (pin "2") (pinfunction "2_2") (pintype "passive"))
    )
    (net (code "148") (name "Net-(D11B-TC)") (class "Default")
      (node (ref "C110") (pin "1") (pinfunction "1_1") (pintype "passive"))
      (node (ref "D11") (pin "12") (pinfunction "TC_12") (pintype "bidirectional"))
      (node (ref "DD8") (pin "4") (pinfunction "F_4") (pintype "input"))
      (node (ref "R274") (pin "2") (pinfunction "2_2") (pintype "passive"))
    )
    (net (code "149") (name "Net-(D11C-DA)") (class "Default")
      (node (ref "D11") (pin "5") (pinfunction "DA_5") (pintype "passive"))
      (node (ref "R243") (pin "2") (pinfunction "2_2") (pintype "passive"))
    )
    (net (code "150") (name "Net-(D11C-TC)") (class "Default")
      (node (ref "C111") (pin "1") (pinfunction "1_1") (pintype "passive"))
      (node (ref "D11") (pin "14") (pinfunction "TC_14") (pintype "bidirectional"))
      (node (ref "DD8") (pin "5") (pinfunction "G_5") (pintype "input"))
      (node (ref "R275") (pin "2") (pinfunction "2_2") (pintype "passive"))
    )
    (net (code "151") (name "Net-(D11D-DA)") (class "Default")
      (node (ref "D11") (pin "7") (pinfunction "DA_7") (pintype "passive"))
      (node (ref "R244") (pin "2") (pinfunction "2_2") (pintype "passive"))
    )
    (net (code "152") (name "Net-(D11D-TC)") (class "Default")
      (node (ref "C112") (pin "1") (pinfunction "1_1") (pintype "passive"))
      (node (ref "D11") (pin "16") (pinfunction "TC_16") (pintype "bidirectional"))
      (node (ref "DD8") (pin "6") (pinfunction "H_6") (pintype "input"))
      (node (ref "R276") (pin "2") (pinfunction "2_2") (pintype "passive"))
    )
    (net (code "153") (name "Net-(D12A-DA)") (class "Default")
      (node (ref "D12") (pin "1") (pinfunction "DA_1") (pintype "passive"))
      (node (ref "R245") (pin "2") (pinfunction "2_2") (pintype "passive"))
    )
    (net (code "154") (name "Net-(D12A-TC)") (class "Default")
      (node (ref "C113") (pin "1") (pinfunction "1_1") (pintype "passive"))
      (node (ref "D12") (pin "10") (pinfunction "TC_10") (pintype "bidirectional"))
      (node (ref "DD9") (pin "11") (pinfunction "A_11") (pintype "input"))
      (node (ref "R277") (pin "2") (pinfunction "2_2") (pintype "passive"))
    )
    (net (code "155") (name "Net-(D12B-DA)") (class "Default")
      (node (ref "D12") (pin "3") (pinfunction "DA_3") (pintype "passive"))
      (node (ref "R246") (pin "2") (pinfunction "2_2") (pintype "passive"))
    )
    (net (code "156") (name "Net-(D12B-TC)") (class "Default")
      (node (ref "C114") (pin "1") (pinfunction "1_1") (pintype "passive"))
      (node (ref "D12") (pin "12") (pinfunction "TC_12") (pintype "bidirectional"))
      (node (ref "DD9") (pin "12") (pinfunction "B_12") (pintype "input"))
      (node (ref "R278") (pin "2") (pinfunction "2_2") (pintype "passive"))
    )
    (net (code "157") (name "Net-(D12C-DA)") (class "Default")
      (node (ref "D12") (pin "5") (pinfunction "DA_5") (pintype "passive"))
      (node (ref "R247") (pin "2") (pinfunction "2_2") (pintype "passive"))
    )
    (net (code "158") (name "Net-(D12C-TC)") (class "Default")
      (node (ref "C115") (pin "1") (pinfunction "1_1") (pintype "passive"))
      (node (ref "D12") (pin "14") (pinfunction "TC_14") (pintype "bidirectional"))
      (node (ref "DD9") (pin "13") (pinfunction "C_13") (pintype "input"))
      (node (ref "R279") (pin "2") (pinfunction "2_2") (pintype "passive"))
    )
    (net (code "159") (name "Net-(D12D-DA)") (class "Default")
      (node (ref "D12") (pin "7") (pinfunction "DA_7") (pintype "passive"))
      (node (ref "R248") (pin "2") (pinfunction "2_2") (pintype "passive"))
    )
    (net (code "160") (name "Net-(D12D-TC)") (class "Default")
      (node (ref "C116") (pin "1") (pinfunction "1_1") (pintype "passive"))
      (node (ref "D12") (pin "16") (pinfunction "TC_16") (pintype "bidirectional"))
      (node (ref "DD9") (pin "14") (pinfunction "D_14") (pintype "input"))
      (node (ref "R280") (pin "2") (pinfunction "2_2") (pintype "passive"))
    )
    (net (code "161") (name "Net-(D13A-DA)") (class "Default")
      (node (ref "D13") (pin "1") (pinfunction "DA_1") (pintype "passive"))
      (node (ref "R249") (pin "2") (pinfunction "2_2") (pintype "passive"))
    )
    (net (code "162") (name "Net-(D13A-TC)") (class "Default")
      (node (ref "C117") (pin "1") (pinfunction "1_1") (pintype "passive"))
      (node (ref "D13") (pin "10") (pinfunction "TC_10") (pintype "bidirectional"))
      (node (ref "DD9") (pin "3") (pinfunction "E_3") (pintype "input"))
      (node (ref "R281") (pin "2") (pinfunction "2_2") (pintype "passive"))
    )
    (net (code "163") (name "Net-(D13B-DA)") (class "Default")
      (node (ref "D13") (pin "3") (pinfunction "DA_3") (pintype "passive"))
      (node (ref "R250") (pin "2") (pinfunction "2_2") (pintype "passive"))
    )
    (net (code "164") (name "Net-(D13B-TC)") (class "Default")
      (node (ref "C118") (pin "1") (pinfunction "1_1") (pintype "passive"))
      (node (ref "D13") (pin "12") (pinfunction "TC_12") (pintype "bidirectional"))
      (node (ref "DD9") (pin "4") (pinfunction "F_4") (pintype "input"))
      (node (ref "R282") (pin "2") (pinfunction "2_2") (pintype "passive"))
    )
    (net (code "165") (name "Net-(D13C-DA)") (class "Default")
      (node (ref "D13") (pin "5") (pinfunction "DA_5") (pintype "passive"))
      (node (ref "R251") (pin "2") (pinfunction "2_2") (pintype "passive"))
    )
    (net (code "166") (name "Net-(D13C-TC)") (class "Default")
      (node (ref "C119") (pin "1") (pinfunction "1_1") (pintype "passive"))
      (node (ref "D13") (pin "14") (pinfunction "TC_14") (pintype "bidirectional"))
      (node (ref "DD9") (pin "5") (pinfunction "G_5") (pintype "input"))
      (node (ref "R283") (pin "2") (pinfunction "2_2") (pintype "passive"))
    )
    (net (code "167") (name "Net-(D13D-DA)") (class "Default")
      (node (ref "D13") (pin "7") (pinfunction "DA_7") (pintype "passive"))
      (node (ref "R252") (pin "2") (pinfunction "2_2") (pintype "passive"))
    )
    (net (code "168") (name "Net-(D13D-TC)") (class "Default")
      (node (ref "C120") (pin "1") (pinfunction "1_1") (pintype "passive"))
      (node (ref "D13") (pin "16") (pinfunction "TC_16") (pintype "bidirectional"))
      (node (ref "DD9") (pin "6") (pinfunction "H_6") (pintype "input"))
      (node (ref "R284") (pin "2") (pinfunction "2_2") (pintype "passive"))
    )
    (net (code "169") (name "Net-(D14A-DA)") (class "Default")
      (node (ref "D14") (pin "1") (pinfunction "DA_1") (pintype "passive"))
      (node (ref "R285") (pin "2") (pinfunction "2_2") (pintype "passive"))
    )
    (net (code "170") (name "Net-(D14A-TC)") (class "Default")
      (node (ref "C123") (pin "1") (pinfunction "1_1") (pintype "passive"))
      (node (ref "D14") (pin "10") (pinfunction "TC_10") (pintype "bidirectional"))
      (node (ref "DD10") (pin "11") (pinfunction "A_11") (pintype "input"))
      (node (ref "R317") (pin "2") (pinfunction "2_2") (pintype "passive"))
    )
    (net (code "171") (name "Net-(D14B-DA)") (class "Default")
      (node (ref "D14") (pin "3") (pinfunction "DA_3") (pintype "passive"))
      (node (ref "R286") (pin "2") (pinfunction "2_2") (pintype "passive"))
    )
    (net (code "172") (name "Net-(D14B-TC)") (class "Default")
      (node (ref "C124") (pin "1") (pinfunction "1_1") (pintype "passive"))
      (node (ref "D14") (pin "12") (pinfunction "TC_12") (pintype "bidirectional"))
      (node (ref "DD10") (pin "12") (pinfunction "B_12") (pintype "input"))
      (node (ref "R318") (pin "2") (pinfunction "2_2") (pintype "passive"))
    )
    (net (code "173") (name "Net-(D14C-DA)") (class "Default")
      (node (ref "D14") (pin "5") (pinfunction "DA_5") (pintype "passive"))
      (node (ref "R287") (pin "2") (pinfunction "2_2") (pintype "passive"))
    )
    (net (code "174") (name "Net-(D14C-TC)") (class "Default")
      (node (ref "C125") (pin "1") (pinfunction "1_1") (pintype "passive"))
      (node (ref "D14") (pin "14") (pinfunction "TC_14") (pintype "bidirectional"))
      (node (ref "DD10") (pin "13") (pinfunction "C_13") (pintype "input"))
      (node (ref "R319") (pin "2") (pinfunction "2_2") (pintype "passive"))
    )
    (net (code "175") (name "Net-(D14D-DA)") (class "Default")
      (node (ref "D14") (pin "7") (pinfunction "DA_7") (pintype "passive"))
      (node (ref "R288") (pin "2") (pinfunction "2_2") (pintype "passive"))
    )
    (net (code "176") (name "Net-(D14D-TC)") (class "Default")
      (node (ref "C126") (pin "1") (pinfunction "1_1") (pintype "passive"))
      (node (ref "D14") (pin "16") (pinfunction "TC_16") (pintype "bidirectional"))
      (node (ref "DD10") (pin "14") (pinfunction "D_14") (pintype "input"))
      (node (ref "R320") (pin "2") (pinfunction "2_2") (pintype "passive"))
    )
    (net (code "177") (name "Net-(D15A-DA)") (class "Default")
      (node (ref "D15") (pin "1") (pinfunction "DA_1") (pintype "passive"))
      (node (ref "R289") (pin "2") (pinfunction "2_2") (pintype "passive"))
    )
    (net (code "178") (name "Net-(D15A-TC)") (class "Default")
      (node (ref "C127") (pin "1") (pinfunction "1_1") (pintype "passive"))
      (node (ref "D15") (pin "10") (pinfunction "TC_10") (pintype "bidirectional"))
      (node (ref "DD10") (pin "3") (pinfunction "E_3") (pintype "input"))
      (node (ref "R321") (pin "2") (pinfunction "2_2") (pintype "passive"))
    )
    (net (code "179") (name "Net-(D15B-DA)") (class "Default")
      (node (ref "D15") (pin "3") (pinfunction "DA_3") (pintype "passive"))
      (node (ref "R290") (pin "2") (pinfunction "2_2") (pintype "passive"))
    )
    (net (code "180") (name "Net-(D15B-TC)") (class "Default")
      (node (ref "C128") (pin "1") (pinfunction "1_1") (pintype "passive"))
      (node (ref "D15") (pin "12") (pinfunction "TC_12") (pintype "bidirectional"))
      (node (ref "DD10") (pin "4") (pinfunction "F_4") (pintype "input"))
      (node (ref "R322") (pin "2") (pinfunction "2_2") (pintype "passive"))
    )
    (net (code "181") (name "Net-(D15C-DA)") (class "Default")
      (node (ref "D15") (pin "5") (pinfunction "DA_5") (pintype "passive"))
      (node (ref "R291") (pin "2") (pinfunction "2_2") (pintype "passive"))
    )
    (net (code "182") (name "Net-(D15C-TC)") (class "Default")
      (node (ref "C129") (pin "1") (pinfunction "1_1") (pintype "passive"))
      (node (ref "D15") (pin "14") (pinfunction "TC_14") (pintype "bidirectional"))
      (node (ref "DD10") (pin "5") (pinfunction "G_5") (pintype "input"))
      (node (ref "R323") (pin "2") (pinfunction "2_2") (pintype "passive"))
    )
    (net (code "183") (name "Net-(D15D-DA)") (class "Default")
      (node (ref "D15") (pin "7") (pinfunction "DA_7") (pintype "passive"))
      (node (ref "R292") (pin "2") (pinfunction "2_2") (pintype "passive"))
    )
    (net (code "184") (name "Net-(D15D-TC)") (class "Default")
      (node (ref "C130") (pin "1") (pinfunction "1_1") (pintype "passive"))
      (node (ref "D15") (pin "16") (pinfunction "TC_16") (pintype "bidirectional"))
      (node (ref "DD10") (pin "6") (pinfunction "H_6") (pintype "input"))
      (node (ref "R324") (pin "2") (pinfunction "2_2") (pintype "passive"))
    )
    (net (code "185") (name "Net-(D16A-DA)") (class "Default")
      (node (ref "D16") (pin "1") (pinfunction "DA_1") (pintype "passive"))
      (node (ref "R293") (pin "2") (pinfunction "2_2") (pintype "passive"))
    )
    (net (code "186") (name "Net-(D16A-TC)") (class "Default")
      (node (ref "C131") (pin "1") (pinfunction "1_1") (pintype "passive"))
      (node (ref "D16") (pin "10") (pinfunction "TC_10") (pintype "bidirectional"))
      (node (ref "DD11") (pin "11") (pinfunction "A_11") (pintype "input"))
      (node (ref "R325") (pin "2") (pinfunction "2_2") (pintype "passive"))
    )
    (net (code "187") (name "Net-(D16B-DA)") (class "Default")
      (node (ref "D16") (pin "3") (pinfunction "DA_3") (pintype "passive"))
      (node (ref "R294") (pin "2") (pinfunction "2_2") (pintype "passive"))
    )
    (net (code "188") (name "Net-(D16B-TC)") (class "Default")
      (node (ref "C132") (pin "1") (pinfunction "1_1") (pintype "passive"))
      (node (ref "D16") (pin "12") (pinfunction "TC_12") (pintype "bidirectional"))
      (node (ref "DD11") (pin "12") (pinfunction "B_12") (pintype "input"))
      (node (ref "R326") (pin "2") (pinfunction "2_2") (pintype "passive"))
    )
    (net (code "189") (name "Net-(D16C-DA)") (class "Default")
      (node (ref "D16") (pin "5") (pinfunction "DA_5") (pintype "passive"))
      (node (ref "R295") (pin "2") (pinfunction "2_2") (pintype "passive"))
    )
    (net (code "190") (name "Net-(D16C-TC)") (class "Default")
      (node (ref "C133") (pin "1") (pinfunction "1_1") (pintype "passive"))
      (node (ref "D16") (pin "14") (pinfunction "TC_14") (pintype "bidirectional"))
      (node (ref "DD11") (pin "13") (pinfunction "C_13") (pintype "input"))
      (node (ref "R327") (pin "2") (pinfunction "2_2") (pintype "passive"))
    )
    (net (code "191") (name "Net-(D16D-DA)") (class "Default")
      (node (ref "D16") (pin "7") (pinfunction "DA_7") (pintype "passive"))
      (node (ref "R296") (pin "2") (pinfunction "2_2") (pintype "passive"))
    )
    (net (code "192") (name "Net-(D16D-TC)") (class "Default")
      (node (ref "C134") (pin "1") (pinfunction "1_1") (pintype "passive"))
      (node (ref "D16") (pin "16") (pinfunction "TC_16") (pintype "bidirectional"))
      (node (ref "DD11") (pin "14") (pinfunction "D_14") (pintype "input"))
      (node (ref "R328") (pin "2") (pinfunction "2_2") (pintype "passive"))
    )
    (net (code "193") (name "Net-(D17A-DA)") (class "Default")
      (node (ref "D17") (pin "1") (pinfunction "DA_1") (pintype "passive"))
      (node (ref "R297") (pin "2") (pinfunction "2_2") (pintype "passive"))
    )
    (net (code "194") (name "Net-(D17A-TC)") (class "Default")
      (node (ref "C135") (pin "1") (pinfunction "1_1") (pintype "passive"))
      (node (ref "D17") (pin "10") (pinfunction "TC_10") (pintype "bidirectional"))
      (node (ref "DD11") (pin "3") (pinfunction "E_3") (pintype "input"))
      (node (ref "R329") (pin "2") (pinfunction "2_2") (pintype "passive"))
    )
    (net (code "195") (name "Net-(D17B-DA)") (class "Default")
      (node (ref "D17") (pin "3") (pinfunction "DA_3") (pintype "passive"))
      (node (ref "R298") (pin "2") (pinfunction "2_2") (pintype "passive"))
    )
    (net (code "196") (name "Net-(D17B-TC)") (class "Default")
      (node (ref "C136") (pin "1") (pinfunction "1_1") (pintype "passive"))
      (node (ref "D17") (pin "12") (pinfunction "TC_12") (pintype "bidirectional"))
      (node (ref "DD11") (pin "4") (pinfunction "F_4") (pintype "input"))
      (node (ref "R330") (pin "2") (pinfunction "2_2") (pintype "passive"))
    )
    (net (code "197") (name "Net-(D17C-DA)") (class "Default")
      (node (ref "D17") (pin "5") (pinfunction "DA_5") (pintype "passive"))
      (node (ref "R299") (pin "2") (pinfunction "2_2") (pintype "passive"))
    )
    (net (code "198") (name "Net-(D17C-TC)") (class "Default")
      (node (ref "C137") (pin "1") (pinfunction "1_1") (pintype "passive"))
      (node (ref "D17") (pin "14") (pinfunction "TC_14") (pintype "bidirectional"))
      (node (ref "DD11") (pin "5") (pinfunction "G_5") (pintype "input"))
      (node (ref "R331") (pin "2") (pinfunction "2_2") (pintype "passive"))
    )
    (net (code "199") (name "Net-(D17D-DA)") (class "Default")
      (node (ref "D17") (pin "7") (pinfunction "DA_7") (pintype "passive"))
      (node (ref "R300") (pin "2") (pinfunction "2_2") (pintype "passive"))
    )
    (net (code "200") (name "Net-(D17D-TC)") (class "Default")
      (node (ref "C138") (pin "1") (pinfunction "1_1") (pintype "passive"))
      (node (ref "D17") (pin "16") (pinfunction "TC_16") (pintype "bidirectional"))
      (node (ref "DD11") (pin "6") (pinfunction "H_6") (pintype "input"))
      (node (ref "R332") (pin "2") (pinfunction "2_2") (pintype "passive"))
    )
    (net (code "201") (name "Net-(D18A-DA)") (class "Default")
      (node (ref "D18") (pin "1") (pinfunction "DA_1") (pintype "passive"))
      (node (ref "R334") (pin "1") (pinfunction "1_1") (pintype "passive"))
    )
    (net (code "202") (name "Net-(D18A-TC)") (class "Default")
      (node (ref "D18") (pin "10") (pinfunction "TC_10") (pintype "bidirectional"))
      (node (ref "R350") (pin "1") (pinfunction "1_1") (pintype "passive"))
      (node (ref "VD196") (pin "C") (pinfunction "C_C") (pintype "passive"))
    )
    (net (code "203") (name "Net-(D18B-DA)") (class "Default")
      (node (ref "D18") (pin "3") (pinfunction "DA_3") (pintype "passive"))
      (node (ref "R335") (pin "1") (pinfunction "1_1") (pintype "passive"))
    )
    (net (code "204") (name "Net-(D18B-TC)") (class "Default")
      (node (ref "D18") (pin "12") (pinfunction "TC_12") (pintype "bidirectional"))
      (node (ref "R351") (pin "1") (pinfunction "1_1") (pintype "passive"))
      (node (ref "VD197") (pin "C") (pinfunction "C_C") (pintype "passive"))
    )
    (net (code "205") (name "Net-(D18C-DA)") (class "Default")
      (node (ref "D18") (pin "5") (pinfunction "DA_5") (pintype "passive"))
      (node (ref "R336") (pin "1") (pinfunction "1_1") (pintype "passive"))
    )
    (net (code "206") (name "Net-(D18C-TC)") (class "Default")
      (node (ref "D18") (pin "14") (pinfunction "TC_14") (pintype "bidirectional"))
      (node (ref "R352") (pin "1") (pinfunction "1_1") (pintype "passive"))
      (node (ref "VD198") (pin "C") (pinfunction "C_C") (pintype "passive"))
    )
    (net (code "207") (name "Net-(D18D-DA)") (class "Default")
      (node (ref "D18") (pin "7") (pinfunction "DA_7") (pintype "passive"))
      (node (ref "R337") (pin "1") (pinfunction "1_1") (pintype "passive"))
    )
    (net (code "208") (name "Net-(D18D-TC)") (class "Default")
      (node (ref "D18") (pin "16") (pinfunction "TC_16") (pintype "bidirectional"))
      (node (ref "R353") (pin "1") (pinfunction "1_1") (pintype "passive"))
      (node (ref "VD199") (pin "C") (pinfunction "C_C") (pintype "passive"))
    )
    (net (code "209") (name "Net-(D19A-DA)") (class "Default")
      (node (ref "D19") (pin "1") (pinfunction "DA_1") (pintype "passive"))
      (node (ref "R338") (pin "1") (pinfunction "1_1") (pintype "passive"))
    )
    (net (code "210") (name "Net-(D19A-TC)") (class "Default")
      (node (ref "D19") (pin "10") (pinfunction "TC_10") (pintype "bidirectional"))
      (node (ref "R354") (pin "1") (pinfunction "1_1") (pintype "passive"))
      (node (ref "VD200") (pin "C") (pinfunction "C_C") (pintype "passive"))
    )
    (net (code "211") (name "Net-(D19B-DA)") (class "Default")
      (node (ref "D19") (pin "3") (pinfunction "DA_3") (pintype "passive"))
      (node (ref "R339") (pin "1") (pinfunction "1_1") (pintype "passive"))
    )
    (net (code "212") (name "Net-(D19B-TC)") (class "Default")
      (node (ref "D19") (pin "12") (pinfunction "TC_12") (pintype "bidirectional"))
      (node (ref "R355") (pin "1") (pinfunction "1_1") (pintype "passive"))
      (node (ref "VD201") (pin "C") (pinfunction "C_C") (pintype "passive"))
    )
    (net (code "213") (name "Net-(D19C-DA)") (class "Default")
      (node (ref "D19") (pin "5") (pinfunction "DA_5") (pintype "passive"))
      (node (ref "R340") (pin "1") (pinfunction "1_1") (pintype "passive"))
    )
    (net (code "214") (name "Net-(D19C-TC)") (class "Default")
      (node (ref "D19") (pin "14") (pinfunction "TC_14") (pintype "bidirectional"))
      (node (ref "R356") (pin "1") (pinfunction "1_1") (pintype "passive"))
      (node (ref "VD202") (pin "C") (pinfunction "C_C") (pintype "passive"))
    )
    (net (code "215") (name "Net-(D19D-DA)") (class "Default")
      (node (ref "D19") (pin "7") (pinfunction "DA_7") (pintype "passive"))
      (node (ref "R341") (pin "1") (pinfunction "1_1") (pintype "passive"))
    )
    (net (code "216") (name "Net-(D19D-TC)") (class "Default")
      (node (ref "D19") (pin "16") (pinfunction "TC_16") (pintype "bidirectional"))
      (node (ref "R357") (pin "1") (pinfunction "1_1") (pintype "passive"))
      (node (ref "VD203") (pin "C") (pinfunction "C_C") (pintype "passive"))
    )
    (net (code "217") (name "Net-(D20-IFB)") (class "Default")
      (node (ref "D20") (pin "2") (pinfunction "IFB_2") (pintype "output"))
      (node (ref "VD204") (pin "A") (pinfunction "A_A") (pintype "passive"))
    )
    (net (code "218") (name "Net-(D20-IN)") (class "Default")
      (node (ref "D20") (pin "1") (pinfunction "IN_1") (pintype "input"))
      (node (ref "R350") (pin "2") (pinfunction "2_2") (pintype "passive"))
    )
    (net (code "219") (name "Net-(D21-IFB)") (class "Default")
      (node (ref "D21") (pin "2") (pinfunction "IFB_2") (pintype "output"))
      (node (ref "VD205") (pin "A") (pinfunction "A_A") (pintype "passive"))
    )
    (net (code "220") (name "Net-(D21-IN)") (class "Default")
      (node (ref "D21") (pin "1") (pinfunction "IN_1") (pintype "input"))
      (node (ref "R351") (pin "2") (pinfunction "2_2") (pintype "passive"))
    )
    (net (code "221") (name "Net-(D22-IFB)") (class "Default")
      (node (ref "D22") (pin "2") (pinfunction "IFB_2") (pintype "output"))
      (node (ref "VD206") (pin "A") (pinfunction "A_A") (pintype "passive"))
    )
    (net (code "222") (name "Net-(D22-IN)") (class "Default")
      (node (ref "D22") (pin "1") (pinfunction "IN_1") (pintype "input"))
      (node (ref "R352") (pin "2") (pinfunction "2_2") (pintype "passive"))
    )
    (net (code "223") (name "Net-(D23-IFB)") (class "Default")
      (node (ref "D23") (pin "2") (pinfunction "IFB_2") (pintype "output"))
      (node (ref "VD207") (pin "A") (pinfunction "A_A") (pintype "passive"))
    )
    (net (code "224") (name "Net-(D23-IN)") (class "Default")
      (node (ref "D23") (pin "1") (pinfunction "IN_1") (pintype "input"))
      (node (ref "R353") (pin "2") (pinfunction "2_2") (pintype "passive"))
    )
    (net (code "225") (name "Net-(D24-IFB)") (class "Default")
      (node (ref "D24") (pin "2") (pinfunction "IFB_2") (pintype "output"))
      (node (ref "VD208") (pin "A") (pinfunction "A_A") (pintype "passive"))
    )
    (net (code "226") (name "Net-(D24-IN)") (class "Default")
      (node (ref "D24") (pin "1") (pinfunction "IN_1") (pintype "input"))
      (node (ref "R354") (pin "2") (pinfunction "2_2") (pintype "passive"))
    )
    (net (code "227") (name "Net-(D25-IFB)") (class "Default")
      (node (ref "D25") (pin "2") (pinfunction "IFB_2") (pintype "output"))
      (node (ref "VD209") (pin "A") (pinfunction "A_A") (pintype "passive"))
    )
    (net (code "228") (name "Net-(D25-IN)") (class "Default")
      (node (ref "D25") (pin "1") (pinfunction "IN_1") (pintype "input"))
      (node (ref "R355") (pin "2") (pinfunction "2_2") (pintype "passive"))
    )
    (net (code "229") (name "Net-(D26-IFB)") (class "Default")
      (node (ref "D26") (pin "2") (pinfunction "IFB_2") (pintype "output"))
      (node (ref "VD210") (pin "A") (pinfunction "A_A") (pintype "passive"))
    )
    (net (code "230") (name "Net-(D26-IN)") (class "Default")
      (node (ref "D26") (pin "1") (pinfunction "IN_1") (pintype "input"))
      (node (ref "R356") (pin "2") (pinfunction "2_2") (pintype "passive"))
    )
    (net (code "231") (name "Net-(D27-IFB)") (class "Default")
      (node (ref "D27") (pin "2") (pinfunction "IFB_2") (pintype "output"))
      (node (ref "VD211") (pin "A") (pinfunction "A_A") (pintype "passive"))
    )
    (net (code "232") (name "Net-(D27-IN)") (class "Default")
      (node (ref "D27") (pin "1") (pinfunction "IN_1") (pintype "input"))
      (node (ref "R357") (pin "2") (pinfunction "2_2") (pintype "passive"))
    )
    (net (code "233") (name "Net-(DA1A-A)") (class "Default")
      (node (ref "DA1") (pin "3") (pinfunction "A_3") (pintype "input"))
      (node (ref "R80") (pin "2") (pinfunction "2_2") (pintype "passive"))
      (node (ref "VD43") (pin "A") (pinfunction "A_A") (pintype "passive"))
    )
    (net (code "234") (name "Net-(DA1A-B)") (class "Default")
      (node (ref "DA1") (pin "1") (pinfunction "B_1") (pintype "output"))
      (node (ref "R101") (pin "1") (pinfunction "1_1") (pintype "passive"))
      (node (ref "R86") (pin "1") (pinfunction "1_1") (pintype "passive"))
      (node (ref "R87") (pin "2") (pinfunction "2_2") (pintype "passive"))
    )
    (net (code "235") (name "Net-(DA1A-~{A})") (class "Default")
      (node (ref "DA1") (pin "2") (pinfunction "~{A}_2") (pintype "input"))
      (node (ref "R83") (pin "2") (pinfunction "2_2") (pintype "passive"))
    )
    (net (code "236") (name "Net-(DA1B-A)") (class "Default")
      (node (ref "DA1") (pin "5") (pinfunction "A_5") (pintype "input"))
      (node (ref "R77") (pin "2") (pinfunction "2_2") (pintype "passive"))
      (node (ref "VD36") (pin "A") (pinfunction "A_A") (pintype "passive"))
    )
    (net (code "237") (name "Net-(DA1B-B)") (class "Default")
      (node (ref "DA1") (pin "7") (pinfunction "B_7") (pintype "output"))
      (node (ref "R88") (pin "1") (pinfunction "1_1") (pintype "passive"))
      (node (ref "R89") (pin "2") (pinfunction "2_2") (pintype "passive"))
    )
    (net (code "238") (name "Net-(DA1B-~{A})") (class "Default")
      (node (ref "DA1") (pin "6") (pinfunction "~{A}_6") (pintype "input"))
      (node (ref "R83") (pin "1") (pinfunction "1_1") (pintype "passive"))
      (node (ref "R89") (pin "1") (pinfunction "1_1") (pintype "passive"))
      (node (ref "R90") (pin "2") (pinfunction "2_2") (pintype "passive"))
    )
    (net (code "239") (name "Net-(DA2A-A)") (class "Default")
      (node (ref "DA2") (pin "3") (pinfunction "A_3") (pintype "input"))
      (node (ref "R81") (pin "2") (pinfunction "2_2") (pintype "passive"))
      (node (ref "VD45") (pin "A") (pinfunction "A_A") (pintype "passive"))
    )
    (net (code "240") (name "Net-(DA2A-B)") (class "Default")
      (node (ref "DA2") (pin "1") (pinfunction "B_1") (pintype "output"))
      (node (ref "R102") (pin "1") (pinfunction "1_1") (pintype "passive"))
      (node (ref "R91") (pin "1") (pinfunction "1_1") (pintype "passive"))
      (node (ref "R92") (pin "2") (pinfunction "2_2") (pintype "passive"))
    )
    (net (code "241") (name "Net-(DA2A-~{A})") (class "Default")
      (node (ref "DA2") (pin "2") (pinfunction "~{A}_2") (pintype "input"))
      (node (ref "R84") (pin "2") (pinfunction "2_2") (pintype "passive"))
    )
    (net (code "242") (name "Net-(DA2B-A)") (class "Default")
      (node (ref "DA2") (pin "5") (pinfunction "A_5") (pintype "input"))
      (node (ref "R78") (pin "2") (pinfunction "2_2") (pintype "passive"))
      (node (ref "VD38") (pin "A") (pinfunction "A_A") (pintype "passive"))
    )
    (net (code "243") (name "Net-(DA2B-B)") (class "Default")
      (node (ref "DA2") (pin "7") (pinfunction "B_7") (pintype "output"))
      (node (ref "R93") (pin "1") (pinfunction "1_1") (pintype "passive"))
      (node (ref "R94") (pin "2") (pinfunction "2_2") (pintype "passive"))
    )
    (net (code "244") (name "Net-(DA2B-~{A})") (class "Default")
      (node (ref "DA2") (pin "6") (pinfunction "~{A}_6") (pintype "input"))
      (node (ref "R84") (pin "1") (pinfunction "1_1") (pintype "passive"))
      (node (ref "R94") (pin "1") (pinfunction "1_1") (pintype "passive"))
      (node (ref "R95") (pin "2") (pinfunction "2_2") (pintype "passive"))
    )
    (net (code "245") (name "Net-(DA3A-A)") (class "Default")
      (node (ref "DA3") (pin "3") (pinfunction "A_3") (pintype "input"))
      (node (ref "R82") (pin "2") (pinfunction "2_2") (pintype "passive"))
      (node (ref "VD47") (pin "A") (pinfunction "A_A") (pintype "passive"))
    )
    (net (code "246") (name "Net-(DA3A-B)") (class "Default")
      (node (ref "DA3") (pin "1") (pinfunction "B_1") (pintype "output"))
      (node (ref "R103") (pin "1") (pinfunction "1_1") (pintype "passive"))
      (node (ref "R96") (pin "1") (pinfunction "1_1") (pintype "passive"))
      (node (ref "R97") (pin "2") (pinfunction "2_2") (pintype "passive"))
    )
    (net (code "247") (name "Net-(DA3A-~{A})") (class "Default")
      (node (ref "DA3") (pin "2") (pinfunction "~{A}_2") (pintype "input"))
      (node (ref "R85") (pin "2") (pinfunction "2_2") (pintype "passive"))
    )
    (net (code "248") (name "Net-(DA3B-A)") (class "Default")
      (node (ref "DA3") (pin "5") (pinfunction "A_5") (pintype "input"))
      (node (ref "R79") (pin "2") (pinfunction "2_2") (pintype "passive"))
      (node (ref "VD40") (pin "A") (pinfunction "A_A") (pintype "passive"))
    )
    (net (code "249") (name "Net-(DA3B-B)") (class "Default")
      (node (ref "DA3") (pin "7") (pinfunction "B_7") (pintype "output"))
      (node (ref "R98") (pin "1") (pinfunction "1_1") (pintype "passive"))
      (node (ref "R99") (pin "2") (pinfunction "2_2") (pintype "passive"))
    )
    (net (code "250") (name "Net-(DA3B-~{A})") (class "Default")
      (node (ref "DA3") (pin "6") (pinfunction "~{A}_6") (pintype "input"))
      (node (ref "R100") (pin "2") (pinfunction "2_2") (pintype "passive"))
      (node (ref "R85") (pin "1") (pinfunction "1_1") (pintype "passive"))
      (node (ref "R99") (pin "1") (pinfunction "1_1") (pintype "passive"))
    )
    (net (code "251") (name "Net-(DA4A-C_OUT)") (class "Default")
      (node (ref "DA4") (pin "7") (pinfunction "C_OUT_7") (pintype "output"))
      (node (ref "DA7") (pin "2") (pinfunction "D_2") (pintype "input"))
      (node (ref "DA7") (pin "9") (pinfunction "~{D}_9") (pintype "input"))
      (node (ref "R107") (pin "2") (pinfunction "2_2") (pintype "passive"))
      (node (ref "R113") (pin "2") (pinfunction "2_2") (pintype "passive"))
    )
    (net (code "252") (name "Net-(DA4A-IN+)") (class "Default")
      (node (ref "C34") (pin "1") (pinfunction "1_1") (pintype "passive"))
      (node (ref "DA4") (pin "2") (pinfunction "IN+_2") (pintype "input"))
      (node (ref "R104") (pin "1") (pinfunction "1_1") (pintype "passive"))
      (node (ref "R107") (pin "1") (pinfunction "1_1") (pintype "passive"))
      (node (ref "R108") (pin "1") (pinfunction "1_1") (pintype "passive"))
    )
    (net (code "253") (name "Net-(DA4A-IN-)") (class "Default")
      (node (ref "C31") (pin "2") (pinfunction "2_2") (pintype "passive"))
      (node (ref "DA4") (pin "3") (pinfunction "IN-_3") (pintype "input"))
      (node (ref "R101") (pin "2") (pinfunction "2_2") (pintype "passive"))
    )
    (net (code "254") (name "Net-(DA5A-C_OUT)") (class "Default")
      (node (ref "DA5") (pin "7") (pinfunction "C_OUT_7") (pintype "output"))
      (node (ref "DA8") (pin "2") (pinfunction "D_2") (pintype "input"))
      (node (ref "DA8") (pin "9") (pinfunction "~{D}_9") (pintype "input"))
      (node (ref "R109") (pin "2") (pinfunction "2_2") (pintype "passive"))
      (node (ref "R114") (pin "2") (pinfunction "2_2") (pintype "passive"))
    )
    (net (code "255") (name "Net-(DA5A-IN+)") (class "Default")
      (node (ref "C35") (pin "1") (pinfunction "1_1") (pintype "passive"))
      (node (ref "DA5") (pin "2") (pinfunction "IN+_2") (pintype "input"))
      (node (ref "R105") (pin "1") (pinfunction "1_1") (pintype "passive"))
      (node (ref "R109") (pin "1") (pinfunction "1_1") (pintype "passive"))
      (node (ref "R110") (pin "1") (pinfunction "1_1") (pintype "passive"))
    )
    (net (code "256") (name "Net-(DA5A-IN-)") (class "Default")
      (node (ref "C32") (pin "2") (pinfunction "2_2") (pintype "passive"))
      (node (ref "DA5") (pin "3") (pinfunction "IN-_3") (pintype "input"))
      (node (ref "R102") (pin "2") (pinfunction "2_2") (pintype "passive"))
    )
    (net (code "257") (name "Net-(DA6A-C_OUT)") (class "Default")
      (node (ref "DA6") (pin "7") (pinfunction "C_OUT_7") (pintype "output"))
      (node (ref "DA9") (pin "2") (pinfunction "D_2") (pintype "input"))
      (node (ref "DA9") (pin "9") (pinfunction "~{D}_9") (pintype "input"))
      (node (ref "R111") (pin "2") (pinfunction "2_2") (pintype "passive"))
      (node (ref "R115") (pin "2") (pinfunction "2_2") (pintype "passive"))
    )
    (net (code "258") (name "Net-(DA6A-IN+)") (class "Default")
      (node (ref "C36") (pin "1") (pinfunction "1_1") (pintype "passive"))
      (node (ref "DA6") (pin "2") (pinfunction "IN+_2") (pintype "input"))
      (node (ref "R106") (pin "1") (pinfunction "1_1") (pintype "passive"))
      (node (ref "R111") (pin "1") (pinfunction "1_1") (pintype "passive"))
      (node (ref "R112") (pin "1") (pinfunction "1_1") (pintype "passive"))
    )
    (net (code "259") (name "Net-(DA6A-IN-)") (class "Default")
      (node (ref "C33") (pin "2") (pinfunction "2_2") (pintype "passive"))
      (node (ref "DA6") (pin "3") (pinfunction "IN-_3") (pintype "input"))
      (node (ref "R103") (pin "2") (pinfunction "2_2") (pintype "passive"))
    )
    (net (code "260") (name "Net-(DA7A-C)") (class "Default")
      (node (ref "C43") (pin "1") (pinfunction "1_1") (pintype "passive"))
      (node (ref "DA7") (pin "14") (pinfunction "C_14") (pintype "input"))
    )
    (net (code "261") (name "Net-(DA7A-R{slash}C)") (class "Default")
      (node (ref "C43") (pin "2") (pinfunction "2_2") (pintype "passive"))
      (node (ref "DA7") (pin "15") (pinfunction "R/C_15") (pintype "input"))
      (node (ref "R117") (pin "1") (pinfunction "1_1") (pintype "passive"))
    )
    (net (code "262") (name "Net-(DA7A-~{Q})") (class "Default")
      (node (ref "DA7") (pin "4") (pinfunction "~{Q}_4") (pintype "output"))
      (node (ref "DD3") (pin "1") (pinfunction "A_1") (pintype "input"))
    )
    (net (code "263") (name "Net-(DA7B-C)") (class "Default")
      (node (ref "C44") (pin "1") (pinfunction "1_1") (pintype "passive"))
      (node (ref "DA7") (pin "6") (pinfunction "C_6") (pintype "input"))
    )
    (net (code "264") (name "Net-(DA7B-R{slash}C)") (class "Default")
      (node (ref "C44") (pin "2") (pinfunction "2_2") (pintype "passive"))
      (node (ref "DA7") (pin "7") (pinfunction "R/C_7") (pintype "input"))
      (node (ref "R118") (pin "1") (pinfunction "1_1") (pintype "passive"))
    )
    (net (code "265") (name "Net-(DA7B-~{Q})") (class "Default")
      (node (ref "DA7") (pin "12") (pinfunction "~{Q}_12") (pintype "output"))
      (node (ref "DD3") (pin "2") (pinfunction "B_2") (pintype "input"))
    )
    (net (code "266") (name "Net-(DA8A-C)") (class "Default")
      (node (ref "C45") (pin "1") (pinfunction "1_1") (pintype "passive"))
      (node (ref "DA8") (pin "14") (pinfunction "C_14") (pintype "input"))
    )
    (net (code "267") (name "Net-(DA8A-R{slash}C)") (class "Default")
      (node (ref "C45") (pin "2") (pinfunction "2_2") (pintype "passive"))
      (node (ref "DA8") (pin "15") (pinfunction "R/C_15") (pintype "input"))
      (node (ref "R119") (pin "1") (pinfunction "1_1") (pintype "passive"))
    )
    (net (code "268") (name "Net-(DA8A-~{Q})") (class "Default")
      (node (ref "DA8") (pin "4") (pinfunction "~{Q}_4") (pintype "output"))
      (node (ref "DD3") (pin "3") (pinfunction "A_3") (pintype "input"))
    )
    (net (code "269") (name "Net-(DA8B-C)") (class "Default")
      (node (ref "C46") (pin "1") (pinfunction "1_1") (pintype "passive"))
      (node (ref "DA8") (pin "6") (pinfunction "C_6") (pintype "input"))
    )
    (net (code "270") (name "Net-(DA8B-R{slash}C)") (class "Default")
      (node (ref "C46") (pin "2") (pinfunction "2_2") (pintype "passive"))
      (node (ref "DA8") (pin "7") (pinfunction "R/C_7") (pintype "input"))
      (node (ref "R120") (pin "1") (pinfunction "1_1") (pintype "passive"))
    )
    (net (code "271") (name "Net-(DA8B-~{Q})") (class "Default")
      (node (ref "DA8") (pin "12") (pinfunction "~{Q}_12") (pintype "output"))
      (node (ref "DD3") (pin "4") (pinfunction "B_4") (pintype "input"))
    )
    (net (code "272") (name "Net-(DA9A-C)") (class "Default")
      (node (ref "C47") (pin "1") (pinfunction "1_1") (pintype "passive"))
      (node (ref "DA9") (pin "14") (pinfunction "C_14") (pintype "input"))
    )
    (net (code "273") (name "Net-(DA9A-R{slash}C)") (class "Default")
      (node (ref "C47") (pin "2") (pinfunction "2_2") (pintype "passive"))
      (node (ref "DA9") (pin "15") (pinfunction "R/C_15") (pintype "input"))
      (node (ref "R121") (pin "1") (pinfunction "1_1") (pintype "passive"))
    )
    (net (code "274") (name "Net-(DA9A-~{Q})") (class "Default")
      (node (ref "DA9") (pin "4") (pinfunction "~{Q}_4") (pintype "output"))
      (node (ref "DD3") (pin "5") (pinfunction "C_5") (pintype "input"))
    )
    (net (code "275") (name "Net-(DA9B-C)") (class "Default")
      (node (ref "C48") (pin "1") (pinfunction "1_1") (pintype "passive"))
      (node (ref "DA9") (pin "6") (pinfunction "C_6") (pintype "input"))
    )
    (net (code "276") (name "Net-(DA9B-R{slash}C)") (class "Default")
      (node (ref "C48") (pin "2") (pinfunction "2_2") (pintype "passive"))
      (node (ref "DA9") (pin "7") (pinfunction "R/C_7") (pintype "input"))
      (node (ref "R122") (pin "1") (pinfunction "1_1") (pintype "passive"))
    )
    (net (code "277") (name "Net-(DA9B-~{Q})") (class "Default")
      (node (ref "DA9") (pin "12") (pinfunction "~{Q}_12") (pintype "output"))
      (node (ref "DD3") (pin "13") (pinfunction "C_13") (pintype "input"))
    )
    (net (code "278") (name "Net-(DA10-CONT)") (class "Default")
      (node (ref "C55") (pin "1") (pinfunction "1_1") (pintype "passive"))
      (node (ref "DA10") (pin "5") (pinfunction "CONT_5") (pintype "input"))
    )
    (net (code "279") (name "Net-(DA10-DISCH)") (class "Default")
      (node (ref "C49") (pin "1") (pinfunction "1_1") (pintype "passive"))
      (node (ref "C51") (pin "1") (pinfunction "1_1") (pintype "passive"))
      (node (ref "DA10") (pin "6") (pinfunction "THRES_6") (pintype "input"))
      (node (ref "DA10") (pin "7") (pinfunction "DISCH_7") (pintype "input"))
      (node (ref "R123") (pin "1") (pinfunction "1_1") (pintype "passive"))
    )
    (net (code "280") (name "Net-(DA10-OUT)") (class "Default")
      (node (ref "DA10") (pin "3") (pinfunction "OUT_3") (pintype "output"))
      (node (ref "R130") (pin "1") (pinfunction "1_1") (pintype "passive"))
    )
    (net (code "281") (name "Net-(DA10-TRIG)") (class "Default")
      (node (ref "DA10") (pin "2") (pinfunction "TRIG_2") (pintype "input"))
      (node (ref "DD3") (pin "8") (pinfunction "Y_8") (pintype "output"))
    )
    (net (code "282") (name "Net-(DA11-DRN)") (class "Default")
      (node (ref "DA11") (pin "2") (pinfunction "DRN_2") (pintype "bidirectional"))
      (node (ref "R132") (pin "2") (pinfunction "2_2") (pintype "passive"))
      (node (ref "VD53") (pin "A2") (pinfunction "A2_A2") (pintype "passive"))
    )
    (net (code "283") (name "Net-(DA11-GATE)") (class "Default")
      (node (ref "DA11") (pin "4") (pinfunction "GATE_4") (pintype "output"))
      (node (ref "VT1") (pin "1") (pinfunction "G_1") (pintype "passive"))
    )
    (net (code "284") (name "Net-(DA11-IN)") (class "Default")
      (node (ref "DA11") (pin "7") (pinfunction "IN_7") (pintype "input"))
      (node (ref "R131") (pin "2") (pinfunction "2_2") (pintype "passive"))
      (node (ref "VD55") (pin "C") (pinfunction "C_C") (pintype "passive"))
    )
    (net (code "285") (name "Net-(DA11-SRC)") (class "Default")
      (node (ref "DA11") (pin "1") (pinfunction "SRC_1") (pintype "bidirectional"))
      (node (ref "R134") (pin "1") (pinfunction "1_1") (pintype "passive"))
    )
    (net (code "286") (name "Net-(DA11-VCC)") (class "Default")
      (node (ref "C63") (pin "1") (pinfunction "1_1") (pintype "passive"))
      (node (ref "DA11") (pin "5") (pinfunction "VCC_5") (pintype "power_in"))
      (node (ref "R135") (pin "1") (pinfunction "1_1") (pintype "passive"))
    )
    (net (code "287") (name "Net-(DA11-VT)") (class "Default")
      (node (ref "C62") (pin "1") (pinfunction "1_1") (pintype "passive"))
      (node (ref "DA11") (pin "8") (pinfunction "VT_8") (pintype "bidirectional"))
      (node (ref "R133") (pin "2") (pinfunction "2_2") (pintype "passive"))
    )
    (net (code "288") (name "Net-(DA12-FB)") (class "Default")
      (node (ref "C66") (pin "+") (pinfunction "+_+") (pintype "passive"))
      (node (ref "DA12") (pin "4") (pinfunction "FB_4") (pintype "input"))
      (node (ref "L2") (pin "2") (pinfunction "2_2") (pintype "passive"))
      (node (ref "RK2") (pin "1") (pinfunction "P$1_1") (pintype "passive"))
    )
    (net (code "289") (name "Net-(DA12-OUT)") (class "Default")
      (node (ref "DA12") (pin "2") (pinfunction "OUT_2") (pintype "output"))
      (node (ref "L2") (pin "1") (pinfunction "1_1") (pintype "passive"))
      (node (ref "VD58") (pin "C") (pinfunction "C_C") (pintype "passive"))
    )
    (net (code "290") (name "Net-(DA13-OUT)") (class "Default")
      (node (ref "DA13") (pin "2") (pinfunction "OUT_2") (pintype "output"))
      (node (ref "L3") (pin "1") (pinfunction "1_1") (pintype "passive"))
      (node (ref "VD59") (pin "C") (pinfunction "C_C") (pintype "passive"))
    )
    (net (code "291") (name "Net-(DA13-~{ON}{slash}OFF)") (class "Default")
      (node (ref "C58") (pin "1") (pinfunction "1_1") (pintype "passive"))
      (node (ref "C61") (pin "2") (pinfunction "2_2") (pintype "passive"))
      (node (ref "C67") (pin "-") (pinfunction "-_-") (pintype "passive"))
      (node (ref "DA13") (pin "3") (pinfunction "GND_3") (pintype "input"))
      (node (ref "DA13") (pin "5") (pinfunction "~{ON}/OFF_5") (pintype "input"))
      (node (ref "DA13") (pin "6") (pinfunction "GND_6") (pintype "input"))
      (node (ref "RK3") (pin "1") (pinfunction "P$1_1") (pintype "passive"))
      (node (ref "VD59") (pin "A") (pinfunction "A_A") (pintype "passive"))
    )
    (net (code "292") (name "Net-(DA14-IN)") (class "Default")
      (node (ref "C64") (pin "+") (pinfunction "+_+") (pintype "passive"))
      (node (ref "C65") (pin "1") (pinfunction "1_1") (pintype "passive"))
      (node (ref "DA14") (pin "3") (pinfunction "IN_3") (pintype "power_in"))
      (node (ref "RK1") (pin "2") (pinfunction "P$2_2") (pintype "passive"))
      (node (ref "VD60") (pin "C") (pinfunction "C_C") (pintype "passive"))
    )
    (net (code "293") (name "Net-(DA15-3.3V)") (class "Default")
      (node (ref "DA15") (pin "5") (pinfunction "3.3V_5") (pintype "power_in"))
      (node (ref "Z44") (pin "1") (pinfunction "1_1") (pintype "passive"))
    )
    (net (code "294") (name "Net-(DA15-D3)") (class "Default")
      (node (ref "DA15") (pin "4") (pinfunction "D3_4") (pintype "bidirectional"))
      (node (ref "Z43") (pin "1") (pinfunction "1_1") (pintype "passive"))
    )
    (net (code "295") (name "Net-(DA15-D4)") (class "Default")
      (node (ref "DA15") (pin "6") (pinfunction "D4_6") (pintype "bidirectional"))
      (node (ref "Z42") (pin "1") (pinfunction "1_1") (pintype "passive"))
    )
    (net (code "296") (name "Net-(DA16-CANH)") (class "Default")
      (node (ref "DA16") (pin "7") (pinfunction "CANH_7") (pintype "bidirectional"))
      (node (ref "XP12") (pin "2") (pinfunction "2_2") (pintype "passive"))
      (node (ref "XP13") (pin "1") (pinfunction "1_1") (pintype "passive"))
    )
    (net (code "297") (name "Net-(DA16-CANL)") (class "Default")
      (node (ref "DA16") (pin "6") (pinfunction "CANL_6") (pintype "bidirectional"))
      (node (ref "R358") (pin "2") (pinfunction "2_2") (pintype "passive"))
      (node (ref "XP12") (pin "1") (pinfunction "1_1") (pintype "passive"))
    )
    (net (code "298") (name "Net-(DA16-RXD)") (class "Default")
      (node (ref "DA16") (pin "4") (pinfunction "RXD_4") (pintype "output"))
      (node (ref "Z47") (pin "1") (pinfunction "1_1") (pintype "passive"))
    )
    (net (code "299") (name "Net-(DA16-TXD)") (class "Default")
      (node (ref "DA16") (pin "1") (pinfunction "TXD_1") (pintype "input"))
      (node (ref "Z50") (pin "1") (pinfunction "1_1") (pintype "passive"))
    )
    (net (code "300") (name "Net-(DA17-C1+)") (class "Default")
      (node (ref "C146") (pin "1") (pinfunction "1_1") (pintype "passive"))
      (node (ref "DA17") (pin "1") (pinfunction "C1+_1") (pintype "passive"))
    )
    (net (code "301") (name "Net-(DA17-C1-)") (class "Default")
      (node (ref "C146") (pin "2") (pinfunction "2_2") (pintype "passive"))
      (node (ref "DA17") (pin "3") (pinfunction "C1-_3") (pintype "passive"))
    )
    (net (code "302") (name "Net-(DA17-C2+)") (class "Default")
      (node (ref "C147") (pin "1") (pinfunction "1_1") (pintype "passive"))
      (node (ref "DA17") (pin "4") (pinfunction "C2+_4") (pintype "passive"))
    )
    (net (code "303") (name "Net-(DA17-C2-)") (class "Default")
      (node (ref "C147") (pin "2") (pinfunction "2_2") (pintype "passive"))
      (node (ref "DA17") (pin "5") (pinfunction "C2-_5") (pintype "passive"))
    )
    (net (code "304") (name "Net-(DA17-R2IN)") (class "Default")
      (node (ref "DA17") (pin "8") (pinfunction "R2IN_8") (pintype "input"))
      (node (ref "Z46") (pin "3") (pinfunction "3_3") (pintype "passive"))
    )
    (net (code "305") (name "Net-(DA17-T2OUT)") (class "Default")
      (node (ref "DA17") (pin "7") (pinfunction "T2OUT_7") (pintype "output"))
      (node (ref "Z45") (pin "3") (pinfunction "3_3") (pintype "passive"))
    )
    (net (code "306") (name "Net-(DA17-V+)") (class "Default")
      (node (ref "C143") (pin "1") (pinfunction "1_1") (pintype "passive"))
      (node (ref "DA17") (pin "2") (pinfunction "V+_2") (pintype "passive"))
    )
    (net (code "307") (name "Net-(DA17-V-)") (class "Default")
      (node (ref "C145") (pin "1") (pinfunction "1_1") (pintype "passive"))
      (node (ref "DA17") (pin "6") (pinfunction "V-_6") (pintype "passive"))
    )
    (net (code "308") (name "Net-(DD1-OSC_IN)") (class "Default")
      (node (ref "C3") (pin "1") (pinfunction "1_1") (pintype "passive"))
      (node (ref "DD1") (pin "12") (pinfunction "OSC_IN_12") (pintype "input"))
      (node (ref "ZQ1") (pin "2") (pinfunction "P$2_2") (pintype "bidirectional"))
    )
    (net (code "309") (name "Net-(DD1-OSC_OUT)") (class "Default")
      (node (ref "C4") (pin "1") (pinfunction "1_1") (pintype "passive"))
      (node (ref "DD1") (pin "13") (pinfunction "OSC_OUT_13") (pintype "output"))
      (node (ref "ZQ1") (pin "1") (pinfunction "P$1_1") (pintype "bidirectional"))
    )
    (net (code "310") (name "Net-(DD1-PB10(I2C2_SCL{slash}USART3_TX{slash}TIM2_CH3)*)") (class "Default")
      (node (ref "DD1") (pin "47") (pinfunction "PB10(I2C2_SCL/USART3_TX/TIM2_CH3)*_47") (pintype "bidirectional"))
      (node (ref "Z11") (pin "1") (pinfunction "1_1") (pintype "passive"))
    )
    (net (code "311") (name "Net-(DD1-PB11(I2C2_SDA{slash}USART3_RX{slash}TIM2_CH4)*)") (class "Default")
      (node (ref "DD1") (pin "48") (pinfunction "PB11(I2C2_SDA/USART3_RX/TIM2_CH4)*_48") (pintype "bidirectional"))
      (node (ref "Z17") (pin "1") (pinfunction "1_1") (pintype "passive"))
    )
    (net (code "312") (name "Net-(DD1-PB12(SPI2_NSS{slash}I2S2_WS{slash}I2C2_SMBA{slash}USART3_CK{slash}TIM1_BKIN)*)") (class "Default")
      (node (ref "DD1") (pin "51") (pinfunction "PB12(SPI2_NSS/I2S2_WS/I2C2_SMBA/USART3_CK/TIM1_BKIN)*_51") (pintype "bidirectional"))
      (node (ref "Z12") (pin "1") (pinfunction "1_1") (pintype "passive"))
    )
    (net (code "313") (name "Net-(DD1-PB13(SPI2_SCK{slash}I2S2_SCK{slash}USART3_CTS{slash}TIM1_CH1N)*)") (class "Default")
      (node (ref "DD1") (pin "52") (pinfunction "PB13(SPI2_SCK/I2S2_SCK/USART3_CTS/TIM1_CH1N)*_52") (pintype "bidirectional"))
      (node (ref "Z18") (pin "1") (pinfunction "1_1") (pintype "passive"))
    )
    (net (code "314") (name "Net-(DD1-PB14(SPI2_MISO{slash}USART3_RTS{slash}TIM1_CH2N)*)") (class "Default")
      (node (ref "DD1") (pin "53") (pinfunction "PB14(SPI2_MISO/USART3_RTS/TIM1_CH2N)*_53") (pintype "bidirectional"))
      (node (ref "Z13") (pin "1") (pinfunction "1_1") (pintype "passive"))
    )
    (net (code "315") (name "Net-(DD1-PB15(SPI2_MOSI{slash}I2S2_SD{slash}TIM1_CH3N)*)") (class "Default")
      (node (ref "DD1") (pin "54") (pinfunction "PB15(SPI2_MOSI/I2S2_SD/TIM1_CH3N)*_54") (pintype "bidirectional"))
      (node (ref "Z19") (pin "1") (pinfunction "1_1") (pintype "passive"))
    )
    (net (code "316") (name "Net-(DD1-PE0(TIM4_ETR{slash}FSMC_NBL0)*)") (class "Default")
      (node (ref "DD1") (pin "97") (pinfunction "PE0(TIM4_ETR/FSMC_NBL0)*_97") (pintype "bidirectional"))
      (node (ref "Z14") (pin "1") (pinfunction "1_1") (pintype "passive"))
    )
    (net (code "317") (name "Net-(DD1-PE2(TRACECK{slash}FSMC_A23)*)") (class "Default")
      (node (ref "DD1") (pin "1") (pinfunction "PE2(TRACECK/FSMC_A23)*_1") (pintype "bidirectional"))
      (node (ref "Z20") (pin "1") (pinfunction "1_1") (pintype "passive"))
    )
    (net (code "318") (name "Net-(DD1-PE3(TRACED0{slash}FSMC_A19)*)") (class "Default")
      (node (ref "DD1") (pin "2") (pinfunction "PE3(TRACED0/FSMC_A19)*_2") (pintype "bidirectional"))
      (node (ref "Z15") (pin "1") (pinfunction "1_1") (pintype "passive"))
    )
    (net (code "319") (name "Net-(DD1-PE4(TRACED1{slash}FSMC_A20)*)") (class "Default")
      (node (ref "DD1") (pin "3") (pinfunction "PE4(TRACED1/FSMC_A20)*_3") (pintype "bidirectional"))
      (node (ref "Z21") (pin "1") (pinfunction "1_1") (pintype "passive"))
    )
    (net (code "320") (name "Net-(DD1-PE5(TRACED2{slash}FSMC_A21)*)") (class "Default")
      (node (ref "DD1") (pin "4") (pinfunction "PE5(TRACED2/FSMC_A21)*_4") (pintype "bidirectional"))
      (node (ref "Z16") (pin "1") (pinfunction "1_1") (pintype "passive"))
    )
    (net (code "321") (name "Net-(DD1-VDD_A)") (class "Default")
      (node (ref "C7") (pin "1") (pinfunction "1_1") (pintype "passive"))
      (node (ref "DD1") (pin "21") (pinfunction "VREF+_21") (pintype "power_in"))
      (node (ref "DD1") (pin "22") (pinfunction "VDD_A_22") (pintype "power_in"))
      (node (ref "L1") (pin "2") (pinfunction "2_2") (pintype "passive"))
    )
    (net (code "322") (name "Net-(DD1-VREF-)") (class "Default")
      (node (ref "C7") (pin "2") (pinfunction "2_2") (pintype "passive"))
      (node (ref "DD1") (pin "19") (pinfunction "VSS_A_19") (pintype "power_in"))
      (node (ref "DD1") (pin "20") (pinfunction "VREF-_20") (pintype "power_in"))
      (node (ref "R10") (pin "2") (pinfunction "2_2") (pintype "passive"))
      (node (ref "Z5") (pin "1") (pinfunction "1_1") (pintype "passive"))
    )
    (net (code "323") (name "Net-(DD2-SCL)") (class "Default")
      (node (ref "DD2") (pin "6") (pinfunction "SCL_6") (pintype "open_collector"))
      (node (ref "R25") (pin "2") (pinfunction "2_2") (pintype "passive"))
      (node (ref "Z11") (pin "3") (pinfunction "3_3") (pintype "passive"))
    )
    (net (code "324") (name "Net-(DD2-SDA)") (class "Default")
      (node (ref "DD2") (pin "5") (pinfunction "SDA_5") (pintype "open_collector"))
      (node (ref "R15") (pin "2") (pinfunction "2_2") (pintype "passive"))
      (node (ref "Z17") (pin "3") (pinfunction "3_3") (pintype "passive"))
    )
    (net (code "325") (name "Net-(DD3A-Y)") (class "Default")
      (node (ref "DD3") (pin "12") (pinfunction "Y_12") (pintype "output"))
      (node (ref "DD3") (pin "9") (pinfunction "A_9") (pintype "input"))
    )
    (net (code "326") (name "Net-(DD3B-Y)") (class "Default")
      (node (ref "DD3") (pin "10") (pinfunction "B_10") (pintype "input"))
      (node (ref "DD3") (pin "11") (pinfunction "C_11") (pintype "input"))
      (node (ref "DD3") (pin "6") (pinfunction "Y_6") (pintype "output"))
    )
    (net (code "327") (name "Net-(DD4A-SER)") (class "Default")
      (node (ref "DD4") (pin "10") (pinfunction "SER_10") (pintype "input"))
      (node (ref "R188") (pin "2") (pinfunction "2_2") (pintype "passive"))
    )
    (net (code "328") (name "Net-(DD12A-QA)") (class "Default")
      (node (ref "DD12") (pin "15") (pinfunction "QA_15") (pintype "tri_state"))
      (node (ref "R334") (pin "2") (pinfunction "2_2") (pintype "passive"))
    )
    (net (code "329") (name "Net-(DD12A-QB)") (class "Default")
      (node (ref "DD12") (pin "1") (pinfunction "QB_1") (pintype "tri_state"))
      (node (ref "R335") (pin "2") (pinfunction "2_2") (pintype "passive"))
    )
    (net (code "330") (name "Net-(DD12A-QC)") (class "Default")
      (node (ref "DD12") (pin "2") (pinfunction "QC_2") (pintype "tri_state"))
      (node (ref "R336") (pin "2") (pinfunction "2_2") (pintype "passive"))
    )
    (net (code "331") (name "Net-(DD12A-QD)") (class "Default")
      (node (ref "DD12") (pin "3") (pinfunction "QD_3") (pintype "tri_state"))
      (node (ref "R337") (pin "2") (pinfunction "2_2") (pintype "passive"))
    )
    (net (code "332") (name "Net-(DD12A-QE)") (class "Default")
      (node (ref "DD12") (pin "4") (pinfunction "QE_4") (pintype "tri_state"))
      (node (ref "R338") (pin "2") (pinfunction "2_2") (pintype "passive"))
    )
    (net (code "333") (name "Net-(DD12A-QF)") (class "Default")
      (node (ref "DD12") (pin "5") (pinfunction "QF_5") (pintype "tri_state"))
      (node (ref "R339") (pin "2") (pinfunction "2_2") (pintype "passive"))
    )
    (net (code "334") (name "Net-(DD12A-QG)") (class "Default")
      (node (ref "DD12") (pin "6") (pinfunction "QG_6") (pintype "tri_state"))
      (node (ref "R340") (pin "2") (pinfunction "2_2") (pintype "passive"))
    )
    (net (code "335") (name "Net-(DD12A-QH)") (class "Default")
      (node (ref "DD12") (pin "7") (pinfunction "QH_7") (pintype "tri_state"))
      (node (ref "R341") (pin "2") (pinfunction "2_2") (pintype "passive"))
    )
    (net (code "336") (name "Net-(R1-Pad1)") (class "Default")
      (node (ref "R1") (pin "1") (pinfunction "1_1") (pintype "passive"))
      (node (ref "XP1") (pin "3") (pinfunction "3_3") (pintype "passive"))
      (node (ref "Z2") (pin "1") (pinfunction "1_1") (pintype "passive"))
    )
    (net (code "337") (name "Net-(R2-Pad1)") (class "Default")
      (node (ref "R2") (pin "1") (pinfunction "1_1") (pintype "passive"))
      (node (ref "XP1") (pin "5") (pinfunction "5_5") (pintype "passive"))
      (node (ref "Z6") (pin "1") (pinfunction "1_1") (pintype "passive"))
    )
    (net (code "338") (name "Net-(R3-Pad1)") (class "Default")
      (node (ref "R3") (pin "1") (pinfunction "1_1") (pintype "passive"))
      (node (ref "XP1") (pin "11") (pinfunction "11_11") (pintype "passive"))
    )
    (net (code "339") (name "Net-(R4-Pad1)") (class "Default")
      (node (ref "R4") (pin "1") (pinfunction "1_1") (pintype "passive"))
      (node (ref "XP1") (pin "17") (pinfunction "17_17") (pintype "passive"))
    )
    (net (code "340") (name "Net-(R5-Pad1)") (class "Default")
      (node (ref "R5") (pin "1") (pinfunction "1_1") (pintype "passive"))
      (node (ref "XP1") (pin "19") (pinfunction "19_19") (pintype "passive"))
    )
    (net (code "341") (name "Net-(R6-Pad1)") (class "Default")
      (node (ref "R6") (pin "1") (pinfunction "1_1") (pintype "passive"))
      (node (ref "XP1") (pin "7") (pinfunction "7_7") (pintype "passive"))
      (node (ref "Z3") (pin "1") (pinfunction "1_1") (pintype "passive"))
    )
    (net (code "342") (name "Net-(R7-Pad1)") (class "Default")
      (node (ref "R7") (pin "1") (pinfunction "1_1") (pintype "passive"))
      (node (ref "XP1") (pin "9") (pinfunction "9_9") (pintype "passive"))
      (node (ref "Z7") (pin "1") (pinfunction "1_1") (pintype "passive"))
    )
    (net (code "343") (name "Net-(R8-Pad1)") (class "Default")
      (node (ref "R8") (pin "1") (pinfunction "1_1") (pintype "passive"))
      (node (ref "XP1") (pin "13") (pinfunction "13_13") (pintype "passive"))
      (node (ref "Z4") (pin "1") (pinfunction "1_1") (pintype "passive"))
    )
    (net (code "344") (name "Net-(R11-Pad1)") (class "Default")
      (node (ref "R11") (pin "1") (pinfunction "1_1") (pintype "passive"))
      (node (ref "Z9") (pin "3") (pinfunction "3_3") (pintype "passive"))
    )
    (net (code "345") (name "Net-(R11-Pad2)") (class "Default")
      (node (ref "R11") (pin "2") (pinfunction "2_2") (pintype "passive"))
      (node (ref "VD1") (pin "A") (pinfunction "A_A") (pintype "passive"))
      (node (ref "XP2") (pin "2") (pinfunction "2_2") (pintype "passive"))
    )
    (net (code "346") (name "Net-(R12-Pad1)") (class "Default")
      (node (ref "R12") (pin "1") (pinfunction "1_1") (pintype "passive"))
      (node (ref "Z10") (pin "3") (pinfunction "3_3") (pintype "passive"))
    )
    (net (code "347") (name "Net-(R12-Pad2)") (class "Default")
      (node (ref "R12") (pin "2") (pinfunction "2_2") (pintype "passive"))
      (node (ref "VD2") (pin "A") (pinfunction "A_A") (pintype "passive"))
      (node (ref "XP3") (pin "2") (pinfunction "2_2") (pintype "passive"))
    )
    (net (code "348") (name "Net-(R13-Pad2)") (class "Default")
      (node (ref "R13") (pin "2") (pinfunction "2_2") (pintype "passive"))
      (node (ref "VD1") (pin "C") (pinfunction "C_C") (pintype "passive"))
    )
    (net (code "349") (name "Net-(R14-Pad2)") (class "Default")
      (node (ref "R14") (pin "2") (pinfunction "2_2") (pintype "passive"))
      (node (ref "VD2") (pin "C") (pinfunction "C_C") (pintype "passive"))
    )
    (net (code "350") (name "Net-(R16-Pad2)") (class "Default")
      (node (ref "R16") (pin "2") (pinfunction "2_2") (pintype "passive"))
      (node (ref "Z12") (pin "3") (pinfunction "3_3") (pintype "passive"))
    )
    (net (code "351") (name "Net-(R17-Pad2)") (class "Default")
      (node (ref "R17") (pin "2") (pinfunction "2_2") (pintype "passive"))
      (node (ref "Z18") (pin "3") (pinfunction "3_3") (pintype "passive"))
    )
    (net (code "352") (name "Net-(R18-Pad2)") (class "Default")
      (node (ref "R18") (pin "2") (pinfunction "2_2") (pintype "passive"))
      (node (ref "Z13") (pin "3") (pinfunction "3_3") (pintype "passive"))
    )
    (net (code "353") (name "Net-(R19-Pad2)") (class "Default")
      (node (ref "R19") (pin "2") (pinfunction "2_2") (pintype "passive"))
      (node (ref "Z19") (pin "3") (pinfunction "3_3") (pintype "passive"))
    )
    (net (code "354") (name "Net-(R20-Pad1)") (class "Default")
      (node (ref "R20") (pin "1") (pinfunction "1_1") (pintype "passive"))
      (node (ref "Z14") (pin "3") (pinfunction "3_3") (pintype "passive"))
    )
    (net (code "355") (name "Net-(R20-Pad2)") (class "Default")
      (node (ref "R20") (pin "2") (pinfunction "2_2") (pintype "passive"))
      (node (ref "VD3") (pin "C") (pinfunction "C_C") (pintype "passive"))
    )
    (net (code "356") (name "Net-(R21-Pad2)") (class "Default")
      (node (ref "R21") (pin "2") (pinfunction "2_2") (pintype "passive"))
      (node (ref "Z20") (pin "3") (pinfunction "3_3") (pintype "passive"))
    )
    (net (code "357") (name "Net-(R22-Pad2)") (class "Default")
      (node (ref "R22") (pin "2") (pinfunction "2_2") (pintype "passive"))
      (node (ref "Z15") (pin "3") (pinfunction "3_3") (pintype "passive"))
    )
    (net (code "358") (name "Net-(R23-Pad2)") (class "Default")
      (node (ref "R23") (pin "2") (pinfunction "2_2") (pintype "passive"))
      (node (ref "Z21") (pin "3") (pinfunction "3_3") (pintype "passive"))
    )
    (net (code "359") (name "Net-(R24-Pad2)") (class "Default")
      (node (ref "R24") (pin "2") (pinfunction "2_2") (pintype "passive"))
      (node (ref "Z16") (pin "3") (pinfunction "3_3") (pintype "passive"))
    )
    (net (code "360") (name "Net-(R28-Pad2)") (class "Default")
      (node (ref "R28") (pin "2") (pinfunction "2_2") (pintype "passive"))
      (node (ref "VD14") (pin "A") (pinfunction "A_A") (pintype "passive"))
      (node (ref "VD6") (pin "A1") (pinfunction "A1_A1") (pintype "passive"))
    )
    (net (code "361") (name "Net-(R34-Pad1)") (class "Default")
      (node (ref "R34") (pin "1") (pinfunction "1_1") (pintype "passive"))
      (node (ref "VD12") (pin "C") (pinfunction "C_C") (pintype "passive"))
    )
    (net (code "362") (name "Net-(R35-Pad1)") (class "Default")
      (node (ref "R35") (pin "1") (pinfunction "1_1") (pintype "passive"))
      (node (ref "VD13") (pin "C") (pinfunction "C_C") (pintype "passive"))
    )
    (net (code "363") (name "Net-(R36-Pad1)") (class "Default")
      (node (ref "R36") (pin "1") (pinfunction "1_1") (pintype "passive"))
      (node (ref "VD14") (pin "C") (pinfunction "C_C") (pintype "passive"))
    )
    (net (code "364") (name "Net-(R37-Pad1)") (class "Default")
      (node (ref "R37") (pin "1") (pinfunction "1_1") (pintype "passive"))
      (node (ref "VD15") (pin "C") (pinfunction "C_C") (pintype "passive"))
    )
    (net (code "365") (name "Net-(R38-Pad1)") (class "Default")
      (node (ref "R38") (pin "1") (pinfunction "1_1") (pintype "passive"))
      (node (ref "VD16") (pin "C") (pinfunction "C_C") (pintype "passive"))
    )
    (net (code "366") (name "Net-(R39-Pad1)") (class "Default")
      (node (ref "R39") (pin "1") (pinfunction "1_1") (pintype "passive"))
      (node (ref "VD17") (pin "C") (pinfunction "C_C") (pintype "passive"))
    )
    (net (code "367") (name "Net-(R40-Pad1)") (class "Default")
      (node (ref "R40") (pin "1") (pinfunction "1_1") (pintype "passive"))
      (node (ref "VD18") (pin "C") (pinfunction "C_C") (pintype "passive"))
    )
    (net (code "368") (name "Net-(R41-Pad1)") (class "Default")
      (node (ref "R41") (pin "1") (pinfunction "1_1") (pintype "passive"))
      (node (ref "VD19") (pin "C") (pinfunction "C_C") (pintype "passive"))
    )
    (net (code "369") (name "Net-(R58-Pad1)") (class "Default")
      (node (ref "R58") (pin "1") (pinfunction "1_1") (pintype "passive"))
      (node (ref "VD28") (pin "C") (pinfunction "C_C") (pintype "passive"))
    )
    (net (code "370") (name "Net-(R59-Pad1)") (class "Default")
      (node (ref "R59") (pin "1") (pinfunction "1_1") (pintype "passive"))
      (node (ref "VD29") (pin "C") (pinfunction "C_C") (pintype "passive"))
    )
    (net (code "371") (name "Net-(R60-Pad1)") (class "Default")
      (node (ref "R60") (pin "1") (pinfunction "1_1") (pintype "passive"))
      (node (ref "VD30") (pin "C") (pinfunction "C_C") (pintype "passive"))
    )
    (net (code "372") (name "Net-(R61-Pad1)") (class "Default")
      (node (ref "R61") (pin "1") (pinfunction "1_1") (pintype "passive"))
      (node (ref "VD31") (pin "C") (pinfunction "C_C") (pintype "passive"))
    )
    (net (code "373") (name "Net-(R62-Pad1)") (class "Default")
      (node (ref "R62") (pin "1") (pinfunction "1_1") (pintype "passive"))
      (node (ref "VD32") (pin "C") (pinfunction "C_C") (pintype "passive"))
    )
    (net (code "374") (name "Net-(R63-Pad1)") (class "Default")
      (node (ref "R63") (pin "1") (pinfunction "1_1") (pintype "passive"))
      (node (ref "VD33") (pin "C") (pinfunction "C_C") (pintype "passive"))
    )
    (net (code "375") (name "Net-(R64-Pad1)") (class "Default")
      (node (ref "R64") (pin "1") (pinfunction "1_1") (pintype "passive"))
      (node (ref "VD34") (pin "C") (pinfunction "C_C") (pintype "passive"))
    )
    (net (code "376") (name "Net-(R65-Pad1)") (class "Default")
      (node (ref "R65") (pin "1") (pinfunction "1_1") (pintype "passive"))
      (node (ref "VD35") (pin "C") (pinfunction "C_C") (pintype "passive"))
    )
    (net (code "377") (name "Net-(R87-Pad1)") (class "Default")
      (node (ref "R87") (pin "1") (pinfunction "1_1") (pintype "passive"))
      (node (ref "R88") (pin "2") (pinfunction "2_2") (pintype "passive"))
    )
    (net (code "378") (name "Net-(R92-Pad1)") (class "Default")
      (node (ref "R92") (pin "1") (pinfunction "1_1") (pintype "passive"))
      (node (ref "R93") (pin "2") (pinfunction "2_2") (pintype "passive"))
    )
    (net (code "379") (name "Net-(R97-Pad1)") (class "Default")
      (node (ref "R97") (pin "1") (pinfunction "1_1") (pintype "passive"))
      (node (ref "R98") (pin "2") (pinfunction "2_2") (pintype "passive"))
    )
    (net (code "380") (name "Net-(R116-S)") (class "Default")
      (node (ref "R108") (pin "2") (pinfunction "2_2") (pintype "passive"))
      (node (ref "R110") (pin "2") (pinfunction "2_2") (pintype "passive"))
      (node (ref "R112") (pin "2") (pinfunction "2_2") (pintype "passive"))
      (node (ref "R116") (pin "2") (pinfunction "S_2") (pintype "passive"))
    )
    (net (code "381") (name "Net-(R126-Pad2)") (class "Default")
      (node (ref "R126") (pin "2") (pinfunction "2_2") (pintype "passive"))
      (node (ref "R128") (pin "2") (pinfunction "2_2") (pintype "passive"))
      (node (ref "VD51") (pin "C") (pinfunction "C_C") (pintype "passive"))
      (node (ref "Z38") (pin "1") (pinfunction "1_1") (pintype "passive"))
    )
    (net (code "382") (name "Net-(R127-Pad2)") (class "Default")
      (node (ref "R127") (pin "2") (pinfunction "2_2") (pintype "passive"))
      (node (ref "R129") (pin "2") (pinfunction "2_2") (pintype "passive"))
      (node (ref "VD52") (pin "C") (pinfunction "C_C") (pintype "passive"))
      (node (ref "Z39") (pin "1") (pinfunction "1_1") (pintype "passive"))
    )
    (net (code "383") (name "Net-(R130-Pad2)") (class "Default")
      (node (ref "R130") (pin "2") (pinfunction "2_2") (pintype "passive"))
      (node (ref "VD50") (pin "C") (pinfunction "C_C") (pintype "passive"))
      (node (ref "Z40") (pin "1") (pinfunction "1_1") (pintype "passive"))
    )
    (net (code "384") (name "Net-(R136-Pad2)") (class "Default")
      (node (ref "R136") (pin "2") (pinfunction "2_2") (pintype "passive"))
      (node (ref "VD64") (pin "A") (pinfunction "A_A") (pintype "passive"))
    )
    (net (code "385") (name "Net-(R137-Pad1)") (class "Default")
      (node (ref "R137") (pin "1") (pinfunction "1_1") (pintype "passive"))
      (node (ref "VD65") (pin "C") (pinfunction "C_C") (pintype "passive"))
    )
    (net (code "386") (name "Net-(R154-Pad2)") (class "Default")
      (node (ref "R154") (pin "2") (pinfunction "2_2") (pintype "passive"))
      (node (ref "VD82") (pin "C") (pinfunction "C_C") (pintype "passive"))
    )
    (net (code "387") (name "Net-(R155-Pad2)") (class "Default")
      (node (ref "R155") (pin "2") (pinfunction "2_2") (pintype "passive"))
      (node (ref "VD83") (pin "C") (pinfunction "C_C") (pintype "passive"))
    )
    (net (code "388") (name "Net-(R156-Pad2)") (class "Default")
      (node (ref "R156") (pin "2") (pinfunction "2_2") (pintype "passive"))
      (node (ref "VD84") (pin "C") (pinfunction "C_C") (pintype "passive"))
    )
    (net (code "389") (name "Net-(R157-Pad2)") (class "Default")
      (node (ref "R157") (pin "2") (pinfunction "2_2") (pintype "passive"))
      (node (ref "VD85") (pin "C") (pinfunction "C_C") (pintype "passive"))
    )
    (net (code "390") (name "Net-(R158-Pad2)") (class "Default")
      (node (ref "R158") (pin "2") (pinfunction "2_2") (pintype "passive"))
      (node (ref "VD86") (pin "C") (pinfunction "C_C") (pintype "passive"))
    )
    (net (code "391") (name "Net-(R159-Pad2)") (class "Default")
      (node (ref "R159") (pin "2") (pinfunction "2_2") (pintype "passive"))
      (node (ref "VD87") (pin "C") (pinfunction "C_C") (pintype "passive"))
    )
    (net (code "392") (name "Net-(R160-Pad2)") (class "Default")
      (node (ref "R160") (pin "2") (pinfunction "2_2") (pintype "passive"))
      (node (ref "VD88") (pin "C") (pinfunction "C_C") (pintype "passive"))
    )
    (net (code "393") (name "Net-(R161-Pad2)") (class "Default")
      (node (ref "R161") (pin "2") (pinfunction "2_2") (pintype "passive"))
      (node (ref "VD89") (pin "C") (pinfunction "C_C") (pintype "passive"))
    )
    (net (code "394") (name "Net-(R162-Pad2)") (class "Default")
      (node (ref "R162") (pin "2") (pinfunction "2_2") (pintype "passive"))
      (node (ref "VD90") (pin "C") (pinfunction "C_C") (pintype "passive"))
    )
    (net (code "395") (name "Net-(R163-Pad2)") (class "Default")
      (node (ref "R163") (pin "2") (pinfunction "2_2") (pintype "passive"))
      (node (ref "VD91") (pin "C") (pinfunction "C_C") (pintype "passive"))
    )
    (net (code "396") (name "Net-(R164-Pad2)") (class "Default")
      (node (ref "R164") (pin "2") (pinfunction "2_2") (pintype "passive"))
      (node (ref "VD92") (pin "C") (pinfunction "C_C") (pintype "passive"))
    )
    (net (code "397") (name "Net-(R165-Pad2)") (class "Default")
      (node (ref "R165") (pin "2") (pinfunction "2_2") (pintype "passive"))
      (node (ref "VD93") (pin "C") (pinfunction "C_C") (pintype "passive"))
    )
    (net (code "398") (name "Net-(R166-Pad2)") (class "Default")
      (node (ref "R166") (pin "2") (pinfunction "2_2") (pintype "passive"))
      (node (ref "VD94") (pin "C") (pinfunction "C_C") (pintype "passive"))
    )
    (net (code "399") (name "Net-(R167-Pad2)") (class "Default")
      (node (ref "R167") (pin "2") (pinfunction "2_2") (pintype "passive"))
      (node (ref "VD95") (pin "C") (pinfunction "C_C") (pintype "passive"))
    )
    (net (code "400") (name "Net-(R168-Pad2)") (class "Default")
      (node (ref "R168") (pin "2") (pinfunction "2_2") (pintype "passive"))
      (node (ref "VD96") (pin "C") (pinfunction "C_C") (pintype "passive"))
    )
    (net (code "401") (name "Net-(R169-Pad2)") (class "Default")
      (node (ref "R169") (pin "2") (pinfunction "2_2") (pintype "passive"))
      (node (ref "VD97") (pin "C") (pinfunction "C_C") (pintype "passive"))
    )
    (net (code "402") (name "Net-(R186-Pad1)") (class "Default")
      (node (ref "R186") (pin "1") (pinfunction "1_1") (pintype "passive"))
      (node (ref "VD99") (pin "C") (pinfunction "C_C") (pintype "passive"))
      (node (ref "VT2") (pin "C") (pinfunction "C_C") (pintype "passive"))
    )
    (net (code "403") (name "Net-(R187-Pad2)") (class "Default")
      (node (ref "R187") (pin "2") (pinfunction "2_2") (pintype "passive"))
      (node (ref "VD98") (pin "C") (pinfunction "C_C") (pintype "passive"))
    )
    (net (code "404") (name "Net-(R205-Pad2)") (class "Default")
      (node (ref "R205") (pin "2") (pinfunction "2_2") (pintype "passive"))
      (node (ref "VD116") (pin "C") (pinfunction "C_C") (pintype "passive"))
    )
    (net (code "405") (name "Net-(R206-Pad2)") (class "Default")
      (node (ref "R206") (pin "2") (pinfunction "2_2") (pintype "passive"))
      (node (ref "VD117") (pin "C") (pinfunction "C_C") (pintype "passive"))
    )
    (net (code "406") (name "Net-(R207-Pad2)") (class "Default")
      (node (ref "R207") (pin "2") (pinfunction "2_2") (pintype "passive"))
      (node (ref "VD118") (pin "C") (pinfunction "C_C") (pintype "passive"))
    )
    (net (code "407") (name "Net-(R208-Pad2)") (class "Default")
      (node (ref "R208") (pin "2") (pinfunction "2_2") (pintype "passive"))
      (node (ref "VD119") (pin "C") (pinfunction "C_C") (pintype "passive"))
    )
    (net (code "408") (name "Net-(R209-Pad2)") (class "Default")
      (node (ref "R209") (pin "2") (pinfunction "2_2") (pintype "passive"))
      (node (ref "VD120") (pin "C") (pinfunction "C_C") (pintype "passive"))
    )
    (net (code "409") (name "Net-(R210-Pad2)") (class "Default")
      (node (ref "R210") (pin "2") (pinfunction "2_2") (pintype "passive"))
      (node (ref "VD121") (pin "C") (pinfunction "C_C") (pintype "passive"))
    )
    (net (code "410") (name "Net-(R211-Pad2)") (class "Default")
      (node (ref "R211") (pin "2") (pinfunction "2_2") (pintype "passive"))
      (node (ref "VD122") (pin "C") (pinfunction "C_C") (pintype "passive"))
    )
    (net (code "411") (name "Net-(R212-Pad2)") (class "Default")
      (node (ref "R212") (pin "2") (pinfunction "2_2") (pintype "passive"))
      (node (ref "VD123") (pin "C") (pinfunction "C_C") (pintype "passive"))
    )
    (net (code "412") (name "Net-(R213-Pad2)") (class "Default")
      (node (ref "R213") (pin "2") (pinfunction "2_2") (pintype "passive"))
      (node (ref "VD124") (pin "C") (pinfunction "C_C") (pintype "passive"))
    )
    (net (code "413") (name "Net-(R214-Pad2)") (class "Default")
      (node (ref "R214") (pin "2") (pinfunction "2_2") (pintype "passive"))
      (node (ref "VD125") (pin "C") (pinfunction "C_C") (pintype "passive"))
    )
    (net (code "414") (name "Net-(R215-Pad2)") (class "Default")
      (node (ref "R215") (pin "2") (pinfunction "2_2") (pintype "passive"))
      (node (ref "VD126") (pin "C") (pinfunction "C_C") (pintype "passive"))
    )
    (net (code "415") (name "Net-(R216-Pad2)") (class "Default")
      (node (ref "R216") (pin "2") (pinfunction "2_2") (pintype "passive"))
      (node (ref "VD127") (pin "C") (pinfunction "C_C") (pintype "passive"))
    )
    (net (code "416") (name "Net-(R217-Pad2)") (class "Default")
      (node (ref "R217") (pin "2") (pinfunction "2_2") (pintype "passive"))
      (node (ref "VD128") (pin "C") (pinfunction "C_C") (pintype "passive"))
    )
    (net (code "417") (name "Net-(R218-Pad2)") (class "Default")
      (node (ref "R218") (pin "2") (pinfunction "2_2") (pintype "passive"))
      (node (ref "VD129") (pin "C") (pinfunction "C_C") (pintype "passive"))
    )
    (net (code "418") (name "Net-(R219-Pad2)") (class "Default")
      (node (ref "R219") (pin "2") (pinfunction "2_2") (pintype "passive"))
      (node (ref "VD130") (pin "C") (pinfunction "C_C") (pintype "passive"))
    )
    (net (code "419") (name "Net-(R220-Pad2)") (class "Default")
      (node (ref "R220") (pin "2") (pinfunction "2_2") (pintype "passive"))
      (node (ref "VD131") (pin "C") (pinfunction "C_C") (pintype "passive"))
    )
    (net (code "420") (name "Net-(R253-Pad2)") (class "Default")
      (node (ref "R253") (pin "2") (pinfunction "2_2") (pintype "passive"))
      (node (ref "VD148") (pin "C") (pinfunction "C_C") (pintype "passive"))
    )
    (net (code "421") (name "Net-(R254-Pad2)") (class "Default")
      (node (ref "R254") (pin "2") (pinfunction "2_2") (pintype "passive"))
      (node (ref "VD149") (pin "C") (pinfunction "C_C") (pintype "passive"))
    )
    (net (code "422") (name "Net-(R255-Pad2)") (class "Default")
      (node (ref "R255") (pin "2") (pinfunction "2_2") (pintype "passive"))
      (node (ref "VD150") (pin "C") (pinfunction "C_C") (pintype "passive"))
    )
    (net (code "423") (name "Net-(R256-Pad2)") (class "Default")
      (node (ref "R256") (pin "2") (pinfunction "2_2") (pintype "passive"))
      (node (ref "VD151") (pin "C") (pinfunction "C_C") (pintype "passive"))
    )
    (net (code "424") (name "Net-(R257-Pad2)") (class "Default")
      (node (ref "R257") (pin "2") (pinfunction "2_2") (pintype "passive"))
      (node (ref "VD152") (pin "C") (pinfunction "C_C") (pintype "passive"))
    )
    (net (code "425") (name "Net-(R258-Pad2)") (class "Default")
      (node (ref "R258") (pin "2") (pinfunction "2_2") (pintype "passive"))
      (node (ref "VD153") (pin "C") (pinfunction "C_C") (pintype "passive"))
    )
    (net (code "426") (name "Net-(R259-Pad2)") (class "Default")
      (node (ref "R259") (pin "2") (pinfunction "2_2") (pintype "passive"))
      (node (ref "VD154") (pin "C") (pinfunction "C_C") (pintype "passive"))
    )
    (net (code "427") (name "Net-(R260-Pad2)") (class "Default")
      (node (ref "R260") (pin "2") (pinfunction "2_2") (pintype "passive"))
      (node (ref "VD155") (pin "C") (pinfunction "C_C") (pintype "passive"))
    )
    (net (code "428") (name "Net-(R261-Pad2)") (class "Default")
      (node (ref "R261") (pin "2") (pinfunction "2_2") (pintype "passive"))
      (node (ref "VD156") (pin "C") (pinfunction "C_C") (pintype "passive"))
    )
    (net (code "429") (name "Net-(R262-Pad2)") (class "Default")
      (node (ref "R262") (pin "2") (pinfunction "2_2") (pintype "passive"))
      (node (ref "VD157") (pin "C") (pinfunction "C_C") (pintype "passive"))
    )
    (net (code "430") (name "Net-(R263-Pad2)") (class "Default")
      (node (ref "R263") (pin "2") (pinfunction "2_2") (pintype "passive"))
      (node (ref "VD158") (pin "C") (pinfunction "C_C") (pintype "passive"))
    )
    (net (code "431") (name "Net-(R264-Pad2)") (class "Default")
      (node (ref "R264") (pin "2") (pinfunction "2_2") (pintype "passive"))
      (node (ref "VD159") (pin "C") (pinfunction "C_C") (pintype "passive"))
    )
    (net (code "432") (name "Net-(R265-Pad2)") (class "Default")
      (node (ref "R265") (pin "2") (pinfunction "2_2") (pintype "passive"))
      (node (ref "VD160") (pin "C") (pinfunction "C_C") (pintype "passive"))
    )
    (net (code "433") (name "Net-(R266-Pad2)") (class "Default")
      (node (ref "R266") (pin "2") (pinfunction "2_2") (pintype "passive"))
      (node (ref "VD161") (pin "C") (pinfunction "C_C") (pintype "passive"))
    )
    (net (code "434") (name "Net-(R267-Pad2)") (class "Default")
      (node (ref "R267") (pin "2") (pinfunction "2_2") (pintype "passive"))
      (node (ref "VD162") (pin "C") (pinfunction "C_C") (pintype "passive"))
    )
    (net (code "435") (name "Net-(R268-Pad2)") (class "Default")
      (node (ref "R268") (pin "2") (pinfunction "2_2") (pintype "passive"))
      (node (ref "VD163") (pin "C") (pinfunction "C_C") (pintype "passive"))
    )
    (net (code "436") (name "Net-(R301-Pad2)") (class "Default")
      (node (ref "R301") (pin "2") (pinfunction "2_2") (pintype "passive"))
      (node (ref "VD180") (pin "C") (pinfunction "C_C") (pintype "passive"))
    )
    (net (code "437") (name "Net-(R302-Pad2)") (class "Default")
      (node (ref "R302") (pin "2") (pinfunction "2_2") (pintype "passive"))
      (node (ref "VD181") (pin "C") (pinfunction "C_C") (pintype "passive"))
    )
    (net (code "438") (name "Net-(R303-Pad2)") (class "Default")
      (node (ref "R303") (pin "2") (pinfunction "2_2") (pintype "passive"))
      (node (ref "VD182") (pin "C") (pinfunction "C_C") (pintype "passive"))
    )
    (net (code "439") (name "Net-(R304-Pad2)") (class "Default")
      (node (ref "R304") (pin "2") (pinfunction "2_2") (pintype "passive"))
      (node (ref "VD183") (pin "C") (pinfunction "C_C") (pintype "passive"))
    )
    (net (code "440") (name "Net-(R305-Pad2)") (class "Default")
      (node (ref "R305") (pin "2") (pinfunction "2_2") (pintype "passive"))
      (node (ref "VD184") (pin "C") (pinfunction "C_C") (pintype "passive"))
    )
    (net (code "441") (name "Net-(R306-Pad2)") (class "Default")
      (node (ref "R306") (pin "2") (pinfunction "2_2") (pintype "passive"))
      (node (ref "VD185") (pin "C") (pinfunction "C_C") (pintype "passive"))
    )
    (net (code "442") (name "Net-(R307-Pad2)") (class "Default")
      (node (ref "R307") (pin "2") (pinfunction "2_2") (pintype "passive"))
      (node (ref "VD186") (pin "C") (pinfunction "C_C") (pintype "passive"))
    )
    (net (code "443") (name "Net-(R308-Pad2)") (class "Default")
      (node (ref "R308") (pin "2") (pinfunction "2_2") (pintype "passive"))
      (node (ref "VD187") (pin "C") (pinfunction "C_C") (pintype "passive"))
    )
    (net (code "444") (name "Net-(R309-Pad2)") (class "Default")
      (node (ref "R309") (pin "2") (pinfunction "2_2") (pintype "passive"))
      (node (ref "VD188") (pin "C") (pinfunction "C_C") (pintype "passive"))
    )
    (net (code "445") (name "Net-(R310-Pad2)") (class "Default")
      (node (ref "R310") (pin "2") (pinfunction "2_2") (pintype "passive"))
      (node (ref "VD189") (pin "C") (pinfunction "C_C") (pintype "passive"))
    )
    (net (code "446") (name "Net-(R311-Pad2)") (class "Default")
      (node (ref "R311") (pin "2") (pinfunction "2_2") (pintype "passive"))
      (node (ref "VD190") (pin "C") (pinfunction "C_C") (pintype "passive"))
    )
    (net (code "447") (name "Net-(R312-Pad2)") (class "Default")
      (node (ref "R312") (pin "2") (pinfunction "2_2") (pintype "passive"))
      (node (ref "VD191") (pin "C") (pinfunction "C_C") (pintype "passive"))
    )
    (net (code "448") (name "Net-(R313-Pad2)") (class "Default")
      (node (ref "R313") (pin "2") (pinfunction "2_2") (pintype "passive"))
      (node (ref "VD192") (pin "C") (pinfunction "C_C") (pintype "passive"))
    )
    (net (code "449") (name "Net-(R314-Pad2)") (class "Default")
      (node (ref "R314") (pin "2") (pinfunction "2_2") (pintype "passive"))
      (node (ref "VD193") (pin "C") (pinfunction "C_C") (pintype "passive"))
    )
    (net (code "450") (name "Net-(R315-Pad2)") (class "Default")
      (node (ref "R315") (pin "2") (pinfunction "2_2") (pintype "passive"))
      (node (ref "VD194") (pin "C") (pinfunction "C_C") (pintype "passive"))
    )
    (net (code "451") (name "Net-(R316-Pad2)") (class "Default")
      (node (ref "R316") (pin "2") (pinfunction "2_2") (pintype "passive"))
      (node (ref "VD195") (pin "C") (pinfunction "C_C") (pintype "passive"))
    )
    (net (code "452") (name "Net-(R342-Pad2)") (class "Default")
      (node (ref "R342") (pin "2") (pinfunction "2_2") (pintype "passive"))
      (node (ref "VD204") (pin "C") (pinfunction "C_C") (pintype "passive"))
    )
    (net (code "453") (name "Net-(R343-Pad2)") (class "Default")
      (node (ref "R343") (pin "2") (pinfunction "2_2") (pintype "passive"))
      (node (ref "VD205") (pin "C") (pinfunction "C_C") (pintype "passive"))
    )
    (net (code "454") (name "Net-(R344-Pad2)") (class "Default")
      (node (ref "R344") (pin "2") (pinfunction "2_2") (pintype "passive"))
      (node (ref "VD206") (pin "C") (pinfunction "C_C") (pintype "passive"))
    )
    (net (code "455") (name "Net-(R345-Pad2)") (class "Default")
      (node (ref "R345") (pin "2") (pinfunction "2_2") (pintype "passive"))
      (node (ref "VD207") (pin "C") (pinfunction "C_C") (pintype "passive"))
    )
    (net (code "456") (name "Net-(R346-Pad2)") (class "Default")
      (node (ref "R346") (pin "2") (pinfunction "2_2") (pintype "passive"))
      (node (ref "VD208") (pin "C") (pinfunction "C_C") (pintype "passive"))
    )
    (net (code "457") (name "Net-(R347-Pad2)") (class "Default")
      (node (ref "R347") (pin "2") (pinfunction "2_2") (pintype "passive"))
      (node (ref "VD209") (pin "C") (pinfunction "C_C") (pintype "passive"))
    )
    (net (code "458") (name "Net-(R348-Pad2)") (class "Default")
      (node (ref "R348") (pin "2") (pinfunction "2_2") (pintype "passive"))
      (node (ref "VD210") (pin "C") (pinfunction "C_C") (pintype "passive"))
    )
    (net (code "459") (name "Net-(R349-Pad2)") (class "Default")
      (node (ref "R349") (pin "2") (pinfunction "2_2") (pintype "passive"))
      (node (ref "VD211") (pin "C") (pinfunction "C_C") (pintype "passive"))
    )
    (net (code "460") (name "Net-(R358-Pad1)") (class "Default")
      (node (ref "R358") (pin "1") (pinfunction "1_1") (pintype "passive"))
      (node (ref "XP13") (pin "2") (pinfunction "2_2") (pintype "passive"))
    )
    (net (code "461") (name "Net-(R359-Pad1)") (class "Default")
      (node (ref "R359") (pin "1") (pinfunction "1_1") (pintype "passive"))
      (node (ref "R360") (pin "2") (pinfunction "2_2") (pintype "passive"))
      (node (ref "VT4") (pin "C") (pinfunction "C_C") (pintype "passive"))
    )
    (net (code "462") (name "Net-(R361-Pad1)") (class "Default")
      (node (ref "R361") (pin "1") (pinfunction "1_1") (pintype "passive"))
      (node (ref "R363") (pin "1") (pinfunction "1_1") (pintype "passive"))
      (node (ref "VD214") (pin "C") (pinfunction "C_C") (pintype "passive"))
    )
    (net (code "463") (name "Net-(R362-Pad1)") (class "Default")
      (node (ref "R362") (pin "1") (pinfunction "1_1") (pintype "passive"))
      (node (ref "R364") (pin "1") (pinfunction "1_1") (pintype "passive"))
      (node (ref "VT4") (pin "B") (pinfunction "B_B") (pintype "passive"))
    )
    (net (code "464") (name "Net-(R363-Pad2)") (class "Default")
      (node (ref "R363") (pin "2") (pinfunction "2_2") (pintype "passive"))
      (node (ref "Z48") (pin "1") (pinfunction "1_1") (pintype "passive"))
    )
    (net (code "465") (name "Net-(R364-Pad2)") (class "Default")
      (node (ref "R364") (pin "2") (pinfunction "2_2") (pintype "passive"))
      (node (ref "Z49") (pin "1") (pinfunction "1_1") (pintype "passive"))
    )
    (net (code "466") (name "Net-(RK1-P$1)") (class "Default")
      (node (ref "RK1") (pin "1") (pinfunction "P$1_1") (pintype "passive"))
      (node (ref "VD56") (pin "C") (pinfunction "C_C") (pintype "passive"))
    )
    (net (code "467") (name "Net-(VD36-PadC)") (class "Default")
      (node (ref "VD36") (pin "C") (pinfunction "C_C") (pintype "passive"))
      (node (ref "VD37") (pin "C") (pinfunction "C_C") (pintype "passive"))
    )
    (net (code "468") (name "Net-(VD38-PadC)") (class "Default")
      (node (ref "VD38") (pin "C") (pinfunction "C_C") (pintype "passive"))
      (node (ref "VD39") (pin "C") (pinfunction "C_C") (pintype "passive"))
    )
    (net (code "469") (name "Net-(VD40-PadC)") (class "Default")
      (node (ref "VD40") (pin "C") (pinfunction "C_C") (pintype "passive"))
      (node (ref "VD41") (pin "C") (pinfunction "C_C") (pintype "passive"))
    )
    (net (code "470") (name "Net-(VD42-PadC)") (class "Default")
      (node (ref "VD42") (pin "C") (pinfunction "C_C") (pintype "passive"))
      (node (ref "VD43") (pin "C") (pinfunction "C_C") (pintype "passive"))
    )
    (net (code "471") (name "Net-(VD44-PadC)") (class "Default")
      (node (ref "VD44") (pin "C") (pinfunction "C_C") (pintype "passive"))
      (node (ref "VD45") (pin "C") (pinfunction "C_C") (pintype "passive"))
    )
    (net (code "472") (name "Net-(VD46-PadC)") (class "Default")
      (node (ref "VD46") (pin "C") (pinfunction "C_C") (pintype "passive"))
      (node (ref "VD47") (pin "C") (pinfunction "C_C") (pintype "passive"))
    )
    (net (code "473") (name "Net-(VD53-PadA1)") (class "Default")
      (node (ref "VD53") (pin "A1") (pinfunction "A1_A1") (pintype "passive"))
      (node (ref "VD54") (pin "A2") (pinfunction "A2_A2") (pintype "passive"))
    )
    (net (code "474") (name "Net-(VD61-C)") (class "Default")
      (node (ref "R131") (pin "1") (pinfunction "1_1") (pintype "passive"))
      (node (ref "R132") (pin "1") (pinfunction "1_1") (pintype "passive"))
      (node (ref "R135") (pin "2") (pinfunction "2_2") (pintype "passive"))
      (node (ref "VD61") (pin "2") (pinfunction "C_2") (pintype "passive"))
      (node (ref "VT1") (pin "2") (pinfunction "D_2") (pintype "passive"))
    )
    (net (code "475") (name "Net-(VD62-PadA2)") (class "Default")
      (node (ref "VD62") (pin "A2") (pinfunction "A2_A2") (pintype "passive"))
      (node (ref "VD63") (pin "C") (pinfunction "C_C") (pintype "passive"))
    )
    (net (code "476") (name "Net-(VD212-PadA2)") (class "Default")
      (node (ref "VD212") (pin "A2") (pinfunction "A2_A2") (pintype "passive"))
      (node (ref "XP12") (pin "4") (pinfunction "4_4") (pintype "passive"))
      (node (ref "Z45") (pin "1") (pinfunction "1_1") (pintype "passive"))
    )
    (net (code "477") (name "Net-(VD213-PadA2)") (class "Default")
      (node (ref "VD213") (pin "A2") (pinfunction "A2_A2") (pintype "passive"))
      (node (ref "XP12") (pin "3") (pinfunction "3_3") (pintype "passive"))
      (node (ref "Z46") (pin "1") (pinfunction "1_1") (pintype "passive"))
    )
    (net (code "478") (name "Net-(VT1-S)") (class "Default")
      (node (ref "R134") (pin "2") (pinfunction "2_2") (pintype "passive"))
      (node (ref "VD57") (pin "A1") (pinfunction "A1_A1") (pintype "passive"))
      (node (ref "VT1") (pin "3") (pinfunction "S_3") (pintype "passive"))
      (node (ref "Z41") (pin "1") (pinfunction "1_1") (pintype "passive"))
    )
    (net (code "479") (name "Net-(VT3-PadE)") (class "Default")
      (node (ref "VT3") (pin "E") (pinfunction "E_E") (pintype "passive"))
      (node (ref "Z44") (pin "3") (pinfunction "3_3") (pintype "passive"))
    )
    (net (code "480") (name "Net-(XS1-1)") (class "Default")
      (node (ref "L4") (pin "1") (pinfunction "1_1") (pintype "passive"))
      (node (ref "XS1") (pin "VBUS") (pinfunction "1_VBUS") (pintype "passive"))
    )
    (net (code "481") (name "Net-(XS1-2)") (class "Default")
      (node (ref "XS1") (pin "D-") (pinfunction "2_D-") (pintype "passive"))
      (node (ref "Z43") (pin "3") (pinfunction "3_3") (pintype "passive"))
    )
    (net (code "482") (name "Net-(XS1-3)") (class "Default")
      (node (ref "XS1") (pin "D+") (pinfunction "3_D+") (pintype "passive"))
      (node (ref "Z42") (pin "3") (pinfunction "3_3") (pintype "passive"))
    )
    (net (code "483") (name "OUT_DRV1") (class "Default")
      (node (ref "D20") (pin "4") (pinfunction "OUT1_4") (pintype "power_in"))
      (node (ref "D20") (pin "5") (pinfunction "OUT2_5") (pintype "power_in"))
      (node (ref "XP11") (pin "1") (pinfunction "1_1") (pintype "passive"))
      (node (ref "XP11") (pin "4") (pinfunction "4_4") (pintype "passive"))
    )
    (net (code "484") (name "OUT_DRV2") (class "Default")
      (node (ref "D21") (pin "4") (pinfunction "OUT1_4") (pintype "power_in"))
      (node (ref "D21") (pin "5") (pinfunction "OUT2_5") (pintype "power_in"))
      (node (ref "XP11") (pin "5") (pinfunction "5_5") (pintype "passive"))
      (node (ref "XP11") (pin "8") (pinfunction "8_8") (pintype "passive"))
    )
    (net (code "485") (name "OUT_DRV3") (class "Default")
      (node (ref "D22") (pin "4") (pinfunction "OUT1_4") (pintype "power_in"))
      (node (ref "D22") (pin "5") (pinfunction "OUT2_5") (pintype "power_in"))
      (node (ref "XP11") (pin "12") (pinfunction "12_12") (pintype "passive"))
      (node (ref "XP11") (pin "9") (pinfunction "9_9") (pintype "passive"))
    )
    (net (code "486") (name "OUT_DRV4") (class "Default")
      (node (ref "D23") (pin "4") (pinfunction "OUT1_4") (pintype "power_in"))
      (node (ref "D23") (pin "5") (pinfunction "OUT2_5") (pintype "power_in"))
      (node (ref "XP11") (pin "13") (pinfunction "13_13") (pintype "passive"))
      (node (ref "XP11") (pin "16") (pinfunction "16_16") (pintype "passive"))
    )
    (net (code "487") (name "OUT_DRV5") (class "Default")
      (node (ref "D24") (pin "4") (pinfunction "OUT1_4") (pintype "power_in"))
      (node (ref "D24") (pin "5") (pinfunction "OUT2_5") (pintype "power_in"))
      (node (ref "XP11") (pin "17") (pinfunction "17_17") (pintype "passive"))
      (node (ref "XP11") (pin "20") (pinfunction "20_20") (pintype "passive"))
    )
    (net (code "488") (name "OUT_DRV6") (class "Default")
      (node (ref "D25") (pin "4") (pinfunction "OUT1_4") (pintype "power_in"))
      (node (ref "D25") (pin "5") (pinfunction "OUT2_5") (pintype "power_in"))
      (node (ref "XP11") (pin "21") (pinfunction "21_21") (pintype "passive"))
      (node (ref "XP11") (pin "24") (pinfunction "24_24") (pintype "passive"))
    )
    (net (code "489") (name "OUT_DRV7") (class "Default")
      (node (ref "D26") (pin "4") (pinfunction "OUT1_4") (pintype "power_in"))
      (node (ref "D26") (pin "5") (pinfunction "OUT2_5") (pintype "power_in"))
      (node (ref "XP11") (pin "25") (pinfunction "25_25") (pintype "passive"))
      (node (ref "XP11") (pin "28") (pinfunction "28_28") (pintype "passive"))
    )
    (net (code "490") (name "OUT_DRV8") (class "Default")
      (node (ref "D27") (pin "4") (pinfunction "OUT1_4") (pintype "power_in"))
      (node (ref "D27") (pin "5") (pinfunction "OUT2_5") (pintype "power_in"))
      (node (ref "XP11") (pin "29") (pinfunction "29_29") (pintype "passive"))
      (node (ref "XP11") (pin "32") (pinfunction "32_32") (pintype "passive"))
    )
    (net (code "491") (name "PHASE_1") (class "Default")
      (node (ref "R74") (pin "2") (pinfunction "2_2") (pintype "passive"))
      (node (ref "R77") (pin "1") (pinfunction "1_1") (pintype "passive"))
      (node (ref "R80") (pin "1") (pinfunction "1_1") (pintype "passive"))
      (node (ref "XP5") (pin "2") (pinfunction "2_2") (pintype "passive"))
    )
    (net (code "492") (name "PHASE_2") (class "Default")
      (node (ref "R75") (pin "2") (pinfunction "2_2") (pintype "passive"))
      (node (ref "R78") (pin "1") (pinfunction "1_1") (pintype "passive"))
      (node (ref "R81") (pin "1") (pinfunction "1_1") (pintype "passive"))
      (node (ref "XP5") (pin "4") (pinfunction "4_4") (pintype "passive"))
    )
    (net (code "493") (name "PHASE_3") (class "Default")
      (node (ref "R76") (pin "2") (pinfunction "2_2") (pintype "passive"))
      (node (ref "R79") (pin "1") (pinfunction "1_1") (pintype "passive"))
      (node (ref "R82") (pin "1") (pinfunction "1_1") (pintype "passive"))
      (node (ref "XP5") (pin "6") (pinfunction "6_6") (pintype "passive"))
    )
    (net (code "494") (name "REL_RAW_1") (class "Default")
      (node (ref "R138") (pin "1") (pinfunction "1_1") (pintype "passive"))
      (node (ref "R154") (pin "1") (pinfunction "1_1") (pintype "passive"))
      (node (ref "VD66") (pin "C") (pinfunction "C_C") (pintype "passive"))
      (node (ref "XP7") (pin "1") (pinfunction "1_1") (pintype "passive"))
    )
    (net (code "495") (name "REL_RAW_2") (class "Default")
      (node (ref "R139") (pin "1") (pinfunction "1_1") (pintype "passive"))
      (node (ref "R155") (pin "1") (pinfunction "1_1") (pintype "passive"))
      (node (ref "VD67") (pin "C") (pinfunction "C_C") (pintype "passive"))
      (node (ref "XP7") (pin "2") (pinfunction "2_2") (pintype "passive"))
    )
    (net (code "496") (name "REL_RAW_3") (class "Default")
      (node (ref "R140") (pin "1") (pinfunction "1_1") (pintype "passive"))
      (node (ref "R156") (pin "1") (pinfunction "1_1") (pintype "passive"))
      (node (ref "VD68") (pin "C") (pinfunction "C_C") (pintype "passive"))
      (node (ref "XP7") (pin "3") (pinfunction "3_3") (pintype "passive"))
    )
    (net (code "497") (name "REL_RAW_4") (class "Default")
      (node (ref "R141") (pin "1") (pinfunction "1_1") (pintype "passive"))
      (node (ref "R157") (pin "1") (pinfunction "1_1") (pintype "passive"))
      (node (ref "VD69") (pin "C") (pinfunction "C_C") (pintype "passive"))
      (node (ref "XP7") (pin "4") (pinfunction "4_4") (pintype "passive"))
    )
    (net (code "498") (name "REL_RAW_5") (class "Default")
      (node (ref "R142") (pin "1") (pinfunction "1_1") (pintype "passive"))
      (node (ref "R158") (pin "1") (pinfunction "1_1") (pintype "passive"))
      (node (ref "VD70") (pin "C") (pinfunction "C_C") (pintype "passive"))
      (node (ref "XP7") (pin "5") (pinfunction "5_5") (pintype "passive"))
    )
    (net (code "499") (name "REL_RAW_6") (class "Default")
      (node (ref "R143") (pin "1") (pinfunction "1_1") (pintype "passive"))
      (node (ref "R159") (pin "1") (pinfunction "1_1") (pintype "passive"))
      (node (ref "VD71") (pin "C") (pinfunction "C_C") (pintype "passive"))
      (node (ref "XP7") (pin "6") (pinfunction "6_6") (pintype "passive"))
    )
    (net (code "500") (name "REL_RAW_7") (class "Default")
      (node (ref "R144") (pin "1") (pinfunction "1_1") (pintype "passive"))
      (node (ref "R160") (pin "1") (pinfunction "1_1") (pintype "passive"))
      (node (ref "VD72") (pin "C") (pinfunction "C_C") (pintype "passive"))
      (node (ref "XP7") (pin "7") (pinfunction "7_7") (pintype "passive"))
    )
    (net (code "501") (name "REL_RAW_8") (class "Default")
      (node (ref "R145") (pin "1") (pinfunction "1_1") (pintype "passive"))
      (node (ref "R161") (pin "1") (pinfunction "1_1") (pintype "passive"))
      (node (ref "VD73") (pin "C") (pinfunction "C_C") (pintype "passive"))
      (node (ref "XP7") (pin "8") (pinfunction "8_8") (pintype "passive"))
    )
    (net (code "502") (name "REL_RAW_9") (class "Default")
      (node (ref "R146") (pin "1") (pinfunction "1_1") (pintype "passive"))
      (node (ref "R162") (pin "1") (pinfunction "1_1") (pintype "passive"))
      (node (ref "VD74") (pin "C") (pinfunction "C_C") (pintype "passive"))
      (node (ref "XP7") (pin "9") (pinfunction "9_9") (pintype "passive"))
    )
    (net (code "503") (name "REL_RAW_10") (class "Default")
      (node (ref "R147") (pin "1") (pinfunction "1_1") (pintype "passive"))
      (node (ref "R163") (pin "1") (pinfunction "1_1") (pintype "passive"))
      (node (ref "VD75") (pin "C") (pinfunction "C_C") (pintype "passive"))
      (node (ref "XP7") (pin "10") (pinfunction "10_10") (pintype "passive"))
    )
    (net (code "504") (name "REL_RAW_11") (class "Default")
      (node (ref "R148") (pin "1") (pinfunction "1_1") (pintype "passive"))
      (node (ref "R164") (pin "1") (pinfunction "1_1") (pintype "passive"))
      (node (ref "VD76") (pin "C") (pinfunction "C_C") (pintype "passive"))
      (node (ref "XP7") (pin "11") (pinfunction "11_11") (pintype "passive"))
    )
    (net (code "505") (name "REL_RAW_12") (class "Default")
      (node (ref "R149") (pin "1") (pinfunction "1_1") (pintype "passive"))
      (node (ref "R165") (pin "1") (pinfunction "1_1") (pintype "passive"))
      (node (ref "VD77") (pin "C") (pinfunction "C_C") (pintype "passive"))
      (node (ref "XP7") (pin "12") (pinfunction "12_12") (pintype "passive"))
    )
    (net (code "506") (name "REL_RAW_13") (class "Default")
      (node (ref "R150") (pin "1") (pinfunction "1_1") (pintype "passive"))
      (node (ref "R166") (pin "1") (pinfunction "1_1") (pintype "passive"))
      (node (ref "VD78") (pin "C") (pinfunction "C_C") (pintype "passive"))
      (node (ref "XP7") (pin "13") (pinfunction "13_13") (pintype "passive"))
    )
    (net (code "507") (name "REL_RAW_14") (class "Default")
      (node (ref "R151") (pin "1") (pinfunction "1_1") (pintype "passive"))
      (node (ref "R167") (pin "1") (pinfunction "1_1") (pintype "passive"))
      (node (ref "VD79") (pin "C") (pinfunction "C_C") (pintype "passive"))
      (node (ref "XP7") (pin "14") (pinfunction "14_14") (pintype "passive"))
    )
    (net (code "508") (name "REL_RAW_15") (class "Default")
      (node (ref "R152") (pin "1") (pinfunction "1_1") (pintype "passive"))
      (node (ref "R168") (pin "1") (pinfunction "1_1") (pintype "passive"))
      (node (ref "VD80") (pin "C") (pinfunction "C_C") (pintype "passive"))
      (node (ref "XP7") (pin "15") (pinfunction "15_15") (pintype "passive"))
    )
    (net (code "509") (name "REL_RAW_16") (class "Default")
      (node (ref "R153") (pin "1") (pinfunction "1_1") (pintype "passive"))
      (node (ref "R169") (pin "1") (pinfunction "1_1") (pintype "passive"))
      (node (ref "VD81") (pin "C") (pinfunction "C_C") (pintype "passive"))
      (node (ref "XP7") (pin "16") (pinfunction "16_16") (pintype "passive"))
    )
    (net (code "510") (name "REL_RAW_17") (class "Default")
      (node (ref "R189") (pin "1") (pinfunction "1_1") (pintype "passive"))
      (node (ref "R205") (pin "1") (pinfunction "1_1") (pintype "passive"))
      (node (ref "VD100") (pin "C") (pinfunction "C_C") (pintype "passive"))
      (node (ref "XP8") (pin "1") (pinfunction "1_1") (pintype "passive"))
    )
    (net (code "511") (name "REL_RAW_18") (class "Default")
      (node (ref "R190") (pin "1") (pinfunction "1_1") (pintype "passive"))
      (node (ref "R206") (pin "1") (pinfunction "1_1") (pintype "passive"))
      (node (ref "VD101") (pin "C") (pinfunction "C_C") (pintype "passive"))
      (node (ref "XP8") (pin "2") (pinfunction "2_2") (pintype "passive"))
    )
    (net (code "512") (name "REL_RAW_19") (class "Default")
      (node (ref "R191") (pin "1") (pinfunction "1_1") (pintype "passive"))
      (node (ref "R207") (pin "1") (pinfunction "1_1") (pintype "passive"))
      (node (ref "VD102") (pin "C") (pinfunction "C_C") (pintype "passive"))
      (node (ref "XP8") (pin "3") (pinfunction "3_3") (pintype "passive"))
    )
    (net (code "513") (name "REL_RAW_20") (class "Default")
      (node (ref "R192") (pin "1") (pinfunction "1_1") (pintype "passive"))
      (node (ref "R208") (pin "1") (pinfunction "1_1") (pintype "passive"))
      (node (ref "VD103") (pin "C") (pinfunction "C_C") (pintype "passive"))
      (node (ref "XP8") (pin "4") (pinfunction "4_4") (pintype "passive"))
    )
    (net (code "514") (name "REL_RAW_21") (class "Default")
      (node (ref "R193") (pin "1") (pinfunction "1_1") (pintype "passive"))
      (node (ref "R209") (pin "1") (pinfunction "1_1") (pintype "passive"))
      (node (ref "VD104") (pin "C") (pinfunction "C_C") (pintype "passive"))
      (node (ref "XP8") (pin "5") (pinfunction "5_5") (pintype "passive"))
    )
    (net (code "515") (name "REL_RAW_22") (class "Default")
      (node (ref "R194") (pin "1") (pinfunction "1_1") (pintype "passive"))
      (node (ref "R210") (pin "1") (pinfunction "1_1") (pintype "passive"))
      (node (ref "VD105") (pin "C") (pinfunction "C_C") (pintype "passive"))
      (node (ref "XP8") (pin "6") (pinfunction "6_6") (pintype "passive"))
    )
    (net (code "516") (name "REL_RAW_23") (class "Default")
      (node (ref "R195") (pin "1") (pinfunction "1_1") (pintype "passive"))
      (node (ref "R211") (pin "1") (pinfunction "1_1") (pintype "passive"))
      (node (ref "VD106") (pin "C") (pinfunction "C_C") (pintype "passive"))
      (node (ref "XP8") (pin "7") (pinfunction "7_7") (pintype "passive"))
    )
    (net (code "517") (name "REL_RAW_24") (class "Default")
      (node (ref "R196") (pin "1") (pinfunction "1_1") (pintype "passive"))
      (node (ref "R212") (pin "1") (pinfunction "1_1") (pintype "passive"))
      (node (ref "VD107") (pin "C") (pinfunction "C_C") (pintype "passive"))
      (node (ref "XP8") (pin "8") (pinfunction "8_8") (pintype "passive"))
    )
    (net (code "518") (name "REL_RAW_25") (class "Default")
      (node (ref "R197") (pin "1") (pinfunction "1_1") (pintype "passive"))
      (node (ref "R213") (pin "1") (pinfunction "1_1") (pintype "passive"))
      (node (ref "VD108") (pin "C") (pinfunction "C_C") (pintype "passive"))
      (node (ref "XP8") (pin "9") (pinfunction "9_9") (pintype "passive"))
    )
    (net (code "519") (name "REL_RAW_26") (class "Default")
      (node (ref "R198") (pin "1") (pinfunction "1_1") (pintype "passive"))
      (node (ref "R214") (pin "1") (pinfunction "1_1") (pintype "passive"))
      (node (ref "VD109") (pin "C") (pinfunction "C_C") (pintype "passive"))
      (node (ref "XP8") (pin "10") (pinfunction "10_10") (pintype "passive"))
    )
    (net (code "520") (name "REL_RAW_27") (class "Default")
      (node (ref "R199") (pin "1") (pinfunction "1_1") (pintype "passive"))
      (node (ref "R215") (pin "1") (pinfunction "1_1") (pintype "passive"))
      (node (ref "VD110") (pin "C") (pinfunction "C_C") (pintype "passive"))
      (node (ref "XP8") (pin "11") (pinfunction "11_11") (pintype "passive"))
    )
    (net (code "521") (name "REL_RAW_28") (class "Default")
      (node (ref "R200") (pin "1") (pinfunction "1_1") (pintype "passive"))
      (node (ref "R216") (pin "1") (pinfunction "1_1") (pintype "passive"))
      (node (ref "VD111") (pin "C") (pinfunction "C_C") (pintype "passive"))
      (node (ref "XP8") (pin "12") (pinfunction "12_12") (pintype "passive"))
    )
    (net (code "522") (name "REL_RAW_29") (class "Default")
      (node (ref "R201") (pin "1") (pinfunction "1_1") (pintype "passive"))
      (node (ref "R217") (pin "1") (pinfunction "1_1") (pintype "passive"))
      (node (ref "VD112") (pin "C") (pinfunction "C_C") (pintype "passive"))
      (node (ref "XP8") (pin "13") (pinfunction "13_13") (pintype "passive"))
    )
    (net (code "523") (name "REL_RAW_30") (class "Default")
      (node (ref "R202") (pin "1") (pinfunction "1_1") (pintype "passive"))
      (node (ref "R218") (pin "1") (pinfunction "1_1") (pintype "passive"))
      (node (ref "VD113") (pin "C") (pinfunction "C_C") (pintype "passive"))
      (node (ref "XP8") (pin "14") (pinfunction "14_14") (pintype "passive"))
    )
    (net (code "524") (name "REL_RAW_31") (class "Default")
      (node (ref "R203") (pin "1") (pinfunction "1_1") (pintype "passive"))
      (node (ref "R219") (pin "1") (pinfunction "1_1") (pintype "passive"))
      (node (ref "VD114") (pin "C") (pinfunction "C_C") (pintype "passive"))
      (node (ref "XP8") (pin "15") (pinfunction "15_15") (pintype "passive"))
    )
    (net (code "525") (name "REL_RAW_32") (class "Default")
      (node (ref "R204") (pin "1") (pinfunction "1_1") (pintype "passive"))
      (node (ref "R220") (pin "1") (pinfunction "1_1") (pintype "passive"))
      (node (ref "VD115") (pin "C") (pinfunction "C_C") (pintype "passive"))
      (node (ref "XP8") (pin "16") (pinfunction "16_16") (pintype "passive"))
    )
    (net (code "526") (name "REL_RAW_33") (class "Default")
      (node (ref "R237") (pin "1") (pinfunction "1_1") (pintype "passive"))
      (node (ref "R253") (pin "1") (pinfunction "1_1") (pintype "passive"))
      (node (ref "VD132") (pin "C") (pinfunction "C_C") (pintype "passive"))
      (node (ref "XP9") (pin "1") (pinfunction "1_1") (pintype "passive"))
    )
    (net (code "527") (name "REL_RAW_34") (class "Default")
      (node (ref "R238") (pin "1") (pinfunction "1_1") (pintype "passive"))
      (node (ref "R254") (pin "1") (pinfunction "1_1") (pintype "passive"))
      (node (ref "VD133") (pin "C") (pinfunction "C_C") (pintype "passive"))
      (node (ref "XP9") (pin "2") (pinfunction "2_2") (pintype "passive"))
    )
    (net (code "528") (name "REL_RAW_35") (class "Default")
      (node (ref "R239") (pin "1") (pinfunction "1_1") (pintype "passive"))
      (node (ref "R255") (pin "1") (pinfunction "1_1") (pintype "passive"))
      (node (ref "VD134") (pin "C") (pinfunction "C_C") (pintype "passive"))
      (node (ref "XP9") (pin "3") (pinfunction "3_3") (pintype "passive"))
    )
    (net (code "529") (name "REL_RAW_36") (class "Default")
      (node (ref "R240") (pin "1") (pinfunction "1_1") (pintype "passive"))
      (node (ref "R256") (pin "1") (pinfunction "1_1") (pintype "passive"))
      (node (ref "VD135") (pin "C") (pinfunction "C_C") (pintype "passive"))
      (node (ref "XP9") (pin "4") (pinfunction "4_4") (pintype "passive"))
    )
    (net (code "530") (name "REL_RAW_37") (class "Default")
      (node (ref "R241") (pin "1") (pinfunction "1_1") (pintype "passive"))
      (node (ref "R257") (pin "1") (pinfunction "1_1") (pintype "passive"))
      (node (ref "VD136") (pin "C") (pinfunction "C_C") (pintype "passive"))
      (node (ref "XP9") (pin "5") (pinfunction "5_5") (pintype "passive"))
    )
    (net (code "531") (name "REL_RAW_38") (class "Default")
      (node (ref "R242") (pin "1") (pinfunction "1_1") (pintype "passive"))
      (node (ref "R258") (pin "1") (pinfunction "1_1") (pintype "passive"))
      (node (ref "VD137") (pin "C") (pinfunction "C_C") (pintype "passive"))
      (node (ref "XP9") (pin "6") (pinfunction "6_6") (pintype "passive"))
    )
    (net (code "532") (name "REL_RAW_39") (class "Default")
      (node (ref "R243") (pin "1") (pinfunction "1_1") (pintype "passive"))
      (node (ref "R259") (pin "1") (pinfunction "1_1") (pintype "passive"))
      (node (ref "VD138") (pin "C") (pinfunction "C_C") (pintype "passive"))
      (node (ref "XP9") (pin "7") (pinfunction "7_7") (pintype "passive"))
    )
    (net (code "533") (name "REL_RAW_40") (class "Default")
      (node (ref "R244") (pin "1") (pinfunction "1_1") (pintype "passive"))
      (node (ref "R260") (pin "1") (pinfunction "1_1") (pintype "passive"))
      (node (ref "VD139") (pin "C") (pinfunction "C_C") (pintype "passive"))
      (node (ref "XP9") (pin "8") (pinfunction "8_8") (pintype "passive"))
    )
    (net (code "534") (name "REL_RAW_41") (class "Default")
      (node (ref "R245") (pin "1") (pinfunction "1_1") (pintype "passive"))
      (node (ref "R261") (pin "1") (pinfunction "1_1") (pintype "passive"))
      (node (ref "VD140") (pin "C") (pinfunction "C_C") (pintype "passive"))
      (node (ref "XP9") (pin "9") (pinfunction "9_9") (pintype "passive"))
    )
    (net (code "535") (name "REL_RAW_42") (class "Default")
      (node (ref "R246") (pin "1") (pinfunction "1_1") (pintype "passive"))
      (node (ref "R262") (pin "1") (pinfunction "1_1") (pintype "passive"))
      (node (ref "VD141") (pin "C") (pinfunction "C_C") (pintype "passive"))
      (node (ref "XP9") (pin "10") (pinfunction "10_10") (pintype "passive"))
    )
    (net (code "536") (name "REL_RAW_43") (class "Default")
      (node (ref "R247") (pin "1") (pinfunction "1_1") (pintype "passive"))
      (node (ref "R263") (pin "1") (pinfunction "1_1") (pintype "passive"))
      (node (ref "VD142") (pin "C") (pinfunction "C_C") (pintype "passive"))
      (node (ref "XP9") (pin "11") (pinfunction "11_11") (pintype "passive"))
    )
    (net (code "537") (name "REL_RAW_44") (class "Default")
      (node (ref "R248") (pin "1") (pinfunction "1_1") (pintype "passive"))
      (node (ref "R264") (pin "1") (pinfunction "1_1") (pintype "passive"))
      (node (ref "VD143") (pin "C") (pinfunction "C_C") (pintype "passive"))
      (node (ref "XP9") (pin "12") (pinfunction "12_12") (pintype "passive"))
    )
    (net (code "538") (name "REL_RAW_45") (class "Default")
      (node (ref "R249") (pin "1") (pinfunction "1_1") (pintype "passive"))
      (node (ref "R265") (pin "1") (pinfunction "1_1") (pintype "passive"))
      (node (ref "VD144") (pin "C") (pinfunction "C_C") (pintype "passive"))
      (node (ref "XP9") (pin "13") (pinfunction "13_13") (pintype "passive"))
    )
    (net (code "539") (name "REL_RAW_46") (class "Default")
      (node (ref "R250") (pin "1") (pinfunction "1_1") (pintype "passive"))
      (node (ref "R266") (pin "1") (pinfunction "1_1") (pintype "passive"))
      (node (ref "VD145") (pin "C") (pinfunction "C_C") (pintype "passive"))
      (node (ref "XP9") (pin "14") (pinfunction "14_14") (pintype "passive"))
    )
    (net (code "540") (name "REL_RAW_47") (class "Default")
      (node (ref "R251") (pin "1") (pinfunction "1_1") (pintype "passive"))
      (node (ref "R267") (pin "1") (pinfunction "1_1") (pintype "passive"))
      (node (ref "VD146") (pin "C") (pinfunction "C_C") (pintype "passive"))
      (node (ref "XP9") (pin "15") (pinfunction "15_15") (pintype "passive"))
    )
    (net (code "541") (name "REL_RAW_48") (class "Default")
      (node (ref "R252") (pin "1") (pinfunction "1_1") (pintype "passive"))
      (node (ref "R268") (pin "1") (pinfunction "1_1") (pintype "passive"))
      (node (ref "VD147") (pin "C") (pinfunction "C_C") (pintype "passive"))
      (node (ref "XP9") (pin "16") (pinfunction "16_16") (pintype "passive"))
    )
    (net (code "542") (name "REL_RAW_49") (class "Default")
      (node (ref "R285") (pin "1") (pinfunction "1_1") (pintype "passive"))
      (node (ref "R301") (pin "1") (pinfunction "1_1") (pintype "passive"))
      (node (ref "VD164") (pin "C") (pinfunction "C_C") (pintype "passive"))
      (node (ref "XP10") (pin "1") (pinfunction "1_1") (pintype "passive"))
    )
    (net (code "543") (name "REL_RAW_50") (class "Default")
      (node (ref "R286") (pin "1") (pinfunction "1_1") (pintype "passive"))
      (node (ref "R302") (pin "1") (pinfunction "1_1") (pintype "passive"))
      (node (ref "VD165") (pin "C") (pinfunction "C_C") (pintype "passive"))
      (node (ref "XP10") (pin "2") (pinfunction "2_2") (pintype "passive"))
    )
    (net (code "544") (name "REL_RAW_51") (class "Default")
      (node (ref "R287") (pin "1") (pinfunction "1_1") (pintype "passive"))
      (node (ref "R303") (pin "1") (pinfunction "1_1") (pintype "passive"))
      (node (ref "VD166") (pin "C") (pinfunction "C_C") (pintype "passive"))
      (node (ref "XP10") (pin "3") (pinfunction "3_3") (pintype "passive"))
    )
    (net (code "545") (name "REL_RAW_52") (class "Default")
      (node (ref "R288") (pin "1") (pinfunction "1_1") (pintype "passive"))
      (node (ref "R304") (pin "1") (pinfunction "1_1") (pintype "passive"))
      (node (ref "VD167") (pin "C") (pinfunction "C_C") (pintype "passive"))
      (node (ref "XP10") (pin "4") (pinfunction "4_4") (pintype "passive"))
    )
    (net (code "546") (name "REL_RAW_53") (class "Default")
      (node (ref "R289") (pin "1") (pinfunction "1_1") (pintype "passive"))
      (node (ref "R305") (pin "1") (pinfunction "1_1") (pintype "passive"))
      (node (ref "VD168") (pin "C") (pinfunction "C_C") (pintype "passive"))
      (node (ref "XP10") (pin "5") (pinfunction "5_5") (pintype "passive"))
    )
    (net (code "547") (name "REL_RAW_54") (class "Default")
      (node (ref "R290") (pin "1") (pinfunction "1_1") (pintype "passive"))
      (node (ref "R306") (pin "1") (pinfunction "1_1") (pintype "passive"))
      (node (ref "VD169") (pin "C") (pinfunction "C_C") (pintype "passive"))
      (node (ref "XP10") (pin "6") (pinfunction "6_6") (pintype "passive"))
    )
    (net (code "548") (name "REL_RAW_55") (class "Default")
      (node (ref "R291") (pin "1") (pinfunction "1_1") (pintype "passive"))
      (node (ref "R307") (pin "1") (pinfunction "1_1") (pintype "passive"))
      (node (ref "VD170") (pin "C") (pinfunction "C_C") (pintype "passive"))
      (node (ref "XP10") (pin "7") (pinfunction "7_7") (pintype "passive"))
    )
    (net (code "549") (name "REL_RAW_56") (class "Default")
      (node (ref "R292") (pin "1") (pinfunction "1_1") (pintype "passive"))
      (node (ref "R308") (pin "1") (pinfunction "1_1") (pintype "passive"))
      (node (ref "VD171") (pin "C") (pinfunction "C_C") (pintype "passive"))
      (node (ref "XP10") (pin "8") (pinfunction "8_8") (pintype "passive"))
    )
    (net (code "550") (name "REL_RAW_57") (class "Default")
      (node (ref "R293") (pin "1") (pinfunction "1_1") (pintype "passive"))
      (node (ref "R309") (pin "1") (pinfunction "1_1") (pintype "passive"))
      (node (ref "VD172") (pin "C") (pinfunction "C_C") (pintype "passive"))
      (node (ref "XP10") (pin "9") (pinfunction "9_9") (pintype "passive"))
    )
    (net (code "551") (name "REL_RAW_58") (class "Default")
      (node (ref "R294") (pin "1") (pinfunction "1_1") (pintype "passive"))
      (node (ref "R310") (pin "1") (pinfunction "1_1") (pintype "passive"))
      (node (ref "VD173") (pin "C") (pinfunction "C_C") (pintype "passive"))
      (node (ref "XP10") (pin "10") (pinfunction "10_10") (pintype "passive"))
    )
    (net (code "552") (name "REL_RAW_59") (class "Default")
      (node (ref "R295") (pin "1") (pinfunction "1_1") (pintype "passive"))
      (node (ref "R311") (pin "1") (pinfunction "1_1") (pintype "passive"))
      (node (ref "VD174") (pin "C") (pinfunction "C_C") (pintype "passive"))
      (node (ref "XP10") (pin "11") (pinfunction "11_11") (pintype "passive"))
    )
    (net (code "553") (name "REL_RAW_60") (class "Default")
      (node (ref "R296") (pin "1") (pinfunction "1_1") (pintype "passive"))
      (node (ref "R312") (pin "1") (pinfunction "1_1") (pintype "passive"))
      (node (ref "VD175") (pin "C") (pinfunction "C_C") (pintype "passive"))
      (node (ref "XP10") (pin "12") (pinfunction "12_12") (pintype "passive"))
    )
    (net (code "554") (name "REL_RAW_61") (class "Default")
      (node (ref "R297") (pin "1") (pinfunction "1_1") (pintype "passive"))
      (node (ref "R313") (pin "1") (pinfunction "1_1") (pintype "passive"))
      (node (ref "VD176") (pin "C") (pinfunction "C_C") (pintype "passive"))
      (node (ref "XP10") (pin "13") (pinfunction "13_13") (pintype "passive"))
    )
    (net (code "555") (name "REL_RAW_62") (class "Default")
      (node (ref "R298") (pin "1") (pinfunction "1_1") (pintype "passive"))
      (node (ref "R314") (pin "1") (pinfunction "1_1") (pintype "passive"))
      (node (ref "VD177") (pin "C") (pinfunction "C_C") (pintype "passive"))
      (node (ref "XP10") (pin "14") (pinfunction "14_14") (pintype "passive"))
    )
    (net (code "556") (name "REL_RAW_63") (class "Default")
      (node (ref "R299") (pin "1") (pinfunction "1_1") (pintype "passive"))
      (node (ref "R315") (pin "1") (pinfunction "1_1") (pintype "passive"))
      (node (ref "VD178") (pin "C") (pinfunction "C_C") (pintype "passive"))
      (node (ref "XP10") (pin "15") (pinfunction "15_15") (pintype "passive"))
    )
    (net (code "557") (name "REL_RAW_64") (class "Default")
      (node (ref "R300") (pin "1") (pinfunction "1_1") (pintype "passive"))
      (node (ref "R316") (pin "1") (pinfunction "1_1") (pintype "passive"))
      (node (ref "VD179") (pin "C") (pinfunction "C_C") (pintype "passive"))
      (node (ref "XP10") (pin "16") (pinfunction "16_16") (pintype "passive"))
    )
    (net (code "558") (name "RST") (class "Default")
      (node (ref "DD1") (pin "14") (pinfunction "NRST_14") (pintype "bidirectional"))
      (node (ref "Z8") (pin "3") (pinfunction "3_3") (pintype "passive"))
    )
    (net (code "559") (name "SPEEDOMETER") (class "Default")
      (node (ref "DD1") (pin "40") (pinfunction "PE9(FSMC_D6/TIM1_CH1)*_40") (pintype "bidirectional"))
      (node (ref "Z40") (pin "3") (pinfunction "3_3") (pintype "passive"))
    )
    (net (code "560") (name "SR_IN_NSS") (class "Default")
      (node (ref "DD10") (pin "15") (pinfunction "INH_15") (pintype "input"))
      (node (ref "DD11") (pin "15") (pinfunction "INH_15") (pintype "input"))
      (node (ref "DD4") (pin "15") (pinfunction "INH_15") (pintype "input"))
      (node (ref "DD5") (pin "15") (pinfunction "INH_15") (pintype "input"))
      (node (ref "DD6") (pin "15") (pinfunction "INH_15") (pintype "input"))
      (node (ref "DD7") (pin "15") (pinfunction "INH_15") (pintype "input"))
      (node (ref "DD8") (pin "15") (pinfunction "INH_15") (pintype "input"))
      (node (ref "DD9") (pin "15") (pinfunction "INH_15") (pintype "input"))
      (node (ref "R16") (pin "1") (pinfunction "1_1") (pintype "passive"))
    )
    (net (code "561") (name "SR_MISO") (class "Default")
      (node (ref "DD11") (pin "9") (pinfunction "QH_9") (pintype "output"))
      (node (ref "R18") (pin "1") (pinfunction "1_1") (pintype "passive"))
    )
    (net (code "562") (name "SR_MOSI") (class "Default")
      (node (ref "DD12") (pin "14") (pinfunction "SER_14") (pintype "input"))
      (node (ref "R19") (pin "1") (pinfunction "1_1") (pintype "passive"))
    )
    (net (code "563") (name "SR_OUT_1") (class "Default")
      (node (ref "DD4") (pin "9") (pinfunction "QH_9") (pintype "output"))
      (node (ref "DD5") (pin "10") (pinfunction "SER_10") (pintype "input"))
    )
    (net (code "564") (name "SR_OUT_2") (class "Default")
      (node (ref "DD5") (pin "9") (pinfunction "QH_9") (pintype "output"))
      (node (ref "DD6") (pin "10") (pinfunction "SER_10") (pintype "input"))
    )
    (net (code "565") (name "SR_OUT_3") (class "Default")
      (node (ref "DD6") (pin "9") (pinfunction "QH_9") (pintype "output"))
      (node (ref "DD7") (pin "10") (pinfunction "SER_10") (pintype "input"))
    )
    (net (code "566") (name "SR_OUT_4") (class "Default")
      (node (ref "DD7") (pin "9") (pinfunction "QH_9") (pintype "output"))
      (node (ref "DD8") (pin "10") (pinfunction "SER_10") (pintype "input"))
    )
    (net (code "567") (name "SR_OUT_5") (class "Default")
      (node (ref "DD8") (pin "9") (pinfunction "QH_9") (pintype "output"))
      (node (ref "DD9") (pin "10") (pinfunction "SER_10") (pintype "input"))
    )
    (net (code "568") (name "SR_OUT_6") (class "Default")
      (node (ref "DD10") (pin "10") (pinfunction "SER_10") (pintype "input"))
      (node (ref "DD9") (pin "9") (pinfunction "QH_9") (pintype "output"))
    )
    (net (code "569") (name "SR_OUT_7") (class "Default")
      (node (ref "DD10") (pin "9") (pinfunction "QH_9") (pintype "output"))
      (node (ref "DD11") (pin "10") (pinfunction "SER_10") (pintype "input"))
    )
    (net (code "570") (name "SR_OUT_NSS") (class "Default")
      (node (ref "DD12") (pin "12") (pinfunction "STCP_12") (pintype "input"))
      (node (ref "R22") (pin "1") (pinfunction "1_1") (pintype "passive"))
    )
    (net (code "571") (name "SR_SCK") (class "Default")
      (node (ref "DD10") (pin "2") (pinfunction "CLK_2") (pintype "input"))
      (node (ref "DD11") (pin "2") (pinfunction "CLK_2") (pintype "input"))
      (node (ref "DD12") (pin "11") (pinfunction "SHCP_11") (pintype "input"))
      (node (ref "DD4") (pin "2") (pinfunction "CLK_2") (pintype "input"))
      (node (ref "DD5") (pin "2") (pinfunction "CLK_2") (pintype "input"))
      (node (ref "DD6") (pin "2") (pinfunction "CLK_2") (pintype "input"))
      (node (ref "DD7") (pin "2") (pinfunction "CLK_2") (pintype "input"))
      (node (ref "DD8") (pin "2") (pinfunction "CLK_2") (pintype "input"))
      (node (ref "DD9") (pin "2") (pinfunction "CLK_2") (pintype "input"))
      (node (ref "R17") (pin "1") (pinfunction "1_1") (pintype "passive"))
    )
    (net (code "572") (name "TACHOMETER") (class "Default")
      (node (ref "DD1") (pin "59") (pinfunction "PD12(FSMC_A17/USART3_RTS/TIM4_CH1)*_59") (pintype "bidirectional"))
      (node (ref "Z38") (pin "3") (pinfunction "3_3") (pintype "passive"))
    )
    (net (code "573") (name "TACHO_RAW") (class "Default")
      (node (ref "R124") (pin "2") (pinfunction "2_2") (pintype "passive"))
      (node (ref "XP5") (pin "1") (pinfunction "1_1") (pintype "passive"))
    )
    (net (code "574") (name "USART_FROM_MCU") (class "Default")
      (node (ref "DA17") (pin "10") (pinfunction "T2IN_10") (pintype "input"))
      (node (ref "DD1") (pin "68") (pinfunction "PA9(USART1_TX/TIM1_CH2)*_68") (pintype "bidirectional"))
    )
    (net (code "575") (name "USART_TO_MCU") (class "Default")
      (node (ref "DA17") (pin "9") (pinfunction "R2OUT_9") (pintype "output"))
      (node (ref "DD1") (pin "69") (pinfunction "PA10(USART1_RX/TIM1_CH3)*_69") (pintype "bidirectional"))
    )
    (net (code "576") (name "USBDM") (class "Default")
      (node (ref "DA15") (pin "3") (pinfunction "D2_3") (pintype "bidirectional"))
      (node (ref "DD1") (pin "70") (pinfunction "PA11(USBDM/CAN_RX/USART1_CTS/TIM1_CH4)*_70") (pintype "bidirectional"))
    )
    (net (code "577") (name "USBDP") (class "Default")
      (node (ref "DA15") (pin "1") (pinfunction "D1_1") (pintype "bidirectional"))
      (node (ref "DD1") (pin "71") (pinfunction "PA12(USBDP/CAN_TX/USART1_RTS/TIM1_ETR)*_71") (pintype "bidirectional"))
    )
    (net (code "578") (name "USB_DISCOVERY") (class "Default")
      (node (ref "DD1") (pin "45") (pinfunction "PE14(FSMC_D11/TIM1_CH4)*_45") (pintype "bidirectional"))
      (node (ref "Z49") (pin "3") (pinfunction "3_3") (pintype "passive"))
    )
    (net (code "579") (name "USB_PRESENT") (class "Default")
      (node (ref "DD1") (pin "46") (pinfunction "PE15(FSMC_D12/TIM1_BKIN)*_46") (pintype "bidirectional"))
      (node (ref "Z48") (pin "3") (pinfunction "3_3") (pintype "passive"))
    )
    (net (code "580") (name "VCC_DRV1") (class "Default")
      (node (ref "D20") (pin "TAB") (pinfunction "VCC_TAB") (pintype "power_in"))
      (node (ref "XP11") (pin "2") (pinfunction "2_2") (pintype "passive"))
      (node (ref "XP11") (pin "3") (pinfunction "3_3") (pintype "passive"))
    )
    (net (code "581") (name "VCC_DRV2") (class "Default")
      (node (ref "D21") (pin "TAB") (pinfunction "VCC_TAB") (pintype "power_in"))
      (node (ref "XP11") (pin "6") (pinfunction "6_6") (pintype "passive"))
      (node (ref "XP11") (pin "7") (pinfunction "7_7") (pintype "passive"))
    )
    (net (code "582") (name "VCC_DRV3") (class "Default")
      (node (ref "D22") (pin "TAB") (pinfunction "VCC_TAB") (pintype "power_in"))
      (node (ref "XP11") (pin "10") (pinfunction "10_10") (pintype "passive"))
      (node (ref "XP11") (pin "11") (pinfunction "11_11") (pintype "passive"))
    )
    (net (code "583") (name "VCC_DRV4") (class "Default")
      (node (ref "D23") (pin "TAB") (pinfunction "VCC_TAB") (pintype "power_in"))
      (node (ref "XP11") (pin "14") (pinfunction "14_14") (pintype "passive"))
      (node (ref "XP11") (pin "15") (pinfunction "15_15") (pintype "passive"))
    )
    (net (code "584") (name "VCC_DRV5") (class "Default")
      (node (ref "D24") (pin "TAB") (pinfunction "VCC_TAB") (pintype "power_in"))
      (node (ref "XP11") (pin "18") (pinfunction "18_18") (pintype "passive"))
      (node (ref "XP11") (pin "19") (pinfunction "19_19") (pintype "passive"))
    )
    (net (code "585") (name "VCC_DRV6") (class "Default")
      (node (ref "D25") (pin "TAB") (pinfunction "VCC_TAB") (pintype "power_in"))
      (node (ref "XP11") (pin "22") (pinfunction "22_22") (pintype "passive"))
      (node (ref "XP11") (pin "23") (pinfunction "23_23") (pintype "passive"))
    )
    (net (code "586") (name "VCC_DRV7") (class "Default")
      (node (ref "D26") (pin "TAB") (pinfunction "VCC_TAB") (pintype "power_in"))
      (node (ref "XP11") (pin "26") (pinfunction "26_26") (pintype "passive"))
      (node (ref "XP11") (pin "27") (pinfunction "27_27") (pintype "passive"))
    )
    (net (code "587") (name "VCC_DRV8") (class "Default")
      (node (ref "D27") (pin "TAB") (pinfunction "VCC_TAB") (pintype "power_in"))
      (node (ref "XP11") (pin "30") (pinfunction "30_30") (pintype "passive"))
      (node (ref "XP11") (pin "31") (pinfunction "31_31") (pintype "passive"))
    )
    (net (code "588") (name "Z_CHECK") (class "Default")
      (node (ref "D5") (pin "4") (pinfunction "OUT1_4") (pintype "power_in"))
      (node (ref "D5") (pin "5") (pinfunction "OUT2_5") (pintype "power_in"))
      (node (ref "VD116") (pin "A") (pinfunction "A_A") (pintype "passive"))
      (node (ref "VD117") (pin "A") (pinfunction "A_A") (pintype "passive"))
      (node (ref "VD118") (pin "A") (pinfunction "A_A") (pintype "passive"))
      (node (ref "VD119") (pin "A") (pinfunction "A_A") (pintype "passive"))
      (node (ref "VD120") (pin "A") (pinfunction "A_A") (pintype "passive"))
      (node (ref "VD121") (pin "A") (pinfunction "A_A") (pintype "passive"))
      (node (ref "VD122") (pin "A") (pinfunction "A_A") (pintype "passive"))
      (node (ref "VD123") (pin "A") (pinfunction "A_A") (pintype "passive"))
      (node (ref "VD124") (pin "A") (pinfunction "A_A") (pintype "passive"))
      (node (ref "VD125") (pin "A") (pinfunction "A_A") (pintype "passive"))
      (node (ref "VD126") (pin "A") (pinfunction "A_A") (pintype "passive"))
      (node (ref "VD127") (pin "A") (pinfunction "A_A") (pintype "passive"))
      (node (ref "VD128") (pin "A") (pinfunction "A_A") (pintype "passive"))
      (node (ref "VD129") (pin "A") (pinfunction "A_A") (pintype "passive"))
      (node (ref "VD130") (pin "A") (pinfunction "A_A") (pintype "passive"))
      (node (ref "VD131") (pin "A") (pinfunction "A_A") (pintype "passive"))
      (node (ref "VD148") (pin "A") (pinfunction "A_A") (pintype "passive"))
      (node (ref "VD149") (pin "A") (pinfunction "A_A") (pintype "passive"))
      (node (ref "VD150") (pin "A") (pinfunction "A_A") (pintype "passive"))
      (node (ref "VD151") (pin "A") (pinfunction "A_A") (pintype "passive"))
      (node (ref "VD152") (pin "A") (pinfunction "A_A") (pintype "passive"))
      (node (ref "VD153") (pin "A") (pinfunction "A_A") (pintype "passive"))
      (node (ref "VD154") (pin "A") (pinfunction "A_A") (pintype "passive"))
      (node (ref "VD155") (pin "A") (pinfunction "A_A") (pintype "passive"))
      (node (ref "VD156") (pin "A") (pinfunction "A_A") (pintype "passive"))
      (node (ref "VD157") (pin "A") (pinfunction "A_A") (pintype "passive"))
      (node (ref "VD158") (pin "A") (pinfunction "A_A") (pintype "passive"))
      (node (ref "VD159") (pin "A") (pinfunction "A_A") (pintype "passive"))
      (node (ref "VD160") (pin "A") (pinfunction "A_A") (pintype "passive"))
      (node (ref "VD161") (pin "A") (pinfunction "A_A") (pintype "passive"))
      (node (ref "VD162") (pin "A") (pinfunction "A_A") (pintype "passive"))
      (node (ref "VD163") (pin "A") (pinfunction "A_A") (pintype "passive"))
      (node (ref "VD180") (pin "A") (pinfunction "A_A") (pintype "passive"))
      (node (ref "VD181") (pin "A") (pinfunction "A_A") (pintype "passive"))
      (node (ref "VD182") (pin "A") (pinfunction "A_A") (pintype "passive"))
      (node (ref "VD183") (pin "A") (pinfunction "A_A") (pintype "passive"))
      (node (ref "VD184") (pin "A") (pinfunction "A_A") (pintype "passive"))
      (node (ref "VD185") (pin "A") (pinfunction "A_A") (pintype "passive"))
      (node (ref "VD186") (pin "A") (pinfunction "A_A") (pintype "passive"))
      (node (ref "VD187") (pin "A") (pinfunction "A_A") (pintype "passive"))
      (node (ref "VD188") (pin "A") (pinfunction "A_A") (pintype "passive"))
      (node (ref "VD189") (pin "A") (pinfunction "A_A") (pintype "passive"))
      (node (ref "VD190") (pin "A") (pinfunction "A_A") (pintype "passive"))
      (node (ref "VD191") (pin "A") (pinfunction "A_A") (pintype "passive"))
      (node (ref "VD192") (pin "A") (pinfunction "A_A") (pintype "passive"))
      (node (ref "VD193") (pin "A") (pinfunction "A_A") (pintype "passive"))
      (node (ref "VD194") (pin "A") (pinfunction "A_A") (pintype "passive"))
      (node (ref "VD195") (pin "A") (pinfunction "A_A") (pintype "passive"))
      (node (ref "VD82") (pin "A") (pinfunction "A_A") (pintype "passive"))
      (node (ref "VD83") (pin "A") (pinfunction "A_A") (pintype "passive"))
      (node (ref "VD84") (pin "A") (pinfunction "A_A") (pintype "passive"))
      (node (ref "VD85") (pin "A") (pinfunction "A_A") (pintype "passive"))
      (node (ref "VD86") (pin "A") (pinfunction "A_A") (pintype "passive"))
      (node (ref "VD87") (pin "A") (pinfunction "A_A") (pintype "passive"))
      (node (ref "VD88") (pin "A") (pinfunction "A_A") (pintype "passive"))
      (node (ref "VD89") (pin "A") (pinfunction "A_A") (pintype "passive"))
      (node (ref "VD90") (pin "A") (pinfunction "A_A") (pintype "passive"))
      (node (ref "VD91") (pin "A") (pinfunction "A_A") (pintype "passive"))
      (node (ref "VD92") (pin "A") (pinfunction "A_A") (pintype "passive"))
      (node (ref "VD93") (pin "A") (pinfunction "A_A") (pintype "passive"))
      (node (ref "VD94") (pin "A") (pinfunction "A_A") (pintype "passive"))
      (node (ref "VD95") (pin "A") (pinfunction "A_A") (pintype "passive"))
      (node (ref "VD96") (pin "A") (pinfunction "A_A") (pintype "passive"))
      (node (ref "VD97") (pin "A") (pinfunction "A_A") (pintype "passive"))
    )
    (net (code "589") (name "Z_CHECK_TOGGLE") (class "Default")
      (node (ref "R24") (pin "1") (pinfunction "1_1") (pintype "passive"))
      (node (ref "VT2") (pin "B") (pinfunction "B_B") (pintype "passive"))
    )
    (net (code "590") (name "unconnected-(DA4A-BAL-Pad5)") (class "Default")
      (node (ref "DA4") (pin "5") (pinfunction "BAL_5") (pintype "bidirectional"))
    )
    (net (code "591") (name "unconnected-(DA4A-BALSTR-Pad6)") (class "Default")
      (node (ref "DA4") (pin "6") (pinfunction "BALSTR_6") (pintype "bidirectional"))
    )
    (net (code "592") (name "unconnected-(DA5A-BAL-Pad5)") (class "Default")
      (node (ref "DA5") (pin "5") (pinfunction "BAL_5") (pintype "bidirectional"))
    )
    (net (code "593") (name "unconnected-(DA5A-BALSTR-Pad6)") (class "Default")
      (node (ref "DA5") (pin "6") (pinfunction "BALSTR_6") (pintype "bidirectional"))
    )
    (net (code "594") (name "unconnected-(DA6A-BAL-Pad5)") (class "Default")
      (node (ref "DA6") (pin "5") (pinfunction "BAL_5") (pintype "bidirectional"))
    )
    (net (code "595") (name "unconnected-(DA6A-BALSTR-Pad6)") (class "Default")
      (node (ref "DA6") (pin "6") (pinfunction "BALSTR_6") (pintype "bidirectional"))
    )
    (net (code "596") (name "unconnected-(DA7A-Q-Pad13)") (class "Default")
      (node (ref "DA7") (pin "13") (pinfunction "Q_13") (pintype "output"))
    )
    (net (code "597") (name "unconnected-(DA7B-Q-Pad5)") (class "Default")
      (node (ref "DA7") (pin "5") (pinfunction "Q_5") (pintype "output"))
    )
    (net (code "598") (name "unconnected-(DA8A-Q-Pad13)") (class "Default")
      (node (ref "DA8") (pin "13") (pinfunction "Q_13") (pintype "output"))
    )
    (net (code "599") (name "unconnected-(DA8B-Q-Pad5)") (class "Default")
      (node (ref "DA8") (pin "5") (pinfunction "Q_5") (pintype "output"))
    )
    (net (code "600") (name "unconnected-(DA9A-Q-Pad13)") (class "Default")
      (node (ref "DA9") (pin "13") (pinfunction "Q_13") (pintype "output"))
    )
    (net (code "601") (name "unconnected-(DA9B-Q-Pad5)") (class "Default")
      (node (ref "DA9") (pin "5") (pinfunction "Q_5") (pintype "output"))
    )
    (net (code "602") (name "unconnected-(DA11-FAULT-Pad6)") (class "Default")
      (node (ref "DA11") (pin "6") (pinfunction "FAULT_6") (pintype "open_collector"))
    )
    (net (code "603") (name "unconnected-(DA17-R1IN-Pad13)") (class "Default")
      (node (ref "DA17") (pin "13") (pinfunction "R1IN_13") (pintype "input"))
    )
    (net (code "604") (name "unconnected-(DA17-R1OUT-Pad12)") (class "Default")
      (node (ref "DA17") (pin "12") (pinfunction "R1OUT_12") (pintype "output"))
    )
    (net (code "605") (name "unconnected-(DA17-T1IN-Pad11)") (class "Default")
      (node (ref "DA17") (pin "11") (pinfunction "T1IN_11") (pintype "input"))
    )
    (net (code "606") (name "unconnected-(DA17-T1OUT-Pad14)") (class "Default")
      (node (ref "DA17") (pin "14") (pinfunction "T1OUT_14") (pintype "output"))
    )
    (net (code "607") (name "unconnected-(DD1-NC-Pad73)") (class "Default")
      (node (ref "DD1") (pin "73") (pinfunction "NC_73") (pintype "bidirectional"))
    )
    (net (code "608") (name "unconnected-(DD1-PA8(USART1_CK{slash}TIM1_CH1{slash}MCO)*-Pad67)") (class "Default")
      (node (ref "DD1") (pin "67") (pinfunction "PA8(USART1_CK/TIM1_CH1/MCO)*_67") (pintype "bidirectional"))
    )
    (net (code "609") (name "unconnected-(DD1-PB5(I2C1_SMBA{slash}SPI3_MOSI{slash}I2S3_SD{slash}TIM3_CH2{slash}SPI1_MOSI)-Pad91)") (class "Default")
      (node (ref "DD1") (pin "91") (pinfunction "PB5(I2C1_SMBA/SPI3_MOSI/I2S3_SD/TIM3_CH2/SPI1_MOSI)_91") (pintype "bidirectional"))
    )
    (net (code "610") (name "unconnected-(DD1-PB6(I2C1_SCL{slash}TIM4_CH1{slash}USART1_TX)*-Pad92)") (class "Default")
      (node (ref "DD1") (pin "92") (pinfunction "PB6(I2C1_SCL/TIM4_CH1/USART1_TX)*_92") (pintype "bidirectional"))
    )
    (net (code "611") (name "unconnected-(DD1-PB7(I2C1_SDA{slash}FSMC_NADV{slash}TIM4_CH2{slash}USART1_RX)*-Pad93)") (class "Default")
      (node (ref "DD1") (pin "93") (pinfunction "PB7(I2C1_SDA/FSMC_NADV/TIM4_CH2/USART1_RX)*_93") (pintype "bidirectional"))
    )
    (net (code "612") (name "unconnected-(DD1-PB8(TIM4_CH3{slash}SDIO_D4{slash}I2C1_SCL{slash}CAN_RX)*-Pad95)") (class "Default")
      (node (ref "DD1") (pin "95") (pinfunction "PB8(TIM4_CH3/SDIO_D4/I2C1_SCL/CAN_RX)*_95") (pintype "bidirectional"))
    )
    (net (code "613") (name "unconnected-(DD1-PB9(TIM4_CH4{slash}SDIO_D5{slash}I2C1_SDA{slash}CAN_TX)*-Pad96)") (class "Default")
      (node (ref "DD1") (pin "96") (pinfunction "PB9(TIM4_CH4/SDIO_D5/I2C1_SDA/CAN_TX)*_96") (pintype "bidirectional"))
    )
    (net (code "614") (name "unconnected-(DD1-PC7(I2S3_MCK{slash}TIM8_CH2{slash}SDIO_D7{slash}TIM3_CH2)*-Pad64)") (class "Default")
      (node (ref "DD1") (pin "64") (pinfunction "PC7(I2S3_MCK/TIM8_CH2/SDIO_D7/TIM3_CH2)*_64") (pintype "bidirectional"))
    )
    (net (code "615") (name "unconnected-(DD1-PC8(TIM8_CH3{slash}SDIO_D0{slash}TIM3_CH3)*-Pad65)") (class "Default")
      (node (ref "DD1") (pin "65") (pinfunction "PC8(TIM8_CH3/SDIO_D0/TIM3_CH3)*_65") (pintype "bidirectional"))
    )
    (net (code "616") (name "unconnected-(DD1-PC9(TIM8_CH4{slash}SDIO_D1{slash}TIM3_CH4)*-Pad66)") (class "Default")
      (node (ref "DD1") (pin "66") (pinfunction "PC9(TIM8_CH4/SDIO_D1/TIM3_CH4)*_66") (pintype "bidirectional"))
    )
    (net (code "617") (name "unconnected-(DD1-PC10(UART4_TX{slash}SDIO_D2{slash}USART3_TX)*-Pad78)") (class "Default")
      (node (ref "DD1") (pin "78") (pinfunction "PC10(UART4_TX/SDIO_D2/USART3_TX)*_78") (pintype "bidirectional"))
    )
    (net (code "618") (name "unconnected-(DD1-PC11(UART4_RX{slash}SDIO_D3{slash}USART3_RX)*-Pad79)") (class "Default")
      (node (ref "DD1") (pin "79") (pinfunction "PC11(UART4_RX/SDIO_D3/USART3_RX)*_79") (pintype "bidirectional"))
    )
    (net (code "619") (name "unconnected-(DD1-PC12(UART5_TX{slash}SDIO_CK{slash}USART3_CK)*-Pad80)") (class "Default")
      (node (ref "DD1") (pin "80") (pinfunction "PC12(UART5_TX/SDIO_CK/USART3_CK)*_80") (pintype "bidirectional"))
    )
    (net (code "620") (name "unconnected-(DD1-PC13(TAMPER-RTC)-Pad7)") (class "Default")
      (node (ref "DD1") (pin "7") (pinfunction "PC13(TAMPER-RTC)_7") (pintype "bidirectional"))
    )
    (net (code "621") (name "unconnected-(DD1-PC14(OSC32_IN)-Pad8)") (class "Default")
      (node (ref "DD1") (pin "8") (pinfunction "PC14(OSC32_IN)_8") (pintype "bidirectional"))
    )
    (net (code "622") (name "unconnected-(DD1-PC15(OSC32_OUT)-Pad9)") (class "Default")
      (node (ref "DD1") (pin "9") (pinfunction "PC15(OSC32_OUT)_9") (pintype "bidirectional"))
    )
    (net (code "623") (name "unconnected-(DD1-PD2(TIM3_ETR{slash}UART5_RX{slash}SDIO_CMD)*-Pad83)") (class "Default")
      (node (ref "DD1") (pin "83") (pinfunction "PD2(TIM3_ETR/UART5_RX/SDIO_CMD)*_83") (pintype "bidirectional"))
    )
    (net (code "624") (name "unconnected-(DD1-PD3(FSMC_CLK{slash}USART2_CTS)*-Pad84)") (class "Default")
      (node (ref "DD1") (pin "84") (pinfunction "PD3(FSMC_CLK/USART2_CTS)*_84") (pintype "bidirectional"))
    )
    (net (code "625") (name "unconnected-(DD1-PD4(FSMC_NOE{slash}USART2_RTS)*-Pad85)") (class "Default")
      (node (ref "DD1") (pin "85") (pinfunction "PD4(FSMC_NOE/USART2_RTS)*_85") (pintype "bidirectional"))
    )
    (net (code "626") (name "unconnected-(DD1-PD5(FSMC_NWE{slash}USART2_TX)*-Pad86)") (class "Default")
      (node (ref "DD1") (pin "86") (pinfunction "PD5(FSMC_NWE/USART2_TX)*_86") (pintype "bidirectional"))
    )
    (net (code "627") (name "unconnected-(DD1-PD6(FSMC_NWAIT{slash}USART2_RX)*-Pad87)") (class "Default")
      (node (ref "DD1") (pin "87") (pinfunction "PD6(FSMC_NWAIT/USART2_RX)*_87") (pintype "bidirectional"))
    )
    (net (code "628") (name "unconnected-(DD1-PD7(FSMC_NE1{slash}FSMC_NCE2{slash}USART2_CK)*-Pad88)") (class "Default")
      (node (ref "DD1") (pin "88") (pinfunction "PD7(FSMC_NE1/FSMC_NCE2/USART2_CK)*_88") (pintype "bidirectional"))
    )
    (net (code "629") (name "unconnected-(DD1-PD8(FSMC_D13{slash}USART3_TX)*-Pad55)") (class "Default")
      (node (ref "DD1") (pin "55") (pinfunction "PD8(FSMC_D13/USART3_TX)*_55") (pintype "bidirectional"))
    )
    (net (code "630") (name "unconnected-(DD1-PD9(FSMC_D14{slash}USART3_RX)*-Pad56)") (class "Default")
      (node (ref "DD1") (pin "56") (pinfunction "PD9(FSMC_D14/USART3_RX)*_56") (pintype "bidirectional"))
    )
    (net (code "631") (name "unconnected-(DD1-PD10(FSMC_D15{slash}USART3_CK)*-Pad57)") (class "Default")
      (node (ref "DD1") (pin "57") (pinfunction "PD10(FSMC_D15/USART3_CK)*_57") (pintype "bidirectional"))
    )
    (net (code "632") (name "unconnected-(DD1-PD11(FSMC_A16{slash}USART3_CTS)*-Pad58)") (class "Default")
      (node (ref "DD1") (pin "58") (pinfunction "PD11(FSMC_A16/USART3_CTS)*_58") (pintype "bidirectional"))
    )
    (net (code "633") (name "unconnected-(DD1-PD13(FSMC_A18{slash}TIM4_CH2)*-Pad60)") (class "Default")
      (node (ref "DD1") (pin "60") (pinfunction "PD13(FSMC_A18/TIM4_CH2)*_60") (pintype "bidirectional"))
    )
    (net (code "634") (name "unconnected-(DD1-PD14(FSMC_D0{slash}TIM4_CH3)*-Pad61)") (class "Default")
      (node (ref "DD1") (pin "61") (pinfunction "PD14(FSMC_D0/TIM4_CH3)*_61") (pintype "bidirectional"))
    )
    (net (code "635") (name "unconnected-(DD1-PD15(FSMC_D1{slash}TIM4_CH4)*-Pad62)") (class "Default")
      (node (ref "DD1") (pin "62") (pinfunction "PD15(FSMC_D1/TIM4_CH4)*_62") (pintype "bidirectional"))
    )
    (net (code "636") (name "unconnected-(DD1-PE1(FSMC_NBL1)*-Pad98)") (class "Default")
      (node (ref "DD1") (pin "98") (pinfunction "PE1(FSMC_NBL1)*_98") (pintype "bidirectional"))
    )
    (net (code "637") (name "unconnected-(DD1-PE6(TRACED3{slash}FSMC_A22)*-Pad5)") (class "Default")
      (node (ref "DD1") (pin "5") (pinfunction "PE6(TRACED3/FSMC_A22)*_5") (pintype "bidirectional"))
    )
    (net (code "638") (name "unconnected-(DD1-PE7(FSMC_D4{slash}TIM1_ETR)*-Pad38)") (class "Default")
      (node (ref "DD1") (pin "38") (pinfunction "PE7(FSMC_D4/TIM1_ETR)*_38") (pintype "bidirectional"))
    )
    (net (code "639") (name "unconnected-(DD1-PE8(FSMC_D5{slash}TIM1_CH1N)*-Pad39)") (class "Default")
      (node (ref "DD1") (pin "39") (pinfunction "PE8(FSMC_D5/TIM1_CH1N)*_39") (pintype "bidirectional"))
    )
    (net (code "640") (name "unconnected-(DD1-PE10(FSMC_D7{slash}TIM1_CH2N)*-Pad41)") (class "Default")
      (node (ref "DD1") (pin "41") (pinfunction "PE10(FSMC_D7/TIM1_CH2N)*_41") (pintype "bidirectional"))
    )
    (net (code "641") (name "unconnected-(DD1-PE11(FSMC_D8{slash}TIM1_CH2)*-Pad42)") (class "Default")
      (node (ref "DD1") (pin "42") (pinfunction "PE11(FSMC_D8/TIM1_CH2)*_42") (pintype "bidirectional"))
    )
    (net (code "642") (name "unconnected-(DD1-PE12(FSMC_D9{slash}TIM1_CH3N)*-Pad43)") (class "Default")
      (node (ref "DD1") (pin "43") (pinfunction "PE12(FSMC_D9/TIM1_CH3N)*_43") (pintype "bidirectional"))
    )
    (net (code "643") (name "unconnected-(DD1-PE13(FSMC_D10{slash}TIM1_CH3)*-Pad44)") (class "Default")
      (node (ref "DD1") (pin "44") (pinfunction "PE13(FSMC_D10/TIM1_CH3)*_44") (pintype "bidirectional"))
    )
    (net (code "644") (name "unconnected-(DD4A-~{QH}-Pad7)") (class "Default")
      (node (ref "DD4") (pin "7") (pinfunction "~{QH}_7") (pintype "output"))
    )
    (net (code "645") (name "unconnected-(DD5A-~{QH}-Pad7)") (class "Default")
      (node (ref "DD5") (pin "7") (pinfunction "~{QH}_7") (pintype "output"))
    )
    (net (code "646") (name "unconnected-(DD6A-~{QH}-Pad7)") (class "Default")
      (node (ref "DD6") (pin "7") (pinfunction "~{QH}_7") (pintype "output"))
    )
    (net (code "647") (name "unconnected-(DD7A-~{QH}-Pad7)") (class "Default")
      (node (ref "DD7") (pin "7") (pinfunction "~{QH}_7") (pintype "output"))
    )
    (net (code "648") (name "unconnected-(DD8A-~{QH}-Pad7)") (class "Default")
      (node (ref "DD8") (pin "7") (pinfunction "~{QH}_7") (pintype "output"))
    )
    (net (code "649") (name "unconnected-(DD9A-~{QH}-Pad7)") (class "Default")
      (node (ref "DD9") (pin "7") (pinfunction "~{QH}_7") (pintype "output"))
    )
    (net (code "650") (name "unconnected-(DD10A-~{QH}-Pad7)") (class "Default")
      (node (ref "DD10") (pin "7") (pinfunction "~{QH}_7") (pintype "output"))
    )
    (net (code "651") (name "unconnected-(DD11A-~{QH}-Pad7)") (class "Default")
      (node (ref "DD11") (pin "7") (pinfunction "~{QH}_7") (pintype "output"))
    )
    (net (code "652") (name "unconnected-(DD12A-Q7S-Pad9)") (class "Default")
      (node (ref "DD12") (pin "9") (pinfunction "Q7S_9") (pintype "tri_state"))
    )
    (net (code "653") (name "unconnected-(XP5-Pad5)") (class "Default")
      (node (ref "XP5") (pin "5") (pinfunction "5_5") (pintype "passive"))
    )
    (net (code "654") (name "unconnected-(XP5-Pad7)") (class "Default")
      (node (ref "XP5") (pin "7") (pinfunction "7_7") (pintype "passive"))
    )
    (net (code "655") (name "unconnected-(XP5-Pad8)") (class "Default")
      (node (ref "XP5") (pin "8") (pinfunction "8_8") (pintype "passive"))
    )
    (net (code "656") (name "unconnected-(XP11-Pad33)") (class "Default")
      (node (ref "XP11") (pin "33") (pinfunction "33_33") (pintype "passive"))
    )
    (net (code "657") (name "unconnected-(XP11-Pad34)") (class "Default")
      (node (ref "XP11") (pin "34") (pinfunction "34_34") (pintype "passive"))
    )
    (net (code "658") (name "unconnected-(XP12-Pad5)") (class "Default")
      (node (ref "XP12") (pin "5") (pinfunction "5_5") (pintype "passive"))
    )
    (net (code "659") (name "unconnected-(XP12-Pad6)") (class "Default")
      (node (ref "XP12") (pin "6") (pinfunction "6_6") (pintype "passive"))
    )
    (net (code "660") (name "unconnected-(XP12-Pad7)") (class "Default")
      (node (ref "XP12") (pin "7") (pinfunction "7_7") (pintype "passive"))
    )
    (net (code "661") (name "unconnected-(XP12-Pad8)") (class "Default")
      (node (ref "XP12") (pin "8") (pinfunction "8_8") (pintype "passive"))
    )
    (net (code "662") (name "unconnected-(XS1-4-PadID)") (class "Default")
      (node (ref "XS1") (pin "ID") (pinfunction "4_ID") (pintype "passive"))
    )
    (net (code "663") (name "unconnected-(XS1-6-PadSHIELD1)") (class "Default")
      (node (ref "XS1") (pin "SHIELD1") (pinfunction "6_SHIELD1") (pintype "passive"))
    )
    (net (code "664") (name "unconnected-(XS1-7-PadSHIELD2)") (class "Default")
      (node (ref "XS1") (pin "SHIELD2") (pinfunction "7_SHIELD2") (pintype "passive"))
    )
    (net (code "665") (name "unconnected-(XS1-8-PadSHIELD3)") (class "Default")
      (node (ref "XS1") (pin "SHIELD3") (pinfunction "8_SHIELD3") (pintype "passive"))
    )
    (net (code "666") (name "unconnected-(XS1-9-PadSHIELD4)") (class "Default")
      (node (ref "XS1") (pin "SHIELD4") (pinfunction "9_SHIELD4") (pintype "passive"))
    )
    (net (code "667") (name "~{SR_OUT_ENABLE}") (class "Default")
      (node (ref "DD12") (pin "13") (pinfunction "~{OE}_13") (pintype "input"))
      (node (ref "R21") (pin "1") (pinfunction "1_1") (pintype "passive"))
      (node (ref "R333") (pin "1") (pinfunction "1_1") (pintype "passive"))
    )
    (net (code "668") (name "~{SR_SAMPLE}") (class "Default")
      (node (ref "DD10") (pin "1") (pinfunction "SH/~{LD}_1") (pintype "input"))
      (node (ref "DD11") (pin "1") (pinfunction "SH/~{LD}_1") (pintype "input"))
      (node (ref "DD4") (pin "1") (pinfunction "SH/~{LD}_1") (pintype "input"))
      (node (ref "DD5") (pin "1") (pinfunction "SH/~{LD}_1") (pintype "input"))
      (node (ref "DD6") (pin "1") (pinfunction "SH/~{LD}_1") (pintype "input"))
      (node (ref "DD7") (pin "1") (pinfunction "SH/~{LD}_1") (pintype "input"))
      (node (ref "DD8") (pin "1") (pinfunction "SH/~{LD}_1") (pintype "input"))
      (node (ref "DD9") (pin "1") (pinfunction "SH/~{LD}_1") (pintype "input"))
      (node (ref "R23") (pin "1") (pinfunction "1_1") (pintype "passive"))
    )
  )
)
